# cube.net
KiCad netlist of a schematic drawn in EAGLE
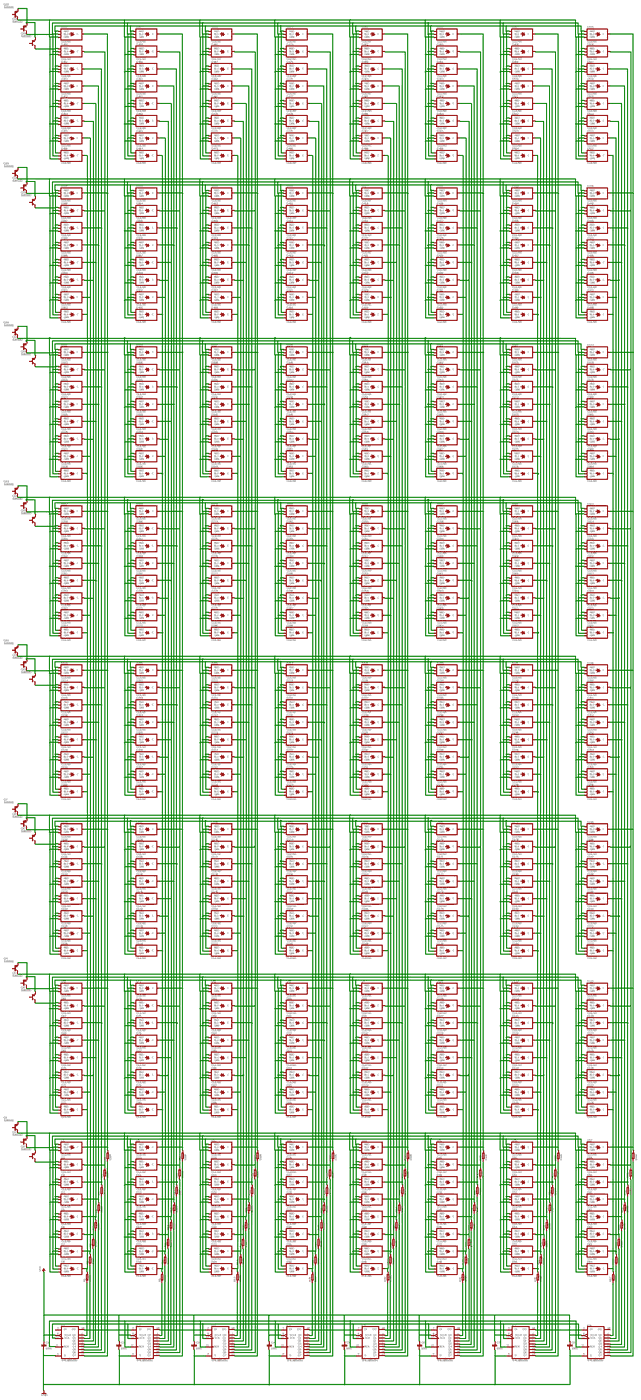
[diagram p0: schematic, sheet 1, overview]
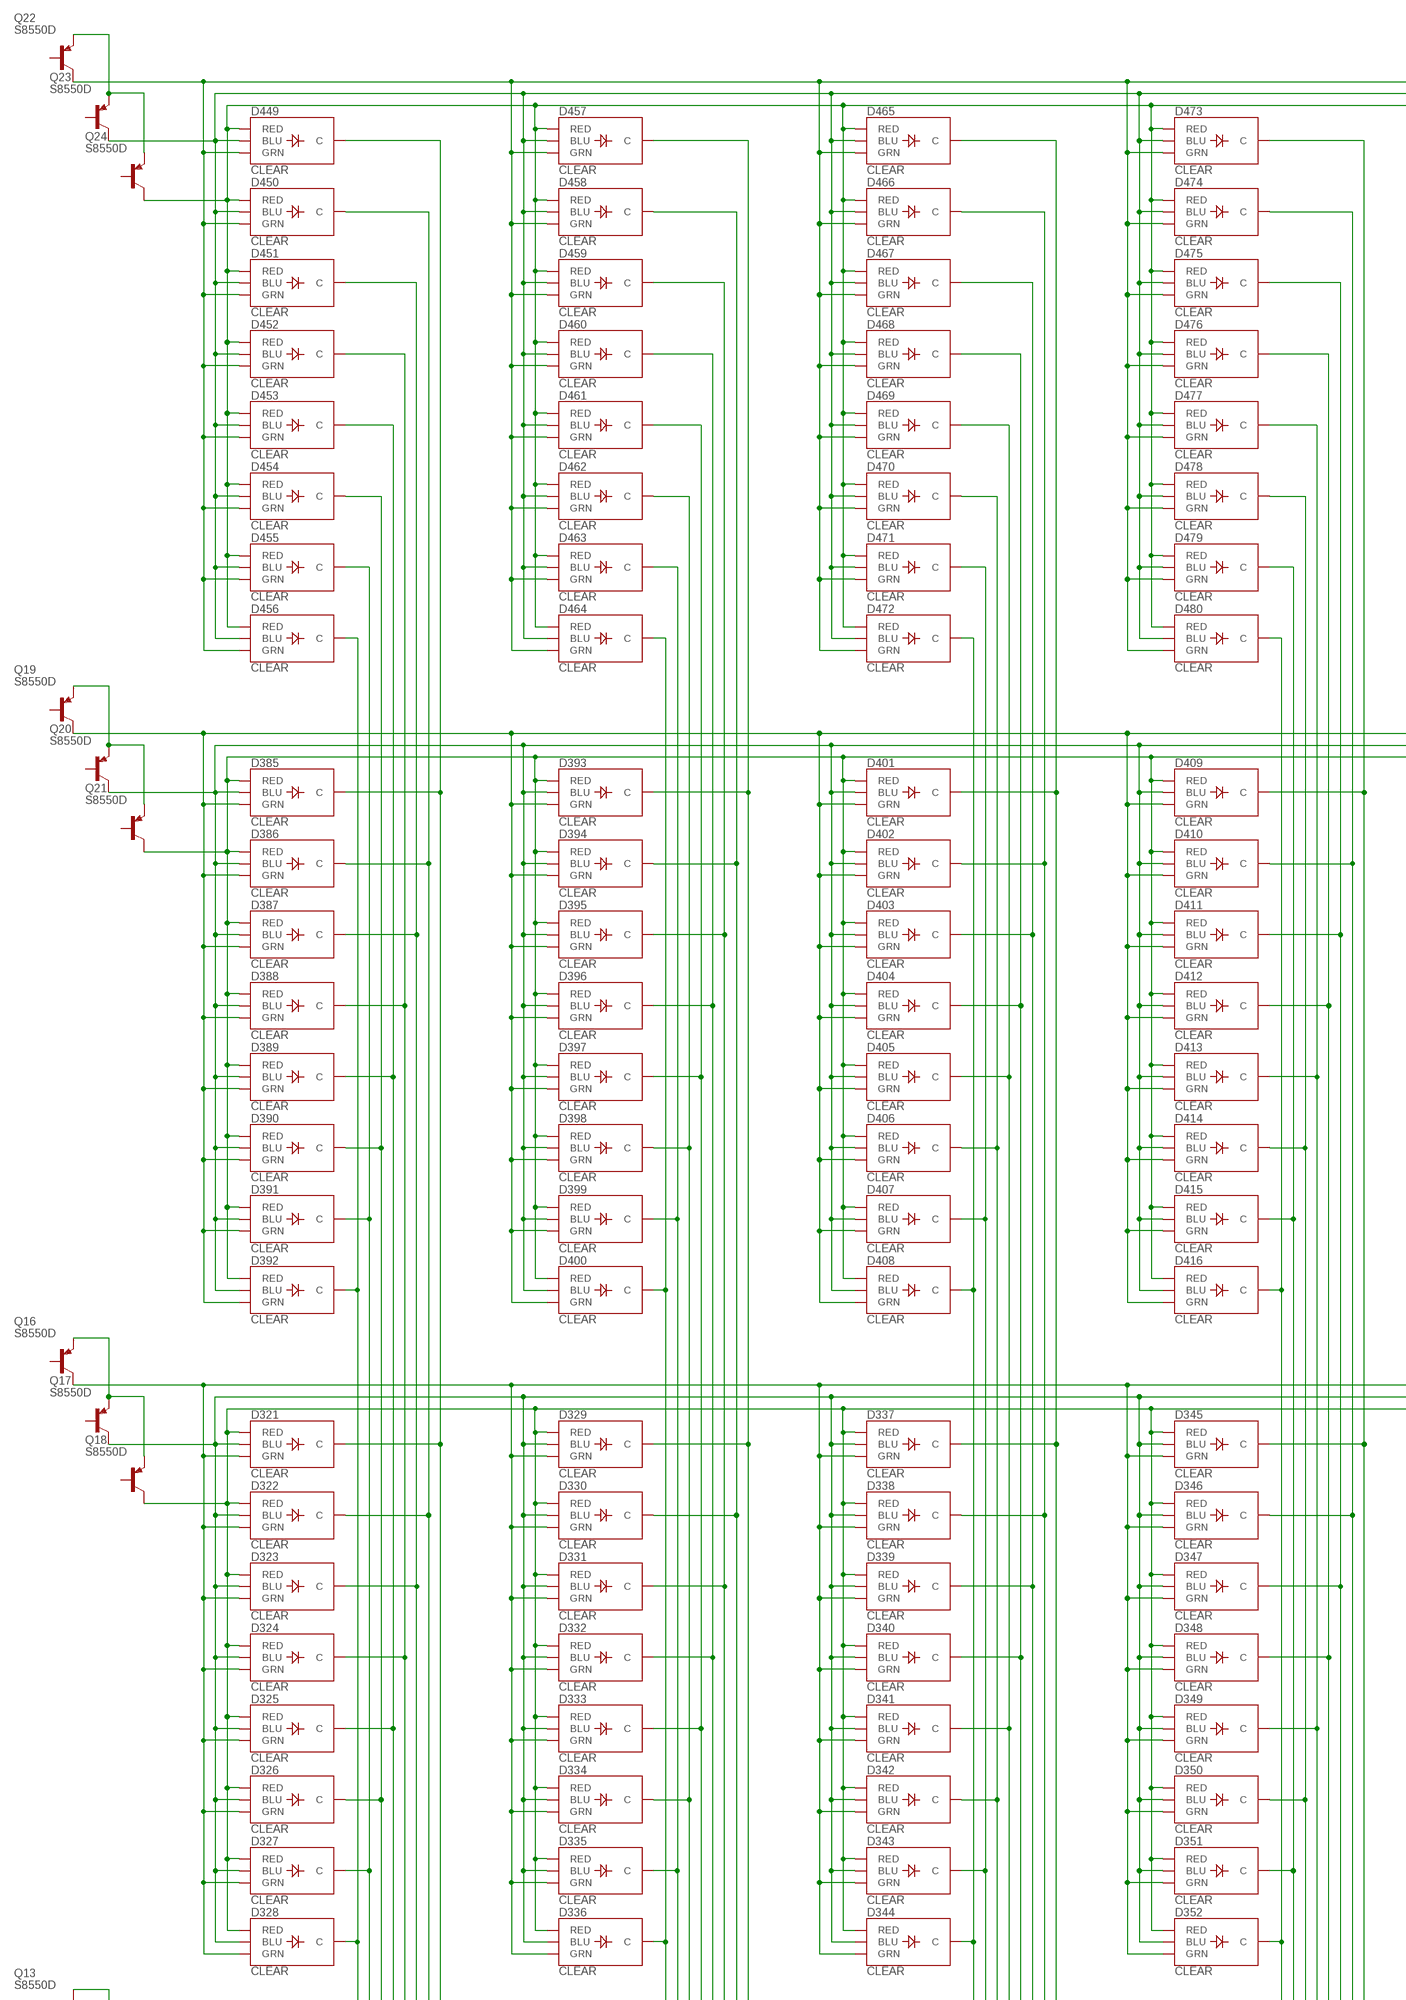
[diagram p1: schematic, sheet 1, part 1 of 8]
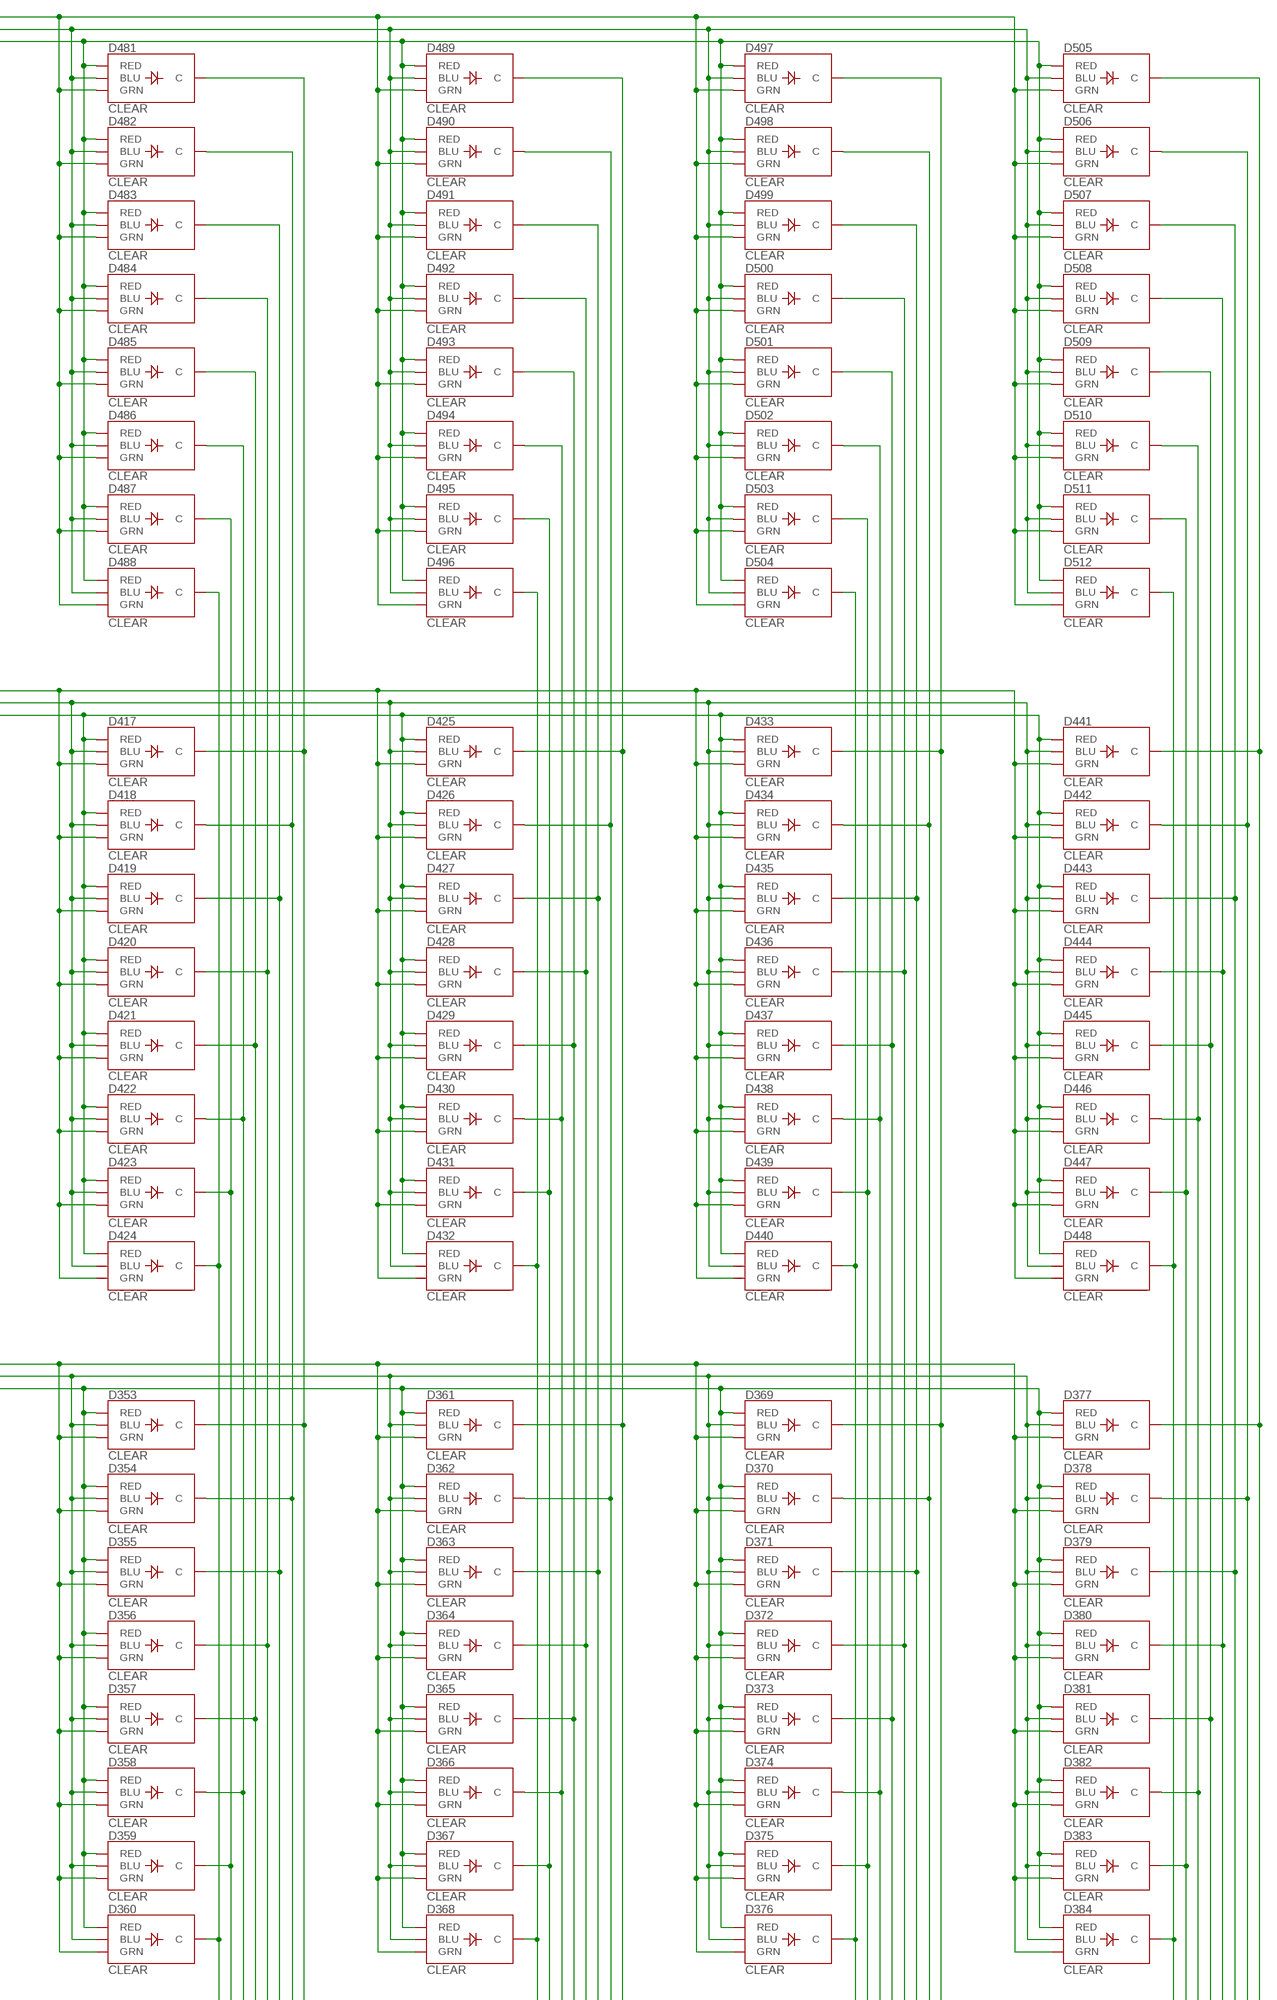
[diagram p2: schematic, sheet 1, part 2 of 8]
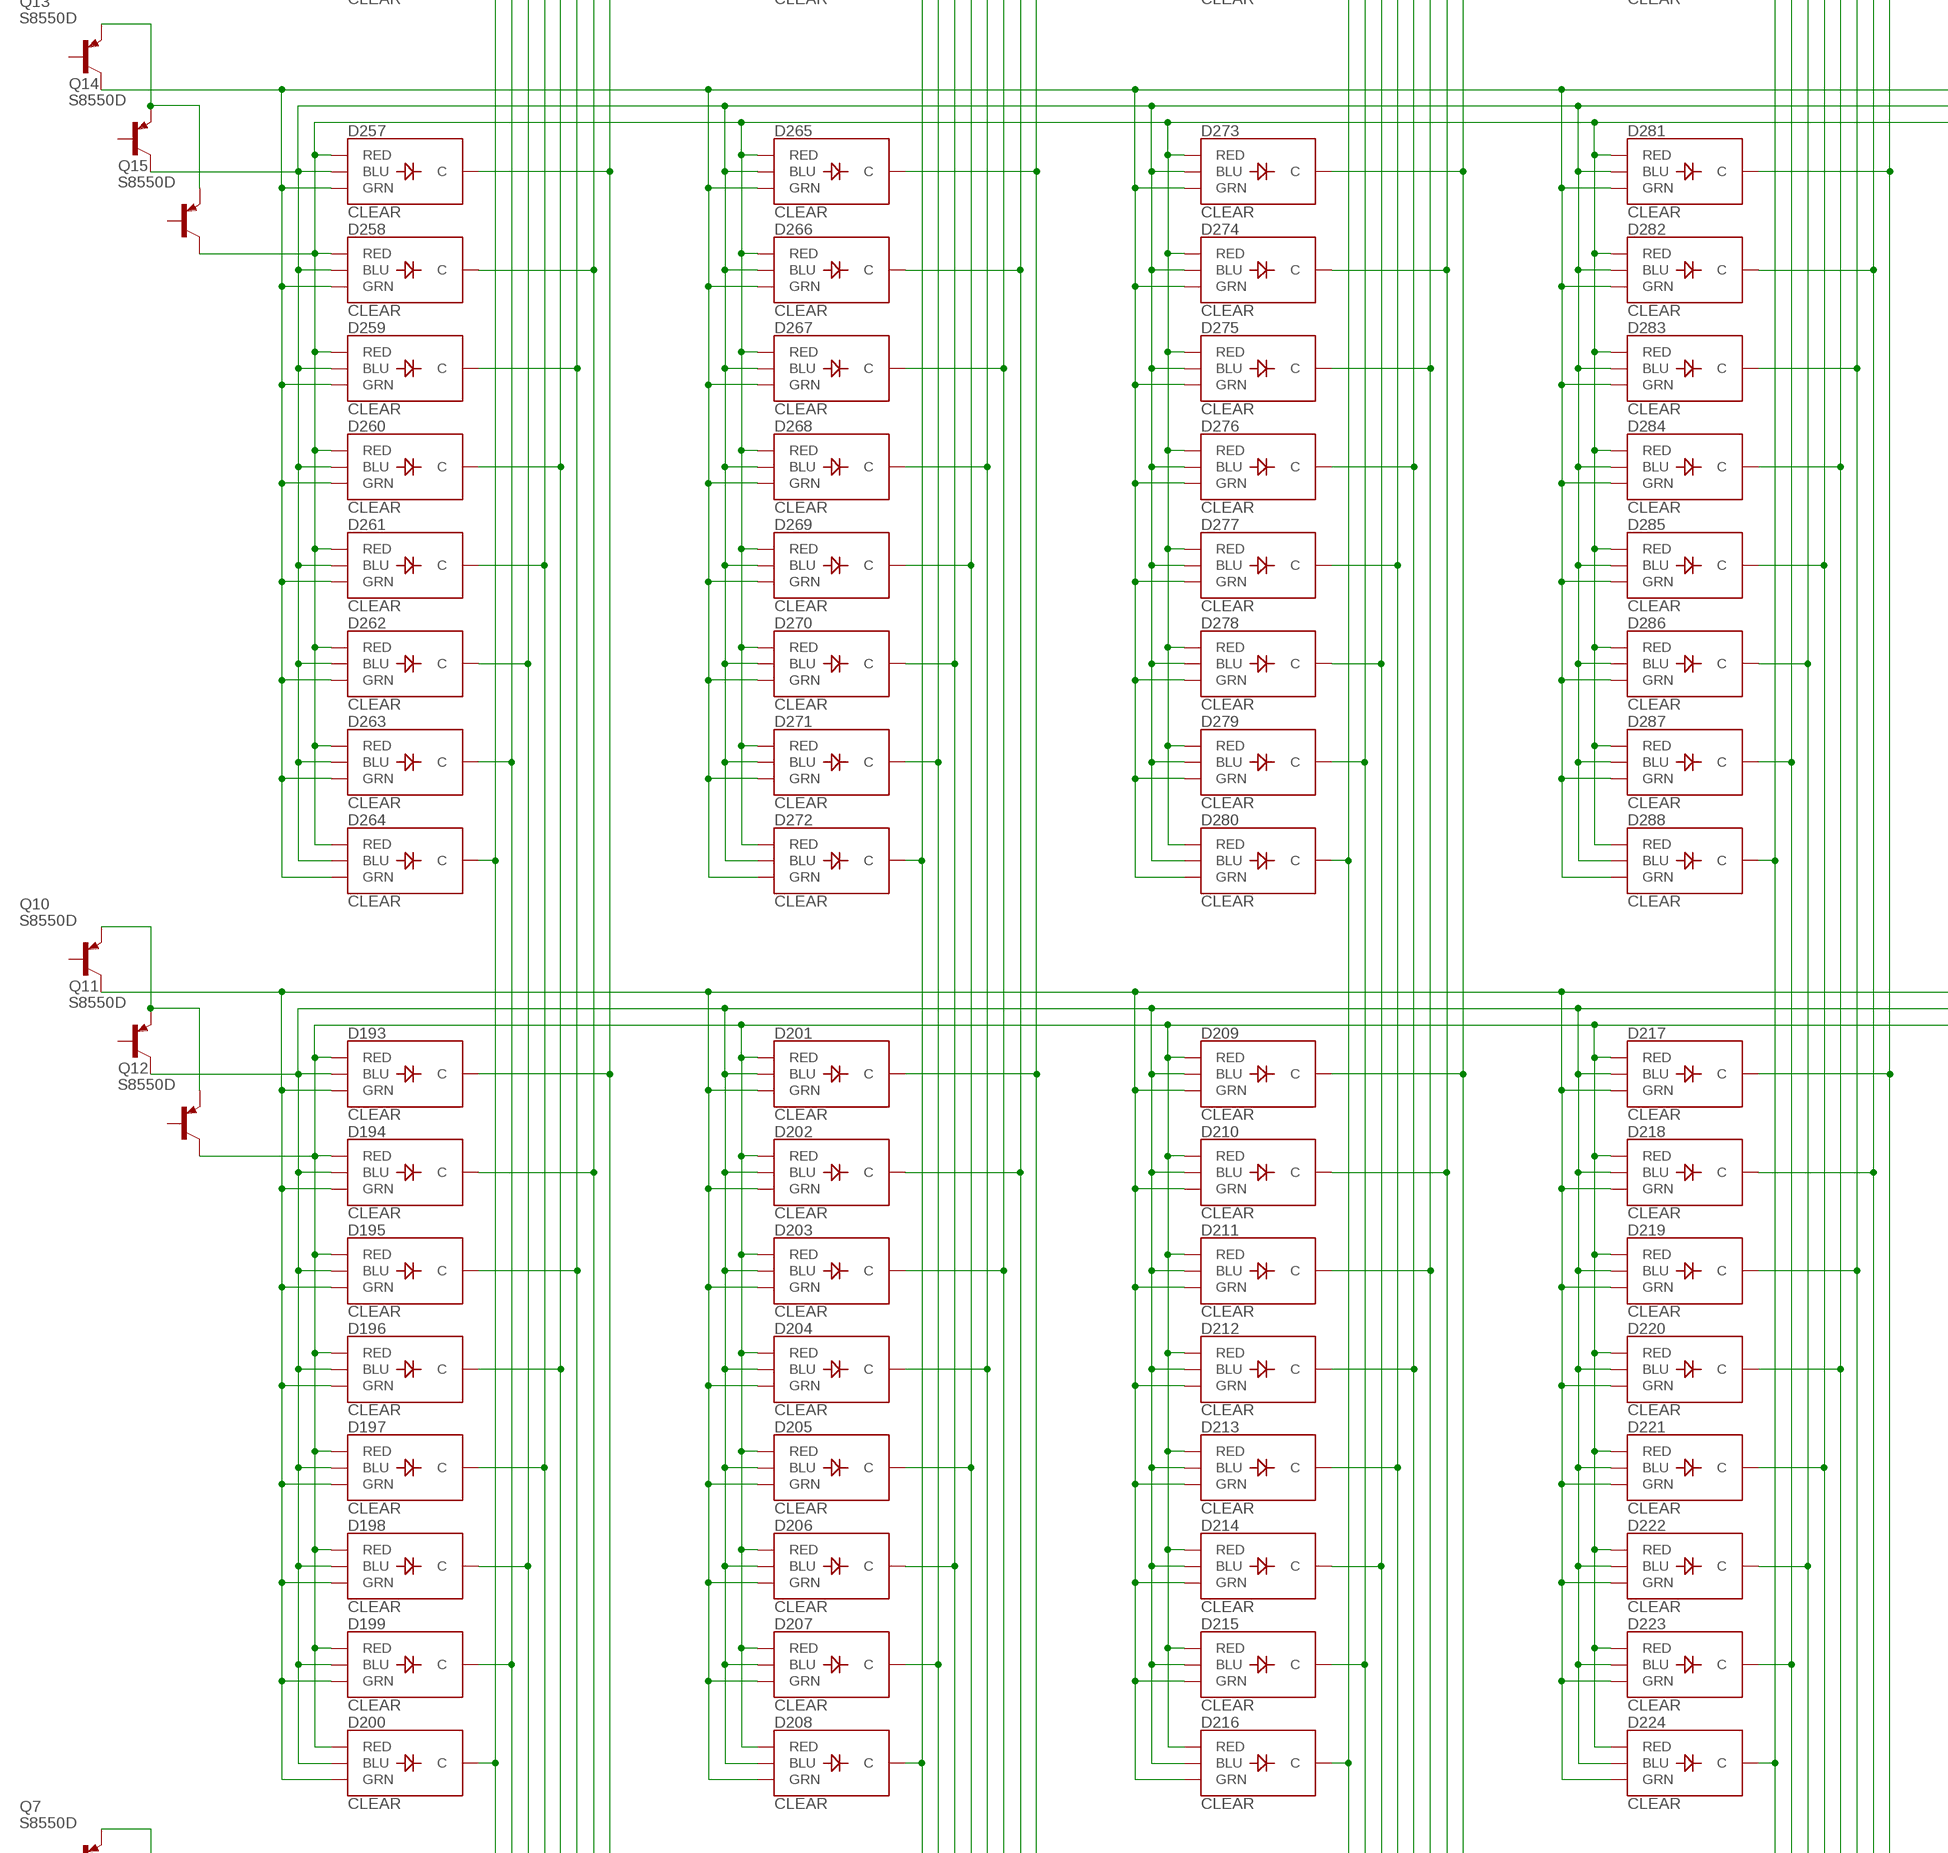
[diagram p3: schematic, sheet 1, part 3 of 8]
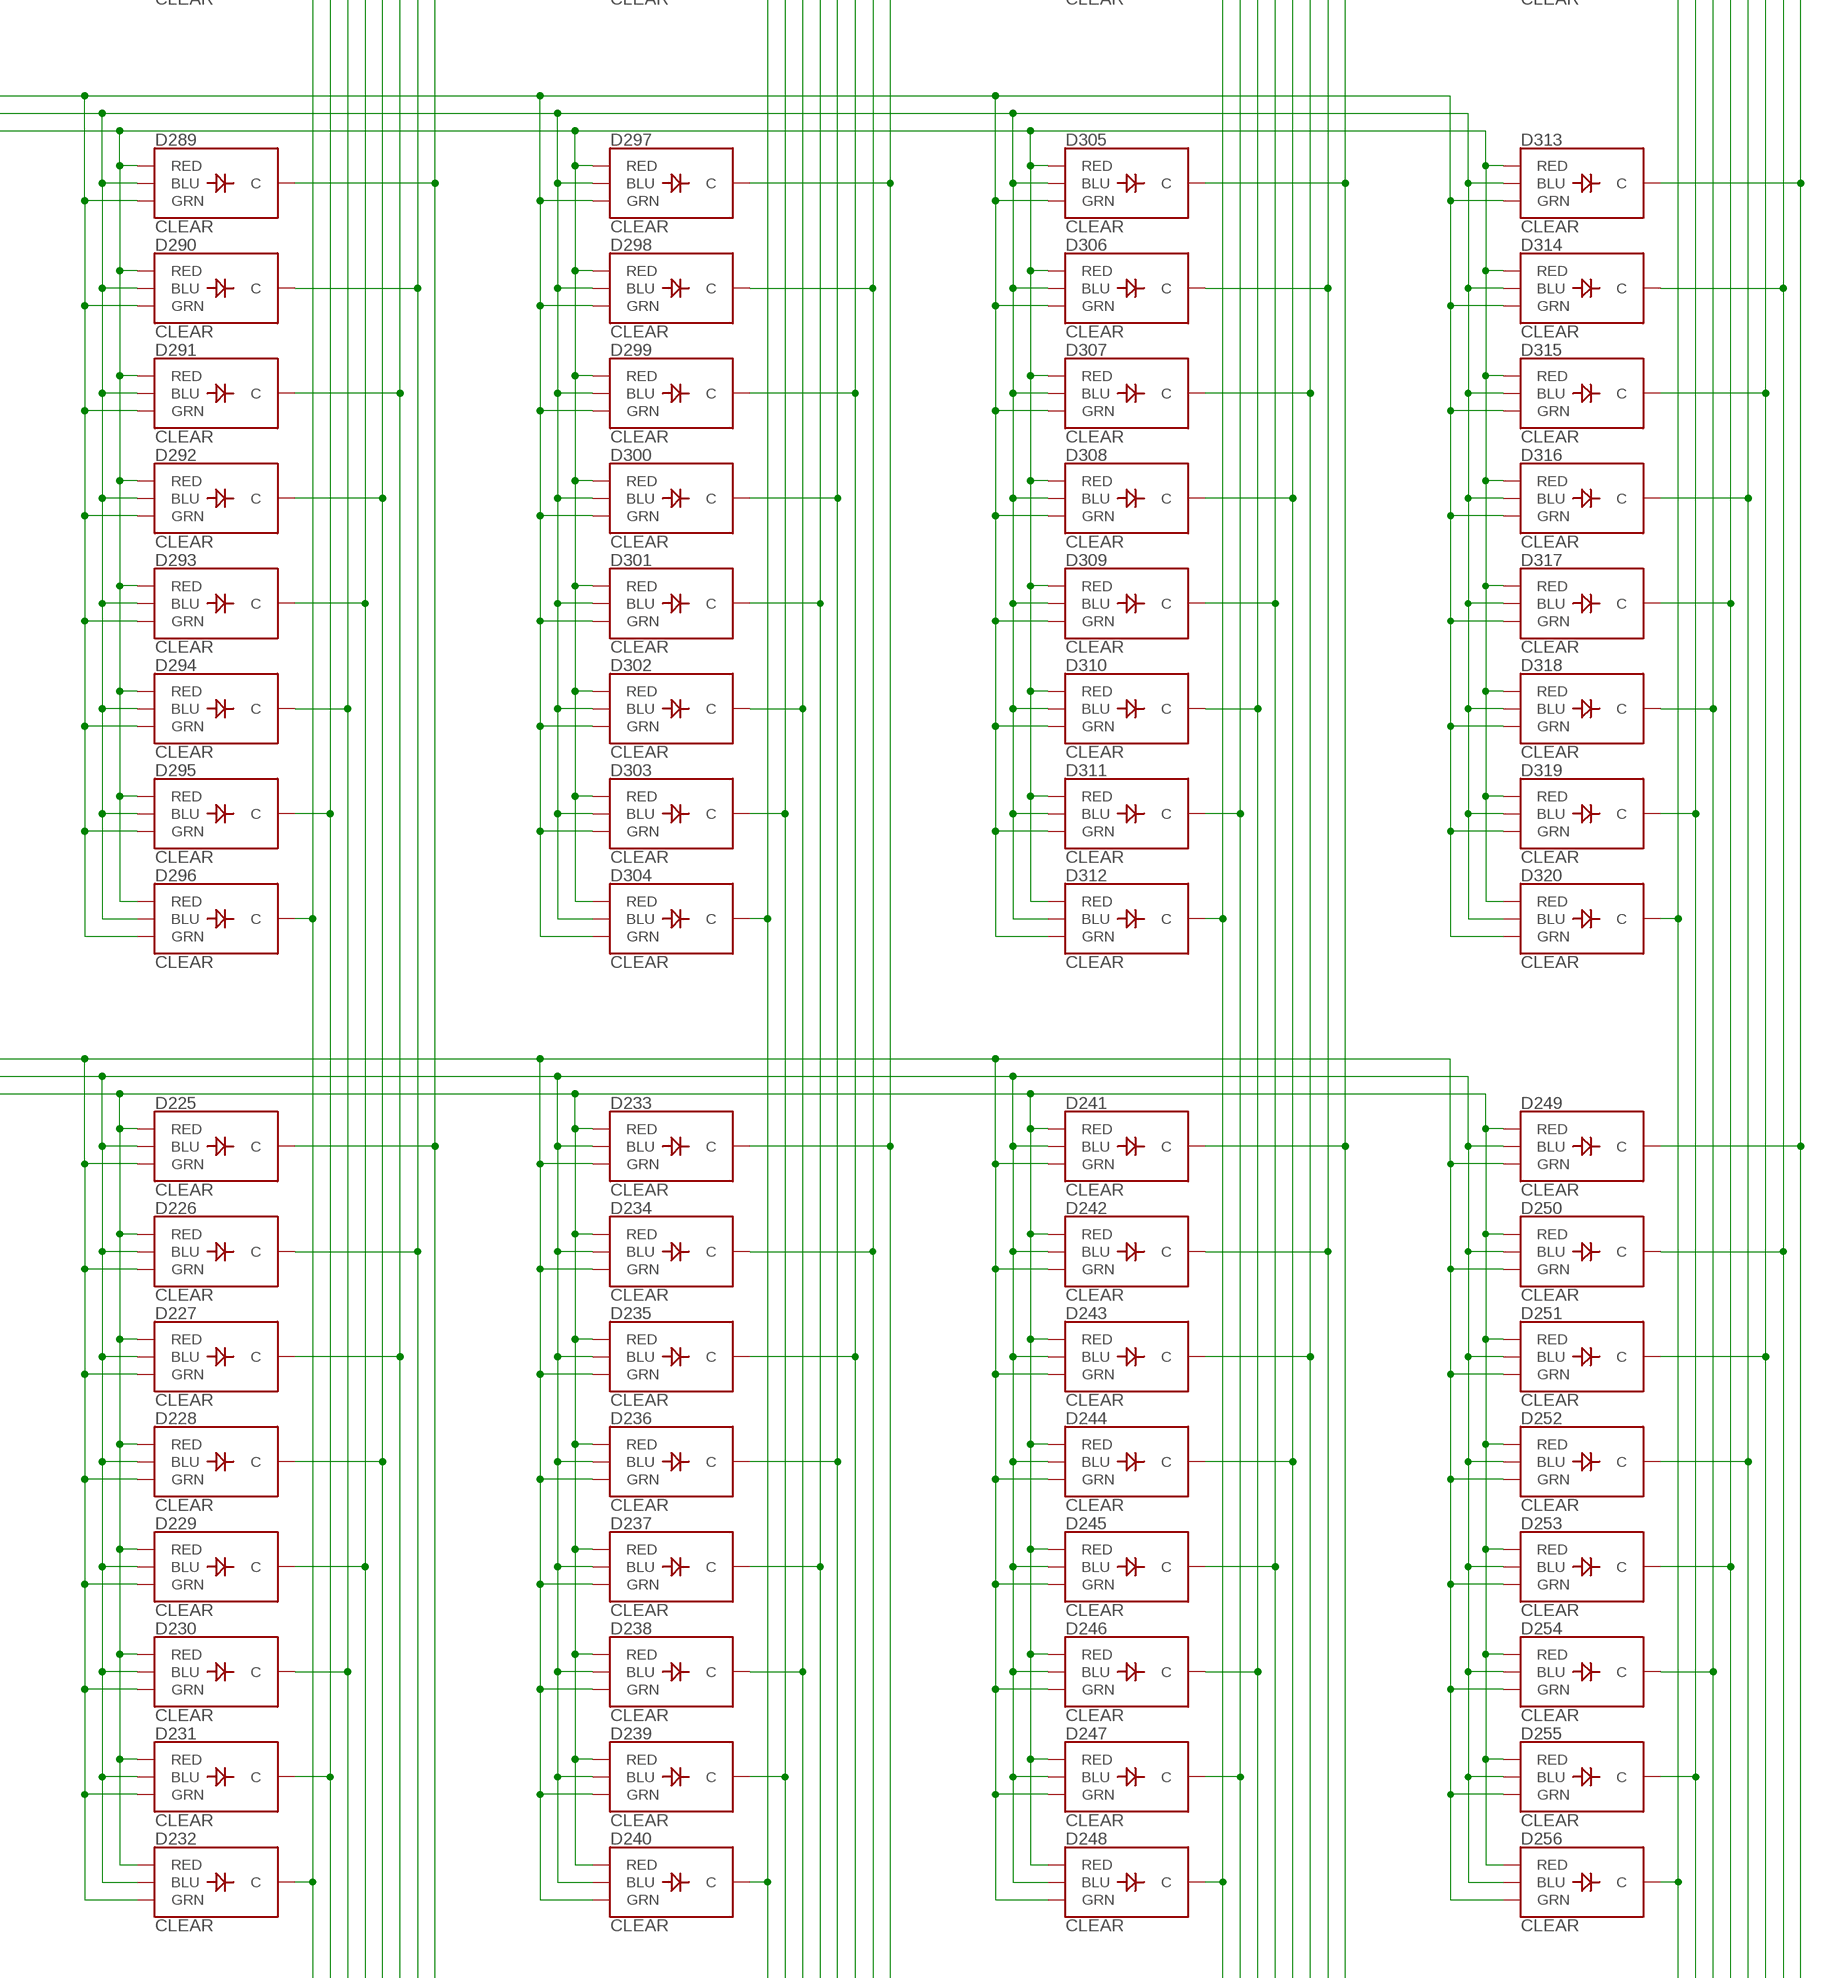
[diagram p4: schematic, sheet 1, part 4 of 8]
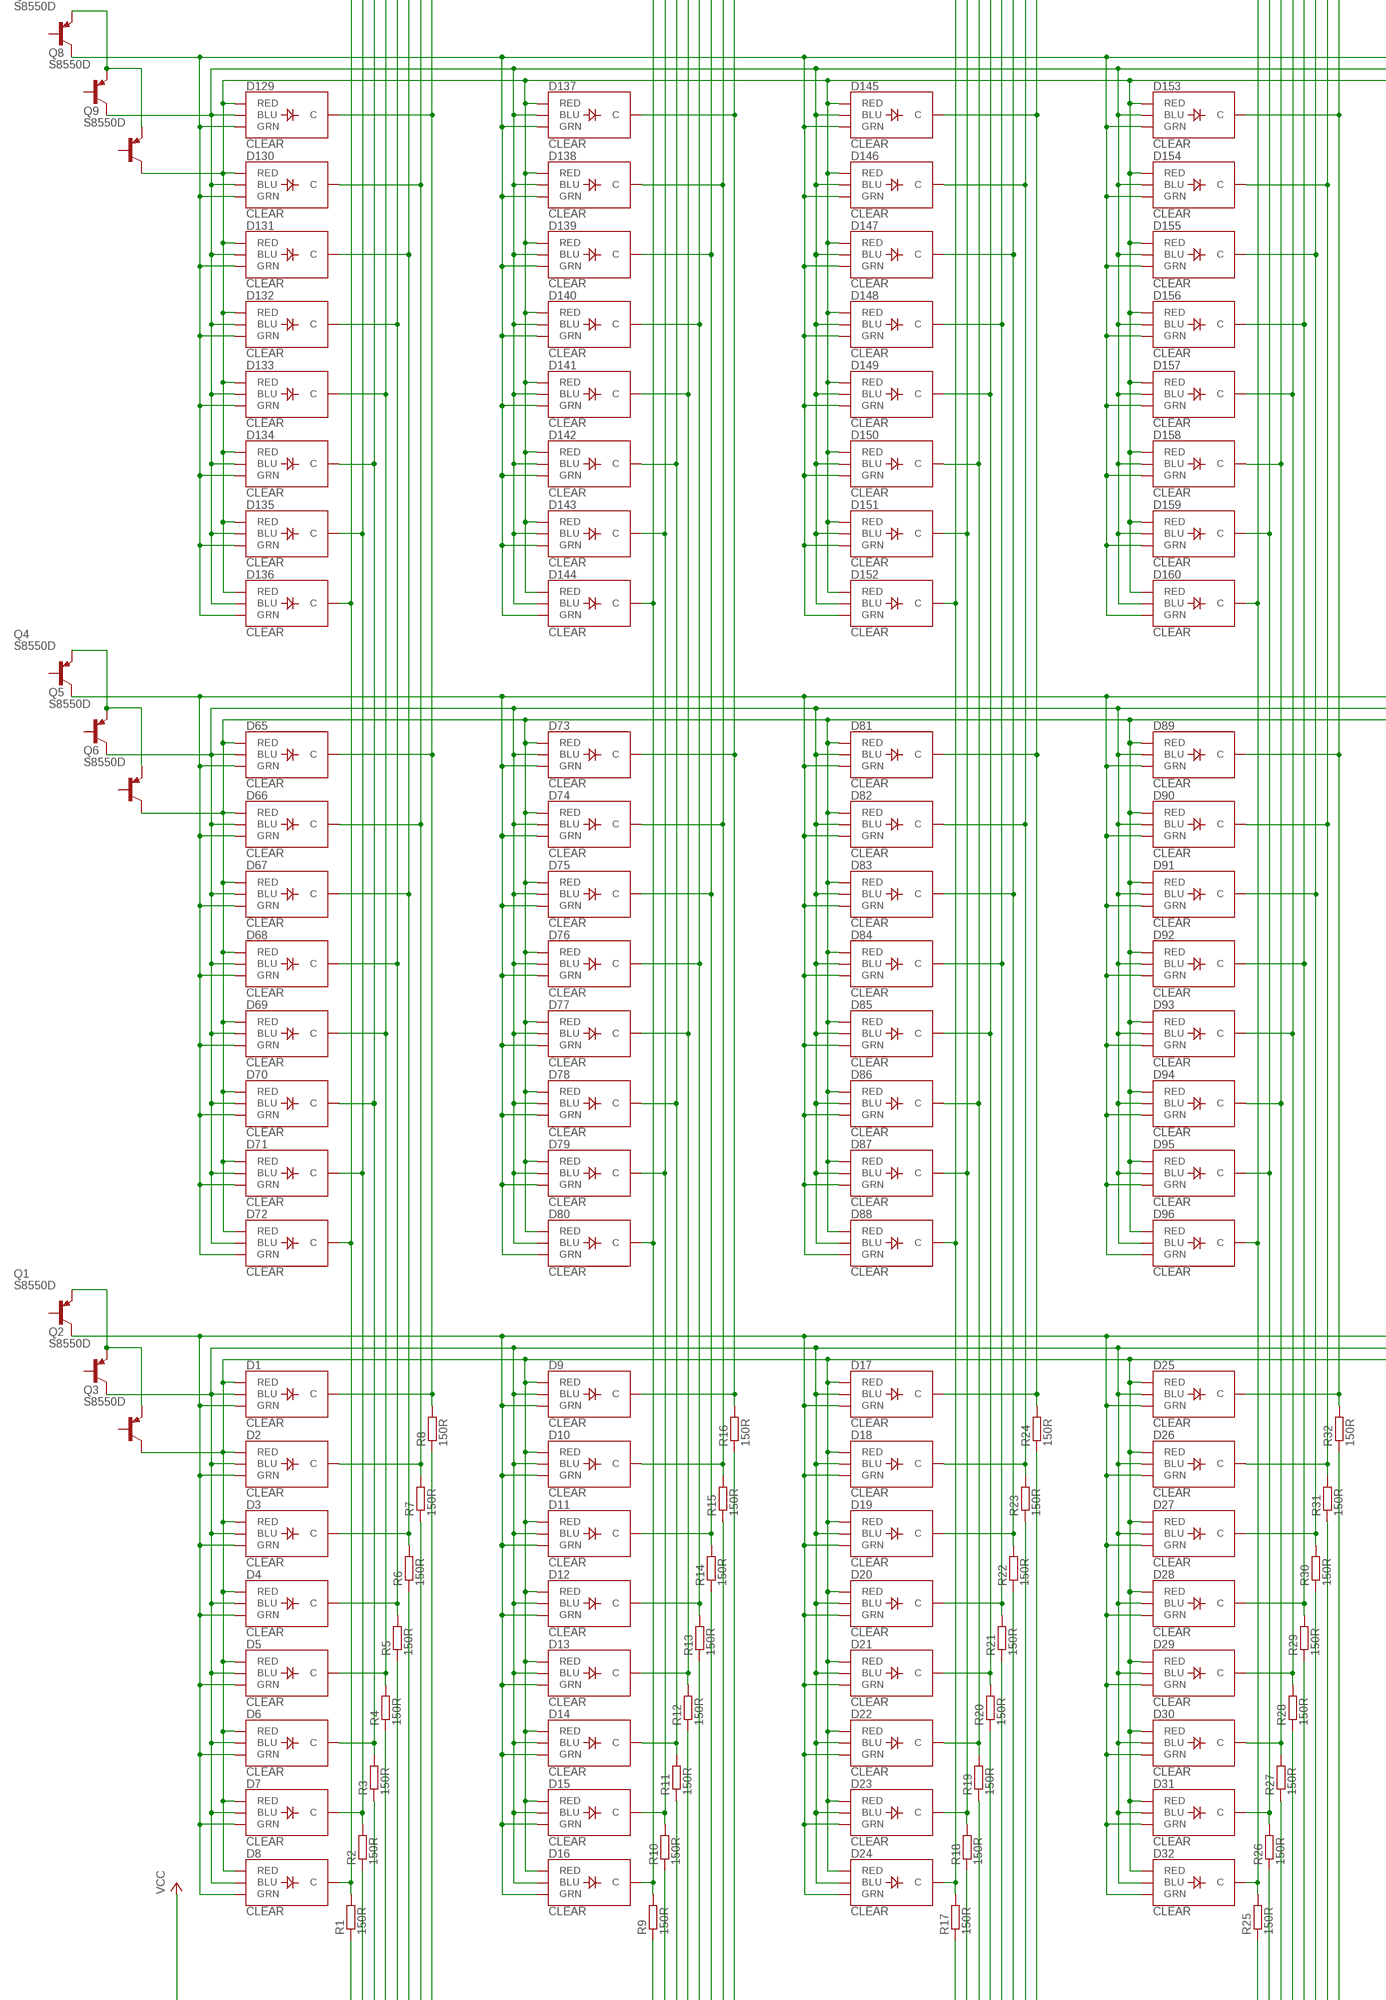
[diagram p5: schematic, sheet 1, part 5 of 8]
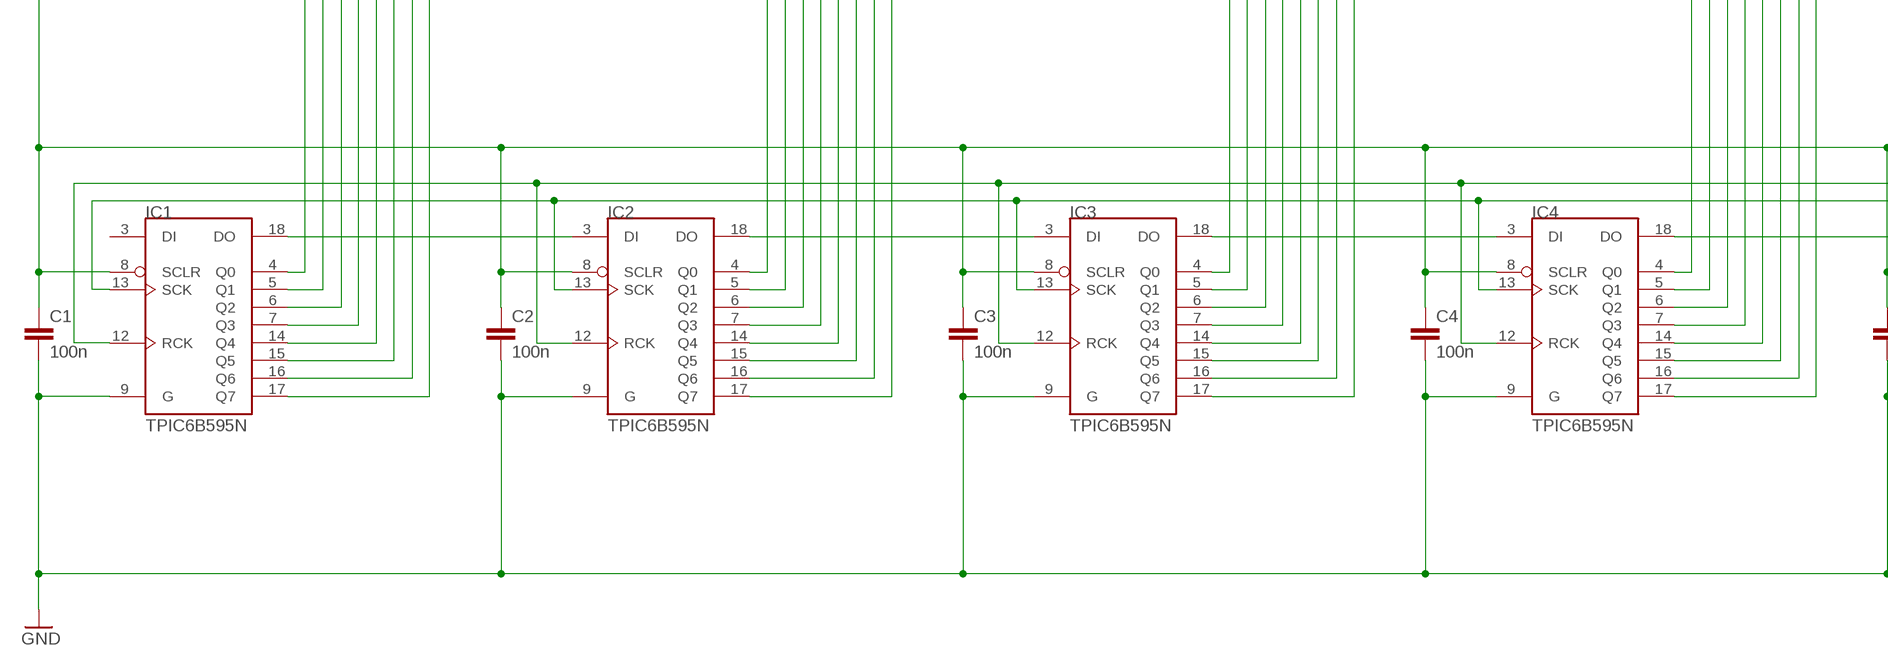
[diagram p6: schematic, sheet 1, part 6 of 8]
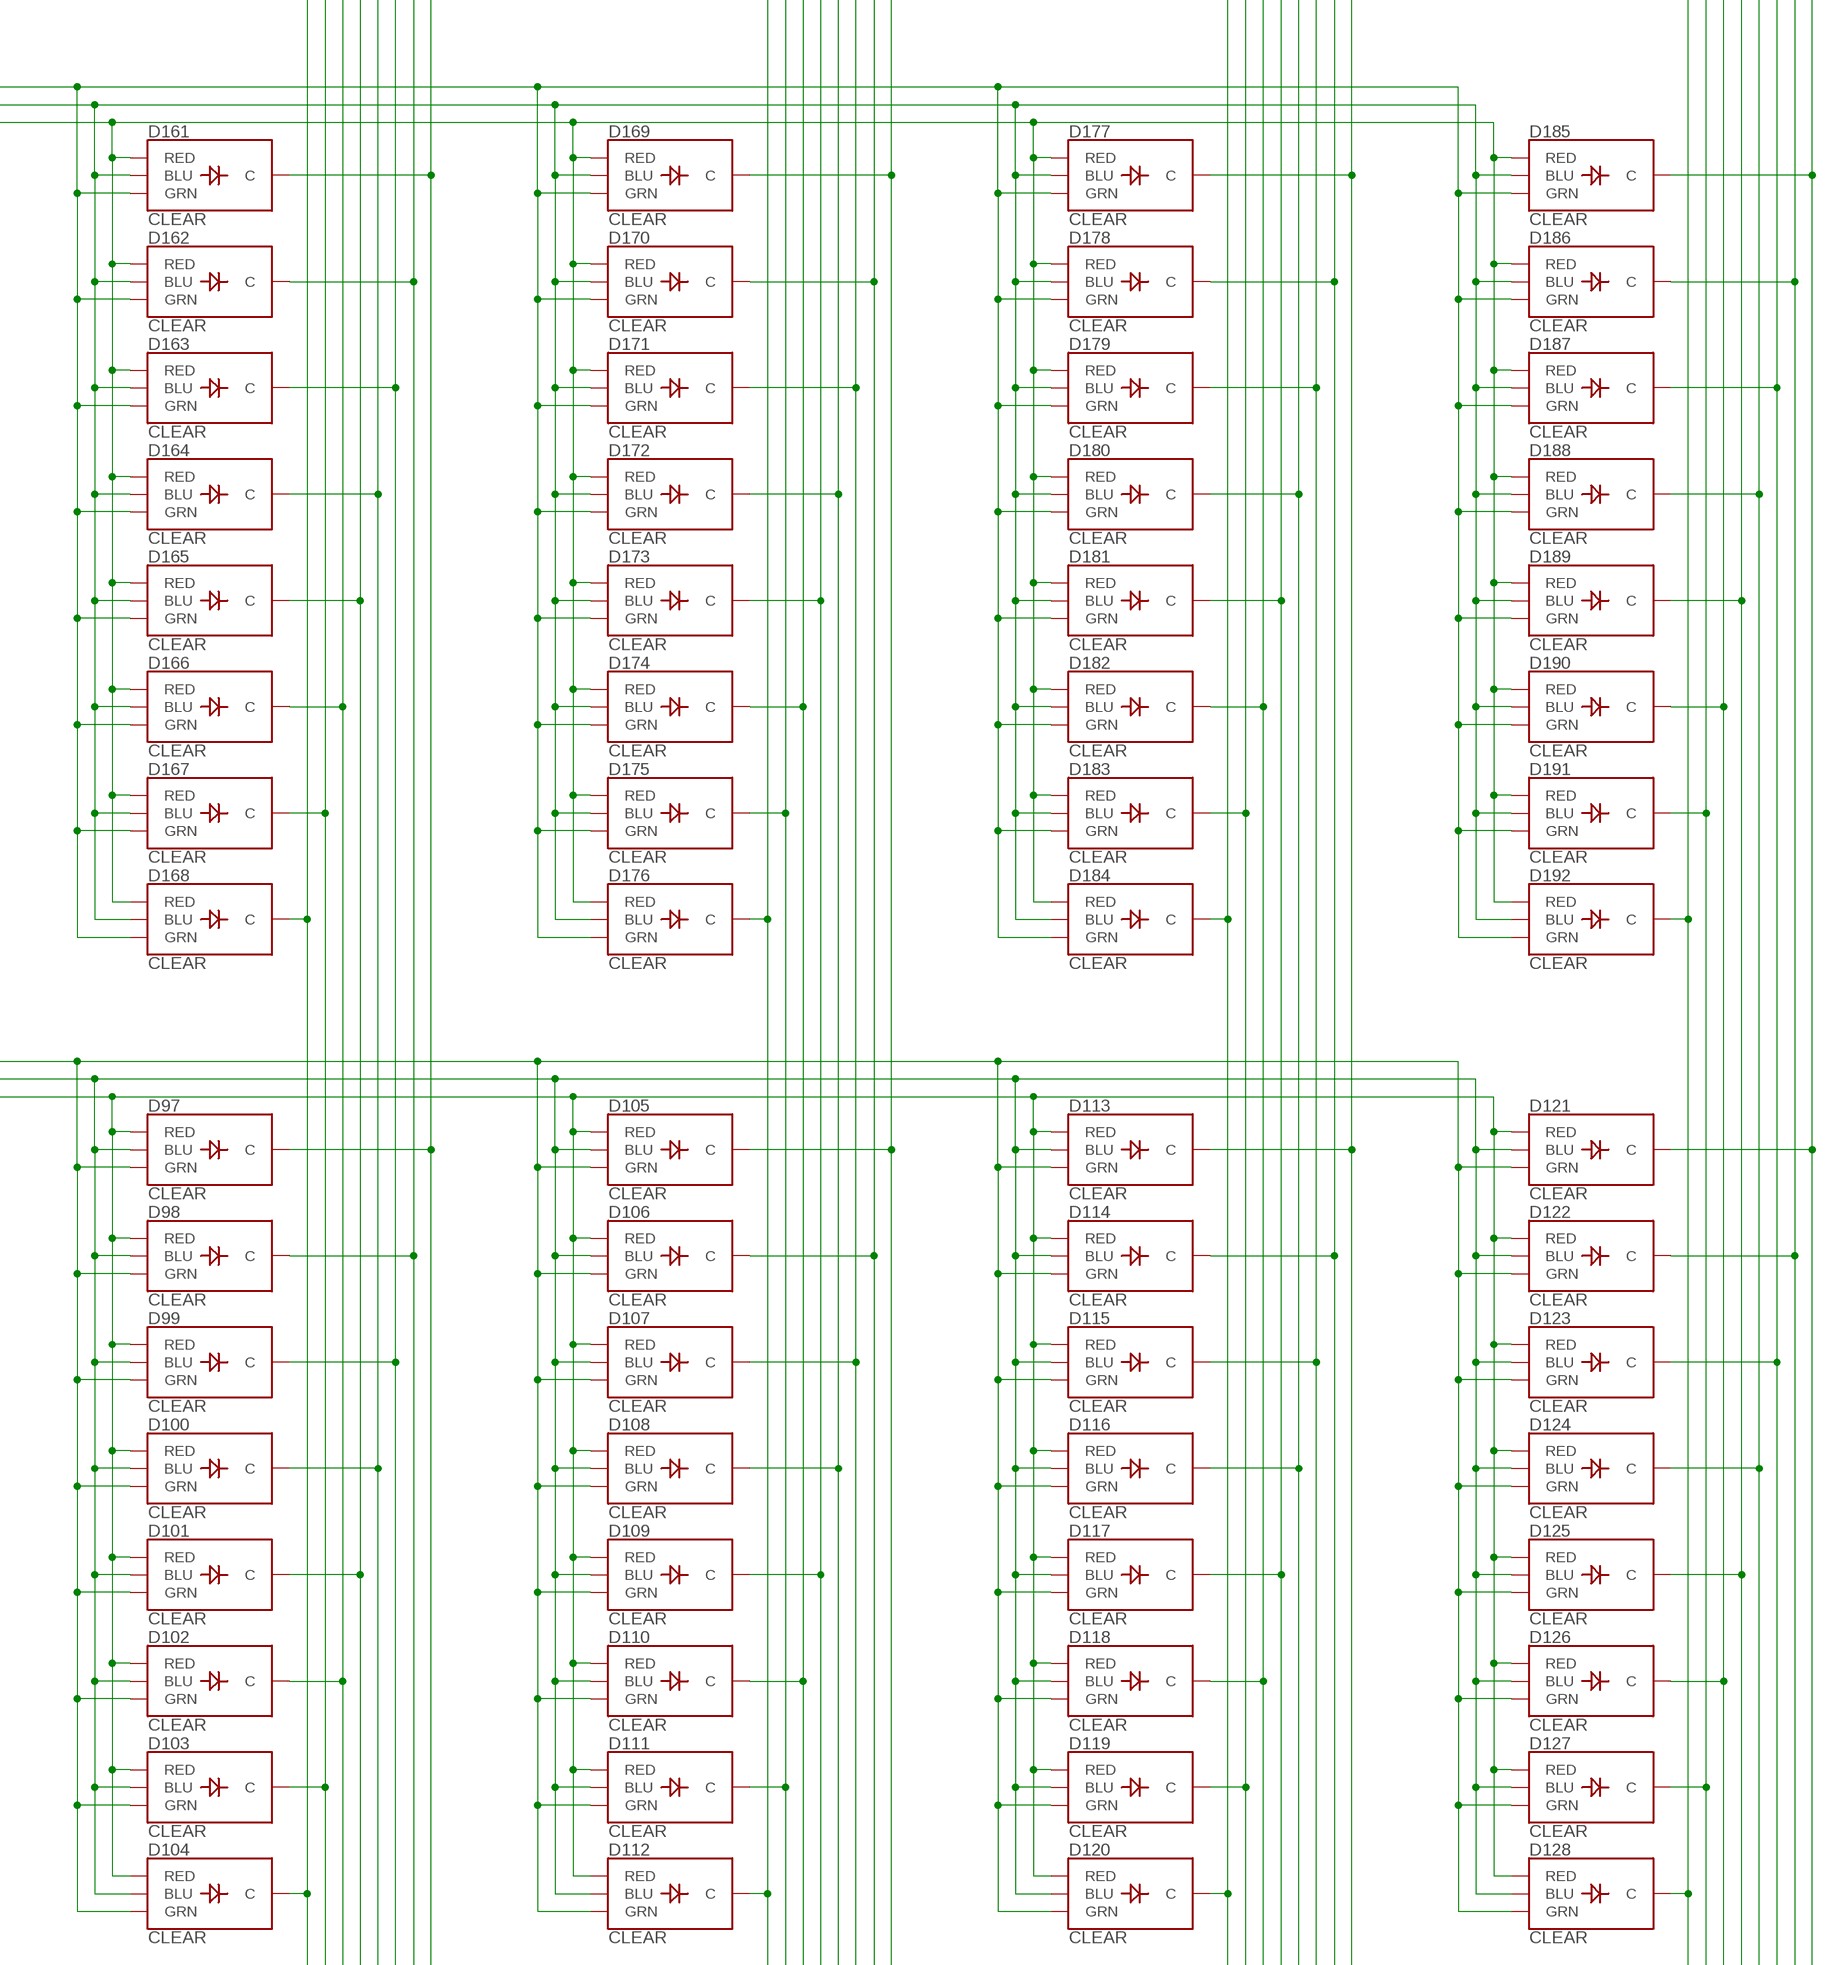
[diagram p7: schematic, sheet 1, part 7 of 8]
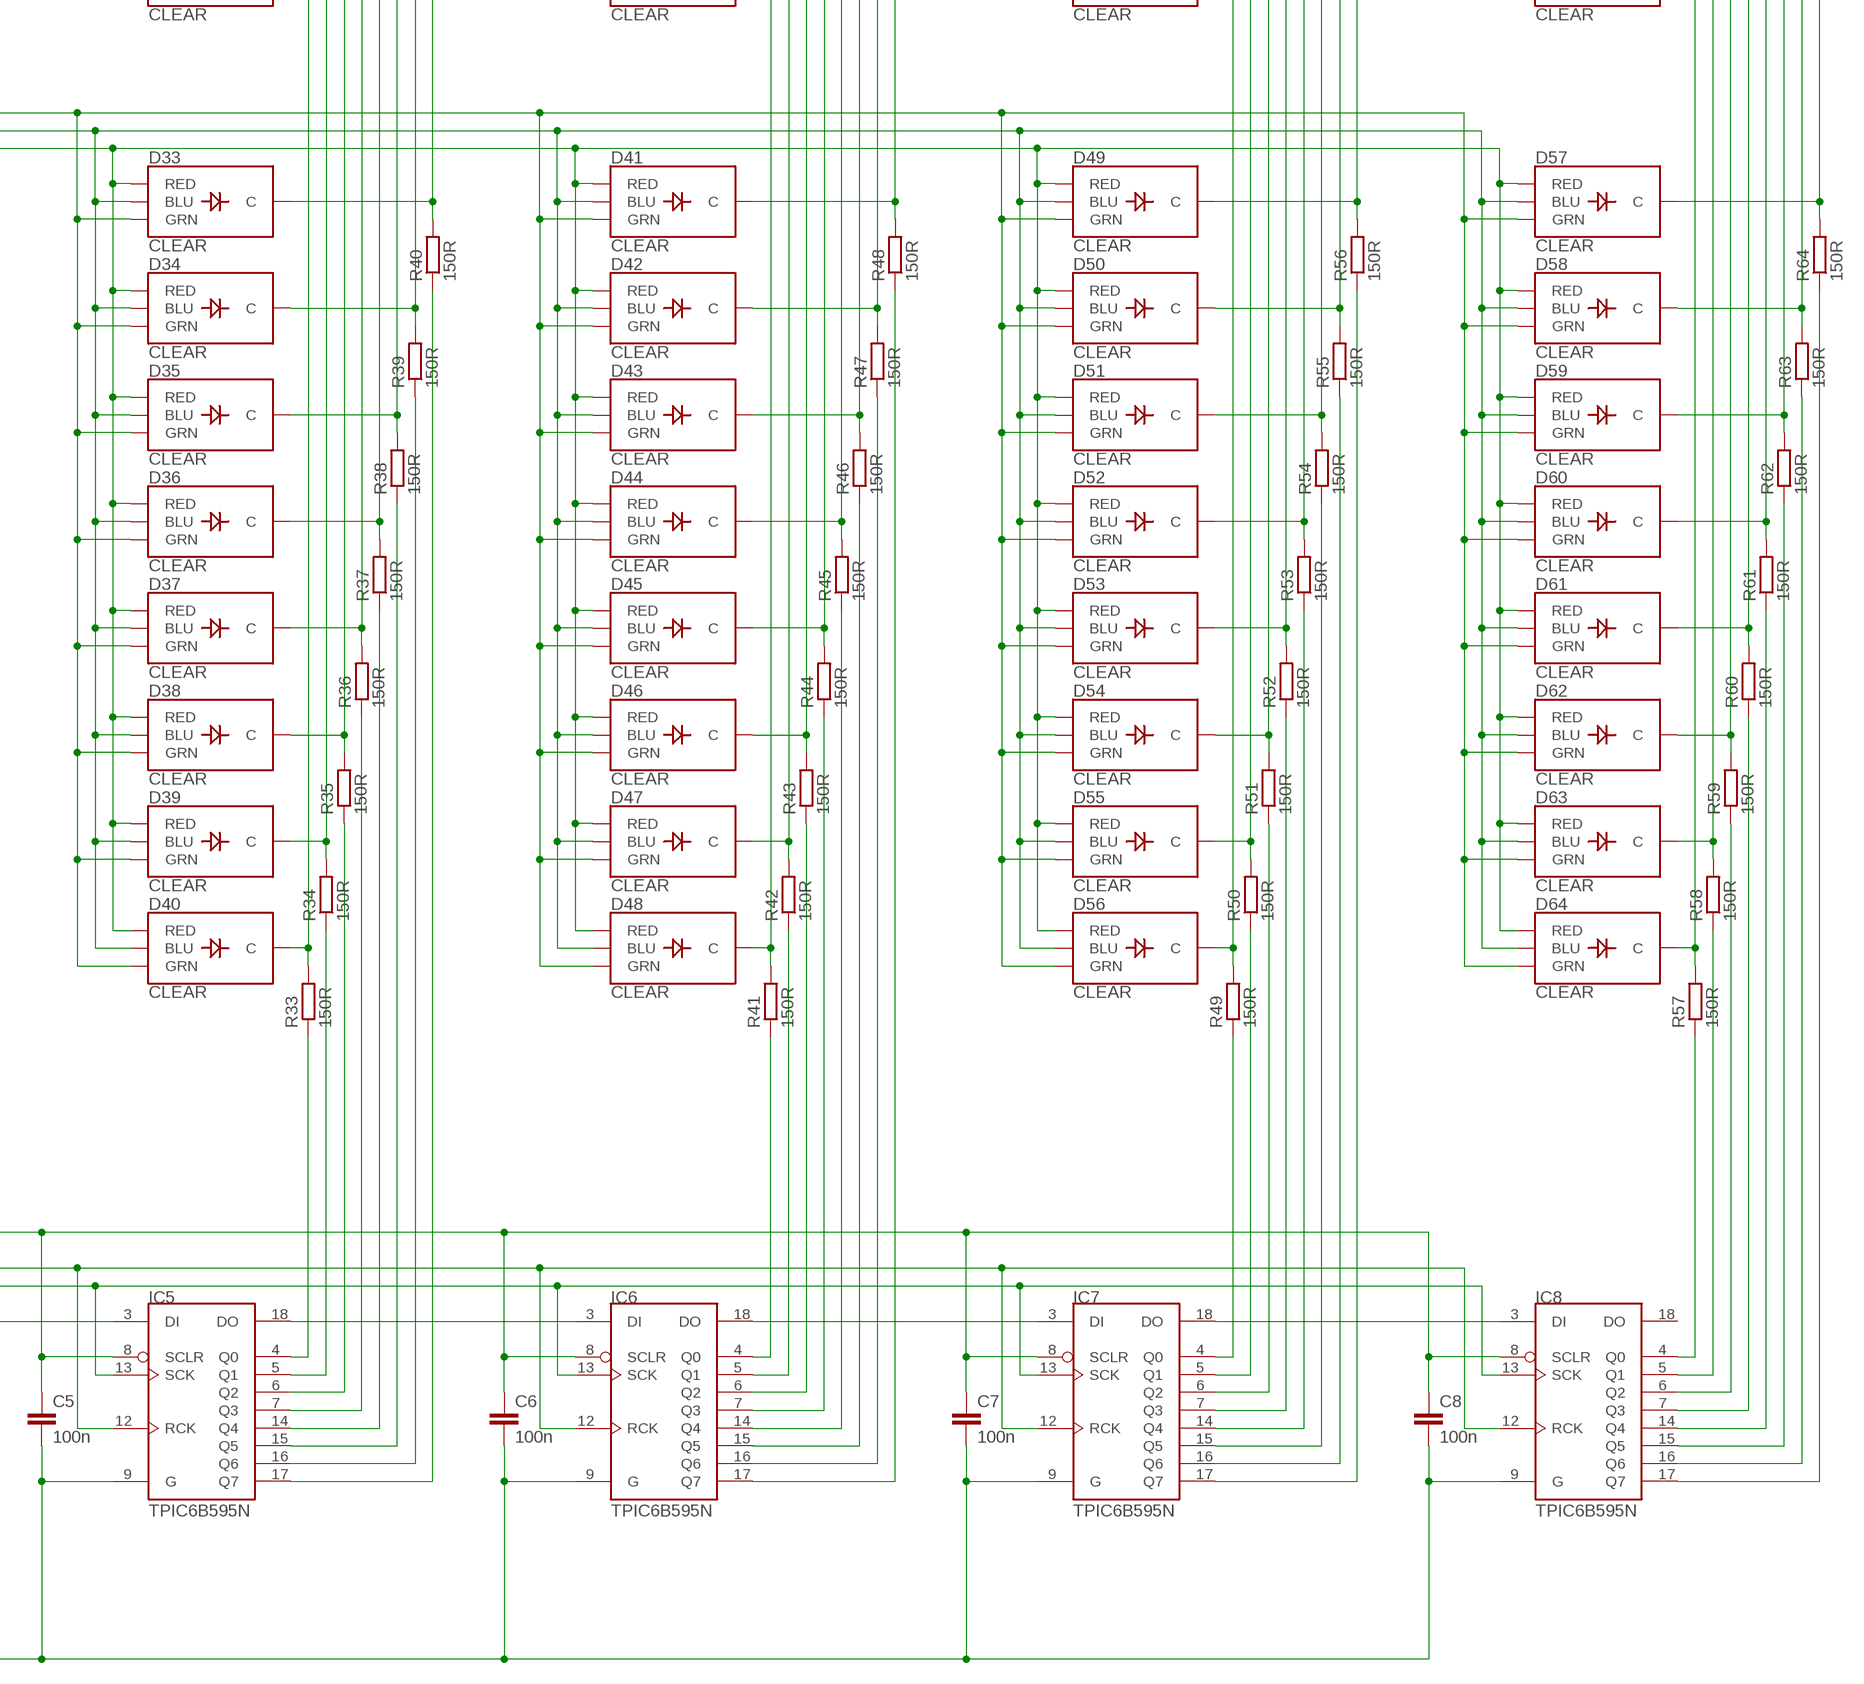
[diagram p8: schematic, sheet 1, part 8 of 8]

(export (version "E")
  (design (tool "Eeschema 10.0.6"))
  (components
    (comp (ref "C1")
      (value "100n")
      (footprint "eagle-import:C050-024X044")
      (libsource (lib "eagle-import") (part "C-EU050-024X044"))
    )
    (comp (ref "C2")
      (value "100n")
      (footprint "eagle-import:C050-024X044")
      (libsource (lib "eagle-import") (part "C-EU050-024X044"))
    )
    (comp (ref "C3")
      (value "100n")
      (footprint "eagle-import:C050-024X044")
      (libsource (lib "eagle-import") (part "C-EU050-024X044"))
    )
    (comp (ref "C4")
      (value "100n")
      (footprint "eagle-import:C050-024X044")
      (libsource (lib "eagle-import") (part "C-EU050-024X044"))
    )
    (comp (ref "C5")
      (value "100n")
      (footprint "eagle-import:C050-024X044")
      (libsource (lib "eagle-import") (part "C-EU050-024X044"))
    )
    (comp (ref "C6")
      (value "100n")
      (footprint "eagle-import:C050-024X044")
      (libsource (lib "eagle-import") (part "C-EU050-024X044"))
    )
    (comp (ref "C7")
      (value "100n")
      (footprint "eagle-import:C050-024X044")
      (libsource (lib "eagle-import") (part "C-EU050-024X044"))
    )
    (comp (ref "C8")
      (value "100n")
      (footprint "eagle-import:C050-024X044")
      (libsource (lib "eagle-import") (part "C-EU050-024X044"))
    )
    (comp (ref "D1")
      (value "CLEAR")
      (footprint "eagle-import:LED-RGB-THRU")
      (libsource (lib "eagle-import") (part "LED-RGB-CCCLEAR"))
    )
    (comp (ref "D2")
      (value "CLEAR")
      (footprint "eagle-import:LED-RGB-THRU")
      (libsource (lib "eagle-import") (part "LED-RGB-CCCLEAR"))
    )
    (comp (ref "D3")
      (value "CLEAR")
      (footprint "eagle-import:LED-RGB-THRU")
      (libsource (lib "eagle-import") (part "LED-RGB-CCCLEAR"))
    )
    (comp (ref "D4")
      (value "CLEAR")
      (footprint "eagle-import:LED-RGB-THRU")
      (libsource (lib "eagle-import") (part "LED-RGB-CCCLEAR"))
    )
    (comp (ref "D5")
      (value "CLEAR")
      (footprint "eagle-import:LED-RGB-THRU")
      (libsource (lib "eagle-import") (part "LED-RGB-CCCLEAR"))
    )
    (comp (ref "D6")
      (value "CLEAR")
      (footprint "eagle-import:LED-RGB-THRU")
      (libsource (lib "eagle-import") (part "LED-RGB-CCCLEAR"))
    )
    (comp (ref "D7")
      (value "CLEAR")
      (footprint "eagle-import:LED-RGB-THRU")
      (libsource (lib "eagle-import") (part "LED-RGB-CCCLEAR"))
    )
    (comp (ref "D8")
      (value "CLEAR")
      (footprint "eagle-import:LED-RGB-THRU")
      (libsource (lib "eagle-import") (part "LED-RGB-CCCLEAR"))
    )
    (comp (ref "D9")
      (value "CLEAR")
      (footprint "eagle-import:LED-RGB-THRU")
      (libsource (lib "eagle-import") (part "LED-RGB-CCCLEAR"))
    )
    (comp (ref "D10")
      (value "CLEAR")
      (footprint "eagle-import:LED-RGB-THRU")
      (libsource (lib "eagle-import") (part "LED-RGB-CCCLEAR"))
    )
    (comp (ref "D11")
      (value "CLEAR")
      (footprint "eagle-import:LED-RGB-THRU")
      (libsource (lib "eagle-import") (part "LED-RGB-CCCLEAR"))
    )
    (comp (ref "D12")
      (value "CLEAR")
      (footprint "eagle-import:LED-RGB-THRU")
      (libsource (lib "eagle-import") (part "LED-RGB-CCCLEAR"))
    )
    (comp (ref "D13")
      (value "CLEAR")
      (footprint "eagle-import:LED-RGB-THRU")
      (libsource (lib "eagle-import") (part "LED-RGB-CCCLEAR"))
    )
    (comp (ref "D14")
      (value "CLEAR")
      (footprint "eagle-import:LED-RGB-THRU")
      (libsource (lib "eagle-import") (part "LED-RGB-CCCLEAR"))
    )
    (comp (ref "D15")
      (value "CLEAR")
      (footprint "eagle-import:LED-RGB-THRU")
      (libsource (lib "eagle-import") (part "LED-RGB-CCCLEAR"))
    )
    (comp (ref "D16")
      (value "CLEAR")
      (footprint "eagle-import:LED-RGB-THRU")
      (libsource (lib "eagle-import") (part "LED-RGB-CCCLEAR"))
    )
    (comp (ref "D17")
      (value "CLEAR")
      (footprint "eagle-import:LED-RGB-THRU")
      (libsource (lib "eagle-import") (part "LED-RGB-CCCLEAR"))
    )
    (comp (ref "D18")
      (value "CLEAR")
      (footprint "eagle-import:LED-RGB-THRU")
      (libsource (lib "eagle-import") (part "LED-RGB-CCCLEAR"))
    )
    (comp (ref "D19")
      (value "CLEAR")
      (footprint "eagle-import:LED-RGB-THRU")
      (libsource (lib "eagle-import") (part "LED-RGB-CCCLEAR"))
    )
    (comp (ref "D20")
      (value "CLEAR")
      (footprint "eagle-import:LED-RGB-THRU")
      (libsource (lib "eagle-import") (part "LED-RGB-CCCLEAR"))
    )
    (comp (ref "D21")
      (value "CLEAR")
      (footprint "eagle-import:LED-RGB-THRU")
      (libsource (lib "eagle-import") (part "LED-RGB-CCCLEAR"))
    )
    (comp (ref "D22")
      (value "CLEAR")
      (footprint "eagle-import:LED-RGB-THRU")
      (libsource (lib "eagle-import") (part "LED-RGB-CCCLEAR"))
    )
    (comp (ref "D23")
      (value "CLEAR")
      (footprint "eagle-import:LED-RGB-THRU")
      (libsource (lib "eagle-import") (part "LED-RGB-CCCLEAR"))
    )
    (comp (ref "D24")
      (value "CLEAR")
      (footprint "eagle-import:LED-RGB-THRU")
      (libsource (lib "eagle-import") (part "LED-RGB-CCCLEAR"))
    )
    (comp (ref "D25")
      (value "CLEAR")
      (footprint "eagle-import:LED-RGB-THRU")
      (libsource (lib "eagle-import") (part "LED-RGB-CCCLEAR"))
    )
    (comp (ref "D26")
      (value "CLEAR")
      (footprint "eagle-import:LED-RGB-THRU")
      (libsource (lib "eagle-import") (part "LED-RGB-CCCLEAR"))
    )
    (comp (ref "D27")
      (value "CLEAR")
      (footprint "eagle-import:LED-RGB-THRU")
      (libsource (lib "eagle-import") (part "LED-RGB-CCCLEAR"))
    )
    (comp (ref "D28")
      (value "CLEAR")
      (footprint "eagle-import:LED-RGB-THRU")
      (libsource (lib "eagle-import") (part "LED-RGB-CCCLEAR"))
    )
    (comp (ref "D29")
      (value "CLEAR")
      (footprint "eagle-import:LED-RGB-THRU")
      (libsource (lib "eagle-import") (part "LED-RGB-CCCLEAR"))
    )
    (comp (ref "D30")
      (value "CLEAR")
      (footprint "eagle-import:LED-RGB-THRU")
      (libsource (lib "eagle-import") (part "LED-RGB-CCCLEAR"))
    )
    (comp (ref "D31")
      (value "CLEAR")
      (footprint "eagle-import:LED-RGB-THRU")
      (libsource (lib "eagle-import") (part "LED-RGB-CCCLEAR"))
    )
    (comp (ref "D32")
      (value "CLEAR")
      (footprint "eagle-import:LED-RGB-THRU")
      (libsource (lib "eagle-import") (part "LED-RGB-CCCLEAR"))
    )
    (comp (ref "D33")
      (value "CLEAR")
      (footprint "eagle-import:LED-RGB-THRU")
      (libsource (lib "eagle-import") (part "LED-RGB-CCCLEAR"))
    )
    (comp (ref "D34")
      (value "CLEAR")
      (footprint "eagle-import:LED-RGB-THRU")
      (libsource (lib "eagle-import") (part "LED-RGB-CCCLEAR"))
    )
    (comp (ref "D35")
      (value "CLEAR")
      (footprint "eagle-import:LED-RGB-THRU")
      (libsource (lib "eagle-import") (part "LED-RGB-CCCLEAR"))
    )
    (comp (ref "D36")
      (value "CLEAR")
      (footprint "eagle-import:LED-RGB-THRU")
      (libsource (lib "eagle-import") (part "LED-RGB-CCCLEAR"))
    )
    (comp (ref "D37")
      (value "CLEAR")
      (footprint "eagle-import:LED-RGB-THRU")
      (libsource (lib "eagle-import") (part "LED-RGB-CCCLEAR"))
    )
    (comp (ref "D38")
      (value "CLEAR")
      (footprint "eagle-import:LED-RGB-THRU")
      (libsource (lib "eagle-import") (part "LED-RGB-CCCLEAR"))
    )
    (comp (ref "D39")
      (value "CLEAR")
      (footprint "eagle-import:LED-RGB-THRU")
      (libsource (lib "eagle-import") (part "LED-RGB-CCCLEAR"))
    )
    (comp (ref "D40")
      (value "CLEAR")
      (footprint "eagle-import:LED-RGB-THRU")
      (libsource (lib "eagle-import") (part "LED-RGB-CCCLEAR"))
    )
    (comp (ref "D41")
      (value "CLEAR")
      (footprint "eagle-import:LED-RGB-THRU")
      (libsource (lib "eagle-import") (part "LED-RGB-CCCLEAR"))
    )
    (comp (ref "D42")
      (value "CLEAR")
      (footprint "eagle-import:LED-RGB-THRU")
      (libsource (lib "eagle-import") (part "LED-RGB-CCCLEAR"))
    )
    (comp (ref "D43")
      (value "CLEAR")
      (footprint "eagle-import:LED-RGB-THRU")
      (libsource (lib "eagle-import") (part "LED-RGB-CCCLEAR"))
    )
    (comp (ref "D44")
      (value "CLEAR")
      (footprint "eagle-import:LED-RGB-THRU")
      (libsource (lib "eagle-import") (part "LED-RGB-CCCLEAR"))
    )
    (comp (ref "D45")
      (value "CLEAR")
      (footprint "eagle-import:LED-RGB-THRU")
      (libsource (lib "eagle-import") (part "LED-RGB-CCCLEAR"))
    )
    (comp (ref "D46")
      (value "CLEAR")
      (footprint "eagle-import:LED-RGB-THRU")
      (libsource (lib "eagle-import") (part "LED-RGB-CCCLEAR"))
    )
    (comp (ref "D47")
      (value "CLEAR")
      (footprint "eagle-import:LED-RGB-THRU")
      (libsource (lib "eagle-import") (part "LED-RGB-CCCLEAR"))
    )
    (comp (ref "D48")
      (value "CLEAR")
      (footprint "eagle-import:LED-RGB-THRU")
      (libsource (lib "eagle-import") (part "LED-RGB-CCCLEAR"))
    )
    (comp (ref "D49")
      (value "CLEAR")
      (footprint "eagle-import:LED-RGB-THRU")
      (libsource (lib "eagle-import") (part "LED-RGB-CCCLEAR"))
    )
    (comp (ref "D50")
      (value "CLEAR")
      (footprint "eagle-import:LED-RGB-THRU")
      (libsource (lib "eagle-import") (part "LED-RGB-CCCLEAR"))
    )
    (comp (ref "D51")
      (value "CLEAR")
      (footprint "eagle-import:LED-RGB-THRU")
      (libsource (lib "eagle-import") (part "LED-RGB-CCCLEAR"))
    )
    (comp (ref "D52")
      (value "CLEAR")
      (footprint "eagle-import:LED-RGB-THRU")
      (libsource (lib "eagle-import") (part "LED-RGB-CCCLEAR"))
    )
    (comp (ref "D53")
      (value "CLEAR")
      (footprint "eagle-import:LED-RGB-THRU")
      (libsource (lib "eagle-import") (part "LED-RGB-CCCLEAR"))
    )
    (comp (ref "D54")
      (value "CLEAR")
      (footprint "eagle-import:LED-RGB-THRU")
      (libsource (lib "eagle-import") (part "LED-RGB-CCCLEAR"))
    )
    (comp (ref "D55")
      (value "CLEAR")
      (footprint "eagle-import:LED-RGB-THRU")
      (libsource (lib "eagle-import") (part "LED-RGB-CCCLEAR"))
    )
    (comp (ref "D56")
      (value "CLEAR")
      (footprint "eagle-import:LED-RGB-THRU")
      (libsource (lib "eagle-import") (part "LED-RGB-CCCLEAR"))
    )
    (comp (ref "D57")
      (value "CLEAR")
      (footprint "eagle-import:LED-RGB-THRU")
      (libsource (lib "eagle-import") (part "LED-RGB-CCCLEAR"))
    )
    (comp (ref "D58")
      (value "CLEAR")
      (footprint "eagle-import:LED-RGB-THRU")
      (libsource (lib "eagle-import") (part "LED-RGB-CCCLEAR"))
    )
    (comp (ref "D59")
      (value "CLEAR")
      (footprint "eagle-import:LED-RGB-THRU")
      (libsource (lib "eagle-import") (part "LED-RGB-CCCLEAR"))
    )
    (comp (ref "D60")
      (value "CLEAR")
      (footprint "eagle-import:LED-RGB-THRU")
      (libsource (lib "eagle-import") (part "LED-RGB-CCCLEAR"))
    )
    (comp (ref "D61")
      (value "CLEAR")
      (footprint "eagle-import:LED-RGB-THRU")
      (libsource (lib "eagle-import") (part "LED-RGB-CCCLEAR"))
    )
    (comp (ref "D62")
      (value "CLEAR")
      (footprint "eagle-import:LED-RGB-THRU")
      (libsource (lib "eagle-import") (part "LED-RGB-CCCLEAR"))
    )
    (comp (ref "D63")
      (value "CLEAR")
      (footprint "eagle-import:LED-RGB-THRU")
      (libsource (lib "eagle-import") (part "LED-RGB-CCCLEAR"))
    )
    (comp (ref "D64")
      (value "CLEAR")
      (footprint "eagle-import:LED-RGB-THRU")
      (libsource (lib "eagle-import") (part "LED-RGB-CCCLEAR"))
    )
    (comp (ref "D65")
      (value "CLEAR")
      (footprint "eagle-import:LED-RGB-THRU")
      (libsource (lib "eagle-import") (part "LED-RGB-CCCLEAR"))
    )
    (comp (ref "D66")
      (value "CLEAR")
      (footprint "eagle-import:LED-RGB-THRU")
      (libsource (lib "eagle-import") (part "LED-RGB-CCCLEAR"))
    )
    (comp (ref "D67")
      (value "CLEAR")
      (footprint "eagle-import:LED-RGB-THRU")
      (libsource (lib "eagle-import") (part "LED-RGB-CCCLEAR"))
    )
    (comp (ref "D68")
      (value "CLEAR")
      (footprint "eagle-import:LED-RGB-THRU")
      (libsource (lib "eagle-import") (part "LED-RGB-CCCLEAR"))
    )
    (comp (ref "D69")
      (value "CLEAR")
      (footprint "eagle-import:LED-RGB-THRU")
      (libsource (lib "eagle-import") (part "LED-RGB-CCCLEAR"))
    )
    (comp (ref "D70")
      (value "CLEAR")
      (footprint "eagle-import:LED-RGB-THRU")
      (libsource (lib "eagle-import") (part "LED-RGB-CCCLEAR"))
    )
    (comp (ref "D71")
      (value "CLEAR")
      (footprint "eagle-import:LED-RGB-THRU")
      (libsource (lib "eagle-import") (part "LED-RGB-CCCLEAR"))
    )
    (comp (ref "D72")
      (value "CLEAR")
      (footprint "eagle-import:LED-RGB-THRU")
      (libsource (lib "eagle-import") (part "LED-RGB-CCCLEAR"))
    )
    (comp (ref "D73")
      (value "CLEAR")
      (footprint "eagle-import:LED-RGB-THRU")
      (libsource (lib "eagle-import") (part "LED-RGB-CCCLEAR"))
    )
    (comp (ref "D74")
      (value "CLEAR")
      (footprint "eagle-import:LED-RGB-THRU")
      (libsource (lib "eagle-import") (part "LED-RGB-CCCLEAR"))
    )
    (comp (ref "D75")
      (value "CLEAR")
      (footprint "eagle-import:LED-RGB-THRU")
      (libsource (lib "eagle-import") (part "LED-RGB-CCCLEAR"))
    )
    (comp (ref "D76")
      (value "CLEAR")
      (footprint "eagle-import:LED-RGB-THRU")
      (libsource (lib "eagle-import") (part "LED-RGB-CCCLEAR"))
    )
    (comp (ref "D77")
      (value "CLEAR")
      (footprint "eagle-import:LED-RGB-THRU")
      (libsource (lib "eagle-import") (part "LED-RGB-CCCLEAR"))
    )
    (comp (ref "D78")
      (value "CLEAR")
      (footprint "eagle-import:LED-RGB-THRU")
      (libsource (lib "eagle-import") (part "LED-RGB-CCCLEAR"))
    )
    (comp (ref "D79")
      (value "CLEAR")
      (footprint "eagle-import:LED-RGB-THRU")
      (libsource (lib "eagle-import") (part "LED-RGB-CCCLEAR"))
    )
    (comp (ref "D80")
      (value "CLEAR")
      (footprint "eagle-import:LED-RGB-THRU")
      (libsource (lib "eagle-import") (part "LED-RGB-CCCLEAR"))
    )
    (comp (ref "D81")
      (value "CLEAR")
      (footprint "eagle-import:LED-RGB-THRU")
      (libsource (lib "eagle-import") (part "LED-RGB-CCCLEAR"))
    )
    (comp (ref "D82")
      (value "CLEAR")
      (footprint "eagle-import:LED-RGB-THRU")
      (libsource (lib "eagle-import") (part "LED-RGB-CCCLEAR"))
    )
    (comp (ref "D83")
      (value "CLEAR")
      (footprint "eagle-import:LED-RGB-THRU")
      (libsource (lib "eagle-import") (part "LED-RGB-CCCLEAR"))
    )
    (comp (ref "D84")
      (value "CLEAR")
      (footprint "eagle-import:LED-RGB-THRU")
      (libsource (lib "eagle-import") (part "LED-RGB-CCCLEAR"))
    )
    (comp (ref "D85")
      (value "CLEAR")
      (footprint "eagle-import:LED-RGB-THRU")
      (libsource (lib "eagle-import") (part "LED-RGB-CCCLEAR"))
    )
    (comp (ref "D86")
      (value "CLEAR")
      (footprint "eagle-import:LED-RGB-THRU")
      (libsource (lib "eagle-import") (part "LED-RGB-CCCLEAR"))
    )
    (comp (ref "D87")
      (value "CLEAR")
      (footprint "eagle-import:LED-RGB-THRU")
      (libsource (lib "eagle-import") (part "LED-RGB-CCCLEAR"))
    )
    (comp (ref "D88")
      (value "CLEAR")
      (footprint "eagle-import:LED-RGB-THRU")
      (libsource (lib "eagle-import") (part "LED-RGB-CCCLEAR"))
    )
    (comp (ref "D89")
      (value "CLEAR")
      (footprint "eagle-import:LED-RGB-THRU")
      (libsource (lib "eagle-import") (part "LED-RGB-CCCLEAR"))
    )
    (comp (ref "D90")
      (value "CLEAR")
      (footprint "eagle-import:LED-RGB-THRU")
      (libsource (lib "eagle-import") (part "LED-RGB-CCCLEAR"))
    )
    (comp (ref "D91")
      (value "CLEAR")
      (footprint "eagle-import:LED-RGB-THRU")
      (libsource (lib "eagle-import") (part "LED-RGB-CCCLEAR"))
    )
    (comp (ref "D92")
      (value "CLEAR")
      (footprint "eagle-import:LED-RGB-THRU")
      (libsource (lib "eagle-import") (part "LED-RGB-CCCLEAR"))
    )
    (comp (ref "D93")
      (value "CLEAR")
      (footprint "eagle-import:LED-RGB-THRU")
      (libsource (lib "eagle-import") (part "LED-RGB-CCCLEAR"))
    )
    (comp (ref "D94")
      (value "CLEAR")
      (footprint "eagle-import:LED-RGB-THRU")
      (libsource (lib "eagle-import") (part "LED-RGB-CCCLEAR"))
    )
    (comp (ref "D95")
      (value "CLEAR")
      (footprint "eagle-import:LED-RGB-THRU")
      (libsource (lib "eagle-import") (part "LED-RGB-CCCLEAR"))
    )
    (comp (ref "D96")
      (value "CLEAR")
      (footprint "eagle-import:LED-RGB-THRU")
      (libsource (lib "eagle-import") (part "LED-RGB-CCCLEAR"))
    )
    (comp (ref "D97")
      (value "CLEAR")
      (footprint "eagle-import:LED-RGB-THRU")
      (libsource (lib "eagle-import") (part "LED-RGB-CCCLEAR"))
    )
    (comp (ref "D98")
      (value "CLEAR")
      (footprint "eagle-import:LED-RGB-THRU")
      (libsource (lib "eagle-import") (part "LED-RGB-CCCLEAR"))
    )
    (comp (ref "D99")
      (value "CLEAR")
      (footprint "eagle-import:LED-RGB-THRU")
      (libsource (lib "eagle-import") (part "LED-RGB-CCCLEAR"))
    )
    (comp (ref "D100")
      (value "CLEAR")
      (footprint "eagle-import:LED-RGB-THRU")
      (libsource (lib "eagle-import") (part "LED-RGB-CCCLEAR"))
    )
    (comp (ref "D101")
      (value "CLEAR")
      (footprint "eagle-import:LED-RGB-THRU")
      (libsource (lib "eagle-import") (part "LED-RGB-CCCLEAR"))
    )
    (comp (ref "D102")
      (value "CLEAR")
      (footprint "eagle-import:LED-RGB-THRU")
      (libsource (lib "eagle-import") (part "LED-RGB-CCCLEAR"))
    )
    (comp (ref "D103")
      (value "CLEAR")
      (footprint "eagle-import:LED-RGB-THRU")
      (libsource (lib "eagle-import") (part "LED-RGB-CCCLEAR"))
    )
    (comp (ref "D104")
      (value "CLEAR")
      (footprint "eagle-import:LED-RGB-THRU")
      (libsource (lib "eagle-import") (part "LED-RGB-CCCLEAR"))
    )
    (comp (ref "D105")
      (value "CLEAR")
      (footprint "eagle-import:LED-RGB-THRU")
      (libsource (lib "eagle-import") (part "LED-RGB-CCCLEAR"))
    )
    (comp (ref "D106")
      (value "CLEAR")
      (footprint "eagle-import:LED-RGB-THRU")
      (libsource (lib "eagle-import") (part "LED-RGB-CCCLEAR"))
    )
    (comp (ref "D107")
      (value "CLEAR")
      (footprint "eagle-import:LED-RGB-THRU")
      (libsource (lib "eagle-import") (part "LED-RGB-CCCLEAR"))
    )
    (comp (ref "D108")
      (value "CLEAR")
      (footprint "eagle-import:LED-RGB-THRU")
      (libsource (lib "eagle-import") (part "LED-RGB-CCCLEAR"))
    )
    (comp (ref "D109")
      (value "CLEAR")
      (footprint "eagle-import:LED-RGB-THRU")
      (libsource (lib "eagle-import") (part "LED-RGB-CCCLEAR"))
    )
    (comp (ref "D110")
      (value "CLEAR")
      (footprint "eagle-import:LED-RGB-THRU")
      (libsource (lib "eagle-import") (part "LED-RGB-CCCLEAR"))
    )
    (comp (ref "D111")
      (value "CLEAR")
      (footprint "eagle-import:LED-RGB-THRU")
      (libsource (lib "eagle-import") (part "LED-RGB-CCCLEAR"))
    )
    (comp (ref "D112")
      (value "CLEAR")
      (footprint "eagle-import:LED-RGB-THRU")
      (libsource (lib "eagle-import") (part "LED-RGB-CCCLEAR"))
    )
    (comp (ref "D113")
      (value "CLEAR")
      (footprint "eagle-import:LED-RGB-THRU")
      (libsource (lib "eagle-import") (part "LED-RGB-CCCLEAR"))
    )
    (comp (ref "D114")
      (value "CLEAR")
      (footprint "eagle-import:LED-RGB-THRU")
      (libsource (lib "eagle-import") (part "LED-RGB-CCCLEAR"))
    )
    (comp (ref "D115")
      (value "CLEAR")
      (footprint "eagle-import:LED-RGB-THRU")
      (libsource (lib "eagle-import") (part "LED-RGB-CCCLEAR"))
    )
    (comp (ref "D116")
      (value "CLEAR")
      (footprint "eagle-import:LED-RGB-THRU")
      (libsource (lib "eagle-import") (part "LED-RGB-CCCLEAR"))
    )
    (comp (ref "D117")
      (value "CLEAR")
      (footprint "eagle-import:LED-RGB-THRU")
      (libsource (lib "eagle-import") (part "LED-RGB-CCCLEAR"))
    )
    (comp (ref "D118")
      (value "CLEAR")
      (footprint "eagle-import:LED-RGB-THRU")
      (libsource (lib "eagle-import") (part "LED-RGB-CCCLEAR"))
    )
    (comp (ref "D119")
      (value "CLEAR")
      (footprint "eagle-import:LED-RGB-THRU")
      (libsource (lib "eagle-import") (part "LED-RGB-CCCLEAR"))
    )
    (comp (ref "D120")
      (value "CLEAR")
      (footprint "eagle-import:LED-RGB-THRU")
      (libsource (lib "eagle-import") (part "LED-RGB-CCCLEAR"))
    )
    (comp (ref "D121")
      (value "CLEAR")
      (footprint "eagle-import:LED-RGB-THRU")
      (libsource (lib "eagle-import") (part "LED-RGB-CCCLEAR"))
    )
    (comp (ref "D122")
      (value "CLEAR")
      (footprint "eagle-import:LED-RGB-THRU")
      (libsource (lib "eagle-import") (part "LED-RGB-CCCLEAR"))
    )
    (comp (ref "D123")
      (value "CLEAR")
      (footprint "eagle-import:LED-RGB-THRU")
      (libsource (lib "eagle-import") (part "LED-RGB-CCCLEAR"))
    )
    (comp (ref "D124")
      (value "CLEAR")
      (footprint "eagle-import:LED-RGB-THRU")
      (libsource (lib "eagle-import") (part "LED-RGB-CCCLEAR"))
    )
    (comp (ref "D125")
      (value "CLEAR")
      (footprint "eagle-import:LED-RGB-THRU")
      (libsource (lib "eagle-import") (part "LED-RGB-CCCLEAR"))
    )
    (comp (ref "D126")
      (value "CLEAR")
      (footprint "eagle-import:LED-RGB-THRU")
      (libsource (lib "eagle-import") (part "LED-RGB-CCCLEAR"))
    )
    (comp (ref "D127")
      (value "CLEAR")
      (footprint "eagle-import:LED-RGB-THRU")
      (libsource (lib "eagle-import") (part "LED-RGB-CCCLEAR"))
    )
    (comp (ref "D128")
      (value "CLEAR")
      (footprint "eagle-import:LED-RGB-THRU")
      (libsource (lib "eagle-import") (part "LED-RGB-CCCLEAR"))
    )
    (comp (ref "D129")
      (value "CLEAR")
      (footprint "eagle-import:LED-RGB-THRU")
      (libsource (lib "eagle-import") (part "LED-RGB-CCCLEAR"))
    )
    (comp (ref "D130")
      (value "CLEAR")
      (footprint "eagle-import:LED-RGB-THRU")
      (libsource (lib "eagle-import") (part "LED-RGB-CCCLEAR"))
    )
    (comp (ref "D131")
      (value "CLEAR")
      (footprint "eagle-import:LED-RGB-THRU")
      (libsource (lib "eagle-import") (part "LED-RGB-CCCLEAR"))
    )
    (comp (ref "D132")
      (value "CLEAR")
      (footprint "eagle-import:LED-RGB-THRU")
      (libsource (lib "eagle-import") (part "LED-RGB-CCCLEAR"))
    )
    (comp (ref "D133")
      (value "CLEAR")
      (footprint "eagle-import:LED-RGB-THRU")
      (libsource (lib "eagle-import") (part "LED-RGB-CCCLEAR"))
    )
    (comp (ref "D134")
      (value "CLEAR")
      (footprint "eagle-import:LED-RGB-THRU")
      (libsource (lib "eagle-import") (part "LED-RGB-CCCLEAR"))
    )
    (comp (ref "D135")
      (value "CLEAR")
      (footprint "eagle-import:LED-RGB-THRU")
      (libsource (lib "eagle-import") (part "LED-RGB-CCCLEAR"))
    )
    (comp (ref "D136")
      (value "CLEAR")
      (footprint "eagle-import:LED-RGB-THRU")
      (libsource (lib "eagle-import") (part "LED-RGB-CCCLEAR"))
    )
    (comp (ref "D137")
      (value "CLEAR")
      (footprint "eagle-import:LED-RGB-THRU")
      (libsource (lib "eagle-import") (part "LED-RGB-CCCLEAR"))
    )
    (comp (ref "D138")
      (value "CLEAR")
      (footprint "eagle-import:LED-RGB-THRU")
      (libsource (lib "eagle-import") (part "LED-RGB-CCCLEAR"))
    )
    (comp (ref "D139")
      (value "CLEAR")
      (footprint "eagle-import:LED-RGB-THRU")
      (libsource (lib "eagle-import") (part "LED-RGB-CCCLEAR"))
    )
    (comp (ref "D140")
      (value "CLEAR")
      (footprint "eagle-import:LED-RGB-THRU")
      (libsource (lib "eagle-import") (part "LED-RGB-CCCLEAR"))
    )
    (comp (ref "D141")
      (value "CLEAR")
      (footprint "eagle-import:LED-RGB-THRU")
      (libsource (lib "eagle-import") (part "LED-RGB-CCCLEAR"))
    )
    (comp (ref "D142")
      (value "CLEAR")
      (footprint "eagle-import:LED-RGB-THRU")
      (libsource (lib "eagle-import") (part "LED-RGB-CCCLEAR"))
    )
    (comp (ref "D143")
      (value "CLEAR")
      (footprint "eagle-import:LED-RGB-THRU")
      (libsource (lib "eagle-import") (part "LED-RGB-CCCLEAR"))
    )
    (comp (ref "D144")
      (value "CLEAR")
      (footprint "eagle-import:LED-RGB-THRU")
      (libsource (lib "eagle-import") (part "LED-RGB-CCCLEAR"))
    )
    (comp (ref "D145")
      (value "CLEAR")
      (footprint "eagle-import:LED-RGB-THRU")
      (libsource (lib "eagle-import") (part "LED-RGB-CCCLEAR"))
    )
    (comp (ref "D146")
      (value "CLEAR")
      (footprint "eagle-import:LED-RGB-THRU")
      (libsource (lib "eagle-import") (part "LED-RGB-CCCLEAR"))
    )
    (comp (ref "D147")
      (value "CLEAR")
      (footprint "eagle-import:LED-RGB-THRU")
      (libsource (lib "eagle-import") (part "LED-RGB-CCCLEAR"))
    )
    (comp (ref "D148")
      (value "CLEAR")
      (footprint "eagle-import:LED-RGB-THRU")
      (libsource (lib "eagle-import") (part "LED-RGB-CCCLEAR"))
    )
    (comp (ref "D149")
      (value "CLEAR")
      (footprint "eagle-import:LED-RGB-THRU")
      (libsource (lib "eagle-import") (part "LED-RGB-CCCLEAR"))
    )
    (comp (ref "D150")
      (value "CLEAR")
      (footprint "eagle-import:LED-RGB-THRU")
      (libsource (lib "eagle-import") (part "LED-RGB-CCCLEAR"))
    )
    (comp (ref "D151")
      (value "CLEAR")
      (footprint "eagle-import:LED-RGB-THRU")
      (libsource (lib "eagle-import") (part "LED-RGB-CCCLEAR"))
    )
    (comp (ref "D152")
      (value "CLEAR")
      (footprint "eagle-import:LED-RGB-THRU")
      (libsource (lib "eagle-import") (part "LED-RGB-CCCLEAR"))
    )
    (comp (ref "D153")
      (value "CLEAR")
      (footprint "eagle-import:LED-RGB-THRU")
      (libsource (lib "eagle-import") (part "LED-RGB-CCCLEAR"))
    )
    (comp (ref "D154")
      (value "CLEAR")
      (footprint "eagle-import:LED-RGB-THRU")
      (libsource (lib "eagle-import") (part "LED-RGB-CCCLEAR"))
    )
    (comp (ref "D155")
      (value "CLEAR")
      (footprint "eagle-import:LED-RGB-THRU")
      (libsource (lib "eagle-import") (part "LED-RGB-CCCLEAR"))
    )
    (comp (ref "D156")
      (value "CLEAR")
      (footprint "eagle-import:LED-RGB-THRU")
      (libsource (lib "eagle-import") (part "LED-RGB-CCCLEAR"))
    )
    (comp (ref "D157")
      (value "CLEAR")
      (footprint "eagle-import:LED-RGB-THRU")
      (libsource (lib "eagle-import") (part "LED-RGB-CCCLEAR"))
    )
    (comp (ref "D158")
      (value "CLEAR")
      (footprint "eagle-import:LED-RGB-THRU")
      (libsource (lib "eagle-import") (part "LED-RGB-CCCLEAR"))
    )
    (comp (ref "D159")
      (value "CLEAR")
      (footprint "eagle-import:LED-RGB-THRU")
      (libsource (lib "eagle-import") (part "LED-RGB-CCCLEAR"))
    )
    (comp (ref "D160")
      (value "CLEAR")
      (footprint "eagle-import:LED-RGB-THRU")
      (libsource (lib "eagle-import") (part "LED-RGB-CCCLEAR"))
    )
    (comp (ref "D161")
      (value "CLEAR")
      (footprint "eagle-import:LED-RGB-THRU")
      (libsource (lib "eagle-import") (part "LED-RGB-CCCLEAR"))
    )
    (comp (ref "D162")
      (value "CLEAR")
      (footprint "eagle-import:LED-RGB-THRU")
      (libsource (lib "eagle-import") (part "LED-RGB-CCCLEAR"))
    )
    (comp (ref "D163")
      (value "CLEAR")
      (footprint "eagle-import:LED-RGB-THRU")
      (libsource (lib "eagle-import") (part "LED-RGB-CCCLEAR"))
    )
    (comp (ref "D164")
      (value "CLEAR")
      (footprint "eagle-import:LED-RGB-THRU")
      (libsource (lib "eagle-import") (part "LED-RGB-CCCLEAR"))
    )
    (comp (ref "D165")
      (value "CLEAR")
      (footprint "eagle-import:LED-RGB-THRU")
      (libsource (lib "eagle-import") (part "LED-RGB-CCCLEAR"))
    )
    (comp (ref "D166")
      (value "CLEAR")
      (footprint "eagle-import:LED-RGB-THRU")
      (libsource (lib "eagle-import") (part "LED-RGB-CCCLEAR"))
    )
    (comp (ref "D167")
      (value "CLEAR")
      (footprint "eagle-import:LED-RGB-THRU")
      (libsource (lib "eagle-import") (part "LED-RGB-CCCLEAR"))
    )
    (comp (ref "D168")
      (value "CLEAR")
      (footprint "eagle-import:LED-RGB-THRU")
      (libsource (lib "eagle-import") (part "LED-RGB-CCCLEAR"))
    )
    (comp (ref "D169")
      (value "CLEAR")
      (footprint "eagle-import:LED-RGB-THRU")
      (libsource (lib "eagle-import") (part "LED-RGB-CCCLEAR"))
    )
    (comp (ref "D170")
      (value "CLEAR")
      (footprint "eagle-import:LED-RGB-THRU")
      (libsource (lib "eagle-import") (part "LED-RGB-CCCLEAR"))
    )
    (comp (ref "D171")
      (value "CLEAR")
      (footprint "eagle-import:LED-RGB-THRU")
      (libsource (lib "eagle-import") (part "LED-RGB-CCCLEAR"))
    )
    (comp (ref "D172")
      (value "CLEAR")
      (footprint "eagle-import:LED-RGB-THRU")
      (libsource (lib "eagle-import") (part "LED-RGB-CCCLEAR"))
    )
    (comp (ref "D173")
      (value "CLEAR")
      (footprint "eagle-import:LED-RGB-THRU")
      (libsource (lib "eagle-import") (part "LED-RGB-CCCLEAR"))
    )
    (comp (ref "D174")
      (value "CLEAR")
      (footprint "eagle-import:LED-RGB-THRU")
      (libsource (lib "eagle-import") (part "LED-RGB-CCCLEAR"))
    )
    (comp (ref "D175")
      (value "CLEAR")
      (footprint "eagle-import:LED-RGB-THRU")
      (libsource (lib "eagle-import") (part "LED-RGB-CCCLEAR"))
    )
    (comp (ref "D176")
      (value "CLEAR")
      (footprint "eagle-import:LED-RGB-THRU")
      (libsource (lib "eagle-import") (part "LED-RGB-CCCLEAR"))
    )
    (comp (ref "D177")
      (value "CLEAR")
      (footprint "eagle-import:LED-RGB-THRU")
      (libsource (lib "eagle-import") (part "LED-RGB-CCCLEAR"))
    )
    (comp (ref "D178")
      (value "CLEAR")
      (footprint "eagle-import:LED-RGB-THRU")
      (libsource (lib "eagle-import") (part "LED-RGB-CCCLEAR"))
    )
    (comp (ref "D179")
      (value "CLEAR")
      (footprint "eagle-import:LED-RGB-THRU")
      (libsource (lib "eagle-import") (part "LED-RGB-CCCLEAR"))
    )
    (comp (ref "D180")
      (value "CLEAR")
      (footprint "eagle-import:LED-RGB-THRU")
      (libsource (lib "eagle-import") (part "LED-RGB-CCCLEAR"))
    )
    (comp (ref "D181")
      (value "CLEAR")
      (footprint "eagle-import:LED-RGB-THRU")
      (libsource (lib "eagle-import") (part "LED-RGB-CCCLEAR"))
    )
    (comp (ref "D182")
      (value "CLEAR")
      (footprint "eagle-import:LED-RGB-THRU")
      (libsource (lib "eagle-import") (part "LED-RGB-CCCLEAR"))
    )
    (comp (ref "D183")
      (value "CLEAR")
      (footprint "eagle-import:LED-RGB-THRU")
      (libsource (lib "eagle-import") (part "LED-RGB-CCCLEAR"))
    )
    (comp (ref "D184")
      (value "CLEAR")
      (footprint "eagle-import:LED-RGB-THRU")
      (libsource (lib "eagle-import") (part "LED-RGB-CCCLEAR"))
    )
    (comp (ref "D185")
      (value "CLEAR")
      (footprint "eagle-import:LED-RGB-THRU")
      (libsource (lib "eagle-import") (part "LED-RGB-CCCLEAR"))
    )
    (comp (ref "D186")
      (value "CLEAR")
      (footprint "eagle-import:LED-RGB-THRU")
      (libsource (lib "eagle-import") (part "LED-RGB-CCCLEAR"))
    )
    (comp (ref "D187")
      (value "CLEAR")
      (footprint "eagle-import:LED-RGB-THRU")
      (libsource (lib "eagle-import") (part "LED-RGB-CCCLEAR"))
    )
    (comp (ref "D188")
      (value "CLEAR")
      (footprint "eagle-import:LED-RGB-THRU")
      (libsource (lib "eagle-import") (part "LED-RGB-CCCLEAR"))
    )
    (comp (ref "D189")
      (value "CLEAR")
      (footprint "eagle-import:LED-RGB-THRU")
      (libsource (lib "eagle-import") (part "LED-RGB-CCCLEAR"))
    )
    (comp (ref "D190")
      (value "CLEAR")
      (footprint "eagle-import:LED-RGB-THRU")
      (libsource (lib "eagle-import") (part "LED-RGB-CCCLEAR"))
    )
    (comp (ref "D191")
      (value "CLEAR")
      (footprint "eagle-import:LED-RGB-THRU")
      (libsource (lib "eagle-import") (part "LED-RGB-CCCLEAR"))
    )
    (comp (ref "D192")
      (value "CLEAR")
      (footprint "eagle-import:LED-RGB-THRU")
      (libsource (lib "eagle-import") (part "LED-RGB-CCCLEAR"))
    )
    (comp (ref "D193")
      (value "CLEAR")
      (footprint "eagle-import:LED-RGB-THRU")
      (libsource (lib "eagle-import") (part "LED-RGB-CCCLEAR"))
    )
    (comp (ref "D194")
      (value "CLEAR")
      (footprint "eagle-import:LED-RGB-THRU")
      (libsource (lib "eagle-import") (part "LED-RGB-CCCLEAR"))
    )
    (comp (ref "D195")
      (value "CLEAR")
      (footprint "eagle-import:LED-RGB-THRU")
      (libsource (lib "eagle-import") (part "LED-RGB-CCCLEAR"))
    )
    (comp (ref "D196")
      (value "CLEAR")
      (footprint "eagle-import:LED-RGB-THRU")
      (libsource (lib "eagle-import") (part "LED-RGB-CCCLEAR"))
    )
    (comp (ref "D197")
      (value "CLEAR")
      (footprint "eagle-import:LED-RGB-THRU")
      (libsource (lib "eagle-import") (part "LED-RGB-CCCLEAR"))
    )
    (comp (ref "D198")
      (value "CLEAR")
      (footprint "eagle-import:LED-RGB-THRU")
      (libsource (lib "eagle-import") (part "LED-RGB-CCCLEAR"))
    )
    (comp (ref "D199")
      (value "CLEAR")
      (footprint "eagle-import:LED-RGB-THRU")
      (libsource (lib "eagle-import") (part "LED-RGB-CCCLEAR"))
    )
    (comp (ref "D200")
      (value "CLEAR")
      (footprint "eagle-import:LED-RGB-THRU")
      (libsource (lib "eagle-import") (part "LED-RGB-CCCLEAR"))
    )
    (comp (ref "D201")
      (value "CLEAR")
      (footprint "eagle-import:LED-RGB-THRU")
      (libsource (lib "eagle-import") (part "LED-RGB-CCCLEAR"))
    )
    (comp (ref "D202")
      (value "CLEAR")
      (footprint "eagle-import:LED-RGB-THRU")
      (libsource (lib "eagle-import") (part "LED-RGB-CCCLEAR"))
    )
    (comp (ref "D203")
      (value "CLEAR")
      (footprint "eagle-import:LED-RGB-THRU")
      (libsource (lib "eagle-import") (part "LED-RGB-CCCLEAR"))
    )
    (comp (ref "D204")
      (value "CLEAR")
      (footprint "eagle-import:LED-RGB-THRU")
      (libsource (lib "eagle-import") (part "LED-RGB-CCCLEAR"))
    )
    (comp (ref "D205")
      (value "CLEAR")
      (footprint "eagle-import:LED-RGB-THRU")
      (libsource (lib "eagle-import") (part "LED-RGB-CCCLEAR"))
    )
    (comp (ref "D206")
      (value "CLEAR")
      (footprint "eagle-import:LED-RGB-THRU")
      (libsource (lib "eagle-import") (part "LED-RGB-CCCLEAR"))
    )
    (comp (ref "D207")
      (value "CLEAR")
      (footprint "eagle-import:LED-RGB-THRU")
      (libsource (lib "eagle-import") (part "LED-RGB-CCCLEAR"))
    )
    (comp (ref "D208")
      (value "CLEAR")
      (footprint "eagle-import:LED-RGB-THRU")
      (libsource (lib "eagle-import") (part "LED-RGB-CCCLEAR"))
    )
    (comp (ref "D209")
      (value "CLEAR")
      (footprint "eagle-import:LED-RGB-THRU")
      (libsource (lib "eagle-import") (part "LED-RGB-CCCLEAR"))
    )
    (comp (ref "D210")
      (value "CLEAR")
      (footprint "eagle-import:LED-RGB-THRU")
      (libsource (lib "eagle-import") (part "LED-RGB-CCCLEAR"))
    )
    (comp (ref "D211")
      (value "CLEAR")
      (footprint "eagle-import:LED-RGB-THRU")
      (libsource (lib "eagle-import") (part "LED-RGB-CCCLEAR"))
    )
    (comp (ref "D212")
      (value "CLEAR")
      (footprint "eagle-import:LED-RGB-THRU")
      (libsource (lib "eagle-import") (part "LED-RGB-CCCLEAR"))
    )
    (comp (ref "D213")
      (value "CLEAR")
      (footprint "eagle-import:LED-RGB-THRU")
      (libsource (lib "eagle-import") (part "LED-RGB-CCCLEAR"))
    )
    (comp (ref "D214")
      (value "CLEAR")
      (footprint "eagle-import:LED-RGB-THRU")
      (libsource (lib "eagle-import") (part "LED-RGB-CCCLEAR"))
    )
    (comp (ref "D215")
      (value "CLEAR")
      (footprint "eagle-import:LED-RGB-THRU")
      (libsource (lib "eagle-import") (part "LED-RGB-CCCLEAR"))
    )
    (comp (ref "D216")
      (value "CLEAR")
      (footprint "eagle-import:LED-RGB-THRU")
      (libsource (lib "eagle-import") (part "LED-RGB-CCCLEAR"))
    )
    (comp (ref "D217")
      (value "CLEAR")
      (footprint "eagle-import:LED-RGB-THRU")
      (libsource (lib "eagle-import") (part "LED-RGB-CCCLEAR"))
    )
    (comp (ref "D218")
      (value "CLEAR")
      (footprint "eagle-import:LED-RGB-THRU")
      (libsource (lib "eagle-import") (part "LED-RGB-CCCLEAR"))
    )
    (comp (ref "D219")
      (value "CLEAR")
      (footprint "eagle-import:LED-RGB-THRU")
      (libsource (lib "eagle-import") (part "LED-RGB-CCCLEAR"))
    )
    (comp (ref "D220")
      (value "CLEAR")
      (footprint "eagle-import:LED-RGB-THRU")
      (libsource (lib "eagle-import") (part "LED-RGB-CCCLEAR"))
    )
    (comp (ref "D221")
      (value "CLEAR")
      (footprint "eagle-import:LED-RGB-THRU")
      (libsource (lib "eagle-import") (part "LED-RGB-CCCLEAR"))
    )
    (comp (ref "D222")
      (value "CLEAR")
      (footprint "eagle-import:LED-RGB-THRU")
      (libsource (lib "eagle-import") (part "LED-RGB-CCCLEAR"))
    )
    (comp (ref "D223")
      (value "CLEAR")
      (footprint "eagle-import:LED-RGB-THRU")
      (libsource (lib "eagle-import") (part "LED-RGB-CCCLEAR"))
    )
    (comp (ref "D224")
      (value "CLEAR")
      (footprint "eagle-import:LED-RGB-THRU")
      (libsource (lib "eagle-import") (part "LED-RGB-CCCLEAR"))
    )
    (comp (ref "D225")
      (value "CLEAR")
      (footprint "eagle-import:LED-RGB-THRU")
      (libsource (lib "eagle-import") (part "LED-RGB-CCCLEAR"))
    )
    (comp (ref "D226")
      (value "CLEAR")
      (footprint "eagle-import:LED-RGB-THRU")
      (libsource (lib "eagle-import") (part "LED-RGB-CCCLEAR"))
    )
    (comp (ref "D227")
      (value "CLEAR")
      (footprint "eagle-import:LED-RGB-THRU")
      (libsource (lib "eagle-import") (part "LED-RGB-CCCLEAR"))
    )
    (comp (ref "D228")
      (value "CLEAR")
      (footprint "eagle-import:LED-RGB-THRU")
      (libsource (lib "eagle-import") (part "LED-RGB-CCCLEAR"))
    )
    (comp (ref "D229")
      (value "CLEAR")
      (footprint "eagle-import:LED-RGB-THRU")
      (libsource (lib "eagle-import") (part "LED-RGB-CCCLEAR"))
    )
    (comp (ref "D230")
      (value "CLEAR")
      (footprint "eagle-import:LED-RGB-THRU")
      (libsource (lib "eagle-import") (part "LED-RGB-CCCLEAR"))
    )
    (comp (ref "D231")
      (value "CLEAR")
      (footprint "eagle-import:LED-RGB-THRU")
      (libsource (lib "eagle-import") (part "LED-RGB-CCCLEAR"))
    )
    (comp (ref "D232")
      (value "CLEAR")
      (footprint "eagle-import:LED-RGB-THRU")
      (libsource (lib "eagle-import") (part "LED-RGB-CCCLEAR"))
    )
    (comp (ref "D233")
      (value "CLEAR")
      (footprint "eagle-import:LED-RGB-THRU")
      (libsource (lib "eagle-import") (part "LED-RGB-CCCLEAR"))
    )
    (comp (ref "D234")
      (value "CLEAR")
      (footprint "eagle-import:LED-RGB-THRU")
      (libsource (lib "eagle-import") (part "LED-RGB-CCCLEAR"))
    )
    (comp (ref "D235")
      (value "CLEAR")
      (footprint "eagle-import:LED-RGB-THRU")
      (libsource (lib "eagle-import") (part "LED-RGB-CCCLEAR"))
    )
    (comp (ref "D236")
      (value "CLEAR")
      (footprint "eagle-import:LED-RGB-THRU")
      (libsource (lib "eagle-import") (part "LED-RGB-CCCLEAR"))
    )
    (comp (ref "D237")
      (value "CLEAR")
      (footprint "eagle-import:LED-RGB-THRU")
      (libsource (lib "eagle-import") (part "LED-RGB-CCCLEAR"))
    )
    (comp (ref "D238")
      (value "CLEAR")
      (footprint "eagle-import:LED-RGB-THRU")
      (libsource (lib "eagle-import") (part "LED-RGB-CCCLEAR"))
    )
    (comp (ref "D239")
      (value "CLEAR")
      (footprint "eagle-import:LED-RGB-THRU")
      (libsource (lib "eagle-import") (part "LED-RGB-CCCLEAR"))
    )
    (comp (ref "D240")
      (value "CLEAR")
      (footprint "eagle-import:LED-RGB-THRU")
      (libsource (lib "eagle-import") (part "LED-RGB-CCCLEAR"))
    )
    (comp (ref "D241")
      (value "CLEAR")
      (footprint "eagle-import:LED-RGB-THRU")
      (libsource (lib "eagle-import") (part "LED-RGB-CCCLEAR"))
    )
    (comp (ref "D242")
      (value "CLEAR")
      (footprint "eagle-import:LED-RGB-THRU")
      (libsource (lib "eagle-import") (part "LED-RGB-CCCLEAR"))
    )
    (comp (ref "D243")
      (value "CLEAR")
      (footprint "eagle-import:LED-RGB-THRU")
      (libsource (lib "eagle-import") (part "LED-RGB-CCCLEAR"))
    )
    (comp (ref "D244")
      (value "CLEAR")
      (footprint "eagle-import:LED-RGB-THRU")
      (libsource (lib "eagle-import") (part "LED-RGB-CCCLEAR"))
    )
    (comp (ref "D245")
      (value "CLEAR")
      (footprint "eagle-import:LED-RGB-THRU")
      (libsource (lib "eagle-import") (part "LED-RGB-CCCLEAR"))
    )
    (comp (ref "D246")
      (value "CLEAR")
      (footprint "eagle-import:LED-RGB-THRU")
      (libsource (lib "eagle-import") (part "LED-RGB-CCCLEAR"))
    )
    (comp (ref "D247")
      (value "CLEAR")
      (footprint "eagle-import:LED-RGB-THRU")
      (libsource (lib "eagle-import") (part "LED-RGB-CCCLEAR"))
    )
    (comp (ref "D248")
      (value "CLEAR")
      (footprint "eagle-import:LED-RGB-THRU")
      (libsource (lib "eagle-import") (part "LED-RGB-CCCLEAR"))
    )
    (comp (ref "D249")
      (value "CLEAR")
      (footprint "eagle-import:LED-RGB-THRU")
      (libsource (lib "eagle-import") (part "LED-RGB-CCCLEAR"))
    )
    (comp (ref "D250")
      (value "CLEAR")
      (footprint "eagle-import:LED-RGB-THRU")
      (libsource (lib "eagle-import") (part "LED-RGB-CCCLEAR"))
    )
    (comp (ref "D251")
      (value "CLEAR")
      (footprint "eagle-import:LED-RGB-THRU")
      (libsource (lib "eagle-import") (part "LED-RGB-CCCLEAR"))
    )
    (comp (ref "D252")
      (value "CLEAR")
      (footprint "eagle-import:LED-RGB-THRU")
      (libsource (lib "eagle-import") (part "LED-RGB-CCCLEAR"))
    )
    (comp (ref "D253")
      (value "CLEAR")
      (footprint "eagle-import:LED-RGB-THRU")
      (libsource (lib "eagle-import") (part "LED-RGB-CCCLEAR"))
    )
    (comp (ref "D254")
      (value "CLEAR")
      (footprint "eagle-import:LED-RGB-THRU")
      (libsource (lib "eagle-import") (part "LED-RGB-CCCLEAR"))
    )
    (comp (ref "D255")
      (value "CLEAR")
      (footprint "eagle-import:LED-RGB-THRU")
      (libsource (lib "eagle-import") (part "LED-RGB-CCCLEAR"))
    )
    (comp (ref "D256")
      (value "CLEAR")
      (footprint "eagle-import:LED-RGB-THRU")
      (libsource (lib "eagle-import") (part "LED-RGB-CCCLEAR"))
    )
    (comp (ref "D257")
      (value "CLEAR")
      (footprint "eagle-import:LED-RGB-THRU")
      (libsource (lib "eagle-import") (part "LED-RGB-CCCLEAR"))
    )
    (comp (ref "D258")
      (value "CLEAR")
      (footprint "eagle-import:LED-RGB-THRU")
      (libsource (lib "eagle-import") (part "LED-RGB-CCCLEAR"))
    )
    (comp (ref "D259")
      (value "CLEAR")
      (footprint "eagle-import:LED-RGB-THRU")
      (libsource (lib "eagle-import") (part "LED-RGB-CCCLEAR"))
    )
    (comp (ref "D260")
      (value "CLEAR")
      (footprint "eagle-import:LED-RGB-THRU")
      (libsource (lib "eagle-import") (part "LED-RGB-CCCLEAR"))
    )
    (comp (ref "D261")
      (value "CLEAR")
      (footprint "eagle-import:LED-RGB-THRU")
      (libsource (lib "eagle-import") (part "LED-RGB-CCCLEAR"))
    )
    (comp (ref "D262")
      (value "CLEAR")
      (footprint "eagle-import:LED-RGB-THRU")
      (libsource (lib "eagle-import") (part "LED-RGB-CCCLEAR"))
    )
    (comp (ref "D263")
      (value "CLEAR")
      (footprint "eagle-import:LED-RGB-THRU")
      (libsource (lib "eagle-import") (part "LED-RGB-CCCLEAR"))
    )
    (comp (ref "D264")
      (value "CLEAR")
      (footprint "eagle-import:LED-RGB-THRU")
      (libsource (lib "eagle-import") (part "LED-RGB-CCCLEAR"))
    )
    (comp (ref "D265")
      (value "CLEAR")
      (footprint "eagle-import:LED-RGB-THRU")
      (libsource (lib "eagle-import") (part "LED-RGB-CCCLEAR"))
    )
    (comp (ref "D266")
      (value "CLEAR")
      (footprint "eagle-import:LED-RGB-THRU")
      (libsource (lib "eagle-import") (part "LED-RGB-CCCLEAR"))
    )
    (comp (ref "D267")
      (value "CLEAR")
      (footprint "eagle-import:LED-RGB-THRU")
      (libsource (lib "eagle-import") (part "LED-RGB-CCCLEAR"))
    )
    (comp (ref "D268")
      (value "CLEAR")
      (footprint "eagle-import:LED-RGB-THRU")
      (libsource (lib "eagle-import") (part "LED-RGB-CCCLEAR"))
    )
    (comp (ref "D269")
      (value "CLEAR")
      (footprint "eagle-import:LED-RGB-THRU")
      (libsource (lib "eagle-import") (part "LED-RGB-CCCLEAR"))
    )
    (comp (ref "D270")
      (value "CLEAR")
      (footprint "eagle-import:LED-RGB-THRU")
      (libsource (lib "eagle-import") (part "LED-RGB-CCCLEAR"))
    )
    (comp (ref "D271")
      (value "CLEAR")
      (footprint "eagle-import:LED-RGB-THRU")
      (libsource (lib "eagle-import") (part "LED-RGB-CCCLEAR"))
    )
    (comp (ref "D272")
      (value "CLEAR")
      (footprint "eagle-import:LED-RGB-THRU")
      (libsource (lib "eagle-import") (part "LED-RGB-CCCLEAR"))
    )
    (comp (ref "D273")
      (value "CLEAR")
      (footprint "eagle-import:LED-RGB-THRU")
      (libsource (lib "eagle-import") (part "LED-RGB-CCCLEAR"))
    )
    (comp (ref "D274")
      (value "CLEAR")
      (footprint "eagle-import:LED-RGB-THRU")
      (libsource (lib "eagle-import") (part "LED-RGB-CCCLEAR"))
    )
    (comp (ref "D275")
      (value "CLEAR")
      (footprint "eagle-import:LED-RGB-THRU")
      (libsource (lib "eagle-import") (part "LED-RGB-CCCLEAR"))
    )
    (comp (ref "D276")
      (value "CLEAR")
      (footprint "eagle-import:LED-RGB-THRU")
      (libsource (lib "eagle-import") (part "LED-RGB-CCCLEAR"))
    )
    (comp (ref "D277")
      (value "CLEAR")
      (footprint "eagle-import:LED-RGB-THRU")
      (libsource (lib "eagle-import") (part "LED-RGB-CCCLEAR"))
    )
    (comp (ref "D278")
      (value "CLEAR")
      (footprint "eagle-import:LED-RGB-THRU")
      (libsource (lib "eagle-import") (part "LED-RGB-CCCLEAR"))
    )
    (comp (ref "D279")
      (value "CLEAR")
      (footprint "eagle-import:LED-RGB-THRU")
      (libsource (lib "eagle-import") (part "LED-RGB-CCCLEAR"))
    )
    (comp (ref "D280")
      (value "CLEAR")
      (footprint "eagle-import:LED-RGB-THRU")
      (libsource (lib "eagle-import") (part "LED-RGB-CCCLEAR"))
    )
    (comp (ref "D281")
      (value "CLEAR")
      (footprint "eagle-import:LED-RGB-THRU")
      (libsource (lib "eagle-import") (part "LED-RGB-CCCLEAR"))
    )
    (comp (ref "D282")
      (value "CLEAR")
      (footprint "eagle-import:LED-RGB-THRU")
      (libsource (lib "eagle-import") (part "LED-RGB-CCCLEAR"))
    )
    (comp (ref "D283")
      (value "CLEAR")
      (footprint "eagle-import:LED-RGB-THRU")
      (libsource (lib "eagle-import") (part "LED-RGB-CCCLEAR"))
    )
    (comp (ref "D284")
      (value "CLEAR")
      (footprint "eagle-import:LED-RGB-THRU")
      (libsource (lib "eagle-import") (part "LED-RGB-CCCLEAR"))
    )
    (comp (ref "D285")
      (value "CLEAR")
      (footprint "eagle-import:LED-RGB-THRU")
      (libsource (lib "eagle-import") (part "LED-RGB-CCCLEAR"))
    )
    (comp (ref "D286")
      (value "CLEAR")
      (footprint "eagle-import:LED-RGB-THRU")
      (libsource (lib "eagle-import") (part "LED-RGB-CCCLEAR"))
    )
    (comp (ref "D287")
      (value "CLEAR")
      (footprint "eagle-import:LED-RGB-THRU")
      (libsource (lib "eagle-import") (part "LED-RGB-CCCLEAR"))
    )
    (comp (ref "D288")
      (value "CLEAR")
      (footprint "eagle-import:LED-RGB-THRU")
      (libsource (lib "eagle-import") (part "LED-RGB-CCCLEAR"))
    )
    (comp (ref "D289")
      (value "CLEAR")
      (footprint "eagle-import:LED-RGB-THRU")
      (libsource (lib "eagle-import") (part "LED-RGB-CCCLEAR"))
    )
    (comp (ref "D290")
      (value "CLEAR")
      (footprint "eagle-import:LED-RGB-THRU")
      (libsource (lib "eagle-import") (part "LED-RGB-CCCLEAR"))
    )
    (comp (ref "D291")
      (value "CLEAR")
      (footprint "eagle-import:LED-RGB-THRU")
      (libsource (lib "eagle-import") (part "LED-RGB-CCCLEAR"))
    )
    (comp (ref "D292")
      (value "CLEAR")
      (footprint "eagle-import:LED-RGB-THRU")
      (libsource (lib "eagle-import") (part "LED-RGB-CCCLEAR"))
    )
    (comp (ref "D293")
      (value "CLEAR")
      (footprint "eagle-import:LED-RGB-THRU")
      (libsource (lib "eagle-import") (part "LED-RGB-CCCLEAR"))
    )
    (comp (ref "D294")
      (value "CLEAR")
      (footprint "eagle-import:LED-RGB-THRU")
      (libsource (lib "eagle-import") (part "LED-RGB-CCCLEAR"))
    )
    (comp (ref "D295")
      (value "CLEAR")
      (footprint "eagle-import:LED-RGB-THRU")
      (libsource (lib "eagle-import") (part "LED-RGB-CCCLEAR"))
    )
    (comp (ref "D296")
      (value "CLEAR")
      (footprint "eagle-import:LED-RGB-THRU")
      (libsource (lib "eagle-import") (part "LED-RGB-CCCLEAR"))
    )
    (comp (ref "D297")
      (value "CLEAR")
      (footprint "eagle-import:LED-RGB-THRU")
      (libsource (lib "eagle-import") (part "LED-RGB-CCCLEAR"))
    )
    (comp (ref "D298")
      (value "CLEAR")
      (footprint "eagle-import:LED-RGB-THRU")
      (libsource (lib "eagle-import") (part "LED-RGB-CCCLEAR"))
    )
    (comp (ref "D299")
      (value "CLEAR")
      (footprint "eagle-import:LED-RGB-THRU")
      (libsource (lib "eagle-import") (part "LED-RGB-CCCLEAR"))
    )
    (comp (ref "D300")
      (value "CLEAR")
      (footprint "eagle-import:LED-RGB-THRU")
      (libsource (lib "eagle-import") (part "LED-RGB-CCCLEAR"))
    )
    (comp (ref "D301")
      (value "CLEAR")
      (footprint "eagle-import:LED-RGB-THRU")
      (libsource (lib "eagle-import") (part "LED-RGB-CCCLEAR"))
    )
    (comp (ref "D302")
      (value "CLEAR")
      (footprint "eagle-import:LED-RGB-THRU")
      (libsource (lib "eagle-import") (part "LED-RGB-CCCLEAR"))
    )
    (comp (ref "D303")
      (value "CLEAR")
      (footprint "eagle-import:LED-RGB-THRU")
      (libsource (lib "eagle-import") (part "LED-RGB-CCCLEAR"))
    )
    (comp (ref "D304")
      (value "CLEAR")
      (footprint "eagle-import:LED-RGB-THRU")
      (libsource (lib "eagle-import") (part "LED-RGB-CCCLEAR"))
    )
    (comp (ref "D305")
      (value "CLEAR")
      (footprint "eagle-import:LED-RGB-THRU")
      (libsource (lib "eagle-import") (part "LED-RGB-CCCLEAR"))
    )
    (comp (ref "D306")
      (value "CLEAR")
      (footprint "eagle-import:LED-RGB-THRU")
      (libsource (lib "eagle-import") (part "LED-RGB-CCCLEAR"))
    )
    (comp (ref "D307")
      (value "CLEAR")
      (footprint "eagle-import:LED-RGB-THRU")
      (libsource (lib "eagle-import") (part "LED-RGB-CCCLEAR"))
    )
    (comp (ref "D308")
      (value "CLEAR")
      (footprint "eagle-import:LED-RGB-THRU")
      (libsource (lib "eagle-import") (part "LED-RGB-CCCLEAR"))
    )
    (comp (ref "D309")
      (value "CLEAR")
      (footprint "eagle-import:LED-RGB-THRU")
      (libsource (lib "eagle-import") (part "LED-RGB-CCCLEAR"))
    )
    (comp (ref "D310")
      (value "CLEAR")
      (footprint "eagle-import:LED-RGB-THRU")
      (libsource (lib "eagle-import") (part "LED-RGB-CCCLEAR"))
    )
    (comp (ref "D311")
      (value "CLEAR")
      (footprint "eagle-import:LED-RGB-THRU")
      (libsource (lib "eagle-import") (part "LED-RGB-CCCLEAR"))
    )
    (comp (ref "D312")
      (value "CLEAR")
      (footprint "eagle-import:LED-RGB-THRU")
      (libsource (lib "eagle-import") (part "LED-RGB-CCCLEAR"))
    )
    (comp (ref "D313")
      (value "CLEAR")
      (footprint "eagle-import:LED-RGB-THRU")
      (libsource (lib "eagle-import") (part "LED-RGB-CCCLEAR"))
    )
    (comp (ref "D314")
      (value "CLEAR")
      (footprint "eagle-import:LED-RGB-THRU")
      (libsource (lib "eagle-import") (part "LED-RGB-CCCLEAR"))
    )
    (comp (ref "D315")
      (value "CLEAR")
      (footprint "eagle-import:LED-RGB-THRU")
      (libsource (lib "eagle-import") (part "LED-RGB-CCCLEAR"))
    )
    (comp (ref "D316")
      (value "CLEAR")
      (footprint "eagle-import:LED-RGB-THRU")
      (libsource (lib "eagle-import") (part "LED-RGB-CCCLEAR"))
    )
    (comp (ref "D317")
      (value "CLEAR")
      (footprint "eagle-import:LED-RGB-THRU")
      (libsource (lib "eagle-import") (part "LED-RGB-CCCLEAR"))
    )
    (comp (ref "D318")
      (value "CLEAR")
      (footprint "eagle-import:LED-RGB-THRU")
      (libsource (lib "eagle-import") (part "LED-RGB-CCCLEAR"))
    )
    (comp (ref "D319")
      (value "CLEAR")
      (footprint "eagle-import:LED-RGB-THRU")
      (libsource (lib "eagle-import") (part "LED-RGB-CCCLEAR"))
    )
    (comp (ref "D320")
      (value "CLEAR")
      (footprint "eagle-import:LED-RGB-THRU")
      (libsource (lib "eagle-import") (part "LED-RGB-CCCLEAR"))
    )
    (comp (ref "D321")
      (value "CLEAR")
      (footprint "eagle-import:LED-RGB-THRU")
      (libsource (lib "eagle-import") (part "LED-RGB-CCCLEAR"))
    )
    (comp (ref "D322")
      (value "CLEAR")
      (footprint "eagle-import:LED-RGB-THRU")
      (libsource (lib "eagle-import") (part "LED-RGB-CCCLEAR"))
    )
    (comp (ref "D323")
      (value "CLEAR")
      (footprint "eagle-import:LED-RGB-THRU")
      (libsource (lib "eagle-import") (part "LED-RGB-CCCLEAR"))
    )
    (comp (ref "D324")
      (value "CLEAR")
      (footprint "eagle-import:LED-RGB-THRU")
      (libsource (lib "eagle-import") (part "LED-RGB-CCCLEAR"))
    )
    (comp (ref "D325")
      (value "CLEAR")
      (footprint "eagle-import:LED-RGB-THRU")
      (libsource (lib "eagle-import") (part "LED-RGB-CCCLEAR"))
    )
    (comp (ref "D326")
      (value "CLEAR")
      (footprint "eagle-import:LED-RGB-THRU")
      (libsource (lib "eagle-import") (part "LED-RGB-CCCLEAR"))
    )
    (comp (ref "D327")
      (value "CLEAR")
      (footprint "eagle-import:LED-RGB-THRU")
      (libsource (lib "eagle-import") (part "LED-RGB-CCCLEAR"))
    )
    (comp (ref "D328")
      (value "CLEAR")
      (footprint "eagle-import:LED-RGB-THRU")
      (libsource (lib "eagle-import") (part "LED-RGB-CCCLEAR"))
    )
    (comp (ref "D329")
      (value "CLEAR")
      (footprint "eagle-import:LED-RGB-THRU")
      (libsource (lib "eagle-import") (part "LED-RGB-CCCLEAR"))
    )
    (comp (ref "D330")
      (value "CLEAR")
      (footprint "eagle-import:LED-RGB-THRU")
      (libsource (lib "eagle-import") (part "LED-RGB-CCCLEAR"))
    )
    (comp (ref "D331")
      (value "CLEAR")
      (footprint "eagle-import:LED-RGB-THRU")
      (libsource (lib "eagle-import") (part "LED-RGB-CCCLEAR"))
    )
    (comp (ref "D332")
      (value "CLEAR")
      (footprint "eagle-import:LED-RGB-THRU")
      (libsource (lib "eagle-import") (part "LED-RGB-CCCLEAR"))
    )
    (comp (ref "D333")
      (value "CLEAR")
      (footprint "eagle-import:LED-RGB-THRU")
      (libsource (lib "eagle-import") (part "LED-RGB-CCCLEAR"))
    )
    (comp (ref "D334")
      (value "CLEAR")
      (footprint "eagle-import:LED-RGB-THRU")
      (libsource (lib "eagle-import") (part "LED-RGB-CCCLEAR"))
    )
    (comp (ref "D335")
      (value "CLEAR")
      (footprint "eagle-import:LED-RGB-THRU")
      (libsource (lib "eagle-import") (part "LED-RGB-CCCLEAR"))
    )
    (comp (ref "D336")
      (value "CLEAR")
      (footprint "eagle-import:LED-RGB-THRU")
      (libsource (lib "eagle-import") (part "LED-RGB-CCCLEAR"))
    )
    (comp (ref "D337")
      (value "CLEAR")
      (footprint "eagle-import:LED-RGB-THRU")
      (libsource (lib "eagle-import") (part "LED-RGB-CCCLEAR"))
    )
    (comp (ref "D338")
      (value "CLEAR")
      (footprint "eagle-import:LED-RGB-THRU")
      (libsource (lib "eagle-import") (part "LED-RGB-CCCLEAR"))
    )
    (comp (ref "D339")
      (value "CLEAR")
      (footprint "eagle-import:LED-RGB-THRU")
      (libsource (lib "eagle-import") (part "LED-RGB-CCCLEAR"))
    )
    (comp (ref "D340")
      (value "CLEAR")
      (footprint "eagle-import:LED-RGB-THRU")
      (libsource (lib "eagle-import") (part "LED-RGB-CCCLEAR"))
    )
    (comp (ref "D341")
      (value "CLEAR")
      (footprint "eagle-import:LED-RGB-THRU")
      (libsource (lib "eagle-import") (part "LED-RGB-CCCLEAR"))
    )
    (comp (ref "D342")
      (value "CLEAR")
      (footprint "eagle-import:LED-RGB-THRU")
      (libsource (lib "eagle-import") (part "LED-RGB-CCCLEAR"))
    )
    (comp (ref "D343")
      (value "CLEAR")
      (footprint "eagle-import:LED-RGB-THRU")
      (libsource (lib "eagle-import") (part "LED-RGB-CCCLEAR"))
    )
    (comp (ref "D344")
      (value "CLEAR")
      (footprint "eagle-import:LED-RGB-THRU")
      (libsource (lib "eagle-import") (part "LED-RGB-CCCLEAR"))
    )
    (comp (ref "D345")
      (value "CLEAR")
      (footprint "eagle-import:LED-RGB-THRU")
      (libsource (lib "eagle-import") (part "LED-RGB-CCCLEAR"))
    )
    (comp (ref "D346")
      (value "CLEAR")
      (footprint "eagle-import:LED-RGB-THRU")
      (libsource (lib "eagle-import") (part "LED-RGB-CCCLEAR"))
    )
    (comp (ref "D347")
      (value "CLEAR")
      (footprint "eagle-import:LED-RGB-THRU")
      (libsource (lib "eagle-import") (part "LED-RGB-CCCLEAR"))
    )
    (comp (ref "D348")
      (value "CLEAR")
      (footprint "eagle-import:LED-RGB-THRU")
      (libsource (lib "eagle-import") (part "LED-RGB-CCCLEAR"))
    )
    (comp (ref "D349")
      (value "CLEAR")
      (footprint "eagle-import:LED-RGB-THRU")
      (libsource (lib "eagle-import") (part "LED-RGB-CCCLEAR"))
    )
    (comp (ref "D350")
      (value "CLEAR")
      (footprint "eagle-import:LED-RGB-THRU")
      (libsource (lib "eagle-import") (part "LED-RGB-CCCLEAR"))
    )
    (comp (ref "D351")
      (value "CLEAR")
      (footprint "eagle-import:LED-RGB-THRU")
      (libsource (lib "eagle-import") (part "LED-RGB-CCCLEAR"))
    )
    (comp (ref "D352")
      (value "CLEAR")
      (footprint "eagle-import:LED-RGB-THRU")
      (libsource (lib "eagle-import") (part "LED-RGB-CCCLEAR"))
    )
    (comp (ref "D353")
      (value "CLEAR")
      (footprint "eagle-import:LED-RGB-THRU")
      (libsource (lib "eagle-import") (part "LED-RGB-CCCLEAR"))
    )
    (comp (ref "D354")
      (value "CLEAR")
      (footprint "eagle-import:LED-RGB-THRU")
      (libsource (lib "eagle-import") (part "LED-RGB-CCCLEAR"))
    )
    (comp (ref "D355")
      (value "CLEAR")
      (footprint "eagle-import:LED-RGB-THRU")
      (libsource (lib "eagle-import") (part "LED-RGB-CCCLEAR"))
    )
    (comp (ref "D356")
      (value "CLEAR")
      (footprint "eagle-import:LED-RGB-THRU")
      (libsource (lib "eagle-import") (part "LED-RGB-CCCLEAR"))
    )
    (comp (ref "D357")
      (value "CLEAR")
      (footprint "eagle-import:LED-RGB-THRU")
      (libsource (lib "eagle-import") (part "LED-RGB-CCCLEAR"))
    )
    (comp (ref "D358")
      (value "CLEAR")
      (footprint "eagle-import:LED-RGB-THRU")
      (libsource (lib "eagle-import") (part "LED-RGB-CCCLEAR"))
    )
    (comp (ref "D359")
      (value "CLEAR")
      (footprint "eagle-import:LED-RGB-THRU")
      (libsource (lib "eagle-import") (part "LED-RGB-CCCLEAR"))
    )
    (comp (ref "D360")
      (value "CLEAR")
      (footprint "eagle-import:LED-RGB-THRU")
      (libsource (lib "eagle-import") (part "LED-RGB-CCCLEAR"))
    )
    (comp (ref "D361")
      (value "CLEAR")
      (footprint "eagle-import:LED-RGB-THRU")
      (libsource (lib "eagle-import") (part "LED-RGB-CCCLEAR"))
    )
    (comp (ref "D362")
      (value "CLEAR")
      (footprint "eagle-import:LED-RGB-THRU")
      (libsource (lib "eagle-import") (part "LED-RGB-CCCLEAR"))
    )
    (comp (ref "D363")
      (value "CLEAR")
      (footprint "eagle-import:LED-RGB-THRU")
      (libsource (lib "eagle-import") (part "LED-RGB-CCCLEAR"))
    )
    (comp (ref "D364")
      (value "CLEAR")
      (footprint "eagle-import:LED-RGB-THRU")
      (libsource (lib "eagle-import") (part "LED-RGB-CCCLEAR"))
    )
    (comp (ref "D365")
      (value "CLEAR")
      (footprint "eagle-import:LED-RGB-THRU")
      (libsource (lib "eagle-import") (part "LED-RGB-CCCLEAR"))
    )
    (comp (ref "D366")
      (value "CLEAR")
      (footprint "eagle-import:LED-RGB-THRU")
      (libsource (lib "eagle-import") (part "LED-RGB-CCCLEAR"))
    )
    (comp (ref "D367")
      (value "CLEAR")
      (footprint "eagle-import:LED-RGB-THRU")
      (libsource (lib "eagle-import") (part "LED-RGB-CCCLEAR"))
    )
    (comp (ref "D368")
      (value "CLEAR")
      (footprint "eagle-import:LED-RGB-THRU")
      (libsource (lib "eagle-import") (part "LED-RGB-CCCLEAR"))
    )
    (comp (ref "D369")
      (value "CLEAR")
      (footprint "eagle-import:LED-RGB-THRU")
      (libsource (lib "eagle-import") (part "LED-RGB-CCCLEAR"))
    )
    (comp (ref "D370")
      (value "CLEAR")
      (footprint "eagle-import:LED-RGB-THRU")
      (libsource (lib "eagle-import") (part "LED-RGB-CCCLEAR"))
    )
    (comp (ref "D371")
      (value "CLEAR")
      (footprint "eagle-import:LED-RGB-THRU")
      (libsource (lib "eagle-import") (part "LED-RGB-CCCLEAR"))
    )
    (comp (ref "D372")
      (value "CLEAR")
      (footprint "eagle-import:LED-RGB-THRU")
      (libsource (lib "eagle-import") (part "LED-RGB-CCCLEAR"))
    )
    (comp (ref "D373")
      (value "CLEAR")
      (footprint "eagle-import:LED-RGB-THRU")
      (libsource (lib "eagle-import") (part "LED-RGB-CCCLEAR"))
    )
    (comp (ref "D374")
      (value "CLEAR")
      (footprint "eagle-import:LED-RGB-THRU")
      (libsource (lib "eagle-import") (part "LED-RGB-CCCLEAR"))
    )
    (comp (ref "D375")
      (value "CLEAR")
      (footprint "eagle-import:LED-RGB-THRU")
      (libsource (lib "eagle-import") (part "LED-RGB-CCCLEAR"))
    )
    (comp (ref "D376")
      (value "CLEAR")
      (footprint "eagle-import:LED-RGB-THRU")
      (libsource (lib "eagle-import") (part "LED-RGB-CCCLEAR"))
    )
    (comp (ref "D377")
      (value "CLEAR")
      (footprint "eagle-import:LED-RGB-THRU")
      (libsource (lib "eagle-import") (part "LED-RGB-CCCLEAR"))
    )
    (comp (ref "D378")
      (value "CLEAR")
      (footprint "eagle-import:LED-RGB-THRU")
      (libsource (lib "eagle-import") (part "LED-RGB-CCCLEAR"))
    )
    (comp (ref "D379")
      (value "CLEAR")
      (footprint "eagle-import:LED-RGB-THRU")
      (libsource (lib "eagle-import") (part "LED-RGB-CCCLEAR"))
    )
    (comp (ref "D380")
      (value "CLEAR")
      (footprint "eagle-import:LED-RGB-THRU")
      (libsource (lib "eagle-import") (part "LED-RGB-CCCLEAR"))
    )
    (comp (ref "D381")
      (value "CLEAR")
      (footprint "eagle-import:LED-RGB-THRU")
      (libsource (lib "eagle-import") (part "LED-RGB-CCCLEAR"))
    )
    (comp (ref "D382")
      (value "CLEAR")
      (footprint "eagle-import:LED-RGB-THRU")
      (libsource (lib "eagle-import") (part "LED-RGB-CCCLEAR"))
    )
    (comp (ref "D383")
      (value "CLEAR")
      (footprint "eagle-import:LED-RGB-THRU")
      (libsource (lib "eagle-import") (part "LED-RGB-CCCLEAR"))
    )
    (comp (ref "D384")
      (value "CLEAR")
      (footprint "eagle-import:LED-RGB-THRU")
      (libsource (lib "eagle-import") (part "LED-RGB-CCCLEAR"))
    )
    (comp (ref "D385")
      (value "CLEAR")
      (footprint "eagle-import:LED-RGB-THRU")
      (libsource (lib "eagle-import") (part "LED-RGB-CCCLEAR"))
    )
    (comp (ref "D386")
      (value "CLEAR")
      (footprint "eagle-import:LED-RGB-THRU")
      (libsource (lib "eagle-import") (part "LED-RGB-CCCLEAR"))
    )
    (comp (ref "D387")
      (value "CLEAR")
      (footprint "eagle-import:LED-RGB-THRU")
      (libsource (lib "eagle-import") (part "LED-RGB-CCCLEAR"))
    )
    (comp (ref "D388")
      (value "CLEAR")
      (footprint "eagle-import:LED-RGB-THRU")
      (libsource (lib "eagle-import") (part "LED-RGB-CCCLEAR"))
    )
    (comp (ref "D389")
      (value "CLEAR")
      (footprint "eagle-import:LED-RGB-THRU")
      (libsource (lib "eagle-import") (part "LED-RGB-CCCLEAR"))
    )
    (comp (ref "D390")
      (value "CLEAR")
      (footprint "eagle-import:LED-RGB-THRU")
      (libsource (lib "eagle-import") (part "LED-RGB-CCCLEAR"))
    )
    (comp (ref "D391")
      (value "CLEAR")
      (footprint "eagle-import:LED-RGB-THRU")
      (libsource (lib "eagle-import") (part "LED-RGB-CCCLEAR"))
    )
    (comp (ref "D392")
      (value "CLEAR")
      (footprint "eagle-import:LED-RGB-THRU")
      (libsource (lib "eagle-import") (part "LED-RGB-CCCLEAR"))
    )
    (comp (ref "D393")
      (value "CLEAR")
      (footprint "eagle-import:LED-RGB-THRU")
      (libsource (lib "eagle-import") (part "LED-RGB-CCCLEAR"))
    )
    (comp (ref "D394")
      (value "CLEAR")
      (footprint "eagle-import:LED-RGB-THRU")
      (libsource (lib "eagle-import") (part "LED-RGB-CCCLEAR"))
    )
    (comp (ref "D395")
      (value "CLEAR")
      (footprint "eagle-import:LED-RGB-THRU")
      (libsource (lib "eagle-import") (part "LED-RGB-CCCLEAR"))
    )
    (comp (ref "D396")
      (value "CLEAR")
      (footprint "eagle-import:LED-RGB-THRU")
      (libsource (lib "eagle-import") (part "LED-RGB-CCCLEAR"))
    )
    (comp (ref "D397")
      (value "CLEAR")
      (footprint "eagle-import:LED-RGB-THRU")
      (libsource (lib "eagle-import") (part "LED-RGB-CCCLEAR"))
    )
    (comp (ref "D398")
      (value "CLEAR")
      (footprint "eagle-import:LED-RGB-THRU")
      (libsource (lib "eagle-import") (part "LED-RGB-CCCLEAR"))
    )
    (comp (ref "D399")
      (value "CLEAR")
      (footprint "eagle-import:LED-RGB-THRU")
      (libsource (lib "eagle-import") (part "LED-RGB-CCCLEAR"))
    )
    (comp (ref "D400")
      (value "CLEAR")
      (footprint "eagle-import:LED-RGB-THRU")
      (libsource (lib "eagle-import") (part "LED-RGB-CCCLEAR"))
    )
    (comp (ref "D401")
      (value "CLEAR")
      (footprint "eagle-import:LED-RGB-THRU")
      (libsource (lib "eagle-import") (part "LED-RGB-CCCLEAR"))
    )
    (comp (ref "D402")
      (value "CLEAR")
      (footprint "eagle-import:LED-RGB-THRU")
      (libsource (lib "eagle-import") (part "LED-RGB-CCCLEAR"))
    )
    (comp (ref "D403")
      (value "CLEAR")
      (footprint "eagle-import:LED-RGB-THRU")
      (libsource (lib "eagle-import") (part "LED-RGB-CCCLEAR"))
    )
    (comp (ref "D404")
      (value "CLEAR")
      (footprint "eagle-import:LED-RGB-THRU")
      (libsource (lib "eagle-import") (part "LED-RGB-CCCLEAR"))
    )
    (comp (ref "D405")
      (value "CLEAR")
      (footprint "eagle-import:LED-RGB-THRU")
      (libsource (lib "eagle-import") (part "LED-RGB-CCCLEAR"))
    )
    (comp (ref "D406")
      (value "CLEAR")
      (footprint "eagle-import:LED-RGB-THRU")
      (libsource (lib "eagle-import") (part "LED-RGB-CCCLEAR"))
    )
    (comp (ref "D407")
      (value "CLEAR")
      (footprint "eagle-import:LED-RGB-THRU")
      (libsource (lib "eagle-import") (part "LED-RGB-CCCLEAR"))
    )
    (comp (ref "D408")
      (value "CLEAR")
      (footprint "eagle-import:LED-RGB-THRU")
      (libsource (lib "eagle-import") (part "LED-RGB-CCCLEAR"))
    )
    (comp (ref "D409")
      (value "CLEAR")
      (footprint "eagle-import:LED-RGB-THRU")
      (libsource (lib "eagle-import") (part "LED-RGB-CCCLEAR"))
    )
    (comp (ref "D410")
      (value "CLEAR")
      (footprint "eagle-import:LED-RGB-THRU")
      (libsource (lib "eagle-import") (part "LED-RGB-CCCLEAR"))
    )
    (comp (ref "D411")
      (value "CLEAR")
      (footprint "eagle-import:LED-RGB-THRU")
      (libsource (lib "eagle-import") (part "LED-RGB-CCCLEAR"))
    )
    (comp (ref "D412")
      (value "CLEAR")
      (footprint "eagle-import:LED-RGB-THRU")
      (libsource (lib "eagle-import") (part "LED-RGB-CCCLEAR"))
    )
    (comp (ref "D413")
      (value "CLEAR")
      (footprint "eagle-import:LED-RGB-THRU")
      (libsource (lib "eagle-import") (part "LED-RGB-CCCLEAR"))
    )
    (comp (ref "D414")
      (value "CLEAR")
      (footprint "eagle-import:LED-RGB-THRU")
      (libsource (lib "eagle-import") (part "LED-RGB-CCCLEAR"))
    )
    (comp (ref "D415")
      (value "CLEAR")
      (footprint "eagle-import:LED-RGB-THRU")
      (libsource (lib "eagle-import") (part "LED-RGB-CCCLEAR"))
    )
    (comp (ref "D416")
      (value "CLEAR")
      (footprint "eagle-import:LED-RGB-THRU")
      (libsource (lib "eagle-import") (part "LED-RGB-CCCLEAR"))
    )
    (comp (ref "D417")
      (value "CLEAR")
      (footprint "eagle-import:LED-RGB-THRU")
      (libsource (lib "eagle-import") (part "LED-RGB-CCCLEAR"))
    )
    (comp (ref "D418")
      (value "CLEAR")
      (footprint "eagle-import:LED-RGB-THRU")
      (libsource (lib "eagle-import") (part "LED-RGB-CCCLEAR"))
    )
    (comp (ref "D419")
      (value "CLEAR")
      (footprint "eagle-import:LED-RGB-THRU")
      (libsource (lib "eagle-import") (part "LED-RGB-CCCLEAR"))
    )
    (comp (ref "D420")
      (value "CLEAR")
      (footprint "eagle-import:LED-RGB-THRU")
      (libsource (lib "eagle-import") (part "LED-RGB-CCCLEAR"))
    )
    (comp (ref "D421")
      (value "CLEAR")
      (footprint "eagle-import:LED-RGB-THRU")
      (libsource (lib "eagle-import") (part "LED-RGB-CCCLEAR"))
    )
    (comp (ref "D422")
      (value "CLEAR")
      (footprint "eagle-import:LED-RGB-THRU")
      (libsource (lib "eagle-import") (part "LED-RGB-CCCLEAR"))
    )
    (comp (ref "D423")
      (value "CLEAR")
      (footprint "eagle-import:LED-RGB-THRU")
      (libsource (lib "eagle-import") (part "LED-RGB-CCCLEAR"))
    )
    (comp (ref "D424")
      (value "CLEAR")
      (footprint "eagle-import:LED-RGB-THRU")
      (libsource (lib "eagle-import") (part "LED-RGB-CCCLEAR"))
    )
    (comp (ref "D425")
      (value "CLEAR")
      (footprint "eagle-import:LED-RGB-THRU")
      (libsource (lib "eagle-import") (part "LED-RGB-CCCLEAR"))
    )
    (comp (ref "D426")
      (value "CLEAR")
      (footprint "eagle-import:LED-RGB-THRU")
      (libsource (lib "eagle-import") (part "LED-RGB-CCCLEAR"))
    )
    (comp (ref "D427")
      (value "CLEAR")
      (footprint "eagle-import:LED-RGB-THRU")
      (libsource (lib "eagle-import") (part "LED-RGB-CCCLEAR"))
    )
    (comp (ref "D428")
      (value "CLEAR")
      (footprint "eagle-import:LED-RGB-THRU")
      (libsource (lib "eagle-import") (part "LED-RGB-CCCLEAR"))
    )
    (comp (ref "D429")
      (value "CLEAR")
      (footprint "eagle-import:LED-RGB-THRU")
      (libsource (lib "eagle-import") (part "LED-RGB-CCCLEAR"))
    )
    (comp (ref "D430")
      (value "CLEAR")
      (footprint "eagle-import:LED-RGB-THRU")
      (libsource (lib "eagle-import") (part "LED-RGB-CCCLEAR"))
    )
    (comp (ref "D431")
      (value "CLEAR")
      (footprint "eagle-import:LED-RGB-THRU")
      (libsource (lib "eagle-import") (part "LED-RGB-CCCLEAR"))
    )
    (comp (ref "D432")
      (value "CLEAR")
      (footprint "eagle-import:LED-RGB-THRU")
      (libsource (lib "eagle-import") (part "LED-RGB-CCCLEAR"))
    )
    (comp (ref "D433")
      (value "CLEAR")
      (footprint "eagle-import:LED-RGB-THRU")
      (libsource (lib "eagle-import") (part "LED-RGB-CCCLEAR"))
    )
    (comp (ref "D434")
      (value "CLEAR")
      (footprint "eagle-import:LED-RGB-THRU")
      (libsource (lib "eagle-import") (part "LED-RGB-CCCLEAR"))
    )
    (comp (ref "D435")
      (value "CLEAR")
      (footprint "eagle-import:LED-RGB-THRU")
      (libsource (lib "eagle-import") (part "LED-RGB-CCCLEAR"))
    )
    (comp (ref "D436")
      (value "CLEAR")
      (footprint "eagle-import:LED-RGB-THRU")
      (libsource (lib "eagle-import") (part "LED-RGB-CCCLEAR"))
    )
    (comp (ref "D437")
      (value "CLEAR")
      (footprint "eagle-import:LED-RGB-THRU")
      (libsource (lib "eagle-import") (part "LED-RGB-CCCLEAR"))
    )
    (comp (ref "D438")
      (value "CLEAR")
      (footprint "eagle-import:LED-RGB-THRU")
      (libsource (lib "eagle-import") (part "LED-RGB-CCCLEAR"))
    )
    (comp (ref "D439")
      (value "CLEAR")
      (footprint "eagle-import:LED-RGB-THRU")
      (libsource (lib "eagle-import") (part "LED-RGB-CCCLEAR"))
    )
    (comp (ref "D440")
      (value "CLEAR")
      (footprint "eagle-import:LED-RGB-THRU")
      (libsource (lib "eagle-import") (part "LED-RGB-CCCLEAR"))
    )
    (comp (ref "D441")
      (value "CLEAR")
      (footprint "eagle-import:LED-RGB-THRU")
      (libsource (lib "eagle-import") (part "LED-RGB-CCCLEAR"))
    )
    (comp (ref "D442")
      (value "CLEAR")
      (footprint "eagle-import:LED-RGB-THRU")
      (libsource (lib "eagle-import") (part "LED-RGB-CCCLEAR"))
    )
    (comp (ref "D443")
      (value "CLEAR")
      (footprint "eagle-import:LED-RGB-THRU")
      (libsource (lib "eagle-import") (part "LED-RGB-CCCLEAR"))
    )
    (comp (ref "D444")
      (value "CLEAR")
      (footprint "eagle-import:LED-RGB-THRU")
      (libsource (lib "eagle-import") (part "LED-RGB-CCCLEAR"))
    )
    (comp (ref "D445")
      (value "CLEAR")
      (footprint "eagle-import:LED-RGB-THRU")
      (libsource (lib "eagle-import") (part "LED-RGB-CCCLEAR"))
    )
    (comp (ref "D446")
      (value "CLEAR")
      (footprint "eagle-import:LED-RGB-THRU")
      (libsource (lib "eagle-import") (part "LED-RGB-CCCLEAR"))
    )
    (comp (ref "D447")
      (value "CLEAR")
      (footprint "eagle-import:LED-RGB-THRU")
      (libsource (lib "eagle-import") (part "LED-RGB-CCCLEAR"))
    )
    (comp (ref "D448")
      (value "CLEAR")
      (footprint "eagle-import:LED-RGB-THRU")
      (libsource (lib "eagle-import") (part "LED-RGB-CCCLEAR"))
    )
    (comp (ref "D449")
      (value "CLEAR")
      (footprint "eagle-import:LED-RGB-THRU")
      (libsource (lib "eagle-import") (part "LED-RGB-CCCLEAR"))
    )
    (comp (ref "D450")
      (value "CLEAR")
      (footprint "eagle-import:LED-RGB-THRU")
      (libsource (lib "eagle-import") (part "LED-RGB-CCCLEAR"))
    )
    (comp (ref "D451")
      (value "CLEAR")
      (footprint "eagle-import:LED-RGB-THRU")
      (libsource (lib "eagle-import") (part "LED-RGB-CCCLEAR"))
    )
    (comp (ref "D452")
      (value "CLEAR")
      (footprint "eagle-import:LED-RGB-THRU")
      (libsource (lib "eagle-import") (part "LED-RGB-CCCLEAR"))
    )
    (comp (ref "D453")
      (value "CLEAR")
      (footprint "eagle-import:LED-RGB-THRU")
      (libsource (lib "eagle-import") (part "LED-RGB-CCCLEAR"))
    )
    (comp (ref "D454")
      (value "CLEAR")
      (footprint "eagle-import:LED-RGB-THRU")
      (libsource (lib "eagle-import") (part "LED-RGB-CCCLEAR"))
    )
    (comp (ref "D455")
      (value "CLEAR")
      (footprint "eagle-import:LED-RGB-THRU")
      (libsource (lib "eagle-import") (part "LED-RGB-CCCLEAR"))
    )
    (comp (ref "D456")
      (value "CLEAR")
      (footprint "eagle-import:LED-RGB-THRU")
      (libsource (lib "eagle-import") (part "LED-RGB-CCCLEAR"))
    )
    (comp (ref "D457")
      (value "CLEAR")
      (footprint "eagle-import:LED-RGB-THRU")
      (libsource (lib "eagle-import") (part "LED-RGB-CCCLEAR"))
    )
    (comp (ref "D458")
      (value "CLEAR")
      (footprint "eagle-import:LED-RGB-THRU")
      (libsource (lib "eagle-import") (part "LED-RGB-CCCLEAR"))
    )
    (comp (ref "D459")
      (value "CLEAR")
      (footprint "eagle-import:LED-RGB-THRU")
      (libsource (lib "eagle-import") (part "LED-RGB-CCCLEAR"))
    )
    (comp (ref "D460")
      (value "CLEAR")
      (footprint "eagle-import:LED-RGB-THRU")
      (libsource (lib "eagle-import") (part "LED-RGB-CCCLEAR"))
    )
    (comp (ref "D461")
      (value "CLEAR")
      (footprint "eagle-import:LED-RGB-THRU")
      (libsource (lib "eagle-import") (part "LED-RGB-CCCLEAR"))
    )
    (comp (ref "D462")
      (value "CLEAR")
      (footprint "eagle-import:LED-RGB-THRU")
      (libsource (lib "eagle-import") (part "LED-RGB-CCCLEAR"))
    )
    (comp (ref "D463")
      (value "CLEAR")
      (footprint "eagle-import:LED-RGB-THRU")
      (libsource (lib "eagle-import") (part "LED-RGB-CCCLEAR"))
    )
    (comp (ref "D464")
      (value "CLEAR")
      (footprint "eagle-import:LED-RGB-THRU")
      (libsource (lib "eagle-import") (part "LED-RGB-CCCLEAR"))
    )
    (comp (ref "D465")
      (value "CLEAR")
      (footprint "eagle-import:LED-RGB-THRU")
      (libsource (lib "eagle-import") (part "LED-RGB-CCCLEAR"))
    )
    (comp (ref "D466")
      (value "CLEAR")
      (footprint "eagle-import:LED-RGB-THRU")
      (libsource (lib "eagle-import") (part "LED-RGB-CCCLEAR"))
    )
    (comp (ref "D467")
      (value "CLEAR")
      (footprint "eagle-import:LED-RGB-THRU")
      (libsource (lib "eagle-import") (part "LED-RGB-CCCLEAR"))
    )
    (comp (ref "D468")
      (value "CLEAR")
      (footprint "eagle-import:LED-RGB-THRU")
      (libsource (lib "eagle-import") (part "LED-RGB-CCCLEAR"))
    )
    (comp (ref "D469")
      (value "CLEAR")
      (footprint "eagle-import:LED-RGB-THRU")
      (libsource (lib "eagle-import") (part "LED-RGB-CCCLEAR"))
    )
    (comp (ref "D470")
      (value "CLEAR")
      (footprint "eagle-import:LED-RGB-THRU")
      (libsource (lib "eagle-import") (part "LED-RGB-CCCLEAR"))
    )
    (comp (ref "D471")
      (value "CLEAR")
      (footprint "eagle-import:LED-RGB-THRU")
      (libsource (lib "eagle-import") (part "LED-RGB-CCCLEAR"))
    )
    (comp (ref "D472")
      (value "CLEAR")
      (footprint "eagle-import:LED-RGB-THRU")
      (libsource (lib "eagle-import") (part "LED-RGB-CCCLEAR"))
    )
    (comp (ref "D473")
      (value "CLEAR")
      (footprint "eagle-import:LED-RGB-THRU")
      (libsource (lib "eagle-import") (part "LED-RGB-CCCLEAR"))
    )
    (comp (ref "D474")
      (value "CLEAR")
      (footprint "eagle-import:LED-RGB-THRU")
      (libsource (lib "eagle-import") (part "LED-RGB-CCCLEAR"))
    )
    (comp (ref "D475")
      (value "CLEAR")
      (footprint "eagle-import:LED-RGB-THRU")
      (libsource (lib "eagle-import") (part "LED-RGB-CCCLEAR"))
    )
    (comp (ref "D476")
      (value "CLEAR")
      (footprint "eagle-import:LED-RGB-THRU")
      (libsource (lib "eagle-import") (part "LED-RGB-CCCLEAR"))
    )
    (comp (ref "D477")
      (value "CLEAR")
      (footprint "eagle-import:LED-RGB-THRU")
      (libsource (lib "eagle-import") (part "LED-RGB-CCCLEAR"))
    )
    (comp (ref "D478")
      (value "CLEAR")
      (footprint "eagle-import:LED-RGB-THRU")
      (libsource (lib "eagle-import") (part "LED-RGB-CCCLEAR"))
    )
    (comp (ref "D479")
      (value "CLEAR")
      (footprint "eagle-import:LED-RGB-THRU")
      (libsource (lib "eagle-import") (part "LED-RGB-CCCLEAR"))
    )
    (comp (ref "D480")
      (value "CLEAR")
      (footprint "eagle-import:LED-RGB-THRU")
      (libsource (lib "eagle-import") (part "LED-RGB-CCCLEAR"))
    )
    (comp (ref "D481")
      (value "CLEAR")
      (footprint "eagle-import:LED-RGB-THRU")
      (libsource (lib "eagle-import") (part "LED-RGB-CCCLEAR"))
    )
    (comp (ref "D482")
      (value "CLEAR")
      (footprint "eagle-import:LED-RGB-THRU")
      (libsource (lib "eagle-import") (part "LED-RGB-CCCLEAR"))
    )
    (comp (ref "D483")
      (value "CLEAR")
      (footprint "eagle-import:LED-RGB-THRU")
      (libsource (lib "eagle-import") (part "LED-RGB-CCCLEAR"))
    )
    (comp (ref "D484")
      (value "CLEAR")
      (footprint "eagle-import:LED-RGB-THRU")
      (libsource (lib "eagle-import") (part "LED-RGB-CCCLEAR"))
    )
    (comp (ref "D485")
      (value "CLEAR")
      (footprint "eagle-import:LED-RGB-THRU")
      (libsource (lib "eagle-import") (part "LED-RGB-CCCLEAR"))
    )
    (comp (ref "D486")
      (value "CLEAR")
      (footprint "eagle-import:LED-RGB-THRU")
      (libsource (lib "eagle-import") (part "LED-RGB-CCCLEAR"))
    )
    (comp (ref "D487")
      (value "CLEAR")
      (footprint "eagle-import:LED-RGB-THRU")
      (libsource (lib "eagle-import") (part "LED-RGB-CCCLEAR"))
    )
    (comp (ref "D488")
      (value "CLEAR")
      (footprint "eagle-import:LED-RGB-THRU")
      (libsource (lib "eagle-import") (part "LED-RGB-CCCLEAR"))
    )
    (comp (ref "D489")
      (value "CLEAR")
      (footprint "eagle-import:LED-RGB-THRU")
      (libsource (lib "eagle-import") (part "LED-RGB-CCCLEAR"))
    )
    (comp (ref "D490")
      (value "CLEAR")
      (footprint "eagle-import:LED-RGB-THRU")
      (libsource (lib "eagle-import") (part "LED-RGB-CCCLEAR"))
    )
    (comp (ref "D491")
      (value "CLEAR")
      (footprint "eagle-import:LED-RGB-THRU")
      (libsource (lib "eagle-import") (part "LED-RGB-CCCLEAR"))
    )
    (comp (ref "D492")
      (value "CLEAR")
      (footprint "eagle-import:LED-RGB-THRU")
      (libsource (lib "eagle-import") (part "LED-RGB-CCCLEAR"))
    )
    (comp (ref "D493")
      (value "CLEAR")
      (footprint "eagle-import:LED-RGB-THRU")
      (libsource (lib "eagle-import") (part "LED-RGB-CCCLEAR"))
    )
    (comp (ref "D494")
      (value "CLEAR")
      (footprint "eagle-import:LED-RGB-THRU")
      (libsource (lib "eagle-import") (part "LED-RGB-CCCLEAR"))
    )
    (comp (ref "D495")
      (value "CLEAR")
      (footprint "eagle-import:LED-RGB-THRU")
      (libsource (lib "eagle-import") (part "LED-RGB-CCCLEAR"))
    )
    (comp (ref "D496")
      (value "CLEAR")
      (footprint "eagle-import:LED-RGB-THRU")
      (libsource (lib "eagle-import") (part "LED-RGB-CCCLEAR"))
    )
    (comp (ref "D497")
      (value "CLEAR")
      (footprint "eagle-import:LED-RGB-THRU")
      (libsource (lib "eagle-import") (part "LED-RGB-CCCLEAR"))
    )
    (comp (ref "D498")
      (value "CLEAR")
      (footprint "eagle-import:LED-RGB-THRU")
      (libsource (lib "eagle-import") (part "LED-RGB-CCCLEAR"))
    )
    (comp (ref "D499")
      (value "CLEAR")
      (footprint "eagle-import:LED-RGB-THRU")
      (libsource (lib "eagle-import") (part "LED-RGB-CCCLEAR"))
    )
    (comp (ref "D500")
      (value "CLEAR")
      (footprint "eagle-import:LED-RGB-THRU")
      (libsource (lib "eagle-import") (part "LED-RGB-CCCLEAR"))
    )
    (comp (ref "D501")
      (value "CLEAR")
      (footprint "eagle-import:LED-RGB-THRU")
      (libsource (lib "eagle-import") (part "LED-RGB-CCCLEAR"))
    )
    (comp (ref "D502")
      (value "CLEAR")
      (footprint "eagle-import:LED-RGB-THRU")
      (libsource (lib "eagle-import") (part "LED-RGB-CCCLEAR"))
    )
    (comp (ref "D503")
      (value "CLEAR")
      (footprint "eagle-import:LED-RGB-THRU")
      (libsource (lib "eagle-import") (part "LED-RGB-CCCLEAR"))
    )
    (comp (ref "D504")
      (value "CLEAR")
      (footprint "eagle-import:LED-RGB-THRU")
      (libsource (lib "eagle-import") (part "LED-RGB-CCCLEAR"))
    )
    (comp (ref "D505")
      (value "CLEAR")
      (footprint "eagle-import:LED-RGB-THRU")
      (libsource (lib "eagle-import") (part "LED-RGB-CCCLEAR"))
    )
    (comp (ref "D506")
      (value "CLEAR")
      (footprint "eagle-import:LED-RGB-THRU")
      (libsource (lib "eagle-import") (part "LED-RGB-CCCLEAR"))
    )
    (comp (ref "D507")
      (value "CLEAR")
      (footprint "eagle-import:LED-RGB-THRU")
      (libsource (lib "eagle-import") (part "LED-RGB-CCCLEAR"))
    )
    (comp (ref "D508")
      (value "CLEAR")
      (footprint "eagle-import:LED-RGB-THRU")
      (libsource (lib "eagle-import") (part "LED-RGB-CCCLEAR"))
    )
    (comp (ref "D509")
      (value "CLEAR")
      (footprint "eagle-import:LED-RGB-THRU")
      (libsource (lib "eagle-import") (part "LED-RGB-CCCLEAR"))
    )
    (comp (ref "D510")
      (value "CLEAR")
      (footprint "eagle-import:LED-RGB-THRU")
      (libsource (lib "eagle-import") (part "LED-RGB-CCCLEAR"))
    )
    (comp (ref "D511")
      (value "CLEAR")
      (footprint "eagle-import:LED-RGB-THRU")
      (libsource (lib "eagle-import") (part "LED-RGB-CCCLEAR"))
    )
    (comp (ref "D512")
      (value "CLEAR")
      (footprint "eagle-import:LED-RGB-THRU")
      (libsource (lib "eagle-import") (part "LED-RGB-CCCLEAR"))
    )
    (comp (ref "IC1")
      (value "TPIC6B595N")
      (footprint "eagle-import:DIL20")
      (libsource (lib "eagle-import") (part "TPIC6B596N"))
    )
    (comp (ref "IC2")
      (value "TPIC6B595N")
      (footprint "eagle-import:DIL20")
      (libsource (lib "eagle-import") (part "TPIC6B596N"))
    )
    (comp (ref "IC3")
      (value "TPIC6B595N")
      (footprint "eagle-import:DIL20")
      (libsource (lib "eagle-import") (part "TPIC6B596N"))
    )
    (comp (ref "IC4")
      (value "TPIC6B595N")
      (footprint "eagle-import:DIL20")
      (libsource (lib "eagle-import") (part "TPIC6B596N"))
    )
    (comp (ref "IC5")
      (value "TPIC6B595N")
      (footprint "eagle-import:DIL20")
      (libsource (lib "eagle-import") (part "TPIC6B596N"))
    )
    (comp (ref "IC6")
      (value "TPIC6B595N")
      (footprint "eagle-import:DIL20")
      (libsource (lib "eagle-import") (part "TPIC6B596N"))
    )
    (comp (ref "IC7")
      (value "TPIC6B595N")
      (footprint "eagle-import:DIL20")
      (libsource (lib "eagle-import") (part "TPIC6B596N"))
    )
    (comp (ref "IC8")
      (value "TPIC6B595N")
      (footprint "eagle-import:DIL20")
      (libsource (lib "eagle-import") (part "TPIC6B596N"))
    )
    (comp (ref "Q1")
      (value "S8550D")
      (footprint "eagle-import:TO92-EBC")
      (libsource (lib "eagle-import") (part "BC558B"))
    )
    (comp (ref "Q2")
      (value "S8550D")
      (footprint "eagle-import:TO92-EBC")
      (libsource (lib "eagle-import") (part "BC558B"))
    )
    (comp (ref "Q3")
      (value "S8550D")
      (footprint "eagle-import:TO92-EBC")
      (libsource (lib "eagle-import") (part "BC558B"))
    )
    (comp (ref "Q4")
      (value "S8550D")
      (footprint "eagle-import:TO92-EBC")
      (libsource (lib "eagle-import") (part "BC558B"))
    )
    (comp (ref "Q5")
      (value "S8550D")
      (footprint "eagle-import:TO92-EBC")
      (libsource (lib "eagle-import") (part "BC558B"))
    )
    (comp (ref "Q6")
      (value "S8550D")
      (footprint "eagle-import:TO92-EBC")
      (libsource (lib "eagle-import") (part "BC558B"))
    )
    (comp (ref "Q7")
      (value "S8550D")
      (footprint "eagle-import:TO92-EBC")
      (libsource (lib "eagle-import") (part "BC558B"))
    )
    (comp (ref "Q8")
      (value "S8550D")
      (footprint "eagle-import:TO92-EBC")
      (libsource (lib "eagle-import") (part "BC558B"))
    )
    (comp (ref "Q9")
      (value "S8550D")
      (footprint "eagle-import:TO92-EBC")
      (libsource (lib "eagle-import") (part "BC558B"))
    )
    (comp (ref "Q10")
      (value "S8550D")
      (footprint "eagle-import:TO92-EBC")
      (libsource (lib "eagle-import") (part "BC558B"))
    )
    (comp (ref "Q11")
      (value "S8550D")
      (footprint "eagle-import:TO92-EBC")
      (libsource (lib "eagle-import") (part "BC558B"))
    )
    (comp (ref "Q12")
      (value "S8550D")
      (footprint "eagle-import:TO92-EBC")
      (libsource (lib "eagle-import") (part "BC558B"))
    )
    (comp (ref "Q13")
      (value "S8550D")
      (footprint "eagle-import:TO92-EBC")
      (libsource (lib "eagle-import") (part "BC558B"))
    )
    (comp (ref "Q14")
      (value "S8550D")
      (footprint "eagle-import:TO92-EBC")
      (libsource (lib "eagle-import") (part "BC558B"))
    )
    (comp (ref "Q15")
      (value "S8550D")
      (footprint "eagle-import:TO92-EBC")
      (libsource (lib "eagle-import") (part "BC558B"))
    )
    (comp (ref "Q16")
      (value "S8550D")
      (footprint "eagle-import:TO92-EBC")
      (libsource (lib "eagle-import") (part "BC558B"))
    )
    (comp (ref "Q17")
      (value "S8550D")
      (footprint "eagle-import:TO92-EBC")
      (libsource (lib "eagle-import") (part "BC558B"))
    )
    (comp (ref "Q18")
      (value "S8550D")
      (footprint "eagle-import:TO92-EBC")
      (libsource (lib "eagle-import") (part "BC558B"))
    )
    (comp (ref "Q19")
      (value "S8550D")
      (footprint "eagle-import:TO92-EBC")
      (libsource (lib "eagle-import") (part "BC558B"))
    )
    (comp (ref "Q20")
      (value "S8550D")
      (footprint "eagle-import:TO92-EBC")
      (libsource (lib "eagle-import") (part "BC558B"))
    )
    (comp (ref "Q21")
      (value "S8550D")
      (footprint "eagle-import:TO92-EBC")
      (libsource (lib "eagle-import") (part "BC558B"))
    )
    (comp (ref "Q22")
      (value "S8550D")
      (footprint "eagle-import:TO92-EBC")
      (libsource (lib "eagle-import") (part "BC558B"))
    )
    (comp (ref "Q23")
      (value "S8550D")
      (footprint "eagle-import:TO92-EBC")
      (libsource (lib "eagle-import") (part "BC558B"))
    )
    (comp (ref "Q24")
      (value "S8550D")
      (footprint "eagle-import:TO92-EBC")
      (libsource (lib "eagle-import") (part "BC558B"))
    )
    (comp (ref "R1")
      (value "150R")
      (footprint "eagle-import:0207_10")
      (libsource (lib "eagle-import") (part "R-EU_0207/10"))
    )
    (comp (ref "R2")
      (value "150R")
      (footprint "eagle-import:0207_10")
      (libsource (lib "eagle-import") (part "R-EU_0207/10"))
    )
    (comp (ref "R3")
      (value "150R")
      (footprint "eagle-import:0207_10")
      (libsource (lib "eagle-import") (part "R-EU_0207/10"))
    )
    (comp (ref "R4")
      (value "150R")
      (footprint "eagle-import:0207_10")
      (libsource (lib "eagle-import") (part "R-EU_0207/10"))
    )
    (comp (ref "R5")
      (value "150R")
      (footprint "eagle-import:0207_10")
      (libsource (lib "eagle-import") (part "R-EU_0207/10"))
    )
    (comp (ref "R6")
      (value "150R")
      (footprint "eagle-import:0207_10")
      (libsource (lib "eagle-import") (part "R-EU_0207/10"))
    )
    (comp (ref "R7")
      (value "150R")
      (footprint "eagle-import:0207_10")
      (libsource (lib "eagle-import") (part "R-EU_0207/10"))
    )
    (comp (ref "R8")
      (value "150R")
      (footprint "eagle-import:0207_10")
      (libsource (lib "eagle-import") (part "R-EU_0207/10"))
    )
    (comp (ref "R9")
      (value "150R")
      (footprint "eagle-import:0207_10")
      (libsource (lib "eagle-import") (part "R-EU_0207/10"))
    )
    (comp (ref "R10")
      (value "150R")
      (footprint "eagle-import:0207_10")
      (libsource (lib "eagle-import") (part "R-EU_0207/10"))
    )
    (comp (ref "R11")
      (value "150R")
      (footprint "eagle-import:0207_10")
      (libsource (lib "eagle-import") (part "R-EU_0207/10"))
    )
    (comp (ref "R12")
      (value "150R")
      (footprint "eagle-import:0207_10")
      (libsource (lib "eagle-import") (part "R-EU_0207/10"))
    )
    (comp (ref "R13")
      (value "150R")
      (footprint "eagle-import:0207_10")
      (libsource (lib "eagle-import") (part "R-EU_0207/10"))
    )
    (comp (ref "R14")
      (value "150R")
      (footprint "eagle-import:0207_10")
      (libsource (lib "eagle-import") (part "R-EU_0207/10"))
    )
    (comp (ref "R15")
      (value "150R")
      (footprint "eagle-import:0207_10")
      (libsource (lib "eagle-import") (part "R-EU_0207/10"))
    )
    (comp (ref "R16")
      (value "150R")
      (footprint "eagle-import:0207_10")
      (libsource (lib "eagle-import") (part "R-EU_0207/10"))
    )
    (comp (ref "R17")
      (value "150R")
      (footprint "eagle-import:0207_10")
      (libsource (lib "eagle-import") (part "R-EU_0207/10"))
    )
    (comp (ref "R18")
      (value "150R")
      (footprint "eagle-import:0207_10")
      (libsource (lib "eagle-import") (part "R-EU_0207/10"))
    )
    (comp (ref "R19")
      (value "150R")
      (footprint "eagle-import:0207_10")
      (libsource (lib "eagle-import") (part "R-EU_0207/10"))
    )
    (comp (ref "R20")
      (value "150R")
      (footprint "eagle-import:0207_10")
      (libsource (lib "eagle-import") (part "R-EU_0207/10"))
    )
    (comp (ref "R21")
      (value "150R")
      (footprint "eagle-import:0207_10")
      (libsource (lib "eagle-import") (part "R-EU_0207/10"))
    )
    (comp (ref "R22")
      (value "150R")
      (footprint "eagle-import:0207_10")
      (libsource (lib "eagle-import") (part "R-EU_0207/10"))
    )
    (comp (ref "R23")
      (value "150R")
      (footprint "eagle-import:0207_10")
      (libsource (lib "eagle-import") (part "R-EU_0207/10"))
    )
    (comp (ref "R24")
      (value "150R")
      (footprint "eagle-import:0207_10")
      (libsource (lib "eagle-import") (part "R-EU_0207/10"))
    )
    (comp (ref "R25")
      (value "150R")
      (footprint "eagle-import:0207_10")
      (libsource (lib "eagle-import") (part "R-EU_0207/10"))
    )
    (comp (ref "R26")
      (value "150R")
      (footprint "eagle-import:0207_10")
      (libsource (lib "eagle-import") (part "R-EU_0207/10"))
    )
    (comp (ref "R27")
      (value "150R")
      (footprint "eagle-import:0207_10")
      (libsource (lib "eagle-import") (part "R-EU_0207/10"))
    )
    (comp (ref "R28")
      (value "150R")
      (footprint "eagle-import:0207_10")
      (libsource (lib "eagle-import") (part "R-EU_0207/10"))
    )
    (comp (ref "R29")
      (value "150R")
      (footprint "eagle-import:0207_10")
      (libsource (lib "eagle-import") (part "R-EU_0207/10"))
    )
    (comp (ref "R30")
      (value "150R")
      (footprint "eagle-import:0207_10")
      (libsource (lib "eagle-import") (part "R-EU_0207/10"))
    )
    (comp (ref "R31")
      (value "150R")
      (footprint "eagle-import:0207_10")
      (libsource (lib "eagle-import") (part "R-EU_0207/10"))
    )
    (comp (ref "R32")
      (value "150R")
      (footprint "eagle-import:0207_10")
      (libsource (lib "eagle-import") (part "R-EU_0207/10"))
    )
    (comp (ref "R33")
      (value "150R")
      (footprint "eagle-import:0207_10")
      (libsource (lib "eagle-import") (part "R-EU_0207/10"))
    )
    (comp (ref "R34")
      (value "150R")
      (footprint "eagle-import:0207_10")
      (libsource (lib "eagle-import") (part "R-EU_0207/10"))
    )
    (comp (ref "R35")
      (value "150R")
      (footprint "eagle-import:0207_10")
      (libsource (lib "eagle-import") (part "R-EU_0207/10"))
    )
    (comp (ref "R36")
      (value "150R")
      (footprint "eagle-import:0207_10")
      (libsource (lib "eagle-import") (part "R-EU_0207/10"))
    )
    (comp (ref "R37")
      (value "150R")
      (footprint "eagle-import:0207_10")
      (libsource (lib "eagle-import") (part "R-EU_0207/10"))
    )
    (comp (ref "R38")
      (value "150R")
      (footprint "eagle-import:0207_10")
      (libsource (lib "eagle-import") (part "R-EU_0207/10"))
    )
    (comp (ref "R39")
      (value "150R")
      (footprint "eagle-import:0207_10")
      (libsource (lib "eagle-import") (part "R-EU_0207/10"))
    )
    (comp (ref "R40")
      (value "150R")
      (footprint "eagle-import:0207_10")
      (libsource (lib "eagle-import") (part "R-EU_0207/10"))
    )
    (comp (ref "R41")
      (value "150R")
      (footprint "eagle-import:0207_10")
      (libsource (lib "eagle-import") (part "R-EU_0207/10"))
    )
    (comp (ref "R42")
      (value "150R")
      (footprint "eagle-import:0207_10")
      (libsource (lib "eagle-import") (part "R-EU_0207/10"))
    )
    (comp (ref "R43")
      (value "150R")
      (footprint "eagle-import:0207_10")
      (libsource (lib "eagle-import") (part "R-EU_0207/10"))
    )
    (comp (ref "R44")
      (value "150R")
      (footprint "eagle-import:0207_10")
      (libsource (lib "eagle-import") (part "R-EU_0207/10"))
    )
    (comp (ref "R45")
      (value "150R")
      (footprint "eagle-import:0207_10")
      (libsource (lib "eagle-import") (part "R-EU_0207/10"))
    )
    (comp (ref "R46")
      (value "150R")
      (footprint "eagle-import:0207_10")
      (libsource (lib "eagle-import") (part "R-EU_0207/10"))
    )
    (comp (ref "R47")
      (value "150R")
      (footprint "eagle-import:0207_10")
      (libsource (lib "eagle-import") (part "R-EU_0207/10"))
    )
    (comp (ref "R48")
      (value "150R")
      (footprint "eagle-import:0207_10")
      (libsource (lib "eagle-import") (part "R-EU_0207/10"))
    )
    (comp (ref "R49")
      (value "150R")
      (footprint "eagle-import:0207_10")
      (libsource (lib "eagle-import") (part "R-EU_0207/10"))
    )
    (comp (ref "R50")
      (value "150R")
      (footprint "eagle-import:0207_10")
      (libsource (lib "eagle-import") (part "R-EU_0207/10"))
    )
    (comp (ref "R51")
      (value "150R")
      (footprint "eagle-import:0207_10")
      (libsource (lib "eagle-import") (part "R-EU_0207/10"))
    )
    (comp (ref "R52")
      (value "150R")
      (footprint "eagle-import:0207_10")
      (libsource (lib "eagle-import") (part "R-EU_0207/10"))
    )
    (comp (ref "R53")
      (value "150R")
      (footprint "eagle-import:0207_10")
      (libsource (lib "eagle-import") (part "R-EU_0207/10"))
    )
    (comp (ref "R54")
      (value "150R")
      (footprint "eagle-import:0207_10")
      (libsource (lib "eagle-import") (part "R-EU_0207/10"))
    )
    (comp (ref "R55")
      (value "150R")
      (footprint "eagle-import:0207_10")
      (libsource (lib "eagle-import") (part "R-EU_0207/10"))
    )
    (comp (ref "R56")
      (value "150R")
      (footprint "eagle-import:0207_10")
      (libsource (lib "eagle-import") (part "R-EU_0207/10"))
    )
    (comp (ref "R57")
      (value "150R")
      (footprint "eagle-import:0207_10")
      (libsource (lib "eagle-import") (part "R-EU_0207/10"))
    )
    (comp (ref "R58")
      (value "150R")
      (footprint "eagle-import:0207_10")
      (libsource (lib "eagle-import") (part "R-EU_0207/10"))
    )
    (comp (ref "R59")
      (value "150R")
      (footprint "eagle-import:0207_10")
      (libsource (lib "eagle-import") (part "R-EU_0207/10"))
    )
    (comp (ref "R60")
      (value "150R")
      (footprint "eagle-import:0207_10")
      (libsource (lib "eagle-import") (part "R-EU_0207/10"))
    )
    (comp (ref "R61")
      (value "150R")
      (footprint "eagle-import:0207_10")
      (libsource (lib "eagle-import") (part "R-EU_0207/10"))
    )
    (comp (ref "R62")
      (value "150R")
      (footprint "eagle-import:0207_10")
      (libsource (lib "eagle-import") (part "R-EU_0207/10"))
    )
    (comp (ref "R63")
      (value "150R")
      (footprint "eagle-import:0207_10")
      (libsource (lib "eagle-import") (part "R-EU_0207/10"))
    )
    (comp (ref "R64")
      (value "150R")
      (footprint "eagle-import:0207_10")
      (libsource (lib "eagle-import") (part "R-EU_0207/10"))
    )
  )
  (nets
    (net (code "1") (name "GND") (class "Default")
      (node (ref "C1") (pin "2") (pinfunction "2_2") (pintype "passive"))
      (node (ref "C2") (pin "2") (pinfunction "2_2") (pintype "passive"))
      (node (ref "C3") (pin "2") (pinfunction "2_2") (pintype "passive"))
      (node (ref "C4") (pin "2") (pinfunction "2_2") (pintype "passive"))
      (node (ref "C5") (pin "2") (pinfunction "2_2") (pintype "passive"))
      (node (ref "C6") (pin "2") (pinfunction "2_2") (pintype "passive"))
      (node (ref "C7") (pin "2") (pinfunction "2_2") (pintype "passive"))
      (node (ref "C8") (pin "2") (pinfunction "2_2") (pintype "passive"))
      (node (ref "IC1") (pin "9") (pinfunction "G_9") (pintype "input"))
      (node (ref "IC2") (pin "9") (pinfunction "G_9") (pintype "input"))
      (node (ref "IC3") (pin "9") (pinfunction "G_9") (pintype "input"))
      (node (ref "IC4") (pin "9") (pinfunction "G_9") (pintype "input"))
      (node (ref "IC5") (pin "9") (pinfunction "G_9") (pintype "input"))
      (node (ref "IC6") (pin "9") (pinfunction "G_9") (pintype "input"))
      (node (ref "IC7") (pin "9") (pinfunction "G_9") (pintype "input"))
      (node (ref "IC8") (pin "9") (pinfunction "G_9") (pintype "input"))
    )
    (net (code "2") (name "Net-(D1-BLU)") (class "Default")
      (node (ref "D1") (pin "4") (pinfunction "BLU_4") (pintype "bidirectional"))
      (node (ref "D10") (pin "4") (pinfunction "BLU_4") (pintype "bidirectional"))
      (node (ref "D11") (pin "4") (pinfunction "BLU_4") (pintype "bidirectional"))
      (node (ref "D12") (pin "4") (pinfunction "BLU_4") (pintype "bidirectional"))
      (node (ref "D13") (pin "4") (pinfunction "BLU_4") (pintype "bidirectional"))
      (node (ref "D14") (pin "4") (pinfunction "BLU_4") (pintype "bidirectional"))
      (node (ref "D15") (pin "4") (pinfunction "BLU_4") (pintype "bidirectional"))
      (node (ref "D16") (pin "4") (pinfunction "BLU_4") (pintype "bidirectional"))
      (node (ref "D17") (pin "4") (pinfunction "BLU_4") (pintype "bidirectional"))
      (node (ref "D18") (pin "4") (pinfunction "BLU_4") (pintype "bidirectional"))
      (node (ref "D19") (pin "4") (pinfunction "BLU_4") (pintype "bidirectional"))
      (node (ref "D2") (pin "4") (pinfunction "BLU_4") (pintype "bidirectional"))
      (node (ref "D20") (pin "4") (pinfunction "BLU_4") (pintype "bidirectional"))
      (node (ref "D21") (pin "4") (pinfunction "BLU_4") (pintype "bidirectional"))
      (node (ref "D22") (pin "4") (pinfunction "BLU_4") (pintype "bidirectional"))
      (node (ref "D23") (pin "4") (pinfunction "BLU_4") (pintype "bidirectional"))
      (node (ref "D24") (pin "4") (pinfunction "BLU_4") (pintype "bidirectional"))
      (node (ref "D25") (pin "4") (pinfunction "BLU_4") (pintype "bidirectional"))
      (node (ref "D26") (pin "4") (pinfunction "BLU_4") (pintype "bidirectional"))
      (node (ref "D27") (pin "4") (pinfunction "BLU_4") (pintype "bidirectional"))
      (node (ref "D28") (pin "4") (pinfunction "BLU_4") (pintype "bidirectional"))
      (node (ref "D29") (pin "4") (pinfunction "BLU_4") (pintype "bidirectional"))
      (node (ref "D3") (pin "4") (pinfunction "BLU_4") (pintype "bidirectional"))
      (node (ref "D30") (pin "4") (pinfunction "BLU_4") (pintype "bidirectional"))
      (node (ref "D31") (pin "4") (pinfunction "BLU_4") (pintype "bidirectional"))
      (node (ref "D32") (pin "4") (pinfunction "BLU_4") (pintype "bidirectional"))
      (node (ref "D33") (pin "4") (pinfunction "BLU_4") (pintype "bidirectional"))
      (node (ref "D34") (pin "4") (pinfunction "BLU_4") (pintype "bidirectional"))
      (node (ref "D35") (pin "4") (pinfunction "BLU_4") (pintype "bidirectional"))
      (node (ref "D36") (pin "4") (pinfunction "BLU_4") (pintype "bidirectional"))
      (node (ref "D37") (pin "4") (pinfunction "BLU_4") (pintype "bidirectional"))
      (node (ref "D38") (pin "4") (pinfunction "BLU_4") (pintype "bidirectional"))
      (node (ref "D39") (pin "4") (pinfunction "BLU_4") (pintype "bidirectional"))
      (node (ref "D4") (pin "4") (pinfunction "BLU_4") (pintype "bidirectional"))
      (node (ref "D40") (pin "4") (pinfunction "BLU_4") (pintype "bidirectional"))
      (node (ref "D41") (pin "4") (pinfunction "BLU_4") (pintype "bidirectional"))
      (node (ref "D42") (pin "4") (pinfunction "BLU_4") (pintype "bidirectional"))
      (node (ref "D43") (pin "4") (pinfunction "BLU_4") (pintype "bidirectional"))
      (node (ref "D44") (pin "4") (pinfunction "BLU_4") (pintype "bidirectional"))
      (node (ref "D45") (pin "4") (pinfunction "BLU_4") (pintype "bidirectional"))
      (node (ref "D46") (pin "4") (pinfunction "BLU_4") (pintype "bidirectional"))
      (node (ref "D47") (pin "4") (pinfunction "BLU_4") (pintype "bidirectional"))
      (node (ref "D48") (pin "4") (pinfunction "BLU_4") (pintype "bidirectional"))
      (node (ref "D49") (pin "4") (pinfunction "BLU_4") (pintype "bidirectional"))
      (node (ref "D5") (pin "4") (pinfunction "BLU_4") (pintype "bidirectional"))
      (node (ref "D50") (pin "4") (pinfunction "BLU_4") (pintype "bidirectional"))
      (node (ref "D51") (pin "4") (pinfunction "BLU_4") (pintype "bidirectional"))
      (node (ref "D52") (pin "4") (pinfunction "BLU_4") (pintype "bidirectional"))
      (node (ref "D53") (pin "4") (pinfunction "BLU_4") (pintype "bidirectional"))
      (node (ref "D54") (pin "4") (pinfunction "BLU_4") (pintype "bidirectional"))
      (node (ref "D55") (pin "4") (pinfunction "BLU_4") (pintype "bidirectional"))
      (node (ref "D56") (pin "4") (pinfunction "BLU_4") (pintype "bidirectional"))
      (node (ref "D57") (pin "4") (pinfunction "BLU_4") (pintype "bidirectional"))
      (node (ref "D58") (pin "4") (pinfunction "BLU_4") (pintype "bidirectional"))
      (node (ref "D59") (pin "4") (pinfunction "BLU_4") (pintype "bidirectional"))
      (node (ref "D6") (pin "4") (pinfunction "BLU_4") (pintype "bidirectional"))
      (node (ref "D60") (pin "4") (pinfunction "BLU_4") (pintype "bidirectional"))
      (node (ref "D61") (pin "4") (pinfunction "BLU_4") (pintype "bidirectional"))
      (node (ref "D62") (pin "4") (pinfunction "BLU_4") (pintype "bidirectional"))
      (node (ref "D63") (pin "4") (pinfunction "BLU_4") (pintype "bidirectional"))
      (node (ref "D64") (pin "4") (pinfunction "BLU_4") (pintype "bidirectional"))
      (node (ref "D7") (pin "4") (pinfunction "BLU_4") (pintype "bidirectional"))
      (node (ref "D8") (pin "4") (pinfunction "BLU_4") (pintype "bidirectional"))
      (node (ref "D9") (pin "4") (pinfunction "BLU_4") (pintype "bidirectional"))
      (node (ref "Q2") (pin "C") (pinfunction "C_C") (pintype "passive"))
    )
    (net (code "3") (name "Net-(D1-C)") (class "Default")
      (node (ref "D1") (pin "2") (pinfunction "C_2") (pintype "bidirectional"))
      (node (ref "D129") (pin "2") (pinfunction "C_2") (pintype "bidirectional"))
      (node (ref "D193") (pin "2") (pinfunction "C_2") (pintype "bidirectional"))
      (node (ref "D257") (pin "2") (pinfunction "C_2") (pintype "bidirectional"))
      (node (ref "D321") (pin "2") (pinfunction "C_2") (pintype "bidirectional"))
      (node (ref "D385") (pin "2") (pinfunction "C_2") (pintype "bidirectional"))
      (node (ref "D449") (pin "2") (pinfunction "C_2") (pintype "bidirectional"))
      (node (ref "D65") (pin "2") (pinfunction "C_2") (pintype "bidirectional"))
      (node (ref "R8") (pin "2") (pinfunction "2_2") (pintype "passive"))
    )
    (net (code "4") (name "Net-(D1-GRN)") (class "Default")
      (node (ref "D1") (pin "3") (pinfunction "GRN_3") (pintype "bidirectional"))
      (node (ref "D10") (pin "3") (pinfunction "GRN_3") (pintype "bidirectional"))
      (node (ref "D11") (pin "3") (pinfunction "GRN_3") (pintype "bidirectional"))
      (node (ref "D12") (pin "3") (pinfunction "GRN_3") (pintype "bidirectional"))
      (node (ref "D13") (pin "3") (pinfunction "GRN_3") (pintype "bidirectional"))
      (node (ref "D14") (pin "3") (pinfunction "GRN_3") (pintype "bidirectional"))
      (node (ref "D15") (pin "3") (pinfunction "GRN_3") (pintype "bidirectional"))
      (node (ref "D16") (pin "3") (pinfunction "GRN_3") (pintype "bidirectional"))
      (node (ref "D17") (pin "3") (pinfunction "GRN_3") (pintype "bidirectional"))
      (node (ref "D18") (pin "3") (pinfunction "GRN_3") (pintype "bidirectional"))
      (node (ref "D19") (pin "3") (pinfunction "GRN_3") (pintype "bidirectional"))
      (node (ref "D2") (pin "3") (pinfunction "GRN_3") (pintype "bidirectional"))
      (node (ref "D20") (pin "3") (pinfunction "GRN_3") (pintype "bidirectional"))
      (node (ref "D21") (pin "3") (pinfunction "GRN_3") (pintype "bidirectional"))
      (node (ref "D22") (pin "3") (pinfunction "GRN_3") (pintype "bidirectional"))
      (node (ref "D23") (pin "3") (pinfunction "GRN_3") (pintype "bidirectional"))
      (node (ref "D24") (pin "3") (pinfunction "GRN_3") (pintype "bidirectional"))
      (node (ref "D25") (pin "3") (pinfunction "GRN_3") (pintype "bidirectional"))
      (node (ref "D26") (pin "3") (pinfunction "GRN_3") (pintype "bidirectional"))
      (node (ref "D27") (pin "3") (pinfunction "GRN_3") (pintype "bidirectional"))
      (node (ref "D28") (pin "3") (pinfunction "GRN_3") (pintype "bidirectional"))
      (node (ref "D29") (pin "3") (pinfunction "GRN_3") (pintype "bidirectional"))
      (node (ref "D3") (pin "3") (pinfunction "GRN_3") (pintype "bidirectional"))
      (node (ref "D30") (pin "3") (pinfunction "GRN_3") (pintype "bidirectional"))
      (node (ref "D31") (pin "3") (pinfunction "GRN_3") (pintype "bidirectional"))
      (node (ref "D32") (pin "3") (pinfunction "GRN_3") (pintype "bidirectional"))
      (node (ref "D33") (pin "3") (pinfunction "GRN_3") (pintype "bidirectional"))
      (node (ref "D34") (pin "3") (pinfunction "GRN_3") (pintype "bidirectional"))
      (node (ref "D35") (pin "3") (pinfunction "GRN_3") (pintype "bidirectional"))
      (node (ref "D36") (pin "3") (pinfunction "GRN_3") (pintype "bidirectional"))
      (node (ref "D37") (pin "3") (pinfunction "GRN_3") (pintype "bidirectional"))
      (node (ref "D38") (pin "3") (pinfunction "GRN_3") (pintype "bidirectional"))
      (node (ref "D39") (pin "3") (pinfunction "GRN_3") (pintype "bidirectional"))
      (node (ref "D4") (pin "3") (pinfunction "GRN_3") (pintype "bidirectional"))
      (node (ref "D40") (pin "3") (pinfunction "GRN_3") (pintype "bidirectional"))
      (node (ref "D41") (pin "3") (pinfunction "GRN_3") (pintype "bidirectional"))
      (node (ref "D42") (pin "3") (pinfunction "GRN_3") (pintype "bidirectional"))
      (node (ref "D43") (pin "3") (pinfunction "GRN_3") (pintype "bidirectional"))
      (node (ref "D44") (pin "3") (pinfunction "GRN_3") (pintype "bidirectional"))
      (node (ref "D45") (pin "3") (pinfunction "GRN_3") (pintype "bidirectional"))
      (node (ref "D46") (pin "3") (pinfunction "GRN_3") (pintype "bidirectional"))
      (node (ref "D47") (pin "3") (pinfunction "GRN_3") (pintype "bidirectional"))
      (node (ref "D48") (pin "3") (pinfunction "GRN_3") (pintype "bidirectional"))
      (node (ref "D49") (pin "3") (pinfunction "GRN_3") (pintype "bidirectional"))
      (node (ref "D5") (pin "3") (pinfunction "GRN_3") (pintype "bidirectional"))
      (node (ref "D50") (pin "3") (pinfunction "GRN_3") (pintype "bidirectional"))
      (node (ref "D51") (pin "3") (pinfunction "GRN_3") (pintype "bidirectional"))
      (node (ref "D52") (pin "3") (pinfunction "GRN_3") (pintype "bidirectional"))
      (node (ref "D53") (pin "3") (pinfunction "GRN_3") (pintype "bidirectional"))
      (node (ref "D54") (pin "3") (pinfunction "GRN_3") (pintype "bidirectional"))
      (node (ref "D55") (pin "3") (pinfunction "GRN_3") (pintype "bidirectional"))
      (node (ref "D56") (pin "3") (pinfunction "GRN_3") (pintype "bidirectional"))
      (node (ref "D57") (pin "3") (pinfunction "GRN_3") (pintype "bidirectional"))
      (node (ref "D58") (pin "3") (pinfunction "GRN_3") (pintype "bidirectional"))
      (node (ref "D59") (pin "3") (pinfunction "GRN_3") (pintype "bidirectional"))
      (node (ref "D6") (pin "3") (pinfunction "GRN_3") (pintype "bidirectional"))
      (node (ref "D60") (pin "3") (pinfunction "GRN_3") (pintype "bidirectional"))
      (node (ref "D61") (pin "3") (pinfunction "GRN_3") (pintype "bidirectional"))
      (node (ref "D62") (pin "3") (pinfunction "GRN_3") (pintype "bidirectional"))
      (node (ref "D63") (pin "3") (pinfunction "GRN_3") (pintype "bidirectional"))
      (node (ref "D64") (pin "3") (pinfunction "GRN_3") (pintype "bidirectional"))
      (node (ref "D7") (pin "3") (pinfunction "GRN_3") (pintype "bidirectional"))
      (node (ref "D8") (pin "3") (pinfunction "GRN_3") (pintype "bidirectional"))
      (node (ref "D9") (pin "3") (pinfunction "GRN_3") (pintype "bidirectional"))
      (node (ref "Q1") (pin "C") (pinfunction "C_C") (pintype "passive"))
    )
    (net (code "5") (name "Net-(D1-RED)") (class "Default")
      (node (ref "D1") (pin "1") (pinfunction "RED_1") (pintype "bidirectional"))
      (node (ref "D10") (pin "1") (pinfunction "RED_1") (pintype "bidirectional"))
      (node (ref "D11") (pin "1") (pinfunction "RED_1") (pintype "bidirectional"))
      (node (ref "D12") (pin "1") (pinfunction "RED_1") (pintype "bidirectional"))
      (node (ref "D13") (pin "1") (pinfunction "RED_1") (pintype "bidirectional"))
      (node (ref "D14") (pin "1") (pinfunction "RED_1") (pintype "bidirectional"))
      (node (ref "D15") (pin "1") (pinfunction "RED_1") (pintype "bidirectional"))
      (node (ref "D16") (pin "1") (pinfunction "RED_1") (pintype "bidirectional"))
      (node (ref "D17") (pin "1") (pinfunction "RED_1") (pintype "bidirectional"))
      (node (ref "D18") (pin "1") (pinfunction "RED_1") (pintype "bidirectional"))
      (node (ref "D19") (pin "1") (pinfunction "RED_1") (pintype "bidirectional"))
      (node (ref "D2") (pin "1") (pinfunction "RED_1") (pintype "bidirectional"))
      (node (ref "D20") (pin "1") (pinfunction "RED_1") (pintype "bidirectional"))
      (node (ref "D21") (pin "1") (pinfunction "RED_1") (pintype "bidirectional"))
      (node (ref "D22") (pin "1") (pinfunction "RED_1") (pintype "bidirectional"))
      (node (ref "D23") (pin "1") (pinfunction "RED_1") (pintype "bidirectional"))
      (node (ref "D24") (pin "1") (pinfunction "RED_1") (pintype "bidirectional"))
      (node (ref "D25") (pin "1") (pinfunction "RED_1") (pintype "bidirectional"))
      (node (ref "D26") (pin "1") (pinfunction "RED_1") (pintype "bidirectional"))
      (node (ref "D27") (pin "1") (pinfunction "RED_1") (pintype "bidirectional"))
      (node (ref "D28") (pin "1") (pinfunction "RED_1") (pintype "bidirectional"))
      (node (ref "D29") (pin "1") (pinfunction "RED_1") (pintype "bidirectional"))
      (node (ref "D3") (pin "1") (pinfunction "RED_1") (pintype "bidirectional"))
      (node (ref "D30") (pin "1") (pinfunction "RED_1") (pintype "bidirectional"))
      (node (ref "D31") (pin "1") (pinfunction "RED_1") (pintype "bidirectional"))
      (node (ref "D32") (pin "1") (pinfunction "RED_1") (pintype "bidirectional"))
      (node (ref "D33") (pin "1") (pinfunction "RED_1") (pintype "bidirectional"))
      (node (ref "D34") (pin "1") (pinfunction "RED_1") (pintype "bidirectional"))
      (node (ref "D35") (pin "1") (pinfunction "RED_1") (pintype "bidirectional"))
      (node (ref "D36") (pin "1") (pinfunction "RED_1") (pintype "bidirectional"))
      (node (ref "D37") (pin "1") (pinfunction "RED_1") (pintype "bidirectional"))
      (node (ref "D38") (pin "1") (pinfunction "RED_1") (pintype "bidirectional"))
      (node (ref "D39") (pin "1") (pinfunction "RED_1") (pintype "bidirectional"))
      (node (ref "D4") (pin "1") (pinfunction "RED_1") (pintype "bidirectional"))
      (node (ref "D40") (pin "1") (pinfunction "RED_1") (pintype "bidirectional"))
      (node (ref "D41") (pin "1") (pinfunction "RED_1") (pintype "bidirectional"))
      (node (ref "D42") (pin "1") (pinfunction "RED_1") (pintype "bidirectional"))
      (node (ref "D43") (pin "1") (pinfunction "RED_1") (pintype "bidirectional"))
      (node (ref "D44") (pin "1") (pinfunction "RED_1") (pintype "bidirectional"))
      (node (ref "D45") (pin "1") (pinfunction "RED_1") (pintype "bidirectional"))
      (node (ref "D46") (pin "1") (pinfunction "RED_1") (pintype "bidirectional"))
      (node (ref "D47") (pin "1") (pinfunction "RED_1") (pintype "bidirectional"))
      (node (ref "D48") (pin "1") (pinfunction "RED_1") (pintype "bidirectional"))
      (node (ref "D49") (pin "1") (pinfunction "RED_1") (pintype "bidirectional"))
      (node (ref "D5") (pin "1") (pinfunction "RED_1") (pintype "bidirectional"))
      (node (ref "D50") (pin "1") (pinfunction "RED_1") (pintype "bidirectional"))
      (node (ref "D51") (pin "1") (pinfunction "RED_1") (pintype "bidirectional"))
      (node (ref "D52") (pin "1") (pinfunction "RED_1") (pintype "bidirectional"))
      (node (ref "D53") (pin "1") (pinfunction "RED_1") (pintype "bidirectional"))
      (node (ref "D54") (pin "1") (pinfunction "RED_1") (pintype "bidirectional"))
      (node (ref "D55") (pin "1") (pinfunction "RED_1") (pintype "bidirectional"))
      (node (ref "D56") (pin "1") (pinfunction "RED_1") (pintype "bidirectional"))
      (node (ref "D57") (pin "1") (pinfunction "RED_1") (pintype "bidirectional"))
      (node (ref "D58") (pin "1") (pinfunction "RED_1") (pintype "bidirectional"))
      (node (ref "D59") (pin "1") (pinfunction "RED_1") (pintype "bidirectional"))
      (node (ref "D6") (pin "1") (pinfunction "RED_1") (pintype "bidirectional"))
      (node (ref "D60") (pin "1") (pinfunction "RED_1") (pintype "bidirectional"))
      (node (ref "D61") (pin "1") (pinfunction "RED_1") (pintype "bidirectional"))
      (node (ref "D62") (pin "1") (pinfunction "RED_1") (pintype "bidirectional"))
      (node (ref "D63") (pin "1") (pinfunction "RED_1") (pintype "bidirectional"))
      (node (ref "D64") (pin "1") (pinfunction "RED_1") (pintype "bidirectional"))
      (node (ref "D7") (pin "1") (pinfunction "RED_1") (pintype "bidirectional"))
      (node (ref "D8") (pin "1") (pinfunction "RED_1") (pintype "bidirectional"))
      (node (ref "D9") (pin "1") (pinfunction "RED_1") (pintype "bidirectional"))
      (node (ref "Q3") (pin "C") (pinfunction "C_C") (pintype "passive"))
    )
    (net (code "6") (name "Net-(D10-C)") (class "Default")
      (node (ref "D10") (pin "2") (pinfunction "C_2") (pintype "bidirectional"))
      (node (ref "D138") (pin "2") (pinfunction "C_2") (pintype "bidirectional"))
      (node (ref "D202") (pin "2") (pinfunction "C_2") (pintype "bidirectional"))
      (node (ref "D266") (pin "2") (pinfunction "C_2") (pintype "bidirectional"))
      (node (ref "D330") (pin "2") (pinfunction "C_2") (pintype "bidirectional"))
      (node (ref "D394") (pin "2") (pinfunction "C_2") (pintype "bidirectional"))
      (node (ref "D458") (pin "2") (pinfunction "C_2") (pintype "bidirectional"))
      (node (ref "D74") (pin "2") (pinfunction "C_2") (pintype "bidirectional"))
      (node (ref "R15") (pin "2") (pinfunction "2_2") (pintype "passive"))
    )
    (net (code "7") (name "Net-(D11-C)") (class "Default")
      (node (ref "D11") (pin "2") (pinfunction "C_2") (pintype "bidirectional"))
      (node (ref "D139") (pin "2") (pinfunction "C_2") (pintype "bidirectional"))
      (node (ref "D203") (pin "2") (pinfunction "C_2") (pintype "bidirectional"))
      (node (ref "D267") (pin "2") (pinfunction "C_2") (pintype "bidirectional"))
      (node (ref "D331") (pin "2") (pinfunction "C_2") (pintype "bidirectional"))
      (node (ref "D395") (pin "2") (pinfunction "C_2") (pintype "bidirectional"))
      (node (ref "D459") (pin "2") (pinfunction "C_2") (pintype "bidirectional"))
      (node (ref "D75") (pin "2") (pinfunction "C_2") (pintype "bidirectional"))
      (node (ref "R14") (pin "2") (pinfunction "2_2") (pintype "passive"))
    )
    (net (code "8") (name "Net-(D12-C)") (class "Default")
      (node (ref "D12") (pin "2") (pinfunction "C_2") (pintype "bidirectional"))
      (node (ref "D140") (pin "2") (pinfunction "C_2") (pintype "bidirectional"))
      (node (ref "D204") (pin "2") (pinfunction "C_2") (pintype "bidirectional"))
      (node (ref "D268") (pin "2") (pinfunction "C_2") (pintype "bidirectional"))
      (node (ref "D332") (pin "2") (pinfunction "C_2") (pintype "bidirectional"))
      (node (ref "D396") (pin "2") (pinfunction "C_2") (pintype "bidirectional"))
      (node (ref "D460") (pin "2") (pinfunction "C_2") (pintype "bidirectional"))
      (node (ref "D76") (pin "2") (pinfunction "C_2") (pintype "bidirectional"))
      (node (ref "R13") (pin "2") (pinfunction "2_2") (pintype "passive"))
    )
    (net (code "9") (name "Net-(D13-C)") (class "Default")
      (node (ref "D13") (pin "2") (pinfunction "C_2") (pintype "bidirectional"))
      (node (ref "D141") (pin "2") (pinfunction "C_2") (pintype "bidirectional"))
      (node (ref "D205") (pin "2") (pinfunction "C_2") (pintype "bidirectional"))
      (node (ref "D269") (pin "2") (pinfunction "C_2") (pintype "bidirectional"))
      (node (ref "D333") (pin "2") (pinfunction "C_2") (pintype "bidirectional"))
      (node (ref "D397") (pin "2") (pinfunction "C_2") (pintype "bidirectional"))
      (node (ref "D461") (pin "2") (pinfunction "C_2") (pintype "bidirectional"))
      (node (ref "D77") (pin "2") (pinfunction "C_2") (pintype "bidirectional"))
      (node (ref "R12") (pin "2") (pinfunction "2_2") (pintype "passive"))
    )
    (net (code "10") (name "Net-(D14-C)") (class "Default")
      (node (ref "D14") (pin "2") (pinfunction "C_2") (pintype "bidirectional"))
      (node (ref "D142") (pin "2") (pinfunction "C_2") (pintype "bidirectional"))
      (node (ref "D206") (pin "2") (pinfunction "C_2") (pintype "bidirectional"))
      (node (ref "D270") (pin "2") (pinfunction "C_2") (pintype "bidirectional"))
      (node (ref "D334") (pin "2") (pinfunction "C_2") (pintype "bidirectional"))
      (node (ref "D398") (pin "2") (pinfunction "C_2") (pintype "bidirectional"))
      (node (ref "D462") (pin "2") (pinfunction "C_2") (pintype "bidirectional"))
      (node (ref "D78") (pin "2") (pinfunction "C_2") (pintype "bidirectional"))
      (node (ref "R11") (pin "2") (pinfunction "2_2") (pintype "passive"))
    )
    (net (code "11") (name "Net-(D100-BLU)") (class "Default")
      (node (ref "D100") (pin "4") (pinfunction "BLU_4") (pintype "bidirectional"))
      (node (ref "D101") (pin "4") (pinfunction "BLU_4") (pintype "bidirectional"))
      (node (ref "D102") (pin "4") (pinfunction "BLU_4") (pintype "bidirectional"))
      (node (ref "D103") (pin "4") (pinfunction "BLU_4") (pintype "bidirectional"))
      (node (ref "D104") (pin "4") (pinfunction "BLU_4") (pintype "bidirectional"))
      (node (ref "D105") (pin "4") (pinfunction "BLU_4") (pintype "bidirectional"))
      (node (ref "D106") (pin "4") (pinfunction "BLU_4") (pintype "bidirectional"))
      (node (ref "D107") (pin "4") (pinfunction "BLU_4") (pintype "bidirectional"))
      (node (ref "D108") (pin "4") (pinfunction "BLU_4") (pintype "bidirectional"))
      (node (ref "D109") (pin "4") (pinfunction "BLU_4") (pintype "bidirectional"))
      (node (ref "D110") (pin "4") (pinfunction "BLU_4") (pintype "bidirectional"))
      (node (ref "D111") (pin "4") (pinfunction "BLU_4") (pintype "bidirectional"))
      (node (ref "D112") (pin "4") (pinfunction "BLU_4") (pintype "bidirectional"))
      (node (ref "D113") (pin "4") (pinfunction "BLU_4") (pintype "bidirectional"))
      (node (ref "D114") (pin "4") (pinfunction "BLU_4") (pintype "bidirectional"))
      (node (ref "D115") (pin "4") (pinfunction "BLU_4") (pintype "bidirectional"))
      (node (ref "D116") (pin "4") (pinfunction "BLU_4") (pintype "bidirectional"))
      (node (ref "D117") (pin "4") (pinfunction "BLU_4") (pintype "bidirectional"))
      (node (ref "D118") (pin "4") (pinfunction "BLU_4") (pintype "bidirectional"))
      (node (ref "D119") (pin "4") (pinfunction "BLU_4") (pintype "bidirectional"))
      (node (ref "D120") (pin "4") (pinfunction "BLU_4") (pintype "bidirectional"))
      (node (ref "D121") (pin "4") (pinfunction "BLU_4") (pintype "bidirectional"))
      (node (ref "D122") (pin "4") (pinfunction "BLU_4") (pintype "bidirectional"))
      (node (ref "D123") (pin "4") (pinfunction "BLU_4") (pintype "bidirectional"))
      (node (ref "D124") (pin "4") (pinfunction "BLU_4") (pintype "bidirectional"))
      (node (ref "D125") (pin "4") (pinfunction "BLU_4") (pintype "bidirectional"))
      (node (ref "D126") (pin "4") (pinfunction "BLU_4") (pintype "bidirectional"))
      (node (ref "D127") (pin "4") (pinfunction "BLU_4") (pintype "bidirectional"))
      (node (ref "D128") (pin "4") (pinfunction "BLU_4") (pintype "bidirectional"))
      (node (ref "D65") (pin "4") (pinfunction "BLU_4") (pintype "bidirectional"))
      (node (ref "D66") (pin "4") (pinfunction "BLU_4") (pintype "bidirectional"))
      (node (ref "D67") (pin "4") (pinfunction "BLU_4") (pintype "bidirectional"))
      (node (ref "D68") (pin "4") (pinfunction "BLU_4") (pintype "bidirectional"))
      (node (ref "D69") (pin "4") (pinfunction "BLU_4") (pintype "bidirectional"))
      (node (ref "D70") (pin "4") (pinfunction "BLU_4") (pintype "bidirectional"))
      (node (ref "D71") (pin "4") (pinfunction "BLU_4") (pintype "bidirectional"))
      (node (ref "D72") (pin "4") (pinfunction "BLU_4") (pintype "bidirectional"))
      (node (ref "D73") (pin "4") (pinfunction "BLU_4") (pintype "bidirectional"))
      (node (ref "D74") (pin "4") (pinfunction "BLU_4") (pintype "bidirectional"))
      (node (ref "D75") (pin "4") (pinfunction "BLU_4") (pintype "bidirectional"))
      (node (ref "D76") (pin "4") (pinfunction "BLU_4") (pintype "bidirectional"))
      (node (ref "D77") (pin "4") (pinfunction "BLU_4") (pintype "bidirectional"))
      (node (ref "D78") (pin "4") (pinfunction "BLU_4") (pintype "bidirectional"))
      (node (ref "D79") (pin "4") (pinfunction "BLU_4") (pintype "bidirectional"))
      (node (ref "D80") (pin "4") (pinfunction "BLU_4") (pintype "bidirectional"))
      (node (ref "D81") (pin "4") (pinfunction "BLU_4") (pintype "bidirectional"))
      (node (ref "D82") (pin "4") (pinfunction "BLU_4") (pintype "bidirectional"))
      (node (ref "D83") (pin "4") (pinfunction "BLU_4") (pintype "bidirectional"))
      (node (ref "D84") (pin "4") (pinfunction "BLU_4") (pintype "bidirectional"))
      (node (ref "D85") (pin "4") (pinfunction "BLU_4") (pintype "bidirectional"))
      (node (ref "D86") (pin "4") (pinfunction "BLU_4") (pintype "bidirectional"))
      (node (ref "D87") (pin "4") (pinfunction "BLU_4") (pintype "bidirectional"))
      (node (ref "D88") (pin "4") (pinfunction "BLU_4") (pintype "bidirectional"))
      (node (ref "D89") (pin "4") (pinfunction "BLU_4") (pintype "bidirectional"))
      (node (ref "D90") (pin "4") (pinfunction "BLU_4") (pintype "bidirectional"))
      (node (ref "D91") (pin "4") (pinfunction "BLU_4") (pintype "bidirectional"))
      (node (ref "D92") (pin "4") (pinfunction "BLU_4") (pintype "bidirectional"))
      (node (ref "D93") (pin "4") (pinfunction "BLU_4") (pintype "bidirectional"))
      (node (ref "D94") (pin "4") (pinfunction "BLU_4") (pintype "bidirectional"))
      (node (ref "D95") (pin "4") (pinfunction "BLU_4") (pintype "bidirectional"))
      (node (ref "D96") (pin "4") (pinfunction "BLU_4") (pintype "bidirectional"))
      (node (ref "D97") (pin "4") (pinfunction "BLU_4") (pintype "bidirectional"))
      (node (ref "D98") (pin "4") (pinfunction "BLU_4") (pintype "bidirectional"))
      (node (ref "D99") (pin "4") (pinfunction "BLU_4") (pintype "bidirectional"))
      (node (ref "Q5") (pin "C") (pinfunction "C_C") (pintype "passive"))
    )
    (net (code "12") (name "Net-(D100-C)") (class "Default")
      (node (ref "D100") (pin "2") (pinfunction "C_2") (pintype "bidirectional"))
      (node (ref "D164") (pin "2") (pinfunction "C_2") (pintype "bidirectional"))
      (node (ref "D228") (pin "2") (pinfunction "C_2") (pintype "bidirectional"))
      (node (ref "D292") (pin "2") (pinfunction "C_2") (pintype "bidirectional"))
      (node (ref "D356") (pin "2") (pinfunction "C_2") (pintype "bidirectional"))
      (node (ref "D36") (pin "2") (pinfunction "C_2") (pintype "bidirectional"))
      (node (ref "D420") (pin "2") (pinfunction "C_2") (pintype "bidirectional"))
      (node (ref "D484") (pin "2") (pinfunction "C_2") (pintype "bidirectional"))
      (node (ref "R37") (pin "2") (pinfunction "2_2") (pintype "passive"))
    )
    (net (code "13") (name "Net-(D100-GRN)") (class "Default")
      (node (ref "D100") (pin "3") (pinfunction "GRN_3") (pintype "bidirectional"))
      (node (ref "D101") (pin "3") (pinfunction "GRN_3") (pintype "bidirectional"))
      (node (ref "D102") (pin "3") (pinfunction "GRN_3") (pintype "bidirectional"))
      (node (ref "D103") (pin "3") (pinfunction "GRN_3") (pintype "bidirectional"))
      (node (ref "D104") (pin "3") (pinfunction "GRN_3") (pintype "bidirectional"))
      (node (ref "D105") (pin "3") (pinfunction "GRN_3") (pintype "bidirectional"))
      (node (ref "D106") (pin "3") (pinfunction "GRN_3") (pintype "bidirectional"))
      (node (ref "D107") (pin "3") (pinfunction "GRN_3") (pintype "bidirectional"))
      (node (ref "D108") (pin "3") (pinfunction "GRN_3") (pintype "bidirectional"))
      (node (ref "D109") (pin "3") (pinfunction "GRN_3") (pintype "bidirectional"))
      (node (ref "D110") (pin "3") (pinfunction "GRN_3") (pintype "bidirectional"))
      (node (ref "D111") (pin "3") (pinfunction "GRN_3") (pintype "bidirectional"))
      (node (ref "D112") (pin "3") (pinfunction "GRN_3") (pintype "bidirectional"))
      (node (ref "D113") (pin "3") (pinfunction "GRN_3") (pintype "bidirectional"))
      (node (ref "D114") (pin "3") (pinfunction "GRN_3") (pintype "bidirectional"))
      (node (ref "D115") (pin "3") (pinfunction "GRN_3") (pintype "bidirectional"))
      (node (ref "D116") (pin "3") (pinfunction "GRN_3") (pintype "bidirectional"))
      (node (ref "D117") (pin "3") (pinfunction "GRN_3") (pintype "bidirectional"))
      (node (ref "D118") (pin "3") (pinfunction "GRN_3") (pintype "bidirectional"))
      (node (ref "D119") (pin "3") (pinfunction "GRN_3") (pintype "bidirectional"))
      (node (ref "D120") (pin "3") (pinfunction "GRN_3") (pintype "bidirectional"))
      (node (ref "D121") (pin "3") (pinfunction "GRN_3") (pintype "bidirectional"))
      (node (ref "D122") (pin "3") (pinfunction "GRN_3") (pintype "bidirectional"))
      (node (ref "D123") (pin "3") (pinfunction "GRN_3") (pintype "bidirectional"))
      (node (ref "D124") (pin "3") (pinfunction "GRN_3") (pintype "bidirectional"))
      (node (ref "D125") (pin "3") (pinfunction "GRN_3") (pintype "bidirectional"))
      (node (ref "D126") (pin "3") (pinfunction "GRN_3") (pintype "bidirectional"))
      (node (ref "D127") (pin "3") (pinfunction "GRN_3") (pintype "bidirectional"))
      (node (ref "D128") (pin "3") (pinfunction "GRN_3") (pintype "bidirectional"))
      (node (ref "D65") (pin "3") (pinfunction "GRN_3") (pintype "bidirectional"))
      (node (ref "D66") (pin "3") (pinfunction "GRN_3") (pintype "bidirectional"))
      (node (ref "D67") (pin "3") (pinfunction "GRN_3") (pintype "bidirectional"))
      (node (ref "D68") (pin "3") (pinfunction "GRN_3") (pintype "bidirectional"))
      (node (ref "D69") (pin "3") (pinfunction "GRN_3") (pintype "bidirectional"))
      (node (ref "D70") (pin "3") (pinfunction "GRN_3") (pintype "bidirectional"))
      (node (ref "D71") (pin "3") (pinfunction "GRN_3") (pintype "bidirectional"))
      (node (ref "D72") (pin "3") (pinfunction "GRN_3") (pintype "bidirectional"))
      (node (ref "D73") (pin "3") (pinfunction "GRN_3") (pintype "bidirectional"))
      (node (ref "D74") (pin "3") (pinfunction "GRN_3") (pintype "bidirectional"))
      (node (ref "D75") (pin "3") (pinfunction "GRN_3") (pintype "bidirectional"))
      (node (ref "D76") (pin "3") (pinfunction "GRN_3") (pintype "bidirectional"))
      (node (ref "D77") (pin "3") (pinfunction "GRN_3") (pintype "bidirectional"))
      (node (ref "D78") (pin "3") (pinfunction "GRN_3") (pintype "bidirectional"))
      (node (ref "D79") (pin "3") (pinfunction "GRN_3") (pintype "bidirectional"))
      (node (ref "D80") (pin "3") (pinfunction "GRN_3") (pintype "bidirectional"))
      (node (ref "D81") (pin "3") (pinfunction "GRN_3") (pintype "bidirectional"))
      (node (ref "D82") (pin "3") (pinfunction "GRN_3") (pintype "bidirectional"))
      (node (ref "D83") (pin "3") (pinfunction "GRN_3") (pintype "bidirectional"))
      (node (ref "D84") (pin "3") (pinfunction "GRN_3") (pintype "bidirectional"))
      (node (ref "D85") (pin "3") (pinfunction "GRN_3") (pintype "bidirectional"))
      (node (ref "D86") (pin "3") (pinfunction "GRN_3") (pintype "bidirectional"))
      (node (ref "D87") (pin "3") (pinfunction "GRN_3") (pintype "bidirectional"))
      (node (ref "D88") (pin "3") (pinfunction "GRN_3") (pintype "bidirectional"))
      (node (ref "D89") (pin "3") (pinfunction "GRN_3") (pintype "bidirectional"))
      (node (ref "D90") (pin "3") (pinfunction "GRN_3") (pintype "bidirectional"))
      (node (ref "D91") (pin "3") (pinfunction "GRN_3") (pintype "bidirectional"))
      (node (ref "D92") (pin "3") (pinfunction "GRN_3") (pintype "bidirectional"))
      (node (ref "D93") (pin "3") (pinfunction "GRN_3") (pintype "bidirectional"))
      (node (ref "D94") (pin "3") (pinfunction "GRN_3") (pintype "bidirectional"))
      (node (ref "D95") (pin "3") (pinfunction "GRN_3") (pintype "bidirectional"))
      (node (ref "D96") (pin "3") (pinfunction "GRN_3") (pintype "bidirectional"))
      (node (ref "D97") (pin "3") (pinfunction "GRN_3") (pintype "bidirectional"))
      (node (ref "D98") (pin "3") (pinfunction "GRN_3") (pintype "bidirectional"))
      (node (ref "D99") (pin "3") (pinfunction "GRN_3") (pintype "bidirectional"))
      (node (ref "Q4") (pin "C") (pinfunction "C_C") (pintype "passive"))
    )
    (net (code "14") (name "Net-(D100-RED)") (class "Default")
      (node (ref "D100") (pin "1") (pinfunction "RED_1") (pintype "bidirectional"))
      (node (ref "D101") (pin "1") (pinfunction "RED_1") (pintype "bidirectional"))
      (node (ref "D102") (pin "1") (pinfunction "RED_1") (pintype "bidirectional"))
      (node (ref "D103") (pin "1") (pinfunction "RED_1") (pintype "bidirectional"))
      (node (ref "D104") (pin "1") (pinfunction "RED_1") (pintype "bidirectional"))
      (node (ref "D105") (pin "1") (pinfunction "RED_1") (pintype "bidirectional"))
      (node (ref "D106") (pin "1") (pinfunction "RED_1") (pintype "bidirectional"))
      (node (ref "D107") (pin "1") (pinfunction "RED_1") (pintype "bidirectional"))
      (node (ref "D108") (pin "1") (pinfunction "RED_1") (pintype "bidirectional"))
      (node (ref "D109") (pin "1") (pinfunction "RED_1") (pintype "bidirectional"))
      (node (ref "D110") (pin "1") (pinfunction "RED_1") (pintype "bidirectional"))
      (node (ref "D111") (pin "1") (pinfunction "RED_1") (pintype "bidirectional"))
      (node (ref "D112") (pin "1") (pinfunction "RED_1") (pintype "bidirectional"))
      (node (ref "D113") (pin "1") (pinfunction "RED_1") (pintype "bidirectional"))
      (node (ref "D114") (pin "1") (pinfunction "RED_1") (pintype "bidirectional"))
      (node (ref "D115") (pin "1") (pinfunction "RED_1") (pintype "bidirectional"))
      (node (ref "D116") (pin "1") (pinfunction "RED_1") (pintype "bidirectional"))
      (node (ref "D117") (pin "1") (pinfunction "RED_1") (pintype "bidirectional"))
      (node (ref "D118") (pin "1") (pinfunction "RED_1") (pintype "bidirectional"))
      (node (ref "D119") (pin "1") (pinfunction "RED_1") (pintype "bidirectional"))
      (node (ref "D120") (pin "1") (pinfunction "RED_1") (pintype "bidirectional"))
      (node (ref "D121") (pin "1") (pinfunction "RED_1") (pintype "bidirectional"))
      (node (ref "D122") (pin "1") (pinfunction "RED_1") (pintype "bidirectional"))
      (node (ref "D123") (pin "1") (pinfunction "RED_1") (pintype "bidirectional"))
      (node (ref "D124") (pin "1") (pinfunction "RED_1") (pintype "bidirectional"))
      (node (ref "D125") (pin "1") (pinfunction "RED_1") (pintype "bidirectional"))
      (node (ref "D126") (pin "1") (pinfunction "RED_1") (pintype "bidirectional"))
      (node (ref "D127") (pin "1") (pinfunction "RED_1") (pintype "bidirectional"))
      (node (ref "D128") (pin "1") (pinfunction "RED_1") (pintype "bidirectional"))
      (node (ref "D65") (pin "1") (pinfunction "RED_1") (pintype "bidirectional"))
      (node (ref "D66") (pin "1") (pinfunction "RED_1") (pintype "bidirectional"))
      (node (ref "D67") (pin "1") (pinfunction "RED_1") (pintype "bidirectional"))
      (node (ref "D68") (pin "1") (pinfunction "RED_1") (pintype "bidirectional"))
      (node (ref "D69") (pin "1") (pinfunction "RED_1") (pintype "bidirectional"))
      (node (ref "D70") (pin "1") (pinfunction "RED_1") (pintype "bidirectional"))
      (node (ref "D71") (pin "1") (pinfunction "RED_1") (pintype "bidirectional"))
      (node (ref "D72") (pin "1") (pinfunction "RED_1") (pintype "bidirectional"))
      (node (ref "D73") (pin "1") (pinfunction "RED_1") (pintype "bidirectional"))
      (node (ref "D74") (pin "1") (pinfunction "RED_1") (pintype "bidirectional"))
      (node (ref "D75") (pin "1") (pinfunction "RED_1") (pintype "bidirectional"))
      (node (ref "D76") (pin "1") (pinfunction "RED_1") (pintype "bidirectional"))
      (node (ref "D77") (pin "1") (pinfunction "RED_1") (pintype "bidirectional"))
      (node (ref "D78") (pin "1") (pinfunction "RED_1") (pintype "bidirectional"))
      (node (ref "D79") (pin "1") (pinfunction "RED_1") (pintype "bidirectional"))
      (node (ref "D80") (pin "1") (pinfunction "RED_1") (pintype "bidirectional"))
      (node (ref "D81") (pin "1") (pinfunction "RED_1") (pintype "bidirectional"))
      (node (ref "D82") (pin "1") (pinfunction "RED_1") (pintype "bidirectional"))
      (node (ref "D83") (pin "1") (pinfunction "RED_1") (pintype "bidirectional"))
      (node (ref "D84") (pin "1") (pinfunction "RED_1") (pintype "bidirectional"))
      (node (ref "D85") (pin "1") (pinfunction "RED_1") (pintype "bidirectional"))
      (node (ref "D86") (pin "1") (pinfunction "RED_1") (pintype "bidirectional"))
      (node (ref "D87") (pin "1") (pinfunction "RED_1") (pintype "bidirectional"))
      (node (ref "D88") (pin "1") (pinfunction "RED_1") (pintype "bidirectional"))
      (node (ref "D89") (pin "1") (pinfunction "RED_1") (pintype "bidirectional"))
      (node (ref "D90") (pin "1") (pinfunction "RED_1") (pintype "bidirectional"))
      (node (ref "D91") (pin "1") (pinfunction "RED_1") (pintype "bidirectional"))
      (node (ref "D92") (pin "1") (pinfunction "RED_1") (pintype "bidirectional"))
      (node (ref "D93") (pin "1") (pinfunction "RED_1") (pintype "bidirectional"))
      (node (ref "D94") (pin "1") (pinfunction "RED_1") (pintype "bidirectional"))
      (node (ref "D95") (pin "1") (pinfunction "RED_1") (pintype "bidirectional"))
      (node (ref "D96") (pin "1") (pinfunction "RED_1") (pintype "bidirectional"))
      (node (ref "D97") (pin "1") (pinfunction "RED_1") (pintype "bidirectional"))
      (node (ref "D98") (pin "1") (pinfunction "RED_1") (pintype "bidirectional"))
      (node (ref "D99") (pin "1") (pinfunction "RED_1") (pintype "bidirectional"))
      (node (ref "Q6") (pin "C") (pinfunction "C_C") (pintype "passive"))
    )
    (net (code "15") (name "Net-(D101-C)") (class "Default")
      (node (ref "D101") (pin "2") (pinfunction "C_2") (pintype "bidirectional"))
      (node (ref "D165") (pin "2") (pinfunction "C_2") (pintype "bidirectional"))
      (node (ref "D229") (pin "2") (pinfunction "C_2") (pintype "bidirectional"))
      (node (ref "D293") (pin "2") (pinfunction "C_2") (pintype "bidirectional"))
      (node (ref "D357") (pin "2") (pinfunction "C_2") (pintype "bidirectional"))
      (node (ref "D37") (pin "2") (pinfunction "C_2") (pintype "bidirectional"))
      (node (ref "D421") (pin "2") (pinfunction "C_2") (pintype "bidirectional"))
      (node (ref "D485") (pin "2") (pinfunction "C_2") (pintype "bidirectional"))
      (node (ref "R36") (pin "2") (pinfunction "2_2") (pintype "passive"))
    )
    (net (code "16") (name "Net-(D102-C)") (class "Default")
      (node (ref "D102") (pin "2") (pinfunction "C_2") (pintype "bidirectional"))
      (node (ref "D166") (pin "2") (pinfunction "C_2") (pintype "bidirectional"))
      (node (ref "D230") (pin "2") (pinfunction "C_2") (pintype "bidirectional"))
      (node (ref "D294") (pin "2") (pinfunction "C_2") (pintype "bidirectional"))
      (node (ref "D358") (pin "2") (pinfunction "C_2") (pintype "bidirectional"))
      (node (ref "D38") (pin "2") (pinfunction "C_2") (pintype "bidirectional"))
      (node (ref "D422") (pin "2") (pinfunction "C_2") (pintype "bidirectional"))
      (node (ref "D486") (pin "2") (pinfunction "C_2") (pintype "bidirectional"))
      (node (ref "R35") (pin "2") (pinfunction "2_2") (pintype "passive"))
    )
    (net (code "17") (name "Net-(D103-C)") (class "Default")
      (node (ref "D103") (pin "2") (pinfunction "C_2") (pintype "bidirectional"))
      (node (ref "D167") (pin "2") (pinfunction "C_2") (pintype "bidirectional"))
      (node (ref "D231") (pin "2") (pinfunction "C_2") (pintype "bidirectional"))
      (node (ref "D295") (pin "2") (pinfunction "C_2") (pintype "bidirectional"))
      (node (ref "D359") (pin "2") (pinfunction "C_2") (pintype "bidirectional"))
      (node (ref "D39") (pin "2") (pinfunction "C_2") (pintype "bidirectional"))
      (node (ref "D423") (pin "2") (pinfunction "C_2") (pintype "bidirectional"))
      (node (ref "D487") (pin "2") (pinfunction "C_2") (pintype "bidirectional"))
      (node (ref "R34") (pin "2") (pinfunction "2_2") (pintype "passive"))
    )
    (net (code "18") (name "Net-(D104-C)") (class "Default")
      (node (ref "D104") (pin "2") (pinfunction "C_2") (pintype "bidirectional"))
      (node (ref "D168") (pin "2") (pinfunction "C_2") (pintype "bidirectional"))
      (node (ref "D232") (pin "2") (pinfunction "C_2") (pintype "bidirectional"))
      (node (ref "D296") (pin "2") (pinfunction "C_2") (pintype "bidirectional"))
      (node (ref "D360") (pin "2") (pinfunction "C_2") (pintype "bidirectional"))
      (node (ref "D40") (pin "2") (pinfunction "C_2") (pintype "bidirectional"))
      (node (ref "D424") (pin "2") (pinfunction "C_2") (pintype "bidirectional"))
      (node (ref "D488") (pin "2") (pinfunction "C_2") (pintype "bidirectional"))
      (node (ref "R33") (pin "2") (pinfunction "2_2") (pintype "passive"))
    )
    (net (code "19") (name "Net-(D105-C)") (class "Default")
      (node (ref "D105") (pin "2") (pinfunction "C_2") (pintype "bidirectional"))
      (node (ref "D169") (pin "2") (pinfunction "C_2") (pintype "bidirectional"))
      (node (ref "D233") (pin "2") (pinfunction "C_2") (pintype "bidirectional"))
      (node (ref "D297") (pin "2") (pinfunction "C_2") (pintype "bidirectional"))
      (node (ref "D361") (pin "2") (pinfunction "C_2") (pintype "bidirectional"))
      (node (ref "D41") (pin "2") (pinfunction "C_2") (pintype "bidirectional"))
      (node (ref "D425") (pin "2") (pinfunction "C_2") (pintype "bidirectional"))
      (node (ref "D489") (pin "2") (pinfunction "C_2") (pintype "bidirectional"))
      (node (ref "R48") (pin "2") (pinfunction "2_2") (pintype "passive"))
    )
    (net (code "20") (name "Net-(D106-C)") (class "Default")
      (node (ref "D106") (pin "2") (pinfunction "C_2") (pintype "bidirectional"))
      (node (ref "D170") (pin "2") (pinfunction "C_2") (pintype "bidirectional"))
      (node (ref "D234") (pin "2") (pinfunction "C_2") (pintype "bidirectional"))
      (node (ref "D298") (pin "2") (pinfunction "C_2") (pintype "bidirectional"))
      (node (ref "D362") (pin "2") (pinfunction "C_2") (pintype "bidirectional"))
      (node (ref "D42") (pin "2") (pinfunction "C_2") (pintype "bidirectional"))
      (node (ref "D426") (pin "2") (pinfunction "C_2") (pintype "bidirectional"))
      (node (ref "D490") (pin "2") (pinfunction "C_2") (pintype "bidirectional"))
      (node (ref "R47") (pin "2") (pinfunction "2_2") (pintype "passive"))
    )
    (net (code "21") (name "Net-(D107-C)") (class "Default")
      (node (ref "D107") (pin "2") (pinfunction "C_2") (pintype "bidirectional"))
      (node (ref "D171") (pin "2") (pinfunction "C_2") (pintype "bidirectional"))
      (node (ref "D235") (pin "2") (pinfunction "C_2") (pintype "bidirectional"))
      (node (ref "D299") (pin "2") (pinfunction "C_2") (pintype "bidirectional"))
      (node (ref "D363") (pin "2") (pinfunction "C_2") (pintype "bidirectional"))
      (node (ref "D427") (pin "2") (pinfunction "C_2") (pintype "bidirectional"))
      (node (ref "D43") (pin "2") (pinfunction "C_2") (pintype "bidirectional"))
      (node (ref "D491") (pin "2") (pinfunction "C_2") (pintype "bidirectional"))
      (node (ref "R46") (pin "2") (pinfunction "2_2") (pintype "passive"))
    )
    (net (code "22") (name "Net-(D108-C)") (class "Default")
      (node (ref "D108") (pin "2") (pinfunction "C_2") (pintype "bidirectional"))
      (node (ref "D172") (pin "2") (pinfunction "C_2") (pintype "bidirectional"))
      (node (ref "D236") (pin "2") (pinfunction "C_2") (pintype "bidirectional"))
      (node (ref "D300") (pin "2") (pinfunction "C_2") (pintype "bidirectional"))
      (node (ref "D364") (pin "2") (pinfunction "C_2") (pintype "bidirectional"))
      (node (ref "D428") (pin "2") (pinfunction "C_2") (pintype "bidirectional"))
      (node (ref "D44") (pin "2") (pinfunction "C_2") (pintype "bidirectional"))
      (node (ref "D492") (pin "2") (pinfunction "C_2") (pintype "bidirectional"))
      (node (ref "R45") (pin "2") (pinfunction "2_2") (pintype "passive"))
    )
    (net (code "23") (name "Net-(D109-C)") (class "Default")
      (node (ref "D109") (pin "2") (pinfunction "C_2") (pintype "bidirectional"))
      (node (ref "D173") (pin "2") (pinfunction "C_2") (pintype "bidirectional"))
      (node (ref "D237") (pin "2") (pinfunction "C_2") (pintype "bidirectional"))
      (node (ref "D301") (pin "2") (pinfunction "C_2") (pintype "bidirectional"))
      (node (ref "D365") (pin "2") (pinfunction "C_2") (pintype "bidirectional"))
      (node (ref "D429") (pin "2") (pinfunction "C_2") (pintype "bidirectional"))
      (node (ref "D45") (pin "2") (pinfunction "C_2") (pintype "bidirectional"))
      (node (ref "D493") (pin "2") (pinfunction "C_2") (pintype "bidirectional"))
      (node (ref "R44") (pin "2") (pinfunction "2_2") (pintype "passive"))
    )
    (net (code "24") (name "Net-(D110-C)") (class "Default")
      (node (ref "D110") (pin "2") (pinfunction "C_2") (pintype "bidirectional"))
      (node (ref "D174") (pin "2") (pinfunction "C_2") (pintype "bidirectional"))
      (node (ref "D238") (pin "2") (pinfunction "C_2") (pintype "bidirectional"))
      (node (ref "D302") (pin "2") (pinfunction "C_2") (pintype "bidirectional"))
      (node (ref "D366") (pin "2") (pinfunction "C_2") (pintype "bidirectional"))
      (node (ref "D430") (pin "2") (pinfunction "C_2") (pintype "bidirectional"))
      (node (ref "D46") (pin "2") (pinfunction "C_2") (pintype "bidirectional"))
      (node (ref "D494") (pin "2") (pinfunction "C_2") (pintype "bidirectional"))
      (node (ref "R43") (pin "2") (pinfunction "2_2") (pintype "passive"))
    )
    (net (code "25") (name "Net-(D111-C)") (class "Default")
      (node (ref "D111") (pin "2") (pinfunction "C_2") (pintype "bidirectional"))
      (node (ref "D175") (pin "2") (pinfunction "C_2") (pintype "bidirectional"))
      (node (ref "D239") (pin "2") (pinfunction "C_2") (pintype "bidirectional"))
      (node (ref "D303") (pin "2") (pinfunction "C_2") (pintype "bidirectional"))
      (node (ref "D367") (pin "2") (pinfunction "C_2") (pintype "bidirectional"))
      (node (ref "D431") (pin "2") (pinfunction "C_2") (pintype "bidirectional"))
      (node (ref "D47") (pin "2") (pinfunction "C_2") (pintype "bidirectional"))
      (node (ref "D495") (pin "2") (pinfunction "C_2") (pintype "bidirectional"))
      (node (ref "R42") (pin "2") (pinfunction "2_2") (pintype "passive"))
    )
    (net (code "26") (name "Net-(D112-C)") (class "Default")
      (node (ref "D112") (pin "2") (pinfunction "C_2") (pintype "bidirectional"))
      (node (ref "D176") (pin "2") (pinfunction "C_2") (pintype "bidirectional"))
      (node (ref "D240") (pin "2") (pinfunction "C_2") (pintype "bidirectional"))
      (node (ref "D304") (pin "2") (pinfunction "C_2") (pintype "bidirectional"))
      (node (ref "D368") (pin "2") (pinfunction "C_2") (pintype "bidirectional"))
      (node (ref "D432") (pin "2") (pinfunction "C_2") (pintype "bidirectional"))
      (node (ref "D48") (pin "2") (pinfunction "C_2") (pintype "bidirectional"))
      (node (ref "D496") (pin "2") (pinfunction "C_2") (pintype "bidirectional"))
      (node (ref "R41") (pin "2") (pinfunction "2_2") (pintype "passive"))
    )
    (net (code "27") (name "Net-(D113-C)") (class "Default")
      (node (ref "D113") (pin "2") (pinfunction "C_2") (pintype "bidirectional"))
      (node (ref "D177") (pin "2") (pinfunction "C_2") (pintype "bidirectional"))
      (node (ref "D241") (pin "2") (pinfunction "C_2") (pintype "bidirectional"))
      (node (ref "D305") (pin "2") (pinfunction "C_2") (pintype "bidirectional"))
      (node (ref "D369") (pin "2") (pinfunction "C_2") (pintype "bidirectional"))
      (node (ref "D433") (pin "2") (pinfunction "C_2") (pintype "bidirectional"))
      (node (ref "D49") (pin "2") (pinfunction "C_2") (pintype "bidirectional"))
      (node (ref "D497") (pin "2") (pinfunction "C_2") (pintype "bidirectional"))
      (node (ref "R56") (pin "2") (pinfunction "2_2") (pintype "passive"))
    )
    (net (code "28") (name "Net-(D114-C)") (class "Default")
      (node (ref "D114") (pin "2") (pinfunction "C_2") (pintype "bidirectional"))
      (node (ref "D178") (pin "2") (pinfunction "C_2") (pintype "bidirectional"))
      (node (ref "D242") (pin "2") (pinfunction "C_2") (pintype "bidirectional"))
      (node (ref "D306") (pin "2") (pinfunction "C_2") (pintype "bidirectional"))
      (node (ref "D370") (pin "2") (pinfunction "C_2") (pintype "bidirectional"))
      (node (ref "D434") (pin "2") (pinfunction "C_2") (pintype "bidirectional"))
      (node (ref "D498") (pin "2") (pinfunction "C_2") (pintype "bidirectional"))
      (node (ref "D50") (pin "2") (pinfunction "C_2") (pintype "bidirectional"))
      (node (ref "R55") (pin "2") (pinfunction "2_2") (pintype "passive"))
    )
    (net (code "29") (name "Net-(D115-C)") (class "Default")
      (node (ref "D115") (pin "2") (pinfunction "C_2") (pintype "bidirectional"))
      (node (ref "D179") (pin "2") (pinfunction "C_2") (pintype "bidirectional"))
      (node (ref "D243") (pin "2") (pinfunction "C_2") (pintype "bidirectional"))
      (node (ref "D307") (pin "2") (pinfunction "C_2") (pintype "bidirectional"))
      (node (ref "D371") (pin "2") (pinfunction "C_2") (pintype "bidirectional"))
      (node (ref "D435") (pin "2") (pinfunction "C_2") (pintype "bidirectional"))
      (node (ref "D499") (pin "2") (pinfunction "C_2") (pintype "bidirectional"))
      (node (ref "D51") (pin "2") (pinfunction "C_2") (pintype "bidirectional"))
      (node (ref "R54") (pin "2") (pinfunction "2_2") (pintype "passive"))
    )
    (net (code "30") (name "Net-(D116-C)") (class "Default")
      (node (ref "D116") (pin "2") (pinfunction "C_2") (pintype "bidirectional"))
      (node (ref "D180") (pin "2") (pinfunction "C_2") (pintype "bidirectional"))
      (node (ref "D244") (pin "2") (pinfunction "C_2") (pintype "bidirectional"))
      (node (ref "D308") (pin "2") (pinfunction "C_2") (pintype "bidirectional"))
      (node (ref "D372") (pin "2") (pinfunction "C_2") (pintype "bidirectional"))
      (node (ref "D436") (pin "2") (pinfunction "C_2") (pintype "bidirectional"))
      (node (ref "D500") (pin "2") (pinfunction "C_2") (pintype "bidirectional"))
      (node (ref "D52") (pin "2") (pinfunction "C_2") (pintype "bidirectional"))
      (node (ref "R53") (pin "2") (pinfunction "2_2") (pintype "passive"))
    )
    (net (code "31") (name "Net-(D117-C)") (class "Default")
      (node (ref "D117") (pin "2") (pinfunction "C_2") (pintype "bidirectional"))
      (node (ref "D181") (pin "2") (pinfunction "C_2") (pintype "bidirectional"))
      (node (ref "D245") (pin "2") (pinfunction "C_2") (pintype "bidirectional"))
      (node (ref "D309") (pin "2") (pinfunction "C_2") (pintype "bidirectional"))
      (node (ref "D373") (pin "2") (pinfunction "C_2") (pintype "bidirectional"))
      (node (ref "D437") (pin "2") (pinfunction "C_2") (pintype "bidirectional"))
      (node (ref "D501") (pin "2") (pinfunction "C_2") (pintype "bidirectional"))
      (node (ref "D53") (pin "2") (pinfunction "C_2") (pintype "bidirectional"))
      (node (ref "R52") (pin "2") (pinfunction "2_2") (pintype "passive"))
    )
    (net (code "32") (name "Net-(D118-C)") (class "Default")
      (node (ref "D118") (pin "2") (pinfunction "C_2") (pintype "bidirectional"))
      (node (ref "D182") (pin "2") (pinfunction "C_2") (pintype "bidirectional"))
      (node (ref "D246") (pin "2") (pinfunction "C_2") (pintype "bidirectional"))
      (node (ref "D310") (pin "2") (pinfunction "C_2") (pintype "bidirectional"))
      (node (ref "D374") (pin "2") (pinfunction "C_2") (pintype "bidirectional"))
      (node (ref "D438") (pin "2") (pinfunction "C_2") (pintype "bidirectional"))
      (node (ref "D502") (pin "2") (pinfunction "C_2") (pintype "bidirectional"))
      (node (ref "D54") (pin "2") (pinfunction "C_2") (pintype "bidirectional"))
      (node (ref "R51") (pin "2") (pinfunction "2_2") (pintype "passive"))
    )
    (net (code "33") (name "Net-(D119-C)") (class "Default")
      (node (ref "D119") (pin "2") (pinfunction "C_2") (pintype "bidirectional"))
      (node (ref "D183") (pin "2") (pinfunction "C_2") (pintype "bidirectional"))
      (node (ref "D247") (pin "2") (pinfunction "C_2") (pintype "bidirectional"))
      (node (ref "D311") (pin "2") (pinfunction "C_2") (pintype "bidirectional"))
      (node (ref "D375") (pin "2") (pinfunction "C_2") (pintype "bidirectional"))
      (node (ref "D439") (pin "2") (pinfunction "C_2") (pintype "bidirectional"))
      (node (ref "D503") (pin "2") (pinfunction "C_2") (pintype "bidirectional"))
      (node (ref "D55") (pin "2") (pinfunction "C_2") (pintype "bidirectional"))
      (node (ref "R50") (pin "2") (pinfunction "2_2") (pintype "passive"))
    )
    (net (code "34") (name "Net-(D120-C)") (class "Default")
      (node (ref "D120") (pin "2") (pinfunction "C_2") (pintype "bidirectional"))
      (node (ref "D184") (pin "2") (pinfunction "C_2") (pintype "bidirectional"))
      (node (ref "D248") (pin "2") (pinfunction "C_2") (pintype "bidirectional"))
      (node (ref "D312") (pin "2") (pinfunction "C_2") (pintype "bidirectional"))
      (node (ref "D376") (pin "2") (pinfunction "C_2") (pintype "bidirectional"))
      (node (ref "D440") (pin "2") (pinfunction "C_2") (pintype "bidirectional"))
      (node (ref "D504") (pin "2") (pinfunction "C_2") (pintype "bidirectional"))
      (node (ref "D56") (pin "2") (pinfunction "C_2") (pintype "bidirectional"))
      (node (ref "R49") (pin "2") (pinfunction "2_2") (pintype "passive"))
    )
    (net (code "35") (name "Net-(D121-C)") (class "Default")
      (node (ref "D121") (pin "2") (pinfunction "C_2") (pintype "bidirectional"))
      (node (ref "D185") (pin "2") (pinfunction "C_2") (pintype "bidirectional"))
      (node (ref "D249") (pin "2") (pinfunction "C_2") (pintype "bidirectional"))
      (node (ref "D313") (pin "2") (pinfunction "C_2") (pintype "bidirectional"))
      (node (ref "D377") (pin "2") (pinfunction "C_2") (pintype "bidirectional"))
      (node (ref "D441") (pin "2") (pinfunction "C_2") (pintype "bidirectional"))
      (node (ref "D505") (pin "2") (pinfunction "C_2") (pintype "bidirectional"))
      (node (ref "D57") (pin "2") (pinfunction "C_2") (pintype "bidirectional"))
      (node (ref "R64") (pin "2") (pinfunction "2_2") (pintype "passive"))
    )
    (net (code "36") (name "Net-(D122-C)") (class "Default")
      (node (ref "D122") (pin "2") (pinfunction "C_2") (pintype "bidirectional"))
      (node (ref "D186") (pin "2") (pinfunction "C_2") (pintype "bidirectional"))
      (node (ref "D250") (pin "2") (pinfunction "C_2") (pintype "bidirectional"))
      (node (ref "D314") (pin "2") (pinfunction "C_2") (pintype "bidirectional"))
      (node (ref "D378") (pin "2") (pinfunction "C_2") (pintype "bidirectional"))
      (node (ref "D442") (pin "2") (pinfunction "C_2") (pintype "bidirectional"))
      (node (ref "D506") (pin "2") (pinfunction "C_2") (pintype "bidirectional"))
      (node (ref "D58") (pin "2") (pinfunction "C_2") (pintype "bidirectional"))
      (node (ref "R63") (pin "2") (pinfunction "2_2") (pintype "passive"))
    )
    (net (code "37") (name "Net-(D123-C)") (class "Default")
      (node (ref "D123") (pin "2") (pinfunction "C_2") (pintype "bidirectional"))
      (node (ref "D187") (pin "2") (pinfunction "C_2") (pintype "bidirectional"))
      (node (ref "D251") (pin "2") (pinfunction "C_2") (pintype "bidirectional"))
      (node (ref "D315") (pin "2") (pinfunction "C_2") (pintype "bidirectional"))
      (node (ref "D379") (pin "2") (pinfunction "C_2") (pintype "bidirectional"))
      (node (ref "D443") (pin "2") (pinfunction "C_2") (pintype "bidirectional"))
      (node (ref "D507") (pin "2") (pinfunction "C_2") (pintype "bidirectional"))
      (node (ref "D59") (pin "2") (pinfunction "C_2") (pintype "bidirectional"))
      (node (ref "R62") (pin "2") (pinfunction "2_2") (pintype "passive"))
    )
    (net (code "38") (name "Net-(D124-C)") (class "Default")
      (node (ref "D124") (pin "2") (pinfunction "C_2") (pintype "bidirectional"))
      (node (ref "D188") (pin "2") (pinfunction "C_2") (pintype "bidirectional"))
      (node (ref "D252") (pin "2") (pinfunction "C_2") (pintype "bidirectional"))
      (node (ref "D316") (pin "2") (pinfunction "C_2") (pintype "bidirectional"))
      (node (ref "D380") (pin "2") (pinfunction "C_2") (pintype "bidirectional"))
      (node (ref "D444") (pin "2") (pinfunction "C_2") (pintype "bidirectional"))
      (node (ref "D508") (pin "2") (pinfunction "C_2") (pintype "bidirectional"))
      (node (ref "D60") (pin "2") (pinfunction "C_2") (pintype "bidirectional"))
      (node (ref "R61") (pin "2") (pinfunction "2_2") (pintype "passive"))
    )
    (net (code "39") (name "Net-(D125-C)") (class "Default")
      (node (ref "D125") (pin "2") (pinfunction "C_2") (pintype "bidirectional"))
      (node (ref "D189") (pin "2") (pinfunction "C_2") (pintype "bidirectional"))
      (node (ref "D253") (pin "2") (pinfunction "C_2") (pintype "bidirectional"))
      (node (ref "D317") (pin "2") (pinfunction "C_2") (pintype "bidirectional"))
      (node (ref "D381") (pin "2") (pinfunction "C_2") (pintype "bidirectional"))
      (node (ref "D445") (pin "2") (pinfunction "C_2") (pintype "bidirectional"))
      (node (ref "D509") (pin "2") (pinfunction "C_2") (pintype "bidirectional"))
      (node (ref "D61") (pin "2") (pinfunction "C_2") (pintype "bidirectional"))
      (node (ref "R60") (pin "2") (pinfunction "2_2") (pintype "passive"))
    )
    (net (code "40") (name "Net-(D126-C)") (class "Default")
      (node (ref "D126") (pin "2") (pinfunction "C_2") (pintype "bidirectional"))
      (node (ref "D190") (pin "2") (pinfunction "C_2") (pintype "bidirectional"))
      (node (ref "D254") (pin "2") (pinfunction "C_2") (pintype "bidirectional"))
      (node (ref "D318") (pin "2") (pinfunction "C_2") (pintype "bidirectional"))
      (node (ref "D382") (pin "2") (pinfunction "C_2") (pintype "bidirectional"))
      (node (ref "D446") (pin "2") (pinfunction "C_2") (pintype "bidirectional"))
      (node (ref "D510") (pin "2") (pinfunction "C_2") (pintype "bidirectional"))
      (node (ref "D62") (pin "2") (pinfunction "C_2") (pintype "bidirectional"))
      (node (ref "R59") (pin "2") (pinfunction "2_2") (pintype "passive"))
    )
    (net (code "41") (name "Net-(D127-C)") (class "Default")
      (node (ref "D127") (pin "2") (pinfunction "C_2") (pintype "bidirectional"))
      (node (ref "D191") (pin "2") (pinfunction "C_2") (pintype "bidirectional"))
      (node (ref "D255") (pin "2") (pinfunction "C_2") (pintype "bidirectional"))
      (node (ref "D319") (pin "2") (pinfunction "C_2") (pintype "bidirectional"))
      (node (ref "D383") (pin "2") (pinfunction "C_2") (pintype "bidirectional"))
      (node (ref "D447") (pin "2") (pinfunction "C_2") (pintype "bidirectional"))
      (node (ref "D511") (pin "2") (pinfunction "C_2") (pintype "bidirectional"))
      (node (ref "D63") (pin "2") (pinfunction "C_2") (pintype "bidirectional"))
      (node (ref "R58") (pin "2") (pinfunction "2_2") (pintype "passive"))
    )
    (net (code "42") (name "Net-(D128-C)") (class "Default")
      (node (ref "D128") (pin "2") (pinfunction "C_2") (pintype "bidirectional"))
      (node (ref "D192") (pin "2") (pinfunction "C_2") (pintype "bidirectional"))
      (node (ref "D256") (pin "2") (pinfunction "C_2") (pintype "bidirectional"))
      (node (ref "D320") (pin "2") (pinfunction "C_2") (pintype "bidirectional"))
      (node (ref "D384") (pin "2") (pinfunction "C_2") (pintype "bidirectional"))
      (node (ref "D448") (pin "2") (pinfunction "C_2") (pintype "bidirectional"))
      (node (ref "D512") (pin "2") (pinfunction "C_2") (pintype "bidirectional"))
      (node (ref "D64") (pin "2") (pinfunction "C_2") (pintype "bidirectional"))
      (node (ref "R57") (pin "2") (pinfunction "2_2") (pintype "passive"))
    )
    (net (code "43") (name "Net-(D129-BLU)") (class "Default")
      (node (ref "D129") (pin "4") (pinfunction "BLU_4") (pintype "bidirectional"))
      (node (ref "D130") (pin "4") (pinfunction "BLU_4") (pintype "bidirectional"))
      (node (ref "D131") (pin "4") (pinfunction "BLU_4") (pintype "bidirectional"))
      (node (ref "D132") (pin "4") (pinfunction "BLU_4") (pintype "bidirectional"))
      (node (ref "D133") (pin "4") (pinfunction "BLU_4") (pintype "bidirectional"))
      (node (ref "D134") (pin "4") (pinfunction "BLU_4") (pintype "bidirectional"))
      (node (ref "D135") (pin "4") (pinfunction "BLU_4") (pintype "bidirectional"))
      (node (ref "D136") (pin "4") (pinfunction "BLU_4") (pintype "bidirectional"))
      (node (ref "D137") (pin "4") (pinfunction "BLU_4") (pintype "bidirectional"))
      (node (ref "D138") (pin "4") (pinfunction "BLU_4") (pintype "bidirectional"))
      (node (ref "D139") (pin "4") (pinfunction "BLU_4") (pintype "bidirectional"))
      (node (ref "D140") (pin "4") (pinfunction "BLU_4") (pintype "bidirectional"))
      (node (ref "D141") (pin "4") (pinfunction "BLU_4") (pintype "bidirectional"))
      (node (ref "D142") (pin "4") (pinfunction "BLU_4") (pintype "bidirectional"))
      (node (ref "D143") (pin "4") (pinfunction "BLU_4") (pintype "bidirectional"))
      (node (ref "D144") (pin "4") (pinfunction "BLU_4") (pintype "bidirectional"))
      (node (ref "D145") (pin "4") (pinfunction "BLU_4") (pintype "bidirectional"))
      (node (ref "D146") (pin "4") (pinfunction "BLU_4") (pintype "bidirectional"))
      (node (ref "D147") (pin "4") (pinfunction "BLU_4") (pintype "bidirectional"))
      (node (ref "D148") (pin "4") (pinfunction "BLU_4") (pintype "bidirectional"))
      (node (ref "D149") (pin "4") (pinfunction "BLU_4") (pintype "bidirectional"))
      (node (ref "D150") (pin "4") (pinfunction "BLU_4") (pintype "bidirectional"))
      (node (ref "D151") (pin "4") (pinfunction "BLU_4") (pintype "bidirectional"))
      (node (ref "D152") (pin "4") (pinfunction "BLU_4") (pintype "bidirectional"))
      (node (ref "D153") (pin "4") (pinfunction "BLU_4") (pintype "bidirectional"))
      (node (ref "D154") (pin "4") (pinfunction "BLU_4") (pintype "bidirectional"))
      (node (ref "D155") (pin "4") (pinfunction "BLU_4") (pintype "bidirectional"))
      (node (ref "D156") (pin "4") (pinfunction "BLU_4") (pintype "bidirectional"))
      (node (ref "D157") (pin "4") (pinfunction "BLU_4") (pintype "bidirectional"))
      (node (ref "D158") (pin "4") (pinfunction "BLU_4") (pintype "bidirectional"))
      (node (ref "D159") (pin "4") (pinfunction "BLU_4") (pintype "bidirectional"))
      (node (ref "D160") (pin "4") (pinfunction "BLU_4") (pintype "bidirectional"))
      (node (ref "D161") (pin "4") (pinfunction "BLU_4") (pintype "bidirectional"))
      (node (ref "D162") (pin "4") (pinfunction "BLU_4") (pintype "bidirectional"))
      (node (ref "D163") (pin "4") (pinfunction "BLU_4") (pintype "bidirectional"))
      (node (ref "D164") (pin "4") (pinfunction "BLU_4") (pintype "bidirectional"))
      (node (ref "D165") (pin "4") (pinfunction "BLU_4") (pintype "bidirectional"))
      (node (ref "D166") (pin "4") (pinfunction "BLU_4") (pintype "bidirectional"))
      (node (ref "D167") (pin "4") (pinfunction "BLU_4") (pintype "bidirectional"))
      (node (ref "D168") (pin "4") (pinfunction "BLU_4") (pintype "bidirectional"))
      (node (ref "D169") (pin "4") (pinfunction "BLU_4") (pintype "bidirectional"))
      (node (ref "D170") (pin "4") (pinfunction "BLU_4") (pintype "bidirectional"))
      (node (ref "D171") (pin "4") (pinfunction "BLU_4") (pintype "bidirectional"))
      (node (ref "D172") (pin "4") (pinfunction "BLU_4") (pintype "bidirectional"))
      (node (ref "D173") (pin "4") (pinfunction "BLU_4") (pintype "bidirectional"))
      (node (ref "D174") (pin "4") (pinfunction "BLU_4") (pintype "bidirectional"))
      (node (ref "D175") (pin "4") (pinfunction "BLU_4") (pintype "bidirectional"))
      (node (ref "D176") (pin "4") (pinfunction "BLU_4") (pintype "bidirectional"))
      (node (ref "D177") (pin "4") (pinfunction "BLU_4") (pintype "bidirectional"))
      (node (ref "D178") (pin "4") (pinfunction "BLU_4") (pintype "bidirectional"))
      (node (ref "D179") (pin "4") (pinfunction "BLU_4") (pintype "bidirectional"))
      (node (ref "D180") (pin "4") (pinfunction "BLU_4") (pintype "bidirectional"))
      (node (ref "D181") (pin "4") (pinfunction "BLU_4") (pintype "bidirectional"))
      (node (ref "D182") (pin "4") (pinfunction "BLU_4") (pintype "bidirectional"))
      (node (ref "D183") (pin "4") (pinfunction "BLU_4") (pintype "bidirectional"))
      (node (ref "D184") (pin "4") (pinfunction "BLU_4") (pintype "bidirectional"))
      (node (ref "D185") (pin "4") (pinfunction "BLU_4") (pintype "bidirectional"))
      (node (ref "D186") (pin "4") (pinfunction "BLU_4") (pintype "bidirectional"))
      (node (ref "D187") (pin "4") (pinfunction "BLU_4") (pintype "bidirectional"))
      (node (ref "D188") (pin "4") (pinfunction "BLU_4") (pintype "bidirectional"))
      (node (ref "D189") (pin "4") (pinfunction "BLU_4") (pintype "bidirectional"))
      (node (ref "D190") (pin "4") (pinfunction "BLU_4") (pintype "bidirectional"))
      (node (ref "D191") (pin "4") (pinfunction "BLU_4") (pintype "bidirectional"))
      (node (ref "D192") (pin "4") (pinfunction "BLU_4") (pintype "bidirectional"))
      (node (ref "Q8") (pin "C") (pinfunction "C_C") (pintype "passive"))
    )
    (net (code "44") (name "Net-(D129-GRN)") (class "Default")
      (node (ref "D129") (pin "3") (pinfunction "GRN_3") (pintype "bidirectional"))
      (node (ref "D130") (pin "3") (pinfunction "GRN_3") (pintype "bidirectional"))
      (node (ref "D131") (pin "3") (pinfunction "GRN_3") (pintype "bidirectional"))
      (node (ref "D132") (pin "3") (pinfunction "GRN_3") (pintype "bidirectional"))
      (node (ref "D133") (pin "3") (pinfunction "GRN_3") (pintype "bidirectional"))
      (node (ref "D134") (pin "3") (pinfunction "GRN_3") (pintype "bidirectional"))
      (node (ref "D135") (pin "3") (pinfunction "GRN_3") (pintype "bidirectional"))
      (node (ref "D136") (pin "3") (pinfunction "GRN_3") (pintype "bidirectional"))
      (node (ref "D137") (pin "3") (pinfunction "GRN_3") (pintype "bidirectional"))
      (node (ref "D138") (pin "3") (pinfunction "GRN_3") (pintype "bidirectional"))
      (node (ref "D139") (pin "3") (pinfunction "GRN_3") (pintype "bidirectional"))
      (node (ref "D140") (pin "3") (pinfunction "GRN_3") (pintype "bidirectional"))
      (node (ref "D141") (pin "3") (pinfunction "GRN_3") (pintype "bidirectional"))
      (node (ref "D142") (pin "3") (pinfunction "GRN_3") (pintype "bidirectional"))
      (node (ref "D143") (pin "3") (pinfunction "GRN_3") (pintype "bidirectional"))
      (node (ref "D144") (pin "3") (pinfunction "GRN_3") (pintype "bidirectional"))
      (node (ref "D145") (pin "3") (pinfunction "GRN_3") (pintype "bidirectional"))
      (node (ref "D146") (pin "3") (pinfunction "GRN_3") (pintype "bidirectional"))
      (node (ref "D147") (pin "3") (pinfunction "GRN_3") (pintype "bidirectional"))
      (node (ref "D148") (pin "3") (pinfunction "GRN_3") (pintype "bidirectional"))
      (node (ref "D149") (pin "3") (pinfunction "GRN_3") (pintype "bidirectional"))
      (node (ref "D150") (pin "3") (pinfunction "GRN_3") (pintype "bidirectional"))
      (node (ref "D151") (pin "3") (pinfunction "GRN_3") (pintype "bidirectional"))
      (node (ref "D152") (pin "3") (pinfunction "GRN_3") (pintype "bidirectional"))
      (node (ref "D153") (pin "3") (pinfunction "GRN_3") (pintype "bidirectional"))
      (node (ref "D154") (pin "3") (pinfunction "GRN_3") (pintype "bidirectional"))
      (node (ref "D155") (pin "3") (pinfunction "GRN_3") (pintype "bidirectional"))
      (node (ref "D156") (pin "3") (pinfunction "GRN_3") (pintype "bidirectional"))
      (node (ref "D157") (pin "3") (pinfunction "GRN_3") (pintype "bidirectional"))
      (node (ref "D158") (pin "3") (pinfunction "GRN_3") (pintype "bidirectional"))
      (node (ref "D159") (pin "3") (pinfunction "GRN_3") (pintype "bidirectional"))
      (node (ref "D160") (pin "3") (pinfunction "GRN_3") (pintype "bidirectional"))
      (node (ref "D161") (pin "3") (pinfunction "GRN_3") (pintype "bidirectional"))
      (node (ref "D162") (pin "3") (pinfunction "GRN_3") (pintype "bidirectional"))
      (node (ref "D163") (pin "3") (pinfunction "GRN_3") (pintype "bidirectional"))
      (node (ref "D164") (pin "3") (pinfunction "GRN_3") (pintype "bidirectional"))
      (node (ref "D165") (pin "3") (pinfunction "GRN_3") (pintype "bidirectional"))
      (node (ref "D166") (pin "3") (pinfunction "GRN_3") (pintype "bidirectional"))
      (node (ref "D167") (pin "3") (pinfunction "GRN_3") (pintype "bidirectional"))
      (node (ref "D168") (pin "3") (pinfunction "GRN_3") (pintype "bidirectional"))
      (node (ref "D169") (pin "3") (pinfunction "GRN_3") (pintype "bidirectional"))
      (node (ref "D170") (pin "3") (pinfunction "GRN_3") (pintype "bidirectional"))
      (node (ref "D171") (pin "3") (pinfunction "GRN_3") (pintype "bidirectional"))
      (node (ref "D172") (pin "3") (pinfunction "GRN_3") (pintype "bidirectional"))
      (node (ref "D173") (pin "3") (pinfunction "GRN_3") (pintype "bidirectional"))
      (node (ref "D174") (pin "3") (pinfunction "GRN_3") (pintype "bidirectional"))
      (node (ref "D175") (pin "3") (pinfunction "GRN_3") (pintype "bidirectional"))
      (node (ref "D176") (pin "3") (pinfunction "GRN_3") (pintype "bidirectional"))
      (node (ref "D177") (pin "3") (pinfunction "GRN_3") (pintype "bidirectional"))
      (node (ref "D178") (pin "3") (pinfunction "GRN_3") (pintype "bidirectional"))
      (node (ref "D179") (pin "3") (pinfunction "GRN_3") (pintype "bidirectional"))
      (node (ref "D180") (pin "3") (pinfunction "GRN_3") (pintype "bidirectional"))
      (node (ref "D181") (pin "3") (pinfunction "GRN_3") (pintype "bidirectional"))
      (node (ref "D182") (pin "3") (pinfunction "GRN_3") (pintype "bidirectional"))
      (node (ref "D183") (pin "3") (pinfunction "GRN_3") (pintype "bidirectional"))
      (node (ref "D184") (pin "3") (pinfunction "GRN_3") (pintype "bidirectional"))
      (node (ref "D185") (pin "3") (pinfunction "GRN_3") (pintype "bidirectional"))
      (node (ref "D186") (pin "3") (pinfunction "GRN_3") (pintype "bidirectional"))
      (node (ref "D187") (pin "3") (pinfunction "GRN_3") (pintype "bidirectional"))
      (node (ref "D188") (pin "3") (pinfunction "GRN_3") (pintype "bidirectional"))
      (node (ref "D189") (pin "3") (pinfunction "GRN_3") (pintype "bidirectional"))
      (node (ref "D190") (pin "3") (pinfunction "GRN_3") (pintype "bidirectional"))
      (node (ref "D191") (pin "3") (pinfunction "GRN_3") (pintype "bidirectional"))
      (node (ref "D192") (pin "3") (pinfunction "GRN_3") (pintype "bidirectional"))
      (node (ref "Q7") (pin "C") (pinfunction "C_C") (pintype "passive"))
    )
    (net (code "45") (name "Net-(D129-RED)") (class "Default")
      (node (ref "D129") (pin "1") (pinfunction "RED_1") (pintype "bidirectional"))
      (node (ref "D130") (pin "1") (pinfunction "RED_1") (pintype "bidirectional"))
      (node (ref "D131") (pin "1") (pinfunction "RED_1") (pintype "bidirectional"))
      (node (ref "D132") (pin "1") (pinfunction "RED_1") (pintype "bidirectional"))
      (node (ref "D133") (pin "1") (pinfunction "RED_1") (pintype "bidirectional"))
      (node (ref "D134") (pin "1") (pinfunction "RED_1") (pintype "bidirectional"))
      (node (ref "D135") (pin "1") (pinfunction "RED_1") (pintype "bidirectional"))
      (node (ref "D136") (pin "1") (pinfunction "RED_1") (pintype "bidirectional"))
      (node (ref "D137") (pin "1") (pinfunction "RED_1") (pintype "bidirectional"))
      (node (ref "D138") (pin "1") (pinfunction "RED_1") (pintype "bidirectional"))
      (node (ref "D139") (pin "1") (pinfunction "RED_1") (pintype "bidirectional"))
      (node (ref "D140") (pin "1") (pinfunction "RED_1") (pintype "bidirectional"))
      (node (ref "D141") (pin "1") (pinfunction "RED_1") (pintype "bidirectional"))
      (node (ref "D142") (pin "1") (pinfunction "RED_1") (pintype "bidirectional"))
      (node (ref "D143") (pin "1") (pinfunction "RED_1") (pintype "bidirectional"))
      (node (ref "D144") (pin "1") (pinfunction "RED_1") (pintype "bidirectional"))
      (node (ref "D145") (pin "1") (pinfunction "RED_1") (pintype "bidirectional"))
      (node (ref "D146") (pin "1") (pinfunction "RED_1") (pintype "bidirectional"))
      (node (ref "D147") (pin "1") (pinfunction "RED_1") (pintype "bidirectional"))
      (node (ref "D148") (pin "1") (pinfunction "RED_1") (pintype "bidirectional"))
      (node (ref "D149") (pin "1") (pinfunction "RED_1") (pintype "bidirectional"))
      (node (ref "D150") (pin "1") (pinfunction "RED_1") (pintype "bidirectional"))
      (node (ref "D151") (pin "1") (pinfunction "RED_1") (pintype "bidirectional"))
      (node (ref "D152") (pin "1") (pinfunction "RED_1") (pintype "bidirectional"))
      (node (ref "D153") (pin "1") (pinfunction "RED_1") (pintype "bidirectional"))
      (node (ref "D154") (pin "1") (pinfunction "RED_1") (pintype "bidirectional"))
      (node (ref "D155") (pin "1") (pinfunction "RED_1") (pintype "bidirectional"))
      (node (ref "D156") (pin "1") (pinfunction "RED_1") (pintype "bidirectional"))
      (node (ref "D157") (pin "1") (pinfunction "RED_1") (pintype "bidirectional"))
      (node (ref "D158") (pin "1") (pinfunction "RED_1") (pintype "bidirectional"))
      (node (ref "D159") (pin "1") (pinfunction "RED_1") (pintype "bidirectional"))
      (node (ref "D160") (pin "1") (pinfunction "RED_1") (pintype "bidirectional"))
      (node (ref "D161") (pin "1") (pinfunction "RED_1") (pintype "bidirectional"))
      (node (ref "D162") (pin "1") (pinfunction "RED_1") (pintype "bidirectional"))
      (node (ref "D163") (pin "1") (pinfunction "RED_1") (pintype "bidirectional"))
      (node (ref "D164") (pin "1") (pinfunction "RED_1") (pintype "bidirectional"))
      (node (ref "D165") (pin "1") (pinfunction "RED_1") (pintype "bidirectional"))
      (node (ref "D166") (pin "1") (pinfunction "RED_1") (pintype "bidirectional"))
      (node (ref "D167") (pin "1") (pinfunction "RED_1") (pintype "bidirectional"))
      (node (ref "D168") (pin "1") (pinfunction "RED_1") (pintype "bidirectional"))
      (node (ref "D169") (pin "1") (pinfunction "RED_1") (pintype "bidirectional"))
      (node (ref "D170") (pin "1") (pinfunction "RED_1") (pintype "bidirectional"))
      (node (ref "D171") (pin "1") (pinfunction "RED_1") (pintype "bidirectional"))
      (node (ref "D172") (pin "1") (pinfunction "RED_1") (pintype "bidirectional"))
      (node (ref "D173") (pin "1") (pinfunction "RED_1") (pintype "bidirectional"))
      (node (ref "D174") (pin "1") (pinfunction "RED_1") (pintype "bidirectional"))
      (node (ref "D175") (pin "1") (pinfunction "RED_1") (pintype "bidirectional"))
      (node (ref "D176") (pin "1") (pinfunction "RED_1") (pintype "bidirectional"))
      (node (ref "D177") (pin "1") (pinfunction "RED_1") (pintype "bidirectional"))
      (node (ref "D178") (pin "1") (pinfunction "RED_1") (pintype "bidirectional"))
      (node (ref "D179") (pin "1") (pinfunction "RED_1") (pintype "bidirectional"))
      (node (ref "D180") (pin "1") (pinfunction "RED_1") (pintype "bidirectional"))
      (node (ref "D181") (pin "1") (pinfunction "RED_1") (pintype "bidirectional"))
      (node (ref "D182") (pin "1") (pinfunction "RED_1") (pintype "bidirectional"))
      (node (ref "D183") (pin "1") (pinfunction "RED_1") (pintype "bidirectional"))
      (node (ref "D184") (pin "1") (pinfunction "RED_1") (pintype "bidirectional"))
      (node (ref "D185") (pin "1") (pinfunction "RED_1") (pintype "bidirectional"))
      (node (ref "D186") (pin "1") (pinfunction "RED_1") (pintype "bidirectional"))
      (node (ref "D187") (pin "1") (pinfunction "RED_1") (pintype "bidirectional"))
      (node (ref "D188") (pin "1") (pinfunction "RED_1") (pintype "bidirectional"))
      (node (ref "D189") (pin "1") (pinfunction "RED_1") (pintype "bidirectional"))
      (node (ref "D190") (pin "1") (pinfunction "RED_1") (pintype "bidirectional"))
      (node (ref "D191") (pin "1") (pinfunction "RED_1") (pintype "bidirectional"))
      (node (ref "D192") (pin "1") (pinfunction "RED_1") (pintype "bidirectional"))
      (node (ref "Q9") (pin "C") (pinfunction "C_C") (pintype "passive"))
    )
    (net (code "46") (name "Net-(D130-C)") (class "Default")
      (node (ref "D130") (pin "2") (pinfunction "C_2") (pintype "bidirectional"))
      (node (ref "D194") (pin "2") (pinfunction "C_2") (pintype "bidirectional"))
      (node (ref "D2") (pin "2") (pinfunction "C_2") (pintype "bidirectional"))
      (node (ref "D258") (pin "2") (pinfunction "C_2") (pintype "bidirectional"))
      (node (ref "D322") (pin "2") (pinfunction "C_2") (pintype "bidirectional"))
      (node (ref "D386") (pin "2") (pinfunction "C_2") (pintype "bidirectional"))
      (node (ref "D450") (pin "2") (pinfunction "C_2") (pintype "bidirectional"))
      (node (ref "D66") (pin "2") (pinfunction "C_2") (pintype "bidirectional"))
      (node (ref "R7") (pin "2") (pinfunction "2_2") (pintype "passive"))
    )
    (net (code "47") (name "Net-(D131-C)") (class "Default")
      (node (ref "D131") (pin "2") (pinfunction "C_2") (pintype "bidirectional"))
      (node (ref "D195") (pin "2") (pinfunction "C_2") (pintype "bidirectional"))
      (node (ref "D259") (pin "2") (pinfunction "C_2") (pintype "bidirectional"))
      (node (ref "D3") (pin "2") (pinfunction "C_2") (pintype "bidirectional"))
      (node (ref "D323") (pin "2") (pinfunction "C_2") (pintype "bidirectional"))
      (node (ref "D387") (pin "2") (pinfunction "C_2") (pintype "bidirectional"))
      (node (ref "D451") (pin "2") (pinfunction "C_2") (pintype "bidirectional"))
      (node (ref "D67") (pin "2") (pinfunction "C_2") (pintype "bidirectional"))
      (node (ref "R6") (pin "2") (pinfunction "2_2") (pintype "passive"))
    )
    (net (code "48") (name "Net-(D132-C)") (class "Default")
      (node (ref "D132") (pin "2") (pinfunction "C_2") (pintype "bidirectional"))
      (node (ref "D196") (pin "2") (pinfunction "C_2") (pintype "bidirectional"))
      (node (ref "D260") (pin "2") (pinfunction "C_2") (pintype "bidirectional"))
      (node (ref "D324") (pin "2") (pinfunction "C_2") (pintype "bidirectional"))
      (node (ref "D388") (pin "2") (pinfunction "C_2") (pintype "bidirectional"))
      (node (ref "D4") (pin "2") (pinfunction "C_2") (pintype "bidirectional"))
      (node (ref "D452") (pin "2") (pinfunction "C_2") (pintype "bidirectional"))
      (node (ref "D68") (pin "2") (pinfunction "C_2") (pintype "bidirectional"))
      (node (ref "R5") (pin "2") (pinfunction "2_2") (pintype "passive"))
    )
    (net (code "49") (name "Net-(D133-C)") (class "Default")
      (node (ref "D133") (pin "2") (pinfunction "C_2") (pintype "bidirectional"))
      (node (ref "D197") (pin "2") (pinfunction "C_2") (pintype "bidirectional"))
      (node (ref "D261") (pin "2") (pinfunction "C_2") (pintype "bidirectional"))
      (node (ref "D325") (pin "2") (pinfunction "C_2") (pintype "bidirectional"))
      (node (ref "D389") (pin "2") (pinfunction "C_2") (pintype "bidirectional"))
      (node (ref "D453") (pin "2") (pinfunction "C_2") (pintype "bidirectional"))
      (node (ref "D5") (pin "2") (pinfunction "C_2") (pintype "bidirectional"))
      (node (ref "D69") (pin "2") (pinfunction "C_2") (pintype "bidirectional"))
      (node (ref "R4") (pin "2") (pinfunction "2_2") (pintype "passive"))
    )
    (net (code "50") (name "Net-(D134-C)") (class "Default")
      (node (ref "D134") (pin "2") (pinfunction "C_2") (pintype "bidirectional"))
      (node (ref "D198") (pin "2") (pinfunction "C_2") (pintype "bidirectional"))
      (node (ref "D262") (pin "2") (pinfunction "C_2") (pintype "bidirectional"))
      (node (ref "D326") (pin "2") (pinfunction "C_2") (pintype "bidirectional"))
      (node (ref "D390") (pin "2") (pinfunction "C_2") (pintype "bidirectional"))
      (node (ref "D454") (pin "2") (pinfunction "C_2") (pintype "bidirectional"))
      (node (ref "D6") (pin "2") (pinfunction "C_2") (pintype "bidirectional"))
      (node (ref "D70") (pin "2") (pinfunction "C_2") (pintype "bidirectional"))
      (node (ref "R3") (pin "2") (pinfunction "2_2") (pintype "passive"))
    )
    (net (code "51") (name "Net-(D135-C)") (class "Default")
      (node (ref "D135") (pin "2") (pinfunction "C_2") (pintype "bidirectional"))
      (node (ref "D199") (pin "2") (pinfunction "C_2") (pintype "bidirectional"))
      (node (ref "D263") (pin "2") (pinfunction "C_2") (pintype "bidirectional"))
      (node (ref "D327") (pin "2") (pinfunction "C_2") (pintype "bidirectional"))
      (node (ref "D391") (pin "2") (pinfunction "C_2") (pintype "bidirectional"))
      (node (ref "D455") (pin "2") (pinfunction "C_2") (pintype "bidirectional"))
      (node (ref "D7") (pin "2") (pinfunction "C_2") (pintype "bidirectional"))
      (node (ref "D71") (pin "2") (pinfunction "C_2") (pintype "bidirectional"))
      (node (ref "R2") (pin "2") (pinfunction "2_2") (pintype "passive"))
    )
    (net (code "52") (name "Net-(D136-C)") (class "Default")
      (node (ref "D136") (pin "2") (pinfunction "C_2") (pintype "bidirectional"))
      (node (ref "D200") (pin "2") (pinfunction "C_2") (pintype "bidirectional"))
      (node (ref "D264") (pin "2") (pinfunction "C_2") (pintype "bidirectional"))
      (node (ref "D328") (pin "2") (pinfunction "C_2") (pintype "bidirectional"))
      (node (ref "D392") (pin "2") (pinfunction "C_2") (pintype "bidirectional"))
      (node (ref "D456") (pin "2") (pinfunction "C_2") (pintype "bidirectional"))
      (node (ref "D72") (pin "2") (pinfunction "C_2") (pintype "bidirectional"))
      (node (ref "D8") (pin "2") (pinfunction "C_2") (pintype "bidirectional"))
      (node (ref "R1") (pin "2") (pinfunction "2_2") (pintype "passive"))
    )
    (net (code "53") (name "Net-(D137-C)") (class "Default")
      (node (ref "D137") (pin "2") (pinfunction "C_2") (pintype "bidirectional"))
      (node (ref "D201") (pin "2") (pinfunction "C_2") (pintype "bidirectional"))
      (node (ref "D265") (pin "2") (pinfunction "C_2") (pintype "bidirectional"))
      (node (ref "D329") (pin "2") (pinfunction "C_2") (pintype "bidirectional"))
      (node (ref "D393") (pin "2") (pinfunction "C_2") (pintype "bidirectional"))
      (node (ref "D457") (pin "2") (pinfunction "C_2") (pintype "bidirectional"))
      (node (ref "D73") (pin "2") (pinfunction "C_2") (pintype "bidirectional"))
      (node (ref "D9") (pin "2") (pinfunction "C_2") (pintype "bidirectional"))
      (node (ref "R16") (pin "2") (pinfunction "2_2") (pintype "passive"))
    )
    (net (code "54") (name "Net-(D143-C)") (class "Default")
      (node (ref "D143") (pin "2") (pinfunction "C_2") (pintype "bidirectional"))
      (node (ref "D15") (pin "2") (pinfunction "C_2") (pintype "bidirectional"))
      (node (ref "D207") (pin "2") (pinfunction "C_2") (pintype "bidirectional"))
      (node (ref "D271") (pin "2") (pinfunction "C_2") (pintype "bidirectional"))
      (node (ref "D335") (pin "2") (pinfunction "C_2") (pintype "bidirectional"))
      (node (ref "D399") (pin "2") (pinfunction "C_2") (pintype "bidirectional"))
      (node (ref "D463") (pin "2") (pinfunction "C_2") (pintype "bidirectional"))
      (node (ref "D79") (pin "2") (pinfunction "C_2") (pintype "bidirectional"))
      (node (ref "R10") (pin "2") (pinfunction "2_2") (pintype "passive"))
    )
    (net (code "55") (name "Net-(D144-C)") (class "Default")
      (node (ref "D144") (pin "2") (pinfunction "C_2") (pintype "bidirectional"))
      (node (ref "D16") (pin "2") (pinfunction "C_2") (pintype "bidirectional"))
      (node (ref "D208") (pin "2") (pinfunction "C_2") (pintype "bidirectional"))
      (node (ref "D272") (pin "2") (pinfunction "C_2") (pintype "bidirectional"))
      (node (ref "D336") (pin "2") (pinfunction "C_2") (pintype "bidirectional"))
      (node (ref "D400") (pin "2") (pinfunction "C_2") (pintype "bidirectional"))
      (node (ref "D464") (pin "2") (pinfunction "C_2") (pintype "bidirectional"))
      (node (ref "D80") (pin "2") (pinfunction "C_2") (pintype "bidirectional"))
      (node (ref "R9") (pin "2") (pinfunction "2_2") (pintype "passive"))
    )
    (net (code "56") (name "Net-(D145-C)") (class "Default")
      (node (ref "D145") (pin "2") (pinfunction "C_2") (pintype "bidirectional"))
      (node (ref "D17") (pin "2") (pinfunction "C_2") (pintype "bidirectional"))
      (node (ref "D209") (pin "2") (pinfunction "C_2") (pintype "bidirectional"))
      (node (ref "D273") (pin "2") (pinfunction "C_2") (pintype "bidirectional"))
      (node (ref "D337") (pin "2") (pinfunction "C_2") (pintype "bidirectional"))
      (node (ref "D401") (pin "2") (pinfunction "C_2") (pintype "bidirectional"))
      (node (ref "D465") (pin "2") (pinfunction "C_2") (pintype "bidirectional"))
      (node (ref "D81") (pin "2") (pinfunction "C_2") (pintype "bidirectional"))
      (node (ref "R24") (pin "2") (pinfunction "2_2") (pintype "passive"))
    )
    (net (code "57") (name "Net-(D146-C)") (class "Default")
      (node (ref "D146") (pin "2") (pinfunction "C_2") (pintype "bidirectional"))
      (node (ref "D18") (pin "2") (pinfunction "C_2") (pintype "bidirectional"))
      (node (ref "D210") (pin "2") (pinfunction "C_2") (pintype "bidirectional"))
      (node (ref "D274") (pin "2") (pinfunction "C_2") (pintype "bidirectional"))
      (node (ref "D338") (pin "2") (pinfunction "C_2") (pintype "bidirectional"))
      (node (ref "D402") (pin "2") (pinfunction "C_2") (pintype "bidirectional"))
      (node (ref "D466") (pin "2") (pinfunction "C_2") (pintype "bidirectional"))
      (node (ref "D82") (pin "2") (pinfunction "C_2") (pintype "bidirectional"))
      (node (ref "R23") (pin "2") (pinfunction "2_2") (pintype "passive"))
    )
    (net (code "58") (name "Net-(D147-C)") (class "Default")
      (node (ref "D147") (pin "2") (pinfunction "C_2") (pintype "bidirectional"))
      (node (ref "D19") (pin "2") (pinfunction "C_2") (pintype "bidirectional"))
      (node (ref "D211") (pin "2") (pinfunction "C_2") (pintype "bidirectional"))
      (node (ref "D275") (pin "2") (pinfunction "C_2") (pintype "bidirectional"))
      (node (ref "D339") (pin "2") (pinfunction "C_2") (pintype "bidirectional"))
      (node (ref "D403") (pin "2") (pinfunction "C_2") (pintype "bidirectional"))
      (node (ref "D467") (pin "2") (pinfunction "C_2") (pintype "bidirectional"))
      (node (ref "D83") (pin "2") (pinfunction "C_2") (pintype "bidirectional"))
      (node (ref "R22") (pin "2") (pinfunction "2_2") (pintype "passive"))
    )
    (net (code "59") (name "Net-(D148-C)") (class "Default")
      (node (ref "D148") (pin "2") (pinfunction "C_2") (pintype "bidirectional"))
      (node (ref "D20") (pin "2") (pinfunction "C_2") (pintype "bidirectional"))
      (node (ref "D212") (pin "2") (pinfunction "C_2") (pintype "bidirectional"))
      (node (ref "D276") (pin "2") (pinfunction "C_2") (pintype "bidirectional"))
      (node (ref "D340") (pin "2") (pinfunction "C_2") (pintype "bidirectional"))
      (node (ref "D404") (pin "2") (pinfunction "C_2") (pintype "bidirectional"))
      (node (ref "D468") (pin "2") (pinfunction "C_2") (pintype "bidirectional"))
      (node (ref "D84") (pin "2") (pinfunction "C_2") (pintype "bidirectional"))
      (node (ref "R21") (pin "2") (pinfunction "2_2") (pintype "passive"))
    )
    (net (code "60") (name "Net-(D149-C)") (class "Default")
      (node (ref "D149") (pin "2") (pinfunction "C_2") (pintype "bidirectional"))
      (node (ref "D21") (pin "2") (pinfunction "C_2") (pintype "bidirectional"))
      (node (ref "D213") (pin "2") (pinfunction "C_2") (pintype "bidirectional"))
      (node (ref "D277") (pin "2") (pinfunction "C_2") (pintype "bidirectional"))
      (node (ref "D341") (pin "2") (pinfunction "C_2") (pintype "bidirectional"))
      (node (ref "D405") (pin "2") (pinfunction "C_2") (pintype "bidirectional"))
      (node (ref "D469") (pin "2") (pinfunction "C_2") (pintype "bidirectional"))
      (node (ref "D85") (pin "2") (pinfunction "C_2") (pintype "bidirectional"))
      (node (ref "R20") (pin "2") (pinfunction "2_2") (pintype "passive"))
    )
    (net (code "61") (name "Net-(D150-C)") (class "Default")
      (node (ref "D150") (pin "2") (pinfunction "C_2") (pintype "bidirectional"))
      (node (ref "D214") (pin "2") (pinfunction "C_2") (pintype "bidirectional"))
      (node (ref "D22") (pin "2") (pinfunction "C_2") (pintype "bidirectional"))
      (node (ref "D278") (pin "2") (pinfunction "C_2") (pintype "bidirectional"))
      (node (ref "D342") (pin "2") (pinfunction "C_2") (pintype "bidirectional"))
      (node (ref "D406") (pin "2") (pinfunction "C_2") (pintype "bidirectional"))
      (node (ref "D470") (pin "2") (pinfunction "C_2") (pintype "bidirectional"))
      (node (ref "D86") (pin "2") (pinfunction "C_2") (pintype "bidirectional"))
      (node (ref "R19") (pin "2") (pinfunction "2_2") (pintype "passive"))
    )
    (net (code "62") (name "Net-(D151-C)") (class "Default")
      (node (ref "D151") (pin "2") (pinfunction "C_2") (pintype "bidirectional"))
      (node (ref "D215") (pin "2") (pinfunction "C_2") (pintype "bidirectional"))
      (node (ref "D23") (pin "2") (pinfunction "C_2") (pintype "bidirectional"))
      (node (ref "D279") (pin "2") (pinfunction "C_2") (pintype "bidirectional"))
      (node (ref "D343") (pin "2") (pinfunction "C_2") (pintype "bidirectional"))
      (node (ref "D407") (pin "2") (pinfunction "C_2") (pintype "bidirectional"))
      (node (ref "D471") (pin "2") (pinfunction "C_2") (pintype "bidirectional"))
      (node (ref "D87") (pin "2") (pinfunction "C_2") (pintype "bidirectional"))
      (node (ref "R18") (pin "2") (pinfunction "2_2") (pintype "passive"))
    )
    (net (code "63") (name "Net-(D152-C)") (class "Default")
      (node (ref "D152") (pin "2") (pinfunction "C_2") (pintype "bidirectional"))
      (node (ref "D216") (pin "2") (pinfunction "C_2") (pintype "bidirectional"))
      (node (ref "D24") (pin "2") (pinfunction "C_2") (pintype "bidirectional"))
      (node (ref "D280") (pin "2") (pinfunction "C_2") (pintype "bidirectional"))
      (node (ref "D344") (pin "2") (pinfunction "C_2") (pintype "bidirectional"))
      (node (ref "D408") (pin "2") (pinfunction "C_2") (pintype "bidirectional"))
      (node (ref "D472") (pin "2") (pinfunction "C_2") (pintype "bidirectional"))
      (node (ref "D88") (pin "2") (pinfunction "C_2") (pintype "bidirectional"))
      (node (ref "R17") (pin "2") (pinfunction "2_2") (pintype "passive"))
    )
    (net (code "64") (name "Net-(D153-C)") (class "Default")
      (node (ref "D153") (pin "2") (pinfunction "C_2") (pintype "bidirectional"))
      (node (ref "D217") (pin "2") (pinfunction "C_2") (pintype "bidirectional"))
      (node (ref "D25") (pin "2") (pinfunction "C_2") (pintype "bidirectional"))
      (node (ref "D281") (pin "2") (pinfunction "C_2") (pintype "bidirectional"))
      (node (ref "D345") (pin "2") (pinfunction "C_2") (pintype "bidirectional"))
      (node (ref "D409") (pin "2") (pinfunction "C_2") (pintype "bidirectional"))
      (node (ref "D473") (pin "2") (pinfunction "C_2") (pintype "bidirectional"))
      (node (ref "D89") (pin "2") (pinfunction "C_2") (pintype "bidirectional"))
      (node (ref "R32") (pin "2") (pinfunction "2_2") (pintype "passive"))
    )
    (net (code "65") (name "Net-(D154-C)") (class "Default")
      (node (ref "D154") (pin "2") (pinfunction "C_2") (pintype "bidirectional"))
      (node (ref "D218") (pin "2") (pinfunction "C_2") (pintype "bidirectional"))
      (node (ref "D26") (pin "2") (pinfunction "C_2") (pintype "bidirectional"))
      (node (ref "D282") (pin "2") (pinfunction "C_2") (pintype "bidirectional"))
      (node (ref "D346") (pin "2") (pinfunction "C_2") (pintype "bidirectional"))
      (node (ref "D410") (pin "2") (pinfunction "C_2") (pintype "bidirectional"))
      (node (ref "D474") (pin "2") (pinfunction "C_2") (pintype "bidirectional"))
      (node (ref "D90") (pin "2") (pinfunction "C_2") (pintype "bidirectional"))
      (node (ref "R31") (pin "2") (pinfunction "2_2") (pintype "passive"))
    )
    (net (code "66") (name "Net-(D155-C)") (class "Default")
      (node (ref "D155") (pin "2") (pinfunction "C_2") (pintype "bidirectional"))
      (node (ref "D219") (pin "2") (pinfunction "C_2") (pintype "bidirectional"))
      (node (ref "D27") (pin "2") (pinfunction "C_2") (pintype "bidirectional"))
      (node (ref "D283") (pin "2") (pinfunction "C_2") (pintype "bidirectional"))
      (node (ref "D347") (pin "2") (pinfunction "C_2") (pintype "bidirectional"))
      (node (ref "D411") (pin "2") (pinfunction "C_2") (pintype "bidirectional"))
      (node (ref "D475") (pin "2") (pinfunction "C_2") (pintype "bidirectional"))
      (node (ref "D91") (pin "2") (pinfunction "C_2") (pintype "bidirectional"))
      (node (ref "R30") (pin "2") (pinfunction "2_2") (pintype "passive"))
    )
    (net (code "67") (name "Net-(D156-C)") (class "Default")
      (node (ref "D156") (pin "2") (pinfunction "C_2") (pintype "bidirectional"))
      (node (ref "D220") (pin "2") (pinfunction "C_2") (pintype "bidirectional"))
      (node (ref "D28") (pin "2") (pinfunction "C_2") (pintype "bidirectional"))
      (node (ref "D284") (pin "2") (pinfunction "C_2") (pintype "bidirectional"))
      (node (ref "D348") (pin "2") (pinfunction "C_2") (pintype "bidirectional"))
      (node (ref "D412") (pin "2") (pinfunction "C_2") (pintype "bidirectional"))
      (node (ref "D476") (pin "2") (pinfunction "C_2") (pintype "bidirectional"))
      (node (ref "D92") (pin "2") (pinfunction "C_2") (pintype "bidirectional"))
      (node (ref "R29") (pin "2") (pinfunction "2_2") (pintype "passive"))
    )
    (net (code "68") (name "Net-(D157-C)") (class "Default")
      (node (ref "D157") (pin "2") (pinfunction "C_2") (pintype "bidirectional"))
      (node (ref "D221") (pin "2") (pinfunction "C_2") (pintype "bidirectional"))
      (node (ref "D285") (pin "2") (pinfunction "C_2") (pintype "bidirectional"))
      (node (ref "D29") (pin "2") (pinfunction "C_2") (pintype "bidirectional"))
      (node (ref "D349") (pin "2") (pinfunction "C_2") (pintype "bidirectional"))
      (node (ref "D413") (pin "2") (pinfunction "C_2") (pintype "bidirectional"))
      (node (ref "D477") (pin "2") (pinfunction "C_2") (pintype "bidirectional"))
      (node (ref "D93") (pin "2") (pinfunction "C_2") (pintype "bidirectional"))
      (node (ref "R28") (pin "2") (pinfunction "2_2") (pintype "passive"))
    )
    (net (code "69") (name "Net-(D158-C)") (class "Default")
      (node (ref "D158") (pin "2") (pinfunction "C_2") (pintype "bidirectional"))
      (node (ref "D222") (pin "2") (pinfunction "C_2") (pintype "bidirectional"))
      (node (ref "D286") (pin "2") (pinfunction "C_2") (pintype "bidirectional"))
      (node (ref "D30") (pin "2") (pinfunction "C_2") (pintype "bidirectional"))
      (node (ref "D350") (pin "2") (pinfunction "C_2") (pintype "bidirectional"))
      (node (ref "D414") (pin "2") (pinfunction "C_2") (pintype "bidirectional"))
      (node (ref "D478") (pin "2") (pinfunction "C_2") (pintype "bidirectional"))
      (node (ref "D94") (pin "2") (pinfunction "C_2") (pintype "bidirectional"))
      (node (ref "R27") (pin "2") (pinfunction "2_2") (pintype "passive"))
    )
    (net (code "70") (name "Net-(D159-C)") (class "Default")
      (node (ref "D159") (pin "2") (pinfunction "C_2") (pintype "bidirectional"))
      (node (ref "D223") (pin "2") (pinfunction "C_2") (pintype "bidirectional"))
      (node (ref "D287") (pin "2") (pinfunction "C_2") (pintype "bidirectional"))
      (node (ref "D31") (pin "2") (pinfunction "C_2") (pintype "bidirectional"))
      (node (ref "D351") (pin "2") (pinfunction "C_2") (pintype "bidirectional"))
      (node (ref "D415") (pin "2") (pinfunction "C_2") (pintype "bidirectional"))
      (node (ref "D479") (pin "2") (pinfunction "C_2") (pintype "bidirectional"))
      (node (ref "D95") (pin "2") (pinfunction "C_2") (pintype "bidirectional"))
      (node (ref "R26") (pin "2") (pinfunction "2_2") (pintype "passive"))
    )
    (net (code "71") (name "Net-(D160-C)") (class "Default")
      (node (ref "D160") (pin "2") (pinfunction "C_2") (pintype "bidirectional"))
      (node (ref "D224") (pin "2") (pinfunction "C_2") (pintype "bidirectional"))
      (node (ref "D288") (pin "2") (pinfunction "C_2") (pintype "bidirectional"))
      (node (ref "D32") (pin "2") (pinfunction "C_2") (pintype "bidirectional"))
      (node (ref "D352") (pin "2") (pinfunction "C_2") (pintype "bidirectional"))
      (node (ref "D416") (pin "2") (pinfunction "C_2") (pintype "bidirectional"))
      (node (ref "D480") (pin "2") (pinfunction "C_2") (pintype "bidirectional"))
      (node (ref "D96") (pin "2") (pinfunction "C_2") (pintype "bidirectional"))
      (node (ref "R25") (pin "2") (pinfunction "2_2") (pintype "passive"))
    )
    (net (code "72") (name "Net-(D161-C)") (class "Default")
      (node (ref "D161") (pin "2") (pinfunction "C_2") (pintype "bidirectional"))
      (node (ref "D225") (pin "2") (pinfunction "C_2") (pintype "bidirectional"))
      (node (ref "D289") (pin "2") (pinfunction "C_2") (pintype "bidirectional"))
      (node (ref "D33") (pin "2") (pinfunction "C_2") (pintype "bidirectional"))
      (node (ref "D353") (pin "2") (pinfunction "C_2") (pintype "bidirectional"))
      (node (ref "D417") (pin "2") (pinfunction "C_2") (pintype "bidirectional"))
      (node (ref "D481") (pin "2") (pinfunction "C_2") (pintype "bidirectional"))
      (node (ref "D97") (pin "2") (pinfunction "C_2") (pintype "bidirectional"))
      (node (ref "R40") (pin "2") (pinfunction "2_2") (pintype "passive"))
    )
    (net (code "73") (name "Net-(D162-C)") (class "Default")
      (node (ref "D162") (pin "2") (pinfunction "C_2") (pintype "bidirectional"))
      (node (ref "D226") (pin "2") (pinfunction "C_2") (pintype "bidirectional"))
      (node (ref "D290") (pin "2") (pinfunction "C_2") (pintype "bidirectional"))
      (node (ref "D34") (pin "2") (pinfunction "C_2") (pintype "bidirectional"))
      (node (ref "D354") (pin "2") (pinfunction "C_2") (pintype "bidirectional"))
      (node (ref "D418") (pin "2") (pinfunction "C_2") (pintype "bidirectional"))
      (node (ref "D482") (pin "2") (pinfunction "C_2") (pintype "bidirectional"))
      (node (ref "D98") (pin "2") (pinfunction "C_2") (pintype "bidirectional"))
      (node (ref "R39") (pin "2") (pinfunction "2_2") (pintype "passive"))
    )
    (net (code "74") (name "Net-(D163-C)") (class "Default")
      (node (ref "D163") (pin "2") (pinfunction "C_2") (pintype "bidirectional"))
      (node (ref "D227") (pin "2") (pinfunction "C_2") (pintype "bidirectional"))
      (node (ref "D291") (pin "2") (pinfunction "C_2") (pintype "bidirectional"))
      (node (ref "D35") (pin "2") (pinfunction "C_2") (pintype "bidirectional"))
      (node (ref "D355") (pin "2") (pinfunction "C_2") (pintype "bidirectional"))
      (node (ref "D419") (pin "2") (pinfunction "C_2") (pintype "bidirectional"))
      (node (ref "D483") (pin "2") (pinfunction "C_2") (pintype "bidirectional"))
      (node (ref "D99") (pin "2") (pinfunction "C_2") (pintype "bidirectional"))
      (node (ref "R38") (pin "2") (pinfunction "2_2") (pintype "passive"))
    )
    (net (code "75") (name "Net-(D193-BLU)") (class "Default")
      (node (ref "D193") (pin "4") (pinfunction "BLU_4") (pintype "bidirectional"))
      (node (ref "D194") (pin "4") (pinfunction "BLU_4") (pintype "bidirectional"))
      (node (ref "D195") (pin "4") (pinfunction "BLU_4") (pintype "bidirectional"))
      (node (ref "D196") (pin "4") (pinfunction "BLU_4") (pintype "bidirectional"))
      (node (ref "D197") (pin "4") (pinfunction "BLU_4") (pintype "bidirectional"))
      (node (ref "D198") (pin "4") (pinfunction "BLU_4") (pintype "bidirectional"))
      (node (ref "D199") (pin "4") (pinfunction "BLU_4") (pintype "bidirectional"))
      (node (ref "D200") (pin "4") (pinfunction "BLU_4") (pintype "bidirectional"))
      (node (ref "D201") (pin "4") (pinfunction "BLU_4") (pintype "bidirectional"))
      (node (ref "D202") (pin "4") (pinfunction "BLU_4") (pintype "bidirectional"))
      (node (ref "D203") (pin "4") (pinfunction "BLU_4") (pintype "bidirectional"))
      (node (ref "D204") (pin "4") (pinfunction "BLU_4") (pintype "bidirectional"))
      (node (ref "D205") (pin "4") (pinfunction "BLU_4") (pintype "bidirectional"))
      (node (ref "D206") (pin "4") (pinfunction "BLU_4") (pintype "bidirectional"))
      (node (ref "D207") (pin "4") (pinfunction "BLU_4") (pintype "bidirectional"))
      (node (ref "D208") (pin "4") (pinfunction "BLU_4") (pintype "bidirectional"))
      (node (ref "D209") (pin "4") (pinfunction "BLU_4") (pintype "bidirectional"))
      (node (ref "D210") (pin "4") (pinfunction "BLU_4") (pintype "bidirectional"))
      (node (ref "D211") (pin "4") (pinfunction "BLU_4") (pintype "bidirectional"))
      (node (ref "D212") (pin "4") (pinfunction "BLU_4") (pintype "bidirectional"))
      (node (ref "D213") (pin "4") (pinfunction "BLU_4") (pintype "bidirectional"))
      (node (ref "D214") (pin "4") (pinfunction "BLU_4") (pintype "bidirectional"))
      (node (ref "D215") (pin "4") (pinfunction "BLU_4") (pintype "bidirectional"))
      (node (ref "D216") (pin "4") (pinfunction "BLU_4") (pintype "bidirectional"))
      (node (ref "D217") (pin "4") (pinfunction "BLU_4") (pintype "bidirectional"))
      (node (ref "D218") (pin "4") (pinfunction "BLU_4") (pintype "bidirectional"))
      (node (ref "D219") (pin "4") (pinfunction "BLU_4") (pintype "bidirectional"))
      (node (ref "D220") (pin "4") (pinfunction "BLU_4") (pintype "bidirectional"))
      (node (ref "D221") (pin "4") (pinfunction "BLU_4") (pintype "bidirectional"))
      (node (ref "D222") (pin "4") (pinfunction "BLU_4") (pintype "bidirectional"))
      (node (ref "D223") (pin "4") (pinfunction "BLU_4") (pintype "bidirectional"))
      (node (ref "D224") (pin "4") (pinfunction "BLU_4") (pintype "bidirectional"))
      (node (ref "D225") (pin "4") (pinfunction "BLU_4") (pintype "bidirectional"))
      (node (ref "D226") (pin "4") (pinfunction "BLU_4") (pintype "bidirectional"))
      (node (ref "D227") (pin "4") (pinfunction "BLU_4") (pintype "bidirectional"))
      (node (ref "D228") (pin "4") (pinfunction "BLU_4") (pintype "bidirectional"))
      (node (ref "D229") (pin "4") (pinfunction "BLU_4") (pintype "bidirectional"))
      (node (ref "D230") (pin "4") (pinfunction "BLU_4") (pintype "bidirectional"))
      (node (ref "D231") (pin "4") (pinfunction "BLU_4") (pintype "bidirectional"))
      (node (ref "D232") (pin "4") (pinfunction "BLU_4") (pintype "bidirectional"))
      (node (ref "D233") (pin "4") (pinfunction "BLU_4") (pintype "bidirectional"))
      (node (ref "D234") (pin "4") (pinfunction "BLU_4") (pintype "bidirectional"))
      (node (ref "D235") (pin "4") (pinfunction "BLU_4") (pintype "bidirectional"))
      (node (ref "D236") (pin "4") (pinfunction "BLU_4") (pintype "bidirectional"))
      (node (ref "D237") (pin "4") (pinfunction "BLU_4") (pintype "bidirectional"))
      (node (ref "D238") (pin "4") (pinfunction "BLU_4") (pintype "bidirectional"))
      (node (ref "D239") (pin "4") (pinfunction "BLU_4") (pintype "bidirectional"))
      (node (ref "D240") (pin "4") (pinfunction "BLU_4") (pintype "bidirectional"))
      (node (ref "D241") (pin "4") (pinfunction "BLU_4") (pintype "bidirectional"))
      (node (ref "D242") (pin "4") (pinfunction "BLU_4") (pintype "bidirectional"))
      (node (ref "D243") (pin "4") (pinfunction "BLU_4") (pintype "bidirectional"))
      (node (ref "D244") (pin "4") (pinfunction "BLU_4") (pintype "bidirectional"))
      (node (ref "D245") (pin "4") (pinfunction "BLU_4") (pintype "bidirectional"))
      (node (ref "D246") (pin "4") (pinfunction "BLU_4") (pintype "bidirectional"))
      (node (ref "D247") (pin "4") (pinfunction "BLU_4") (pintype "bidirectional"))
      (node (ref "D248") (pin "4") (pinfunction "BLU_4") (pintype "bidirectional"))
      (node (ref "D249") (pin "4") (pinfunction "BLU_4") (pintype "bidirectional"))
      (node (ref "D250") (pin "4") (pinfunction "BLU_4") (pintype "bidirectional"))
      (node (ref "D251") (pin "4") (pinfunction "BLU_4") (pintype "bidirectional"))
      (node (ref "D252") (pin "4") (pinfunction "BLU_4") (pintype "bidirectional"))
      (node (ref "D253") (pin "4") (pinfunction "BLU_4") (pintype "bidirectional"))
      (node (ref "D254") (pin "4") (pinfunction "BLU_4") (pintype "bidirectional"))
      (node (ref "D255") (pin "4") (pinfunction "BLU_4") (pintype "bidirectional"))
      (node (ref "D256") (pin "4") (pinfunction "BLU_4") (pintype "bidirectional"))
      (node (ref "Q11") (pin "C") (pinfunction "C_C") (pintype "passive"))
    )
    (net (code "76") (name "Net-(D193-GRN)") (class "Default")
      (node (ref "D193") (pin "3") (pinfunction "GRN_3") (pintype "bidirectional"))
      (node (ref "D194") (pin "3") (pinfunction "GRN_3") (pintype "bidirectional"))
      (node (ref "D195") (pin "3") (pinfunction "GRN_3") (pintype "bidirectional"))
      (node (ref "D196") (pin "3") (pinfunction "GRN_3") (pintype "bidirectional"))
      (node (ref "D197") (pin "3") (pinfunction "GRN_3") (pintype "bidirectional"))
      (node (ref "D198") (pin "3") (pinfunction "GRN_3") (pintype "bidirectional"))
      (node (ref "D199") (pin "3") (pinfunction "GRN_3") (pintype "bidirectional"))
      (node (ref "D200") (pin "3") (pinfunction "GRN_3") (pintype "bidirectional"))
      (node (ref "D201") (pin "3") (pinfunction "GRN_3") (pintype "bidirectional"))
      (node (ref "D202") (pin "3") (pinfunction "GRN_3") (pintype "bidirectional"))
      (node (ref "D203") (pin "3") (pinfunction "GRN_3") (pintype "bidirectional"))
      (node (ref "D204") (pin "3") (pinfunction "GRN_3") (pintype "bidirectional"))
      (node (ref "D205") (pin "3") (pinfunction "GRN_3") (pintype "bidirectional"))
      (node (ref "D206") (pin "3") (pinfunction "GRN_3") (pintype "bidirectional"))
      (node (ref "D207") (pin "3") (pinfunction "GRN_3") (pintype "bidirectional"))
      (node (ref "D208") (pin "3") (pinfunction "GRN_3") (pintype "bidirectional"))
      (node (ref "D209") (pin "3") (pinfunction "GRN_3") (pintype "bidirectional"))
      (node (ref "D210") (pin "3") (pinfunction "GRN_3") (pintype "bidirectional"))
      (node (ref "D211") (pin "3") (pinfunction "GRN_3") (pintype "bidirectional"))
      (node (ref "D212") (pin "3") (pinfunction "GRN_3") (pintype "bidirectional"))
      (node (ref "D213") (pin "3") (pinfunction "GRN_3") (pintype "bidirectional"))
      (node (ref "D214") (pin "3") (pinfunction "GRN_3") (pintype "bidirectional"))
      (node (ref "D215") (pin "3") (pinfunction "GRN_3") (pintype "bidirectional"))
      (node (ref "D216") (pin "3") (pinfunction "GRN_3") (pintype "bidirectional"))
      (node (ref "D217") (pin "3") (pinfunction "GRN_3") (pintype "bidirectional"))
      (node (ref "D218") (pin "3") (pinfunction "GRN_3") (pintype "bidirectional"))
      (node (ref "D219") (pin "3") (pinfunction "GRN_3") (pintype "bidirectional"))
      (node (ref "D220") (pin "3") (pinfunction "GRN_3") (pintype "bidirectional"))
      (node (ref "D221") (pin "3") (pinfunction "GRN_3") (pintype "bidirectional"))
      (node (ref "D222") (pin "3") (pinfunction "GRN_3") (pintype "bidirectional"))
      (node (ref "D223") (pin "3") (pinfunction "GRN_3") (pintype "bidirectional"))
      (node (ref "D224") (pin "3") (pinfunction "GRN_3") (pintype "bidirectional"))
      (node (ref "D225") (pin "3") (pinfunction "GRN_3") (pintype "bidirectional"))
      (node (ref "D226") (pin "3") (pinfunction "GRN_3") (pintype "bidirectional"))
      (node (ref "D227") (pin "3") (pinfunction "GRN_3") (pintype "bidirectional"))
      (node (ref "D228") (pin "3") (pinfunction "GRN_3") (pintype "bidirectional"))
      (node (ref "D229") (pin "3") (pinfunction "GRN_3") (pintype "bidirectional"))
      (node (ref "D230") (pin "3") (pinfunction "GRN_3") (pintype "bidirectional"))
      (node (ref "D231") (pin "3") (pinfunction "GRN_3") (pintype "bidirectional"))
      (node (ref "D232") (pin "3") (pinfunction "GRN_3") (pintype "bidirectional"))
      (node (ref "D233") (pin "3") (pinfunction "GRN_3") (pintype "bidirectional"))
      (node (ref "D234") (pin "3") (pinfunction "GRN_3") (pintype "bidirectional"))
      (node (ref "D235") (pin "3") (pinfunction "GRN_3") (pintype "bidirectional"))
      (node (ref "D236") (pin "3") (pinfunction "GRN_3") (pintype "bidirectional"))
      (node (ref "D237") (pin "3") (pinfunction "GRN_3") (pintype "bidirectional"))
      (node (ref "D238") (pin "3") (pinfunction "GRN_3") (pintype "bidirectional"))
      (node (ref "D239") (pin "3") (pinfunction "GRN_3") (pintype "bidirectional"))
      (node (ref "D240") (pin "3") (pinfunction "GRN_3") (pintype "bidirectional"))
      (node (ref "D241") (pin "3") (pinfunction "GRN_3") (pintype "bidirectional"))
      (node (ref "D242") (pin "3") (pinfunction "GRN_3") (pintype "bidirectional"))
      (node (ref "D243") (pin "3") (pinfunction "GRN_3") (pintype "bidirectional"))
      (node (ref "D244") (pin "3") (pinfunction "GRN_3") (pintype "bidirectional"))
      (node (ref "D245") (pin "3") (pinfunction "GRN_3") (pintype "bidirectional"))
      (node (ref "D246") (pin "3") (pinfunction "GRN_3") (pintype "bidirectional"))
      (node (ref "D247") (pin "3") (pinfunction "GRN_3") (pintype "bidirectional"))
      (node (ref "D248") (pin "3") (pinfunction "GRN_3") (pintype "bidirectional"))
      (node (ref "D249") (pin "3") (pinfunction "GRN_3") (pintype "bidirectional"))
      (node (ref "D250") (pin "3") (pinfunction "GRN_3") (pintype "bidirectional"))
      (node (ref "D251") (pin "3") (pinfunction "GRN_3") (pintype "bidirectional"))
      (node (ref "D252") (pin "3") (pinfunction "GRN_3") (pintype "bidirectional"))
      (node (ref "D253") (pin "3") (pinfunction "GRN_3") (pintype "bidirectional"))
      (node (ref "D254") (pin "3") (pinfunction "GRN_3") (pintype "bidirectional"))
      (node (ref "D255") (pin "3") (pinfunction "GRN_3") (pintype "bidirectional"))
      (node (ref "D256") (pin "3") (pinfunction "GRN_3") (pintype "bidirectional"))
      (node (ref "Q10") (pin "C") (pinfunction "C_C") (pintype "passive"))
    )
    (net (code "77") (name "Net-(D193-RED)") (class "Default")
      (node (ref "D193") (pin "1") (pinfunction "RED_1") (pintype "bidirectional"))
      (node (ref "D194") (pin "1") (pinfunction "RED_1") (pintype "bidirectional"))
      (node (ref "D195") (pin "1") (pinfunction "RED_1") (pintype "bidirectional"))
      (node (ref "D196") (pin "1") (pinfunction "RED_1") (pintype "bidirectional"))
      (node (ref "D197") (pin "1") (pinfunction "RED_1") (pintype "bidirectional"))
      (node (ref "D198") (pin "1") (pinfunction "RED_1") (pintype "bidirectional"))
      (node (ref "D199") (pin "1") (pinfunction "RED_1") (pintype "bidirectional"))
      (node (ref "D200") (pin "1") (pinfunction "RED_1") (pintype "bidirectional"))
      (node (ref "D201") (pin "1") (pinfunction "RED_1") (pintype "bidirectional"))
      (node (ref "D202") (pin "1") (pinfunction "RED_1") (pintype "bidirectional"))
      (node (ref "D203") (pin "1") (pinfunction "RED_1") (pintype "bidirectional"))
      (node (ref "D204") (pin "1") (pinfunction "RED_1") (pintype "bidirectional"))
      (node (ref "D205") (pin "1") (pinfunction "RED_1") (pintype "bidirectional"))
      (node (ref "D206") (pin "1") (pinfunction "RED_1") (pintype "bidirectional"))
      (node (ref "D207") (pin "1") (pinfunction "RED_1") (pintype "bidirectional"))
      (node (ref "D208") (pin "1") (pinfunction "RED_1") (pintype "bidirectional"))
      (node (ref "D209") (pin "1") (pinfunction "RED_1") (pintype "bidirectional"))
      (node (ref "D210") (pin "1") (pinfunction "RED_1") (pintype "bidirectional"))
      (node (ref "D211") (pin "1") (pinfunction "RED_1") (pintype "bidirectional"))
      (node (ref "D212") (pin "1") (pinfunction "RED_1") (pintype "bidirectional"))
      (node (ref "D213") (pin "1") (pinfunction "RED_1") (pintype "bidirectional"))
      (node (ref "D214") (pin "1") (pinfunction "RED_1") (pintype "bidirectional"))
      (node (ref "D215") (pin "1") (pinfunction "RED_1") (pintype "bidirectional"))
      (node (ref "D216") (pin "1") (pinfunction "RED_1") (pintype "bidirectional"))
      (node (ref "D217") (pin "1") (pinfunction "RED_1") (pintype "bidirectional"))
      (node (ref "D218") (pin "1") (pinfunction "RED_1") (pintype "bidirectional"))
      (node (ref "D219") (pin "1") (pinfunction "RED_1") (pintype "bidirectional"))
      (node (ref "D220") (pin "1") (pinfunction "RED_1") (pintype "bidirectional"))
      (node (ref "D221") (pin "1") (pinfunction "RED_1") (pintype "bidirectional"))
      (node (ref "D222") (pin "1") (pinfunction "RED_1") (pintype "bidirectional"))
      (node (ref "D223") (pin "1") (pinfunction "RED_1") (pintype "bidirectional"))
      (node (ref "D224") (pin "1") (pinfunction "RED_1") (pintype "bidirectional"))
      (node (ref "D225") (pin "1") (pinfunction "RED_1") (pintype "bidirectional"))
      (node (ref "D226") (pin "1") (pinfunction "RED_1") (pintype "bidirectional"))
      (node (ref "D227") (pin "1") (pinfunction "RED_1") (pintype "bidirectional"))
      (node (ref "D228") (pin "1") (pinfunction "RED_1") (pintype "bidirectional"))
      (node (ref "D229") (pin "1") (pinfunction "RED_1") (pintype "bidirectional"))
      (node (ref "D230") (pin "1") (pinfunction "RED_1") (pintype "bidirectional"))
      (node (ref "D231") (pin "1") (pinfunction "RED_1") (pintype "bidirectional"))
      (node (ref "D232") (pin "1") (pinfunction "RED_1") (pintype "bidirectional"))
      (node (ref "D233") (pin "1") (pinfunction "RED_1") (pintype "bidirectional"))
      (node (ref "D234") (pin "1") (pinfunction "RED_1") (pintype "bidirectional"))
      (node (ref "D235") (pin "1") (pinfunction "RED_1") (pintype "bidirectional"))
      (node (ref "D236") (pin "1") (pinfunction "RED_1") (pintype "bidirectional"))
      (node (ref "D237") (pin "1") (pinfunction "RED_1") (pintype "bidirectional"))
      (node (ref "D238") (pin "1") (pinfunction "RED_1") (pintype "bidirectional"))
      (node (ref "D239") (pin "1") (pinfunction "RED_1") (pintype "bidirectional"))
      (node (ref "D240") (pin "1") (pinfunction "RED_1") (pintype "bidirectional"))
      (node (ref "D241") (pin "1") (pinfunction "RED_1") (pintype "bidirectional"))
      (node (ref "D242") (pin "1") (pinfunction "RED_1") (pintype "bidirectional"))
      (node (ref "D243") (pin "1") (pinfunction "RED_1") (pintype "bidirectional"))
      (node (ref "D244") (pin "1") (pinfunction "RED_1") (pintype "bidirectional"))
      (node (ref "D245") (pin "1") (pinfunction "RED_1") (pintype "bidirectional"))
      (node (ref "D246") (pin "1") (pinfunction "RED_1") (pintype "bidirectional"))
      (node (ref "D247") (pin "1") (pinfunction "RED_1") (pintype "bidirectional"))
      (node (ref "D248") (pin "1") (pinfunction "RED_1") (pintype "bidirectional"))
      (node (ref "D249") (pin "1") (pinfunction "RED_1") (pintype "bidirectional"))
      (node (ref "D250") (pin "1") (pinfunction "RED_1") (pintype "bidirectional"))
      (node (ref "D251") (pin "1") (pinfunction "RED_1") (pintype "bidirectional"))
      (node (ref "D252") (pin "1") (pinfunction "RED_1") (pintype "bidirectional"))
      (node (ref "D253") (pin "1") (pinfunction "RED_1") (pintype "bidirectional"))
      (node (ref "D254") (pin "1") (pinfunction "RED_1") (pintype "bidirectional"))
      (node (ref "D255") (pin "1") (pinfunction "RED_1") (pintype "bidirectional"))
      (node (ref "D256") (pin "1") (pinfunction "RED_1") (pintype "bidirectional"))
      (node (ref "Q12") (pin "C") (pinfunction "C_C") (pintype "passive"))
    )
    (net (code "78") (name "Net-(D257-BLU)") (class "Default")
      (node (ref "D257") (pin "4") (pinfunction "BLU_4") (pintype "bidirectional"))
      (node (ref "D258") (pin "4") (pinfunction "BLU_4") (pintype "bidirectional"))
      (node (ref "D259") (pin "4") (pinfunction "BLU_4") (pintype "bidirectional"))
      (node (ref "D260") (pin "4") (pinfunction "BLU_4") (pintype "bidirectional"))
      (node (ref "D261") (pin "4") (pinfunction "BLU_4") (pintype "bidirectional"))
      (node (ref "D262") (pin "4") (pinfunction "BLU_4") (pintype "bidirectional"))
      (node (ref "D263") (pin "4") (pinfunction "BLU_4") (pintype "bidirectional"))
      (node (ref "D264") (pin "4") (pinfunction "BLU_4") (pintype "bidirectional"))
      (node (ref "D265") (pin "4") (pinfunction "BLU_4") (pintype "bidirectional"))
      (node (ref "D266") (pin "4") (pinfunction "BLU_4") (pintype "bidirectional"))
      (node (ref "D267") (pin "4") (pinfunction "BLU_4") (pintype "bidirectional"))
      (node (ref "D268") (pin "4") (pinfunction "BLU_4") (pintype "bidirectional"))
      (node (ref "D269") (pin "4") (pinfunction "BLU_4") (pintype "bidirectional"))
      (node (ref "D270") (pin "4") (pinfunction "BLU_4") (pintype "bidirectional"))
      (node (ref "D271") (pin "4") (pinfunction "BLU_4") (pintype "bidirectional"))
      (node (ref "D272") (pin "4") (pinfunction "BLU_4") (pintype "bidirectional"))
      (node (ref "D273") (pin "4") (pinfunction "BLU_4") (pintype "bidirectional"))
      (node (ref "D274") (pin "4") (pinfunction "BLU_4") (pintype "bidirectional"))
      (node (ref "D275") (pin "4") (pinfunction "BLU_4") (pintype "bidirectional"))
      (node (ref "D276") (pin "4") (pinfunction "BLU_4") (pintype "bidirectional"))
      (node (ref "D277") (pin "4") (pinfunction "BLU_4") (pintype "bidirectional"))
      (node (ref "D278") (pin "4") (pinfunction "BLU_4") (pintype "bidirectional"))
      (node (ref "D279") (pin "4") (pinfunction "BLU_4") (pintype "bidirectional"))
      (node (ref "D280") (pin "4") (pinfunction "BLU_4") (pintype "bidirectional"))
      (node (ref "D281") (pin "4") (pinfunction "BLU_4") (pintype "bidirectional"))
      (node (ref "D282") (pin "4") (pinfunction "BLU_4") (pintype "bidirectional"))
      (node (ref "D283") (pin "4") (pinfunction "BLU_4") (pintype "bidirectional"))
      (node (ref "D284") (pin "4") (pinfunction "BLU_4") (pintype "bidirectional"))
      (node (ref "D285") (pin "4") (pinfunction "BLU_4") (pintype "bidirectional"))
      (node (ref "D286") (pin "4") (pinfunction "BLU_4") (pintype "bidirectional"))
      (node (ref "D287") (pin "4") (pinfunction "BLU_4") (pintype "bidirectional"))
      (node (ref "D288") (pin "4") (pinfunction "BLU_4") (pintype "bidirectional"))
      (node (ref "D289") (pin "4") (pinfunction "BLU_4") (pintype "bidirectional"))
      (node (ref "D290") (pin "4") (pinfunction "BLU_4") (pintype "bidirectional"))
      (node (ref "D291") (pin "4") (pinfunction "BLU_4") (pintype "bidirectional"))
      (node (ref "D292") (pin "4") (pinfunction "BLU_4") (pintype "bidirectional"))
      (node (ref "D293") (pin "4") (pinfunction "BLU_4") (pintype "bidirectional"))
      (node (ref "D294") (pin "4") (pinfunction "BLU_4") (pintype "bidirectional"))
      (node (ref "D295") (pin "4") (pinfunction "BLU_4") (pintype "bidirectional"))
      (node (ref "D296") (pin "4") (pinfunction "BLU_4") (pintype "bidirectional"))
      (node (ref "D297") (pin "4") (pinfunction "BLU_4") (pintype "bidirectional"))
      (node (ref "D298") (pin "4") (pinfunction "BLU_4") (pintype "bidirectional"))
      (node (ref "D299") (pin "4") (pinfunction "BLU_4") (pintype "bidirectional"))
      (node (ref "D300") (pin "4") (pinfunction "BLU_4") (pintype "bidirectional"))
      (node (ref "D301") (pin "4") (pinfunction "BLU_4") (pintype "bidirectional"))
      (node (ref "D302") (pin "4") (pinfunction "BLU_4") (pintype "bidirectional"))
      (node (ref "D303") (pin "4") (pinfunction "BLU_4") (pintype "bidirectional"))
      (node (ref "D304") (pin "4") (pinfunction "BLU_4") (pintype "bidirectional"))
      (node (ref "D305") (pin "4") (pinfunction "BLU_4") (pintype "bidirectional"))
      (node (ref "D306") (pin "4") (pinfunction "BLU_4") (pintype "bidirectional"))
      (node (ref "D307") (pin "4") (pinfunction "BLU_4") (pintype "bidirectional"))
      (node (ref "D308") (pin "4") (pinfunction "BLU_4") (pintype "bidirectional"))
      (node (ref "D309") (pin "4") (pinfunction "BLU_4") (pintype "bidirectional"))
      (node (ref "D310") (pin "4") (pinfunction "BLU_4") (pintype "bidirectional"))
      (node (ref "D311") (pin "4") (pinfunction "BLU_4") (pintype "bidirectional"))
      (node (ref "D312") (pin "4") (pinfunction "BLU_4") (pintype "bidirectional"))
      (node (ref "D313") (pin "4") (pinfunction "BLU_4") (pintype "bidirectional"))
      (node (ref "D314") (pin "4") (pinfunction "BLU_4") (pintype "bidirectional"))
      (node (ref "D315") (pin "4") (pinfunction "BLU_4") (pintype "bidirectional"))
      (node (ref "D316") (pin "4") (pinfunction "BLU_4") (pintype "bidirectional"))
      (node (ref "D317") (pin "4") (pinfunction "BLU_4") (pintype "bidirectional"))
      (node (ref "D318") (pin "4") (pinfunction "BLU_4") (pintype "bidirectional"))
      (node (ref "D319") (pin "4") (pinfunction "BLU_4") (pintype "bidirectional"))
      (node (ref "D320") (pin "4") (pinfunction "BLU_4") (pintype "bidirectional"))
      (node (ref "Q14") (pin "C") (pinfunction "C_C") (pintype "passive"))
    )
    (net (code "79") (name "Net-(D257-GRN)") (class "Default")
      (node (ref "D257") (pin "3") (pinfunction "GRN_3") (pintype "bidirectional"))
      (node (ref "D258") (pin "3") (pinfunction "GRN_3") (pintype "bidirectional"))
      (node (ref "D259") (pin "3") (pinfunction "GRN_3") (pintype "bidirectional"))
      (node (ref "D260") (pin "3") (pinfunction "GRN_3") (pintype "bidirectional"))
      (node (ref "D261") (pin "3") (pinfunction "GRN_3") (pintype "bidirectional"))
      (node (ref "D262") (pin "3") (pinfunction "GRN_3") (pintype "bidirectional"))
      (node (ref "D263") (pin "3") (pinfunction "GRN_3") (pintype "bidirectional"))
      (node (ref "D264") (pin "3") (pinfunction "GRN_3") (pintype "bidirectional"))
      (node (ref "D265") (pin "3") (pinfunction "GRN_3") (pintype "bidirectional"))
      (node (ref "D266") (pin "3") (pinfunction "GRN_3") (pintype "bidirectional"))
      (node (ref "D267") (pin "3") (pinfunction "GRN_3") (pintype "bidirectional"))
      (node (ref "D268") (pin "3") (pinfunction "GRN_3") (pintype "bidirectional"))
      (node (ref "D269") (pin "3") (pinfunction "GRN_3") (pintype "bidirectional"))
      (node (ref "D270") (pin "3") (pinfunction "GRN_3") (pintype "bidirectional"))
      (node (ref "D271") (pin "3") (pinfunction "GRN_3") (pintype "bidirectional"))
      (node (ref "D272") (pin "3") (pinfunction "GRN_3") (pintype "bidirectional"))
      (node (ref "D273") (pin "3") (pinfunction "GRN_3") (pintype "bidirectional"))
      (node (ref "D274") (pin "3") (pinfunction "GRN_3") (pintype "bidirectional"))
      (node (ref "D275") (pin "3") (pinfunction "GRN_3") (pintype "bidirectional"))
      (node (ref "D276") (pin "3") (pinfunction "GRN_3") (pintype "bidirectional"))
      (node (ref "D277") (pin "3") (pinfunction "GRN_3") (pintype "bidirectional"))
      (node (ref "D278") (pin "3") (pinfunction "GRN_3") (pintype "bidirectional"))
      (node (ref "D279") (pin "3") (pinfunction "GRN_3") (pintype "bidirectional"))
      (node (ref "D280") (pin "3") (pinfunction "GRN_3") (pintype "bidirectional"))
      (node (ref "D281") (pin "3") (pinfunction "GRN_3") (pintype "bidirectional"))
      (node (ref "D282") (pin "3") (pinfunction "GRN_3") (pintype "bidirectional"))
      (node (ref "D283") (pin "3") (pinfunction "GRN_3") (pintype "bidirectional"))
      (node (ref "D284") (pin "3") (pinfunction "GRN_3") (pintype "bidirectional"))
      (node (ref "D285") (pin "3") (pinfunction "GRN_3") (pintype "bidirectional"))
      (node (ref "D286") (pin "3") (pinfunction "GRN_3") (pintype "bidirectional"))
      (node (ref "D287") (pin "3") (pinfunction "GRN_3") (pintype "bidirectional"))
      (node (ref "D288") (pin "3") (pinfunction "GRN_3") (pintype "bidirectional"))
      (node (ref "D289") (pin "3") (pinfunction "GRN_3") (pintype "bidirectional"))
      (node (ref "D290") (pin "3") (pinfunction "GRN_3") (pintype "bidirectional"))
      (node (ref "D291") (pin "3") (pinfunction "GRN_3") (pintype "bidirectional"))
      (node (ref "D292") (pin "3") (pinfunction "GRN_3") (pintype "bidirectional"))
      (node (ref "D293") (pin "3") (pinfunction "GRN_3") (pintype "bidirectional"))
      (node (ref "D294") (pin "3") (pinfunction "GRN_3") (pintype "bidirectional"))
      (node (ref "D295") (pin "3") (pinfunction "GRN_3") (pintype "bidirectional"))
      (node (ref "D296") (pin "3") (pinfunction "GRN_3") (pintype "bidirectional"))
      (node (ref "D297") (pin "3") (pinfunction "GRN_3") (pintype "bidirectional"))
      (node (ref "D298") (pin "3") (pinfunction "GRN_3") (pintype "bidirectional"))
      (node (ref "D299") (pin "3") (pinfunction "GRN_3") (pintype "bidirectional"))
      (node (ref "D300") (pin "3") (pinfunction "GRN_3") (pintype "bidirectional"))
      (node (ref "D301") (pin "3") (pinfunction "GRN_3") (pintype "bidirectional"))
      (node (ref "D302") (pin "3") (pinfunction "GRN_3") (pintype "bidirectional"))
      (node (ref "D303") (pin "3") (pinfunction "GRN_3") (pintype "bidirectional"))
      (node (ref "D304") (pin "3") (pinfunction "GRN_3") (pintype "bidirectional"))
      (node (ref "D305") (pin "3") (pinfunction "GRN_3") (pintype "bidirectional"))
      (node (ref "D306") (pin "3") (pinfunction "GRN_3") (pintype "bidirectional"))
      (node (ref "D307") (pin "3") (pinfunction "GRN_3") (pintype "bidirectional"))
      (node (ref "D308") (pin "3") (pinfunction "GRN_3") (pintype "bidirectional"))
      (node (ref "D309") (pin "3") (pinfunction "GRN_3") (pintype "bidirectional"))
      (node (ref "D310") (pin "3") (pinfunction "GRN_3") (pintype "bidirectional"))
      (node (ref "D311") (pin "3") (pinfunction "GRN_3") (pintype "bidirectional"))
      (node (ref "D312") (pin "3") (pinfunction "GRN_3") (pintype "bidirectional"))
      (node (ref "D313") (pin "3") (pinfunction "GRN_3") (pintype "bidirectional"))
      (node (ref "D314") (pin "3") (pinfunction "GRN_3") (pintype "bidirectional"))
      (node (ref "D315") (pin "3") (pinfunction "GRN_3") (pintype "bidirectional"))
      (node (ref "D316") (pin "3") (pinfunction "GRN_3") (pintype "bidirectional"))
      (node (ref "D317") (pin "3") (pinfunction "GRN_3") (pintype "bidirectional"))
      (node (ref "D318") (pin "3") (pinfunction "GRN_3") (pintype "bidirectional"))
      (node (ref "D319") (pin "3") (pinfunction "GRN_3") (pintype "bidirectional"))
      (node (ref "D320") (pin "3") (pinfunction "GRN_3") (pintype "bidirectional"))
      (node (ref "Q13") (pin "C") (pinfunction "C_C") (pintype "passive"))
    )
    (net (code "80") (name "Net-(D257-RED)") (class "Default")
      (node (ref "D257") (pin "1") (pinfunction "RED_1") (pintype "bidirectional"))
      (node (ref "D258") (pin "1") (pinfunction "RED_1") (pintype "bidirectional"))
      (node (ref "D259") (pin "1") (pinfunction "RED_1") (pintype "bidirectional"))
      (node (ref "D260") (pin "1") (pinfunction "RED_1") (pintype "bidirectional"))
      (node (ref "D261") (pin "1") (pinfunction "RED_1") (pintype "bidirectional"))
      (node (ref "D262") (pin "1") (pinfunction "RED_1") (pintype "bidirectional"))
      (node (ref "D263") (pin "1") (pinfunction "RED_1") (pintype "bidirectional"))
      (node (ref "D264") (pin "1") (pinfunction "RED_1") (pintype "bidirectional"))
      (node (ref "D265") (pin "1") (pinfunction "RED_1") (pintype "bidirectional"))
      (node (ref "D266") (pin "1") (pinfunction "RED_1") (pintype "bidirectional"))
      (node (ref "D267") (pin "1") (pinfunction "RED_1") (pintype "bidirectional"))
      (node (ref "D268") (pin "1") (pinfunction "RED_1") (pintype "bidirectional"))
      (node (ref "D269") (pin "1") (pinfunction "RED_1") (pintype "bidirectional"))
      (node (ref "D270") (pin "1") (pinfunction "RED_1") (pintype "bidirectional"))
      (node (ref "D271") (pin "1") (pinfunction "RED_1") (pintype "bidirectional"))
      (node (ref "D272") (pin "1") (pinfunction "RED_1") (pintype "bidirectional"))
      (node (ref "D273") (pin "1") (pinfunction "RED_1") (pintype "bidirectional"))
      (node (ref "D274") (pin "1") (pinfunction "RED_1") (pintype "bidirectional"))
      (node (ref "D275") (pin "1") (pinfunction "RED_1") (pintype "bidirectional"))
      (node (ref "D276") (pin "1") (pinfunction "RED_1") (pintype "bidirectional"))
      (node (ref "D277") (pin "1") (pinfunction "RED_1") (pintype "bidirectional"))
      (node (ref "D278") (pin "1") (pinfunction "RED_1") (pintype "bidirectional"))
      (node (ref "D279") (pin "1") (pinfunction "RED_1") (pintype "bidirectional"))
      (node (ref "D280") (pin "1") (pinfunction "RED_1") (pintype "bidirectional"))
      (node (ref "D281") (pin "1") (pinfunction "RED_1") (pintype "bidirectional"))
      (node (ref "D282") (pin "1") (pinfunction "RED_1") (pintype "bidirectional"))
      (node (ref "D283") (pin "1") (pinfunction "RED_1") (pintype "bidirectional"))
      (node (ref "D284") (pin "1") (pinfunction "RED_1") (pintype "bidirectional"))
      (node (ref "D285") (pin "1") (pinfunction "RED_1") (pintype "bidirectional"))
      (node (ref "D286") (pin "1") (pinfunction "RED_1") (pintype "bidirectional"))
      (node (ref "D287") (pin "1") (pinfunction "RED_1") (pintype "bidirectional"))
      (node (ref "D288") (pin "1") (pinfunction "RED_1") (pintype "bidirectional"))
      (node (ref "D289") (pin "1") (pinfunction "RED_1") (pintype "bidirectional"))
      (node (ref "D290") (pin "1") (pinfunction "RED_1") (pintype "bidirectional"))
      (node (ref "D291") (pin "1") (pinfunction "RED_1") (pintype "bidirectional"))
      (node (ref "D292") (pin "1") (pinfunction "RED_1") (pintype "bidirectional"))
      (node (ref "D293") (pin "1") (pinfunction "RED_1") (pintype "bidirectional"))
      (node (ref "D294") (pin "1") (pinfunction "RED_1") (pintype "bidirectional"))
      (node (ref "D295") (pin "1") (pinfunction "RED_1") (pintype "bidirectional"))
      (node (ref "D296") (pin "1") (pinfunction "RED_1") (pintype "bidirectional"))
      (node (ref "D297") (pin "1") (pinfunction "RED_1") (pintype "bidirectional"))
      (node (ref "D298") (pin "1") (pinfunction "RED_1") (pintype "bidirectional"))
      (node (ref "D299") (pin "1") (pinfunction "RED_1") (pintype "bidirectional"))
      (node (ref "D300") (pin "1") (pinfunction "RED_1") (pintype "bidirectional"))
      (node (ref "D301") (pin "1") (pinfunction "RED_1") (pintype "bidirectional"))
      (node (ref "D302") (pin "1") (pinfunction "RED_1") (pintype "bidirectional"))
      (node (ref "D303") (pin "1") (pinfunction "RED_1") (pintype "bidirectional"))
      (node (ref "D304") (pin "1") (pinfunction "RED_1") (pintype "bidirectional"))
      (node (ref "D305") (pin "1") (pinfunction "RED_1") (pintype "bidirectional"))
      (node (ref "D306") (pin "1") (pinfunction "RED_1") (pintype "bidirectional"))
      (node (ref "D307") (pin "1") (pinfunction "RED_1") (pintype "bidirectional"))
      (node (ref "D308") (pin "1") (pinfunction "RED_1") (pintype "bidirectional"))
      (node (ref "D309") (pin "1") (pinfunction "RED_1") (pintype "bidirectional"))
      (node (ref "D310") (pin "1") (pinfunction "RED_1") (pintype "bidirectional"))
      (node (ref "D311") (pin "1") (pinfunction "RED_1") (pintype "bidirectional"))
      (node (ref "D312") (pin "1") (pinfunction "RED_1") (pintype "bidirectional"))
      (node (ref "D313") (pin "1") (pinfunction "RED_1") (pintype "bidirectional"))
      (node (ref "D314") (pin "1") (pinfunction "RED_1") (pintype "bidirectional"))
      (node (ref "D315") (pin "1") (pinfunction "RED_1") (pintype "bidirectional"))
      (node (ref "D316") (pin "1") (pinfunction "RED_1") (pintype "bidirectional"))
      (node (ref "D317") (pin "1") (pinfunction "RED_1") (pintype "bidirectional"))
      (node (ref "D318") (pin "1") (pinfunction "RED_1") (pintype "bidirectional"))
      (node (ref "D319") (pin "1") (pinfunction "RED_1") (pintype "bidirectional"))
      (node (ref "D320") (pin "1") (pinfunction "RED_1") (pintype "bidirectional"))
      (node (ref "Q15") (pin "C") (pinfunction "C_C") (pintype "passive"))
    )
    (net (code "81") (name "Net-(D321-BLU)") (class "Default")
      (node (ref "D321") (pin "4") (pinfunction "BLU_4") (pintype "bidirectional"))
      (node (ref "D322") (pin "4") (pinfunction "BLU_4") (pintype "bidirectional"))
      (node (ref "D323") (pin "4") (pinfunction "BLU_4") (pintype "bidirectional"))
      (node (ref "D324") (pin "4") (pinfunction "BLU_4") (pintype "bidirectional"))
      (node (ref "D325") (pin "4") (pinfunction "BLU_4") (pintype "bidirectional"))
      (node (ref "D326") (pin "4") (pinfunction "BLU_4") (pintype "bidirectional"))
      (node (ref "D327") (pin "4") (pinfunction "BLU_4") (pintype "bidirectional"))
      (node (ref "D328") (pin "4") (pinfunction "BLU_4") (pintype "bidirectional"))
      (node (ref "D329") (pin "4") (pinfunction "BLU_4") (pintype "bidirectional"))
      (node (ref "D330") (pin "4") (pinfunction "BLU_4") (pintype "bidirectional"))
      (node (ref "D331") (pin "4") (pinfunction "BLU_4") (pintype "bidirectional"))
      (node (ref "D332") (pin "4") (pinfunction "BLU_4") (pintype "bidirectional"))
      (node (ref "D333") (pin "4") (pinfunction "BLU_4") (pintype "bidirectional"))
      (node (ref "D334") (pin "4") (pinfunction "BLU_4") (pintype "bidirectional"))
      (node (ref "D335") (pin "4") (pinfunction "BLU_4") (pintype "bidirectional"))
      (node (ref "D336") (pin "4") (pinfunction "BLU_4") (pintype "bidirectional"))
      (node (ref "D337") (pin "4") (pinfunction "BLU_4") (pintype "bidirectional"))
      (node (ref "D338") (pin "4") (pinfunction "BLU_4") (pintype "bidirectional"))
      (node (ref "D339") (pin "4") (pinfunction "BLU_4") (pintype "bidirectional"))
      (node (ref "D340") (pin "4") (pinfunction "BLU_4") (pintype "bidirectional"))
      (node (ref "D341") (pin "4") (pinfunction "BLU_4") (pintype "bidirectional"))
      (node (ref "D342") (pin "4") (pinfunction "BLU_4") (pintype "bidirectional"))
      (node (ref "D343") (pin "4") (pinfunction "BLU_4") (pintype "bidirectional"))
      (node (ref "D344") (pin "4") (pinfunction "BLU_4") (pintype "bidirectional"))
      (node (ref "D345") (pin "4") (pinfunction "BLU_4") (pintype "bidirectional"))
      (node (ref "D346") (pin "4") (pinfunction "BLU_4") (pintype "bidirectional"))
      (node (ref "D347") (pin "4") (pinfunction "BLU_4") (pintype "bidirectional"))
      (node (ref "D348") (pin "4") (pinfunction "BLU_4") (pintype "bidirectional"))
      (node (ref "D349") (pin "4") (pinfunction "BLU_4") (pintype "bidirectional"))
      (node (ref "D350") (pin "4") (pinfunction "BLU_4") (pintype "bidirectional"))
      (node (ref "D351") (pin "4") (pinfunction "BLU_4") (pintype "bidirectional"))
      (node (ref "D352") (pin "4") (pinfunction "BLU_4") (pintype "bidirectional"))
      (node (ref "D353") (pin "4") (pinfunction "BLU_4") (pintype "bidirectional"))
      (node (ref "D354") (pin "4") (pinfunction "BLU_4") (pintype "bidirectional"))
      (node (ref "D355") (pin "4") (pinfunction "BLU_4") (pintype "bidirectional"))
      (node (ref "D356") (pin "4") (pinfunction "BLU_4") (pintype "bidirectional"))
      (node (ref "D357") (pin "4") (pinfunction "BLU_4") (pintype "bidirectional"))
      (node (ref "D358") (pin "4") (pinfunction "BLU_4") (pintype "bidirectional"))
      (node (ref "D359") (pin "4") (pinfunction "BLU_4") (pintype "bidirectional"))
      (node (ref "D360") (pin "4") (pinfunction "BLU_4") (pintype "bidirectional"))
      (node (ref "D361") (pin "4") (pinfunction "BLU_4") (pintype "bidirectional"))
      (node (ref "D362") (pin "4") (pinfunction "BLU_4") (pintype "bidirectional"))
      (node (ref "D363") (pin "4") (pinfunction "BLU_4") (pintype "bidirectional"))
      (node (ref "D364") (pin "4") (pinfunction "BLU_4") (pintype "bidirectional"))
      (node (ref "D365") (pin "4") (pinfunction "BLU_4") (pintype "bidirectional"))
      (node (ref "D366") (pin "4") (pinfunction "BLU_4") (pintype "bidirectional"))
      (node (ref "D367") (pin "4") (pinfunction "BLU_4") (pintype "bidirectional"))
      (node (ref "D368") (pin "4") (pinfunction "BLU_4") (pintype "bidirectional"))
      (node (ref "D369") (pin "4") (pinfunction "BLU_4") (pintype "bidirectional"))
      (node (ref "D370") (pin "4") (pinfunction "BLU_4") (pintype "bidirectional"))
      (node (ref "D371") (pin "4") (pinfunction "BLU_4") (pintype "bidirectional"))
      (node (ref "D372") (pin "4") (pinfunction "BLU_4") (pintype "bidirectional"))
      (node (ref "D373") (pin "4") (pinfunction "BLU_4") (pintype "bidirectional"))
      (node (ref "D374") (pin "4") (pinfunction "BLU_4") (pintype "bidirectional"))
      (node (ref "D375") (pin "4") (pinfunction "BLU_4") (pintype "bidirectional"))
      (node (ref "D376") (pin "4") (pinfunction "BLU_4") (pintype "bidirectional"))
      (node (ref "D377") (pin "4") (pinfunction "BLU_4") (pintype "bidirectional"))
      (node (ref "D378") (pin "4") (pinfunction "BLU_4") (pintype "bidirectional"))
      (node (ref "D379") (pin "4") (pinfunction "BLU_4") (pintype "bidirectional"))
      (node (ref "D380") (pin "4") (pinfunction "BLU_4") (pintype "bidirectional"))
      (node (ref "D381") (pin "4") (pinfunction "BLU_4") (pintype "bidirectional"))
      (node (ref "D382") (pin "4") (pinfunction "BLU_4") (pintype "bidirectional"))
      (node (ref "D383") (pin "4") (pinfunction "BLU_4") (pintype "bidirectional"))
      (node (ref "D384") (pin "4") (pinfunction "BLU_4") (pintype "bidirectional"))
      (node (ref "Q17") (pin "C") (pinfunction "C_C") (pintype "passive"))
    )
    (net (code "82") (name "Net-(D321-GRN)") (class "Default")
      (node (ref "D321") (pin "3") (pinfunction "GRN_3") (pintype "bidirectional"))
      (node (ref "D322") (pin "3") (pinfunction "GRN_3") (pintype "bidirectional"))
      (node (ref "D323") (pin "3") (pinfunction "GRN_3") (pintype "bidirectional"))
      (node (ref "D324") (pin "3") (pinfunction "GRN_3") (pintype "bidirectional"))
      (node (ref "D325") (pin "3") (pinfunction "GRN_3") (pintype "bidirectional"))
      (node (ref "D326") (pin "3") (pinfunction "GRN_3") (pintype "bidirectional"))
      (node (ref "D327") (pin "3") (pinfunction "GRN_3") (pintype "bidirectional"))
      (node (ref "D328") (pin "3") (pinfunction "GRN_3") (pintype "bidirectional"))
      (node (ref "D329") (pin "3") (pinfunction "GRN_3") (pintype "bidirectional"))
      (node (ref "D330") (pin "3") (pinfunction "GRN_3") (pintype "bidirectional"))
      (node (ref "D331") (pin "3") (pinfunction "GRN_3") (pintype "bidirectional"))
      (node (ref "D332") (pin "3") (pinfunction "GRN_3") (pintype "bidirectional"))
      (node (ref "D333") (pin "3") (pinfunction "GRN_3") (pintype "bidirectional"))
      (node (ref "D334") (pin "3") (pinfunction "GRN_3") (pintype "bidirectional"))
      (node (ref "D335") (pin "3") (pinfunction "GRN_3") (pintype "bidirectional"))
      (node (ref "D336") (pin "3") (pinfunction "GRN_3") (pintype "bidirectional"))
      (node (ref "D337") (pin "3") (pinfunction "GRN_3") (pintype "bidirectional"))
      (node (ref "D338") (pin "3") (pinfunction "GRN_3") (pintype "bidirectional"))
      (node (ref "D339") (pin "3") (pinfunction "GRN_3") (pintype "bidirectional"))
      (node (ref "D340") (pin "3") (pinfunction "GRN_3") (pintype "bidirectional"))
      (node (ref "D341") (pin "3") (pinfunction "GRN_3") (pintype "bidirectional"))
      (node (ref "D342") (pin "3") (pinfunction "GRN_3") (pintype "bidirectional"))
      (node (ref "D343") (pin "3") (pinfunction "GRN_3") (pintype "bidirectional"))
      (node (ref "D344") (pin "3") (pinfunction "GRN_3") (pintype "bidirectional"))
      (node (ref "D345") (pin "3") (pinfunction "GRN_3") (pintype "bidirectional"))
      (node (ref "D346") (pin "3") (pinfunction "GRN_3") (pintype "bidirectional"))
      (node (ref "D347") (pin "3") (pinfunction "GRN_3") (pintype "bidirectional"))
      (node (ref "D348") (pin "3") (pinfunction "GRN_3") (pintype "bidirectional"))
      (node (ref "D349") (pin "3") (pinfunction "GRN_3") (pintype "bidirectional"))
      (node (ref "D350") (pin "3") (pinfunction "GRN_3") (pintype "bidirectional"))
      (node (ref "D351") (pin "3") (pinfunction "GRN_3") (pintype "bidirectional"))
      (node (ref "D352") (pin "3") (pinfunction "GRN_3") (pintype "bidirectional"))
      (node (ref "D353") (pin "3") (pinfunction "GRN_3") (pintype "bidirectional"))
      (node (ref "D354") (pin "3") (pinfunction "GRN_3") (pintype "bidirectional"))
      (node (ref "D355") (pin "3") (pinfunction "GRN_3") (pintype "bidirectional"))
      (node (ref "D356") (pin "3") (pinfunction "GRN_3") (pintype "bidirectional"))
      (node (ref "D357") (pin "3") (pinfunction "GRN_3") (pintype "bidirectional"))
      (node (ref "D358") (pin "3") (pinfunction "GRN_3") (pintype "bidirectional"))
      (node (ref "D359") (pin "3") (pinfunction "GRN_3") (pintype "bidirectional"))
      (node (ref "D360") (pin "3") (pinfunction "GRN_3") (pintype "bidirectional"))
      (node (ref "D361") (pin "3") (pinfunction "GRN_3") (pintype "bidirectional"))
      (node (ref "D362") (pin "3") (pinfunction "GRN_3") (pintype "bidirectional"))
      (node (ref "D363") (pin "3") (pinfunction "GRN_3") (pintype "bidirectional"))
      (node (ref "D364") (pin "3") (pinfunction "GRN_3") (pintype "bidirectional"))
      (node (ref "D365") (pin "3") (pinfunction "GRN_3") (pintype "bidirectional"))
      (node (ref "D366") (pin "3") (pinfunction "GRN_3") (pintype "bidirectional"))
      (node (ref "D367") (pin "3") (pinfunction "GRN_3") (pintype "bidirectional"))
      (node (ref "D368") (pin "3") (pinfunction "GRN_3") (pintype "bidirectional"))
      (node (ref "D369") (pin "3") (pinfunction "GRN_3") (pintype "bidirectional"))
      (node (ref "D370") (pin "3") (pinfunction "GRN_3") (pintype "bidirectional"))
      (node (ref "D371") (pin "3") (pinfunction "GRN_3") (pintype "bidirectional"))
      (node (ref "D372") (pin "3") (pinfunction "GRN_3") (pintype "bidirectional"))
      (node (ref "D373") (pin "3") (pinfunction "GRN_3") (pintype "bidirectional"))
      (node (ref "D374") (pin "3") (pinfunction "GRN_3") (pintype "bidirectional"))
      (node (ref "D375") (pin "3") (pinfunction "GRN_3") (pintype "bidirectional"))
      (node (ref "D376") (pin "3") (pinfunction "GRN_3") (pintype "bidirectional"))
      (node (ref "D377") (pin "3") (pinfunction "GRN_3") (pintype "bidirectional"))
      (node (ref "D378") (pin "3") (pinfunction "GRN_3") (pintype "bidirectional"))
      (node (ref "D379") (pin "3") (pinfunction "GRN_3") (pintype "bidirectional"))
      (node (ref "D380") (pin "3") (pinfunction "GRN_3") (pintype "bidirectional"))
      (node (ref "D381") (pin "3") (pinfunction "GRN_3") (pintype "bidirectional"))
      (node (ref "D382") (pin "3") (pinfunction "GRN_3") (pintype "bidirectional"))
      (node (ref "D383") (pin "3") (pinfunction "GRN_3") (pintype "bidirectional"))
      (node (ref "D384") (pin "3") (pinfunction "GRN_3") (pintype "bidirectional"))
      (node (ref "Q16") (pin "C") (pinfunction "C_C") (pintype "passive"))
    )
    (net (code "83") (name "Net-(D321-RED)") (class "Default")
      (node (ref "D321") (pin "1") (pinfunction "RED_1") (pintype "bidirectional"))
      (node (ref "D322") (pin "1") (pinfunction "RED_1") (pintype "bidirectional"))
      (node (ref "D323") (pin "1") (pinfunction "RED_1") (pintype "bidirectional"))
      (node (ref "D324") (pin "1") (pinfunction "RED_1") (pintype "bidirectional"))
      (node (ref "D325") (pin "1") (pinfunction "RED_1") (pintype "bidirectional"))
      (node (ref "D326") (pin "1") (pinfunction "RED_1") (pintype "bidirectional"))
      (node (ref "D327") (pin "1") (pinfunction "RED_1") (pintype "bidirectional"))
      (node (ref "D328") (pin "1") (pinfunction "RED_1") (pintype "bidirectional"))
      (node (ref "D329") (pin "1") (pinfunction "RED_1") (pintype "bidirectional"))
      (node (ref "D330") (pin "1") (pinfunction "RED_1") (pintype "bidirectional"))
      (node (ref "D331") (pin "1") (pinfunction "RED_1") (pintype "bidirectional"))
      (node (ref "D332") (pin "1") (pinfunction "RED_1") (pintype "bidirectional"))
      (node (ref "D333") (pin "1") (pinfunction "RED_1") (pintype "bidirectional"))
      (node (ref "D334") (pin "1") (pinfunction "RED_1") (pintype "bidirectional"))
      (node (ref "D335") (pin "1") (pinfunction "RED_1") (pintype "bidirectional"))
      (node (ref "D336") (pin "1") (pinfunction "RED_1") (pintype "bidirectional"))
      (node (ref "D337") (pin "1") (pinfunction "RED_1") (pintype "bidirectional"))
      (node (ref "D338") (pin "1") (pinfunction "RED_1") (pintype "bidirectional"))
      (node (ref "D339") (pin "1") (pinfunction "RED_1") (pintype "bidirectional"))
      (node (ref "D340") (pin "1") (pinfunction "RED_1") (pintype "bidirectional"))
      (node (ref "D341") (pin "1") (pinfunction "RED_1") (pintype "bidirectional"))
      (node (ref "D342") (pin "1") (pinfunction "RED_1") (pintype "bidirectional"))
      (node (ref "D343") (pin "1") (pinfunction "RED_1") (pintype "bidirectional"))
      (node (ref "D344") (pin "1") (pinfunction "RED_1") (pintype "bidirectional"))
      (node (ref "D345") (pin "1") (pinfunction "RED_1") (pintype "bidirectional"))
      (node (ref "D346") (pin "1") (pinfunction "RED_1") (pintype "bidirectional"))
      (node (ref "D347") (pin "1") (pinfunction "RED_1") (pintype "bidirectional"))
      (node (ref "D348") (pin "1") (pinfunction "RED_1") (pintype "bidirectional"))
      (node (ref "D349") (pin "1") (pinfunction "RED_1") (pintype "bidirectional"))
      (node (ref "D350") (pin "1") (pinfunction "RED_1") (pintype "bidirectional"))
      (node (ref "D351") (pin "1") (pinfunction "RED_1") (pintype "bidirectional"))
      (node (ref "D352") (pin "1") (pinfunction "RED_1") (pintype "bidirectional"))
      (node (ref "D353") (pin "1") (pinfunction "RED_1") (pintype "bidirectional"))
      (node (ref "D354") (pin "1") (pinfunction "RED_1") (pintype "bidirectional"))
      (node (ref "D355") (pin "1") (pinfunction "RED_1") (pintype "bidirectional"))
      (node (ref "D356") (pin "1") (pinfunction "RED_1") (pintype "bidirectional"))
      (node (ref "D357") (pin "1") (pinfunction "RED_1") (pintype "bidirectional"))
      (node (ref "D358") (pin "1") (pinfunction "RED_1") (pintype "bidirectional"))
      (node (ref "D359") (pin "1") (pinfunction "RED_1") (pintype "bidirectional"))
      (node (ref "D360") (pin "1") (pinfunction "RED_1") (pintype "bidirectional"))
      (node (ref "D361") (pin "1") (pinfunction "RED_1") (pintype "bidirectional"))
      (node (ref "D362") (pin "1") (pinfunction "RED_1") (pintype "bidirectional"))
      (node (ref "D363") (pin "1") (pinfunction "RED_1") (pintype "bidirectional"))
      (node (ref "D364") (pin "1") (pinfunction "RED_1") (pintype "bidirectional"))
      (node (ref "D365") (pin "1") (pinfunction "RED_1") (pintype "bidirectional"))
      (node (ref "D366") (pin "1") (pinfunction "RED_1") (pintype "bidirectional"))
      (node (ref "D367") (pin "1") (pinfunction "RED_1") (pintype "bidirectional"))
      (node (ref "D368") (pin "1") (pinfunction "RED_1") (pintype "bidirectional"))
      (node (ref "D369") (pin "1") (pinfunction "RED_1") (pintype "bidirectional"))
      (node (ref "D370") (pin "1") (pinfunction "RED_1") (pintype "bidirectional"))
      (node (ref "D371") (pin "1") (pinfunction "RED_1") (pintype "bidirectional"))
      (node (ref "D372") (pin "1") (pinfunction "RED_1") (pintype "bidirectional"))
      (node (ref "D373") (pin "1") (pinfunction "RED_1") (pintype "bidirectional"))
      (node (ref "D374") (pin "1") (pinfunction "RED_1") (pintype "bidirectional"))
      (node (ref "D375") (pin "1") (pinfunction "RED_1") (pintype "bidirectional"))
      (node (ref "D376") (pin "1") (pinfunction "RED_1") (pintype "bidirectional"))
      (node (ref "D377") (pin "1") (pinfunction "RED_1") (pintype "bidirectional"))
      (node (ref "D378") (pin "1") (pinfunction "RED_1") (pintype "bidirectional"))
      (node (ref "D379") (pin "1") (pinfunction "RED_1") (pintype "bidirectional"))
      (node (ref "D380") (pin "1") (pinfunction "RED_1") (pintype "bidirectional"))
      (node (ref "D381") (pin "1") (pinfunction "RED_1") (pintype "bidirectional"))
      (node (ref "D382") (pin "1") (pinfunction "RED_1") (pintype "bidirectional"))
      (node (ref "D383") (pin "1") (pinfunction "RED_1") (pintype "bidirectional"))
      (node (ref "D384") (pin "1") (pinfunction "RED_1") (pintype "bidirectional"))
      (node (ref "Q18") (pin "C") (pinfunction "C_C") (pintype "passive"))
    )
    (net (code "84") (name "Net-(D385-BLU)") (class "Default")
      (node (ref "D385") (pin "4") (pinfunction "BLU_4") (pintype "bidirectional"))
      (node (ref "D386") (pin "4") (pinfunction "BLU_4") (pintype "bidirectional"))
      (node (ref "D387") (pin "4") (pinfunction "BLU_4") (pintype "bidirectional"))
      (node (ref "D388") (pin "4") (pinfunction "BLU_4") (pintype "bidirectional"))
      (node (ref "D389") (pin "4") (pinfunction "BLU_4") (pintype "bidirectional"))
      (node (ref "D390") (pin "4") (pinfunction "BLU_4") (pintype "bidirectional"))
      (node (ref "D391") (pin "4") (pinfunction "BLU_4") (pintype "bidirectional"))
      (node (ref "D392") (pin "4") (pinfunction "BLU_4") (pintype "bidirectional"))
      (node (ref "D393") (pin "4") (pinfunction "BLU_4") (pintype "bidirectional"))
      (node (ref "D394") (pin "4") (pinfunction "BLU_4") (pintype "bidirectional"))
      (node (ref "D395") (pin "4") (pinfunction "BLU_4") (pintype "bidirectional"))
      (node (ref "D396") (pin "4") (pinfunction "BLU_4") (pintype "bidirectional"))
      (node (ref "D397") (pin "4") (pinfunction "BLU_4") (pintype "bidirectional"))
      (node (ref "D398") (pin "4") (pinfunction "BLU_4") (pintype "bidirectional"))
      (node (ref "D399") (pin "4") (pinfunction "BLU_4") (pintype "bidirectional"))
      (node (ref "D400") (pin "4") (pinfunction "BLU_4") (pintype "bidirectional"))
      (node (ref "D401") (pin "4") (pinfunction "BLU_4") (pintype "bidirectional"))
      (node (ref "D402") (pin "4") (pinfunction "BLU_4") (pintype "bidirectional"))
      (node (ref "D403") (pin "4") (pinfunction "BLU_4") (pintype "bidirectional"))
      (node (ref "D404") (pin "4") (pinfunction "BLU_4") (pintype "bidirectional"))
      (node (ref "D405") (pin "4") (pinfunction "BLU_4") (pintype "bidirectional"))
      (node (ref "D406") (pin "4") (pinfunction "BLU_4") (pintype "bidirectional"))
      (node (ref "D407") (pin "4") (pinfunction "BLU_4") (pintype "bidirectional"))
      (node (ref "D408") (pin "4") (pinfunction "BLU_4") (pintype "bidirectional"))
      (node (ref "D409") (pin "4") (pinfunction "BLU_4") (pintype "bidirectional"))
      (node (ref "D410") (pin "4") (pinfunction "BLU_4") (pintype "bidirectional"))
      (node (ref "D411") (pin "4") (pinfunction "BLU_4") (pintype "bidirectional"))
      (node (ref "D412") (pin "4") (pinfunction "BLU_4") (pintype "bidirectional"))
      (node (ref "D413") (pin "4") (pinfunction "BLU_4") (pintype "bidirectional"))
      (node (ref "D414") (pin "4") (pinfunction "BLU_4") (pintype "bidirectional"))
      (node (ref "D415") (pin "4") (pinfunction "BLU_4") (pintype "bidirectional"))
      (node (ref "D416") (pin "4") (pinfunction "BLU_4") (pintype "bidirectional"))
      (node (ref "D417") (pin "4") (pinfunction "BLU_4") (pintype "bidirectional"))
      (node (ref "D418") (pin "4") (pinfunction "BLU_4") (pintype "bidirectional"))
      (node (ref "D419") (pin "4") (pinfunction "BLU_4") (pintype "bidirectional"))
      (node (ref "D420") (pin "4") (pinfunction "BLU_4") (pintype "bidirectional"))
      (node (ref "D421") (pin "4") (pinfunction "BLU_4") (pintype "bidirectional"))
      (node (ref "D422") (pin "4") (pinfunction "BLU_4") (pintype "bidirectional"))
      (node (ref "D423") (pin "4") (pinfunction "BLU_4") (pintype "bidirectional"))
      (node (ref "D424") (pin "4") (pinfunction "BLU_4") (pintype "bidirectional"))
      (node (ref "D425") (pin "4") (pinfunction "BLU_4") (pintype "bidirectional"))
      (node (ref "D426") (pin "4") (pinfunction "BLU_4") (pintype "bidirectional"))
      (node (ref "D427") (pin "4") (pinfunction "BLU_4") (pintype "bidirectional"))
      (node (ref "D428") (pin "4") (pinfunction "BLU_4") (pintype "bidirectional"))
      (node (ref "D429") (pin "4") (pinfunction "BLU_4") (pintype "bidirectional"))
      (node (ref "D430") (pin "4") (pinfunction "BLU_4") (pintype "bidirectional"))
      (node (ref "D431") (pin "4") (pinfunction "BLU_4") (pintype "bidirectional"))
      (node (ref "D432") (pin "4") (pinfunction "BLU_4") (pintype "bidirectional"))
      (node (ref "D433") (pin "4") (pinfunction "BLU_4") (pintype "bidirectional"))
      (node (ref "D434") (pin "4") (pinfunction "BLU_4") (pintype "bidirectional"))
      (node (ref "D435") (pin "4") (pinfunction "BLU_4") (pintype "bidirectional"))
      (node (ref "D436") (pin "4") (pinfunction "BLU_4") (pintype "bidirectional"))
      (node (ref "D437") (pin "4") (pinfunction "BLU_4") (pintype "bidirectional"))
      (node (ref "D438") (pin "4") (pinfunction "BLU_4") (pintype "bidirectional"))
      (node (ref "D439") (pin "4") (pinfunction "BLU_4") (pintype "bidirectional"))
      (node (ref "D440") (pin "4") (pinfunction "BLU_4") (pintype "bidirectional"))
      (node (ref "D441") (pin "4") (pinfunction "BLU_4") (pintype "bidirectional"))
      (node (ref "D442") (pin "4") (pinfunction "BLU_4") (pintype "bidirectional"))
      (node (ref "D443") (pin "4") (pinfunction "BLU_4") (pintype "bidirectional"))
      (node (ref "D444") (pin "4") (pinfunction "BLU_4") (pintype "bidirectional"))
      (node (ref "D445") (pin "4") (pinfunction "BLU_4") (pintype "bidirectional"))
      (node (ref "D446") (pin "4") (pinfunction "BLU_4") (pintype "bidirectional"))
      (node (ref "D447") (pin "4") (pinfunction "BLU_4") (pintype "bidirectional"))
      (node (ref "D448") (pin "4") (pinfunction "BLU_4") (pintype "bidirectional"))
      (node (ref "Q20") (pin "C") (pinfunction "C_C") (pintype "passive"))
    )
    (net (code "85") (name "Net-(D385-GRN)") (class "Default")
      (node (ref "D385") (pin "3") (pinfunction "GRN_3") (pintype "bidirectional"))
      (node (ref "D386") (pin "3") (pinfunction "GRN_3") (pintype "bidirectional"))
      (node (ref "D387") (pin "3") (pinfunction "GRN_3") (pintype "bidirectional"))
      (node (ref "D388") (pin "3") (pinfunction "GRN_3") (pintype "bidirectional"))
      (node (ref "D389") (pin "3") (pinfunction "GRN_3") (pintype "bidirectional"))
      (node (ref "D390") (pin "3") (pinfunction "GRN_3") (pintype "bidirectional"))
      (node (ref "D391") (pin "3") (pinfunction "GRN_3") (pintype "bidirectional"))
      (node (ref "D392") (pin "3") (pinfunction "GRN_3") (pintype "bidirectional"))
      (node (ref "D393") (pin "3") (pinfunction "GRN_3") (pintype "bidirectional"))
      (node (ref "D394") (pin "3") (pinfunction "GRN_3") (pintype "bidirectional"))
      (node (ref "D395") (pin "3") (pinfunction "GRN_3") (pintype "bidirectional"))
      (node (ref "D396") (pin "3") (pinfunction "GRN_3") (pintype "bidirectional"))
      (node (ref "D397") (pin "3") (pinfunction "GRN_3") (pintype "bidirectional"))
      (node (ref "D398") (pin "3") (pinfunction "GRN_3") (pintype "bidirectional"))
      (node (ref "D399") (pin "3") (pinfunction "GRN_3") (pintype "bidirectional"))
      (node (ref "D400") (pin "3") (pinfunction "GRN_3") (pintype "bidirectional"))
      (node (ref "D401") (pin "3") (pinfunction "GRN_3") (pintype "bidirectional"))
      (node (ref "D402") (pin "3") (pinfunction "GRN_3") (pintype "bidirectional"))
      (node (ref "D403") (pin "3") (pinfunction "GRN_3") (pintype "bidirectional"))
      (node (ref "D404") (pin "3") (pinfunction "GRN_3") (pintype "bidirectional"))
      (node (ref "D405") (pin "3") (pinfunction "GRN_3") (pintype "bidirectional"))
      (node (ref "D406") (pin "3") (pinfunction "GRN_3") (pintype "bidirectional"))
      (node (ref "D407") (pin "3") (pinfunction "GRN_3") (pintype "bidirectional"))
      (node (ref "D408") (pin "3") (pinfunction "GRN_3") (pintype "bidirectional"))
      (node (ref "D409") (pin "3") (pinfunction "GRN_3") (pintype "bidirectional"))
      (node (ref "D410") (pin "3") (pinfunction "GRN_3") (pintype "bidirectional"))
      (node (ref "D411") (pin "3") (pinfunction "GRN_3") (pintype "bidirectional"))
      (node (ref "D412") (pin "3") (pinfunction "GRN_3") (pintype "bidirectional"))
      (node (ref "D413") (pin "3") (pinfunction "GRN_3") (pintype "bidirectional"))
      (node (ref "D414") (pin "3") (pinfunction "GRN_3") (pintype "bidirectional"))
      (node (ref "D415") (pin "3") (pinfunction "GRN_3") (pintype "bidirectional"))
      (node (ref "D416") (pin "3") (pinfunction "GRN_3") (pintype "bidirectional"))
      (node (ref "D417") (pin "3") (pinfunction "GRN_3") (pintype "bidirectional"))
      (node (ref "D418") (pin "3") (pinfunction "GRN_3") (pintype "bidirectional"))
      (node (ref "D419") (pin "3") (pinfunction "GRN_3") (pintype "bidirectional"))
      (node (ref "D420") (pin "3") (pinfunction "GRN_3") (pintype "bidirectional"))
      (node (ref "D421") (pin "3") (pinfunction "GRN_3") (pintype "bidirectional"))
      (node (ref "D422") (pin "3") (pinfunction "GRN_3") (pintype "bidirectional"))
      (node (ref "D423") (pin "3") (pinfunction "GRN_3") (pintype "bidirectional"))
      (node (ref "D424") (pin "3") (pinfunction "GRN_3") (pintype "bidirectional"))
      (node (ref "D425") (pin "3") (pinfunction "GRN_3") (pintype "bidirectional"))
      (node (ref "D426") (pin "3") (pinfunction "GRN_3") (pintype "bidirectional"))
      (node (ref "D427") (pin "3") (pinfunction "GRN_3") (pintype "bidirectional"))
      (node (ref "D428") (pin "3") (pinfunction "GRN_3") (pintype "bidirectional"))
      (node (ref "D429") (pin "3") (pinfunction "GRN_3") (pintype "bidirectional"))
      (node (ref "D430") (pin "3") (pinfunction "GRN_3") (pintype "bidirectional"))
      (node (ref "D431") (pin "3") (pinfunction "GRN_3") (pintype "bidirectional"))
      (node (ref "D432") (pin "3") (pinfunction "GRN_3") (pintype "bidirectional"))
      (node (ref "D433") (pin "3") (pinfunction "GRN_3") (pintype "bidirectional"))
      (node (ref "D434") (pin "3") (pinfunction "GRN_3") (pintype "bidirectional"))
      (node (ref "D435") (pin "3") (pinfunction "GRN_3") (pintype "bidirectional"))
      (node (ref "D436") (pin "3") (pinfunction "GRN_3") (pintype "bidirectional"))
      (node (ref "D437") (pin "3") (pinfunction "GRN_3") (pintype "bidirectional"))
      (node (ref "D438") (pin "3") (pinfunction "GRN_3") (pintype "bidirectional"))
      (node (ref "D439") (pin "3") (pinfunction "GRN_3") (pintype "bidirectional"))
      (node (ref "D440") (pin "3") (pinfunction "GRN_3") (pintype "bidirectional"))
      (node (ref "D441") (pin "3") (pinfunction "GRN_3") (pintype "bidirectional"))
      (node (ref "D442") (pin "3") (pinfunction "GRN_3") (pintype "bidirectional"))
      (node (ref "D443") (pin "3") (pinfunction "GRN_3") (pintype "bidirectional"))
      (node (ref "D444") (pin "3") (pinfunction "GRN_3") (pintype "bidirectional"))
      (node (ref "D445") (pin "3") (pinfunction "GRN_3") (pintype "bidirectional"))
      (node (ref "D446") (pin "3") (pinfunction "GRN_3") (pintype "bidirectional"))
      (node (ref "D447") (pin "3") (pinfunction "GRN_3") (pintype "bidirectional"))
      (node (ref "D448") (pin "3") (pinfunction "GRN_3") (pintype "bidirectional"))
      (node (ref "Q19") (pin "C") (pinfunction "C_C") (pintype "passive"))
    )
    (net (code "86") (name "Net-(D385-RED)") (class "Default")
      (node (ref "D385") (pin "1") (pinfunction "RED_1") (pintype "bidirectional"))
      (node (ref "D386") (pin "1") (pinfunction "RED_1") (pintype "bidirectional"))
      (node (ref "D387") (pin "1") (pinfunction "RED_1") (pintype "bidirectional"))
      (node (ref "D388") (pin "1") (pinfunction "RED_1") (pintype "bidirectional"))
      (node (ref "D389") (pin "1") (pinfunction "RED_1") (pintype "bidirectional"))
      (node (ref "D390") (pin "1") (pinfunction "RED_1") (pintype "bidirectional"))
      (node (ref "D391") (pin "1") (pinfunction "RED_1") (pintype "bidirectional"))
      (node (ref "D392") (pin "1") (pinfunction "RED_1") (pintype "bidirectional"))
      (node (ref "D393") (pin "1") (pinfunction "RED_1") (pintype "bidirectional"))
      (node (ref "D394") (pin "1") (pinfunction "RED_1") (pintype "bidirectional"))
      (node (ref "D395") (pin "1") (pinfunction "RED_1") (pintype "bidirectional"))
      (node (ref "D396") (pin "1") (pinfunction "RED_1") (pintype "bidirectional"))
      (node (ref "D397") (pin "1") (pinfunction "RED_1") (pintype "bidirectional"))
      (node (ref "D398") (pin "1") (pinfunction "RED_1") (pintype "bidirectional"))
      (node (ref "D399") (pin "1") (pinfunction "RED_1") (pintype "bidirectional"))
      (node (ref "D400") (pin "1") (pinfunction "RED_1") (pintype "bidirectional"))
      (node (ref "D401") (pin "1") (pinfunction "RED_1") (pintype "bidirectional"))
      (node (ref "D402") (pin "1") (pinfunction "RED_1") (pintype "bidirectional"))
      (node (ref "D403") (pin "1") (pinfunction "RED_1") (pintype "bidirectional"))
      (node (ref "D404") (pin "1") (pinfunction "RED_1") (pintype "bidirectional"))
      (node (ref "D405") (pin "1") (pinfunction "RED_1") (pintype "bidirectional"))
      (node (ref "D406") (pin "1") (pinfunction "RED_1") (pintype "bidirectional"))
      (node (ref "D407") (pin "1") (pinfunction "RED_1") (pintype "bidirectional"))
      (node (ref "D408") (pin "1") (pinfunction "RED_1") (pintype "bidirectional"))
      (node (ref "D409") (pin "1") (pinfunction "RED_1") (pintype "bidirectional"))
      (node (ref "D410") (pin "1") (pinfunction "RED_1") (pintype "bidirectional"))
      (node (ref "D411") (pin "1") (pinfunction "RED_1") (pintype "bidirectional"))
      (node (ref "D412") (pin "1") (pinfunction "RED_1") (pintype "bidirectional"))
      (node (ref "D413") (pin "1") (pinfunction "RED_1") (pintype "bidirectional"))
      (node (ref "D414") (pin "1") (pinfunction "RED_1") (pintype "bidirectional"))
      (node (ref "D415") (pin "1") (pinfunction "RED_1") (pintype "bidirectional"))
      (node (ref "D416") (pin "1") (pinfunction "RED_1") (pintype "bidirectional"))
      (node (ref "D417") (pin "1") (pinfunction "RED_1") (pintype "bidirectional"))
      (node (ref "D418") (pin "1") (pinfunction "RED_1") (pintype "bidirectional"))
      (node (ref "D419") (pin "1") (pinfunction "RED_1") (pintype "bidirectional"))
      (node (ref "D420") (pin "1") (pinfunction "RED_1") (pintype "bidirectional"))
      (node (ref "D421") (pin "1") (pinfunction "RED_1") (pintype "bidirectional"))
      (node (ref "D422") (pin "1") (pinfunction "RED_1") (pintype "bidirectional"))
      (node (ref "D423") (pin "1") (pinfunction "RED_1") (pintype "bidirectional"))
      (node (ref "D424") (pin "1") (pinfunction "RED_1") (pintype "bidirectional"))
      (node (ref "D425") (pin "1") (pinfunction "RED_1") (pintype "bidirectional"))
      (node (ref "D426") (pin "1") (pinfunction "RED_1") (pintype "bidirectional"))
      (node (ref "D427") (pin "1") (pinfunction "RED_1") (pintype "bidirectional"))
      (node (ref "D428") (pin "1") (pinfunction "RED_1") (pintype "bidirectional"))
      (node (ref "D429") (pin "1") (pinfunction "RED_1") (pintype "bidirectional"))
      (node (ref "D430") (pin "1") (pinfunction "RED_1") (pintype "bidirectional"))
      (node (ref "D431") (pin "1") (pinfunction "RED_1") (pintype "bidirectional"))
      (node (ref "D432") (pin "1") (pinfunction "RED_1") (pintype "bidirectional"))
      (node (ref "D433") (pin "1") (pinfunction "RED_1") (pintype "bidirectional"))
      (node (ref "D434") (pin "1") (pinfunction "RED_1") (pintype "bidirectional"))
      (node (ref "D435") (pin "1") (pinfunction "RED_1") (pintype "bidirectional"))
      (node (ref "D436") (pin "1") (pinfunction "RED_1") (pintype "bidirectional"))
      (node (ref "D437") (pin "1") (pinfunction "RED_1") (pintype "bidirectional"))
      (node (ref "D438") (pin "1") (pinfunction "RED_1") (pintype "bidirectional"))
      (node (ref "D439") (pin "1") (pinfunction "RED_1") (pintype "bidirectional"))
      (node (ref "D440") (pin "1") (pinfunction "RED_1") (pintype "bidirectional"))
      (node (ref "D441") (pin "1") (pinfunction "RED_1") (pintype "bidirectional"))
      (node (ref "D442") (pin "1") (pinfunction "RED_1") (pintype "bidirectional"))
      (node (ref "D443") (pin "1") (pinfunction "RED_1") (pintype "bidirectional"))
      (node (ref "D444") (pin "1") (pinfunction "RED_1") (pintype "bidirectional"))
      (node (ref "D445") (pin "1") (pinfunction "RED_1") (pintype "bidirectional"))
      (node (ref "D446") (pin "1") (pinfunction "RED_1") (pintype "bidirectional"))
      (node (ref "D447") (pin "1") (pinfunction "RED_1") (pintype "bidirectional"))
      (node (ref "D448") (pin "1") (pinfunction "RED_1") (pintype "bidirectional"))
      (node (ref "Q21") (pin "C") (pinfunction "C_C") (pintype "passive"))
    )
    (net (code "87") (name "Net-(D449-BLU)") (class "Default")
      (node (ref "D449") (pin "4") (pinfunction "BLU_4") (pintype "bidirectional"))
      (node (ref "D450") (pin "4") (pinfunction "BLU_4") (pintype "bidirectional"))
      (node (ref "D451") (pin "4") (pinfunction "BLU_4") (pintype "bidirectional"))
      (node (ref "D452") (pin "4") (pinfunction "BLU_4") (pintype "bidirectional"))
      (node (ref "D453") (pin "4") (pinfunction "BLU_4") (pintype "bidirectional"))
      (node (ref "D454") (pin "4") (pinfunction "BLU_4") (pintype "bidirectional"))
      (node (ref "D455") (pin "4") (pinfunction "BLU_4") (pintype "bidirectional"))
      (node (ref "D456") (pin "4") (pinfunction "BLU_4") (pintype "bidirectional"))
      (node (ref "D457") (pin "4") (pinfunction "BLU_4") (pintype "bidirectional"))
      (node (ref "D458") (pin "4") (pinfunction "BLU_4") (pintype "bidirectional"))
      (node (ref "D459") (pin "4") (pinfunction "BLU_4") (pintype "bidirectional"))
      (node (ref "D460") (pin "4") (pinfunction "BLU_4") (pintype "bidirectional"))
      (node (ref "D461") (pin "4") (pinfunction "BLU_4") (pintype "bidirectional"))
      (node (ref "D462") (pin "4") (pinfunction "BLU_4") (pintype "bidirectional"))
      (node (ref "D463") (pin "4") (pinfunction "BLU_4") (pintype "bidirectional"))
      (node (ref "D464") (pin "4") (pinfunction "BLU_4") (pintype "bidirectional"))
      (node (ref "D465") (pin "4") (pinfunction "BLU_4") (pintype "bidirectional"))
      (node (ref "D466") (pin "4") (pinfunction "BLU_4") (pintype "bidirectional"))
      (node (ref "D467") (pin "4") (pinfunction "BLU_4") (pintype "bidirectional"))
      (node (ref "D468") (pin "4") (pinfunction "BLU_4") (pintype "bidirectional"))
      (node (ref "D469") (pin "4") (pinfunction "BLU_4") (pintype "bidirectional"))
      (node (ref "D470") (pin "4") (pinfunction "BLU_4") (pintype "bidirectional"))
      (node (ref "D471") (pin "4") (pinfunction "BLU_4") (pintype "bidirectional"))
      (node (ref "D472") (pin "4") (pinfunction "BLU_4") (pintype "bidirectional"))
      (node (ref "D473") (pin "4") (pinfunction "BLU_4") (pintype "bidirectional"))
      (node (ref "D474") (pin "4") (pinfunction "BLU_4") (pintype "bidirectional"))
      (node (ref "D475") (pin "4") (pinfunction "BLU_4") (pintype "bidirectional"))
      (node (ref "D476") (pin "4") (pinfunction "BLU_4") (pintype "bidirectional"))
      (node (ref "D477") (pin "4") (pinfunction "BLU_4") (pintype "bidirectional"))
      (node (ref "D478") (pin "4") (pinfunction "BLU_4") (pintype "bidirectional"))
      (node (ref "D479") (pin "4") (pinfunction "BLU_4") (pintype "bidirectional"))
      (node (ref "D480") (pin "4") (pinfunction "BLU_4") (pintype "bidirectional"))
      (node (ref "D481") (pin "4") (pinfunction "BLU_4") (pintype "bidirectional"))
      (node (ref "D482") (pin "4") (pinfunction "BLU_4") (pintype "bidirectional"))
      (node (ref "D483") (pin "4") (pinfunction "BLU_4") (pintype "bidirectional"))
      (node (ref "D484") (pin "4") (pinfunction "BLU_4") (pintype "bidirectional"))
      (node (ref "D485") (pin "4") (pinfunction "BLU_4") (pintype "bidirectional"))
      (node (ref "D486") (pin "4") (pinfunction "BLU_4") (pintype "bidirectional"))
      (node (ref "D487") (pin "4") (pinfunction "BLU_4") (pintype "bidirectional"))
      (node (ref "D488") (pin "4") (pinfunction "BLU_4") (pintype "bidirectional"))
      (node (ref "D489") (pin "4") (pinfunction "BLU_4") (pintype "bidirectional"))
      (node (ref "D490") (pin "4") (pinfunction "BLU_4") (pintype "bidirectional"))
      (node (ref "D491") (pin "4") (pinfunction "BLU_4") (pintype "bidirectional"))
      (node (ref "D492") (pin "4") (pinfunction "BLU_4") (pintype "bidirectional"))
      (node (ref "D493") (pin "4") (pinfunction "BLU_4") (pintype "bidirectional"))
      (node (ref "D494") (pin "4") (pinfunction "BLU_4") (pintype "bidirectional"))
      (node (ref "D495") (pin "4") (pinfunction "BLU_4") (pintype "bidirectional"))
      (node (ref "D496") (pin "4") (pinfunction "BLU_4") (pintype "bidirectional"))
      (node (ref "D497") (pin "4") (pinfunction "BLU_4") (pintype "bidirectional"))
      (node (ref "D498") (pin "4") (pinfunction "BLU_4") (pintype "bidirectional"))
      (node (ref "D499") (pin "4") (pinfunction "BLU_4") (pintype "bidirectional"))
      (node (ref "D500") (pin "4") (pinfunction "BLU_4") (pintype "bidirectional"))
      (node (ref "D501") (pin "4") (pinfunction "BLU_4") (pintype "bidirectional"))
      (node (ref "D502") (pin "4") (pinfunction "BLU_4") (pintype "bidirectional"))
      (node (ref "D503") (pin "4") (pinfunction "BLU_4") (pintype "bidirectional"))
      (node (ref "D504") (pin "4") (pinfunction "BLU_4") (pintype "bidirectional"))
      (node (ref "D505") (pin "4") (pinfunction "BLU_4") (pintype "bidirectional"))
      (node (ref "D506") (pin "4") (pinfunction "BLU_4") (pintype "bidirectional"))
      (node (ref "D507") (pin "4") (pinfunction "BLU_4") (pintype "bidirectional"))
      (node (ref "D508") (pin "4") (pinfunction "BLU_4") (pintype "bidirectional"))
      (node (ref "D509") (pin "4") (pinfunction "BLU_4") (pintype "bidirectional"))
      (node (ref "D510") (pin "4") (pinfunction "BLU_4") (pintype "bidirectional"))
      (node (ref "D511") (pin "4") (pinfunction "BLU_4") (pintype "bidirectional"))
      (node (ref "D512") (pin "4") (pinfunction "BLU_4") (pintype "bidirectional"))
      (node (ref "Q23") (pin "C") (pinfunction "C_C") (pintype "passive"))
    )
    (net (code "88") (name "Net-(D449-GRN)") (class "Default")
      (node (ref "D449") (pin "3") (pinfunction "GRN_3") (pintype "bidirectional"))
      (node (ref "D450") (pin "3") (pinfunction "GRN_3") (pintype "bidirectional"))
      (node (ref "D451") (pin "3") (pinfunction "GRN_3") (pintype "bidirectional"))
      (node (ref "D452") (pin "3") (pinfunction "GRN_3") (pintype "bidirectional"))
      (node (ref "D453") (pin "3") (pinfunction "GRN_3") (pintype "bidirectional"))
      (node (ref "D454") (pin "3") (pinfunction "GRN_3") (pintype "bidirectional"))
      (node (ref "D455") (pin "3") (pinfunction "GRN_3") (pintype "bidirectional"))
      (node (ref "D456") (pin "3") (pinfunction "GRN_3") (pintype "bidirectional"))
      (node (ref "D457") (pin "3") (pinfunction "GRN_3") (pintype "bidirectional"))
      (node (ref "D458") (pin "3") (pinfunction "GRN_3") (pintype "bidirectional"))
      (node (ref "D459") (pin "3") (pinfunction "GRN_3") (pintype "bidirectional"))
      (node (ref "D460") (pin "3") (pinfunction "GRN_3") (pintype "bidirectional"))
      (node (ref "D461") (pin "3") (pinfunction "GRN_3") (pintype "bidirectional"))
      (node (ref "D462") (pin "3") (pinfunction "GRN_3") (pintype "bidirectional"))
      (node (ref "D463") (pin "3") (pinfunction "GRN_3") (pintype "bidirectional"))
      (node (ref "D464") (pin "3") (pinfunction "GRN_3") (pintype "bidirectional"))
      (node (ref "D465") (pin "3") (pinfunction "GRN_3") (pintype "bidirectional"))
      (node (ref "D466") (pin "3") (pinfunction "GRN_3") (pintype "bidirectional"))
      (node (ref "D467") (pin "3") (pinfunction "GRN_3") (pintype "bidirectional"))
      (node (ref "D468") (pin "3") (pinfunction "GRN_3") (pintype "bidirectional"))
      (node (ref "D469") (pin "3") (pinfunction "GRN_3") (pintype "bidirectional"))
      (node (ref "D470") (pin "3") (pinfunction "GRN_3") (pintype "bidirectional"))
      (node (ref "D471") (pin "3") (pinfunction "GRN_3") (pintype "bidirectional"))
      (node (ref "D472") (pin "3") (pinfunction "GRN_3") (pintype "bidirectional"))
      (node (ref "D473") (pin "3") (pinfunction "GRN_3") (pintype "bidirectional"))
      (node (ref "D474") (pin "3") (pinfunction "GRN_3") (pintype "bidirectional"))
      (node (ref "D475") (pin "3") (pinfunction "GRN_3") (pintype "bidirectional"))
      (node (ref "D476") (pin "3") (pinfunction "GRN_3") (pintype "bidirectional"))
      (node (ref "D477") (pin "3") (pinfunction "GRN_3") (pintype "bidirectional"))
      (node (ref "D478") (pin "3") (pinfunction "GRN_3") (pintype "bidirectional"))
      (node (ref "D479") (pin "3") (pinfunction "GRN_3") (pintype "bidirectional"))
      (node (ref "D480") (pin "3") (pinfunction "GRN_3") (pintype "bidirectional"))
      (node (ref "D481") (pin "3") (pinfunction "GRN_3") (pintype "bidirectional"))
      (node (ref "D482") (pin "3") (pinfunction "GRN_3") (pintype "bidirectional"))
      (node (ref "D483") (pin "3") (pinfunction "GRN_3") (pintype "bidirectional"))
      (node (ref "D484") (pin "3") (pinfunction "GRN_3") (pintype "bidirectional"))
      (node (ref "D485") (pin "3") (pinfunction "GRN_3") (pintype "bidirectional"))
      (node (ref "D486") (pin "3") (pinfunction "GRN_3") (pintype "bidirectional"))
      (node (ref "D487") (pin "3") (pinfunction "GRN_3") (pintype "bidirectional"))
      (node (ref "D488") (pin "3") (pinfunction "GRN_3") (pintype "bidirectional"))
      (node (ref "D489") (pin "3") (pinfunction "GRN_3") (pintype "bidirectional"))
      (node (ref "D490") (pin "3") (pinfunction "GRN_3") (pintype "bidirectional"))
      (node (ref "D491") (pin "3") (pinfunction "GRN_3") (pintype "bidirectional"))
      (node (ref "D492") (pin "3") (pinfunction "GRN_3") (pintype "bidirectional"))
      (node (ref "D493") (pin "3") (pinfunction "GRN_3") (pintype "bidirectional"))
      (node (ref "D494") (pin "3") (pinfunction "GRN_3") (pintype "bidirectional"))
      (node (ref "D495") (pin "3") (pinfunction "GRN_3") (pintype "bidirectional"))
      (node (ref "D496") (pin "3") (pinfunction "GRN_3") (pintype "bidirectional"))
      (node (ref "D497") (pin "3") (pinfunction "GRN_3") (pintype "bidirectional"))
      (node (ref "D498") (pin "3") (pinfunction "GRN_3") (pintype "bidirectional"))
      (node (ref "D499") (pin "3") (pinfunction "GRN_3") (pintype "bidirectional"))
      (node (ref "D500") (pin "3") (pinfunction "GRN_3") (pintype "bidirectional"))
      (node (ref "D501") (pin "3") (pinfunction "GRN_3") (pintype "bidirectional"))
      (node (ref "D502") (pin "3") (pinfunction "GRN_3") (pintype "bidirectional"))
      (node (ref "D503") (pin "3") (pinfunction "GRN_3") (pintype "bidirectional"))
      (node (ref "D504") (pin "3") (pinfunction "GRN_3") (pintype "bidirectional"))
      (node (ref "D505") (pin "3") (pinfunction "GRN_3") (pintype "bidirectional"))
      (node (ref "D506") (pin "3") (pinfunction "GRN_3") (pintype "bidirectional"))
      (node (ref "D507") (pin "3") (pinfunction "GRN_3") (pintype "bidirectional"))
      (node (ref "D508") (pin "3") (pinfunction "GRN_3") (pintype "bidirectional"))
      (node (ref "D509") (pin "3") (pinfunction "GRN_3") (pintype "bidirectional"))
      (node (ref "D510") (pin "3") (pinfunction "GRN_3") (pintype "bidirectional"))
      (node (ref "D511") (pin "3") (pinfunction "GRN_3") (pintype "bidirectional"))
      (node (ref "D512") (pin "3") (pinfunction "GRN_3") (pintype "bidirectional"))
      (node (ref "Q22") (pin "C") (pinfunction "C_C") (pintype "passive"))
    )
    (net (code "89") (name "Net-(D449-RED)") (class "Default")
      (node (ref "D449") (pin "1") (pinfunction "RED_1") (pintype "bidirectional"))
      (node (ref "D450") (pin "1") (pinfunction "RED_1") (pintype "bidirectional"))
      (node (ref "D451") (pin "1") (pinfunction "RED_1") (pintype "bidirectional"))
      (node (ref "D452") (pin "1") (pinfunction "RED_1") (pintype "bidirectional"))
      (node (ref "D453") (pin "1") (pinfunction "RED_1") (pintype "bidirectional"))
      (node (ref "D454") (pin "1") (pinfunction "RED_1") (pintype "bidirectional"))
      (node (ref "D455") (pin "1") (pinfunction "RED_1") (pintype "bidirectional"))
      (node (ref "D456") (pin "1") (pinfunction "RED_1") (pintype "bidirectional"))
      (node (ref "D457") (pin "1") (pinfunction "RED_1") (pintype "bidirectional"))
      (node (ref "D458") (pin "1") (pinfunction "RED_1") (pintype "bidirectional"))
      (node (ref "D459") (pin "1") (pinfunction "RED_1") (pintype "bidirectional"))
      (node (ref "D460") (pin "1") (pinfunction "RED_1") (pintype "bidirectional"))
      (node (ref "D461") (pin "1") (pinfunction "RED_1") (pintype "bidirectional"))
      (node (ref "D462") (pin "1") (pinfunction "RED_1") (pintype "bidirectional"))
      (node (ref "D463") (pin "1") (pinfunction "RED_1") (pintype "bidirectional"))
      (node (ref "D464") (pin "1") (pinfunction "RED_1") (pintype "bidirectional"))
      (node (ref "D465") (pin "1") (pinfunction "RED_1") (pintype "bidirectional"))
      (node (ref "D466") (pin "1") (pinfunction "RED_1") (pintype "bidirectional"))
      (node (ref "D467") (pin "1") (pinfunction "RED_1") (pintype "bidirectional"))
      (node (ref "D468") (pin "1") (pinfunction "RED_1") (pintype "bidirectional"))
      (node (ref "D469") (pin "1") (pinfunction "RED_1") (pintype "bidirectional"))
      (node (ref "D470") (pin "1") (pinfunction "RED_1") (pintype "bidirectional"))
      (node (ref "D471") (pin "1") (pinfunction "RED_1") (pintype "bidirectional"))
      (node (ref "D472") (pin "1") (pinfunction "RED_1") (pintype "bidirectional"))
      (node (ref "D473") (pin "1") (pinfunction "RED_1") (pintype "bidirectional"))
      (node (ref "D474") (pin "1") (pinfunction "RED_1") (pintype "bidirectional"))
      (node (ref "D475") (pin "1") (pinfunction "RED_1") (pintype "bidirectional"))
      (node (ref "D476") (pin "1") (pinfunction "RED_1") (pintype "bidirectional"))
      (node (ref "D477") (pin "1") (pinfunction "RED_1") (pintype "bidirectional"))
      (node (ref "D478") (pin "1") (pinfunction "RED_1") (pintype "bidirectional"))
      (node (ref "D479") (pin "1") (pinfunction "RED_1") (pintype "bidirectional"))
      (node (ref "D480") (pin "1") (pinfunction "RED_1") (pintype "bidirectional"))
      (node (ref "D481") (pin "1") (pinfunction "RED_1") (pintype "bidirectional"))
      (node (ref "D482") (pin "1") (pinfunction "RED_1") (pintype "bidirectional"))
      (node (ref "D483") (pin "1") (pinfunction "RED_1") (pintype "bidirectional"))
      (node (ref "D484") (pin "1") (pinfunction "RED_1") (pintype "bidirectional"))
      (node (ref "D485") (pin "1") (pinfunction "RED_1") (pintype "bidirectional"))
      (node (ref "D486") (pin "1") (pinfunction "RED_1") (pintype "bidirectional"))
      (node (ref "D487") (pin "1") (pinfunction "RED_1") (pintype "bidirectional"))
      (node (ref "D488") (pin "1") (pinfunction "RED_1") (pintype "bidirectional"))
      (node (ref "D489") (pin "1") (pinfunction "RED_1") (pintype "bidirectional"))
      (node (ref "D490") (pin "1") (pinfunction "RED_1") (pintype "bidirectional"))
      (node (ref "D491") (pin "1") (pinfunction "RED_1") (pintype "bidirectional"))
      (node (ref "D492") (pin "1") (pinfunction "RED_1") (pintype "bidirectional"))
      (node (ref "D493") (pin "1") (pinfunction "RED_1") (pintype "bidirectional"))
      (node (ref "D494") (pin "1") (pinfunction "RED_1") (pintype "bidirectional"))
      (node (ref "D495") (pin "1") (pinfunction "RED_1") (pintype "bidirectional"))
      (node (ref "D496") (pin "1") (pinfunction "RED_1") (pintype "bidirectional"))
      (node (ref "D497") (pin "1") (pinfunction "RED_1") (pintype "bidirectional"))
      (node (ref "D498") (pin "1") (pinfunction "RED_1") (pintype "bidirectional"))
      (node (ref "D499") (pin "1") (pinfunction "RED_1") (pintype "bidirectional"))
      (node (ref "D500") (pin "1") (pinfunction "RED_1") (pintype "bidirectional"))
      (node (ref "D501") (pin "1") (pinfunction "RED_1") (pintype "bidirectional"))
      (node (ref "D502") (pin "1") (pinfunction "RED_1") (pintype "bidirectional"))
      (node (ref "D503") (pin "1") (pinfunction "RED_1") (pintype "bidirectional"))
      (node (ref "D504") (pin "1") (pinfunction "RED_1") (pintype "bidirectional"))
      (node (ref "D505") (pin "1") (pinfunction "RED_1") (pintype "bidirectional"))
      (node (ref "D506") (pin "1") (pinfunction "RED_1") (pintype "bidirectional"))
      (node (ref "D507") (pin "1") (pinfunction "RED_1") (pintype "bidirectional"))
      (node (ref "D508") (pin "1") (pinfunction "RED_1") (pintype "bidirectional"))
      (node (ref "D509") (pin "1") (pinfunction "RED_1") (pintype "bidirectional"))
      (node (ref "D510") (pin "1") (pinfunction "RED_1") (pintype "bidirectional"))
      (node (ref "D511") (pin "1") (pinfunction "RED_1") (pintype "bidirectional"))
      (node (ref "D512") (pin "1") (pinfunction "RED_1") (pintype "bidirectional"))
      (node (ref "Q24") (pin "C") (pinfunction "C_C") (pintype "passive"))
    )
    (net (code "90") (name "Net-(IC1A-DO)") (class "Default")
      (node (ref "IC1") (pin "18") (pinfunction "DO_18") (pintype "output"))
      (node (ref "IC2") (pin "3") (pinfunction "DI_3") (pintype "input"))
    )
    (net (code "91") (name "Net-(IC1A-Q0)") (class "Default")
      (node (ref "IC1") (pin "4") (pinfunction "Q0_4") (pintype "open_collector"))
      (node (ref "R1") (pin "1") (pinfunction "1_1") (pintype "passive"))
    )
    (net (code "92") (name "Net-(IC1A-Q1)") (class "Default")
      (node (ref "IC1") (pin "5") (pinfunction "Q1_5") (pintype "open_collector"))
      (node (ref "R2") (pin "1") (pinfunction "1_1") (pintype "passive"))
    )
    (net (code "93") (name "Net-(IC1A-Q2)") (class "Default")
      (node (ref "IC1") (pin "6") (pinfunction "Q2_6") (pintype "open_collector"))
      (node (ref "R3") (pin "1") (pinfunction "1_1") (pintype "passive"))
    )
    (net (code "94") (name "Net-(IC1A-Q3)") (class "Default")
      (node (ref "IC1") (pin "7") (pinfunction "Q3_7") (pintype "open_collector"))
      (node (ref "R4") (pin "1") (pinfunction "1_1") (pintype "passive"))
    )
    (net (code "95") (name "Net-(IC1A-Q4)") (class "Default")
      (node (ref "IC1") (pin "14") (pinfunction "Q4_14") (pintype "open_collector"))
      (node (ref "R5") (pin "1") (pinfunction "1_1") (pintype "passive"))
    )
    (net (code "96") (name "Net-(IC1A-Q5)") (class "Default")
      (node (ref "IC1") (pin "15") (pinfunction "Q5_15") (pintype "open_collector"))
      (node (ref "R6") (pin "1") (pinfunction "1_1") (pintype "passive"))
    )
    (net (code "97") (name "Net-(IC1A-Q6)") (class "Default")
      (node (ref "IC1") (pin "16") (pinfunction "Q6_16") (pintype "open_collector"))
      (node (ref "R7") (pin "1") (pinfunction "1_1") (pintype "passive"))
    )
    (net (code "98") (name "Net-(IC1A-Q7)") (class "Default")
      (node (ref "IC1") (pin "17") (pinfunction "Q7_17") (pintype "open_collector"))
      (node (ref "R8") (pin "1") (pinfunction "1_1") (pintype "passive"))
    )
    (net (code "99") (name "Net-(IC1A-RCK)") (class "Default")
      (node (ref "IC1") (pin "12") (pinfunction "RCK_12") (pintype "input"))
      (node (ref "IC2") (pin "12") (pinfunction "RCK_12") (pintype "input"))
      (node (ref "IC3") (pin "12") (pinfunction "RCK_12") (pintype "input"))
      (node (ref "IC4") (pin "12") (pinfunction "RCK_12") (pintype "input"))
      (node (ref "IC5") (pin "12") (pinfunction "RCK_12") (pintype "input"))
      (node (ref "IC6") (pin "12") (pinfunction "RCK_12") (pintype "input"))
      (node (ref "IC7") (pin "12") (pinfunction "RCK_12") (pintype "input"))
      (node (ref "IC8") (pin "12") (pinfunction "RCK_12") (pintype "input"))
    )
    (net (code "100") (name "Net-(IC1A-SCK)") (class "Default")
      (node (ref "IC1") (pin "13") (pinfunction "SCK_13") (pintype "input"))
      (node (ref "IC2") (pin "13") (pinfunction "SCK_13") (pintype "input"))
      (node (ref "IC3") (pin "13") (pinfunction "SCK_13") (pintype "input"))
      (node (ref "IC4") (pin "13") (pinfunction "SCK_13") (pintype "input"))
      (node (ref "IC5") (pin "13") (pinfunction "SCK_13") (pintype "input"))
      (node (ref "IC6") (pin "13") (pinfunction "SCK_13") (pintype "input"))
      (node (ref "IC7") (pin "13") (pinfunction "SCK_13") (pintype "input"))
      (node (ref "IC8") (pin "13") (pinfunction "SCK_13") (pintype "input"))
    )
    (net (code "101") (name "Net-(IC2A-DO)") (class "Default")
      (node (ref "IC2") (pin "18") (pinfunction "DO_18") (pintype "output"))
      (node (ref "IC3") (pin "3") (pinfunction "DI_3") (pintype "input"))
    )
    (net (code "102") (name "Net-(IC2A-Q0)") (class "Default")
      (node (ref "IC2") (pin "4") (pinfunction "Q0_4") (pintype "open_collector"))
      (node (ref "R9") (pin "1") (pinfunction "1_1") (pintype "passive"))
    )
    (net (code "103") (name "Net-(IC2A-Q1)") (class "Default")
      (node (ref "IC2") (pin "5") (pinfunction "Q1_5") (pintype "open_collector"))
      (node (ref "R10") (pin "1") (pinfunction "1_1") (pintype "passive"))
    )
    (net (code "104") (name "Net-(IC2A-Q2)") (class "Default")
      (node (ref "IC2") (pin "6") (pinfunction "Q2_6") (pintype "open_collector"))
      (node (ref "R11") (pin "1") (pinfunction "1_1") (pintype "passive"))
    )
    (net (code "105") (name "Net-(IC2A-Q3)") (class "Default")
      (node (ref "IC2") (pin "7") (pinfunction "Q3_7") (pintype "open_collector"))
      (node (ref "R12") (pin "1") (pinfunction "1_1") (pintype "passive"))
    )
    (net (code "106") (name "Net-(IC2A-Q4)") (class "Default")
      (node (ref "IC2") (pin "14") (pinfunction "Q4_14") (pintype "open_collector"))
      (node (ref "R13") (pin "1") (pinfunction "1_1") (pintype "passive"))
    )
    (net (code "107") (name "Net-(IC2A-Q5)") (class "Default")
      (node (ref "IC2") (pin "15") (pinfunction "Q5_15") (pintype "open_collector"))
      (node (ref "R14") (pin "1") (pinfunction "1_1") (pintype "passive"))
    )
    (net (code "108") (name "Net-(IC2A-Q6)") (class "Default")
      (node (ref "IC2") (pin "16") (pinfunction "Q6_16") (pintype "open_collector"))
      (node (ref "R15") (pin "1") (pinfunction "1_1") (pintype "passive"))
    )
    (net (code "109") (name "Net-(IC2A-Q7)") (class "Default")
      (node (ref "IC2") (pin "17") (pinfunction "Q7_17") (pintype "open_collector"))
      (node (ref "R16") (pin "1") (pinfunction "1_1") (pintype "passive"))
    )
    (net (code "110") (name "Net-(IC3A-DO)") (class "Default")
      (node (ref "IC3") (pin "18") (pinfunction "DO_18") (pintype "output"))
      (node (ref "IC4") (pin "3") (pinfunction "DI_3") (pintype "input"))
    )
    (net (code "111") (name "Net-(IC3A-Q0)") (class "Default")
      (node (ref "IC3") (pin "4") (pinfunction "Q0_4") (pintype "open_collector"))
      (node (ref "R17") (pin "1") (pinfunction "1_1") (pintype "passive"))
    )
    (net (code "112") (name "Net-(IC3A-Q1)") (class "Default")
      (node (ref "IC3") (pin "5") (pinfunction "Q1_5") (pintype "open_collector"))
      (node (ref "R18") (pin "1") (pinfunction "1_1") (pintype "passive"))
    )
    (net (code "113") (name "Net-(IC3A-Q2)") (class "Default")
      (node (ref "IC3") (pin "6") (pinfunction "Q2_6") (pintype "open_collector"))
      (node (ref "R19") (pin "1") (pinfunction "1_1") (pintype "passive"))
    )
    (net (code "114") (name "Net-(IC3A-Q3)") (class "Default")
      (node (ref "IC3") (pin "7") (pinfunction "Q3_7") (pintype "open_collector"))
      (node (ref "R20") (pin "1") (pinfunction "1_1") (pintype "passive"))
    )
    (net (code "115") (name "Net-(IC3A-Q4)") (class "Default")
      (node (ref "IC3") (pin "14") (pinfunction "Q4_14") (pintype "open_collector"))
      (node (ref "R21") (pin "1") (pinfunction "1_1") (pintype "passive"))
    )
    (net (code "116") (name "Net-(IC3A-Q5)") (class "Default")
      (node (ref "IC3") (pin "15") (pinfunction "Q5_15") (pintype "open_collector"))
      (node (ref "R22") (pin "1") (pinfunction "1_1") (pintype "passive"))
    )
    (net (code "117") (name "Net-(IC3A-Q6)") (class "Default")
      (node (ref "IC3") (pin "16") (pinfunction "Q6_16") (pintype "open_collector"))
      (node (ref "R23") (pin "1") (pinfunction "1_1") (pintype "passive"))
    )
    (net (code "118") (name "Net-(IC3A-Q7)") (class "Default")
      (node (ref "IC3") (pin "17") (pinfunction "Q7_17") (pintype "open_collector"))
      (node (ref "R24") (pin "1") (pinfunction "1_1") (pintype "passive"))
    )
    (net (code "119") (name "Net-(IC4A-DO)") (class "Default")
      (node (ref "IC4") (pin "18") (pinfunction "DO_18") (pintype "output"))
      (node (ref "IC5") (pin "3") (pinfunction "DI_3") (pintype "input"))
    )
    (net (code "120") (name "Net-(IC4A-Q0)") (class "Default")
      (node (ref "IC4") (pin "4") (pinfunction "Q0_4") (pintype "open_collector"))
      (node (ref "R25") (pin "1") (pinfunction "1_1") (pintype "passive"))
    )
    (net (code "121") (name "Net-(IC4A-Q1)") (class "Default")
      (node (ref "IC4") (pin "5") (pinfunction "Q1_5") (pintype "open_collector"))
      (node (ref "R26") (pin "1") (pinfunction "1_1") (pintype "passive"))
    )
    (net (code "122") (name "Net-(IC4A-Q2)") (class "Default")
      (node (ref "IC4") (pin "6") (pinfunction "Q2_6") (pintype "open_collector"))
      (node (ref "R27") (pin "1") (pinfunction "1_1") (pintype "passive"))
    )
    (net (code "123") (name "Net-(IC4A-Q3)") (class "Default")
      (node (ref "IC4") (pin "7") (pinfunction "Q3_7") (pintype "open_collector"))
      (node (ref "R28") (pin "1") (pinfunction "1_1") (pintype "passive"))
    )
    (net (code "124") (name "Net-(IC4A-Q4)") (class "Default")
      (node (ref "IC4") (pin "14") (pinfunction "Q4_14") (pintype "open_collector"))
      (node (ref "R29") (pin "1") (pinfunction "1_1") (pintype "passive"))
    )
    (net (code "125") (name "Net-(IC4A-Q5)") (class "Default")
      (node (ref "IC4") (pin "15") (pinfunction "Q5_15") (pintype "open_collector"))
      (node (ref "R30") (pin "1") (pinfunction "1_1") (pintype "passive"))
    )
    (net (code "126") (name "Net-(IC4A-Q6)") (class "Default")
      (node (ref "IC4") (pin "16") (pinfunction "Q6_16") (pintype "open_collector"))
      (node (ref "R31") (pin "1") (pinfunction "1_1") (pintype "passive"))
    )
    (net (code "127") (name "Net-(IC4A-Q7)") (class "Default")
      (node (ref "IC4") (pin "17") (pinfunction "Q7_17") (pintype "open_collector"))
      (node (ref "R32") (pin "1") (pinfunction "1_1") (pintype "passive"))
    )
    (net (code "128") (name "Net-(IC5A-DO)") (class "Default")
      (node (ref "IC5") (pin "18") (pinfunction "DO_18") (pintype "output"))
      (node (ref "IC6") (pin "3") (pinfunction "DI_3") (pintype "input"))
    )
    (net (code "129") (name "Net-(IC5A-Q0)") (class "Default")
      (node (ref "IC5") (pin "4") (pinfunction "Q0_4") (pintype "open_collector"))
      (node (ref "R33") (pin "1") (pinfunction "1_1") (pintype "passive"))
    )
    (net (code "130") (name "Net-(IC5A-Q1)") (class "Default")
      (node (ref "IC5") (pin "5") (pinfunction "Q1_5") (pintype "open_collector"))
      (node (ref "R34") (pin "1") (pinfunction "1_1") (pintype "passive"))
    )
    (net (code "131") (name "Net-(IC5A-Q2)") (class "Default")
      (node (ref "IC5") (pin "6") (pinfunction "Q2_6") (pintype "open_collector"))
      (node (ref "R35") (pin "1") (pinfunction "1_1") (pintype "passive"))
    )
    (net (code "132") (name "Net-(IC5A-Q3)") (class "Default")
      (node (ref "IC5") (pin "7") (pinfunction "Q3_7") (pintype "open_collector"))
      (node (ref "R36") (pin "1") (pinfunction "1_1") (pintype "passive"))
    )
    (net (code "133") (name "Net-(IC5A-Q4)") (class "Default")
      (node (ref "IC5") (pin "14") (pinfunction "Q4_14") (pintype "open_collector"))
      (node (ref "R37") (pin "1") (pinfunction "1_1") (pintype "passive"))
    )
    (net (code "134") (name "Net-(IC5A-Q5)") (class "Default")
      (node (ref "IC5") (pin "15") (pinfunction "Q5_15") (pintype "open_collector"))
      (node (ref "R38") (pin "1") (pinfunction "1_1") (pintype "passive"))
    )
    (net (code "135") (name "Net-(IC5A-Q6)") (class "Default")
      (node (ref "IC5") (pin "16") (pinfunction "Q6_16") (pintype "open_collector"))
      (node (ref "R39") (pin "1") (pinfunction "1_1") (pintype "passive"))
    )
    (net (code "136") (name "Net-(IC5A-Q7)") (class "Default")
      (node (ref "IC5") (pin "17") (pinfunction "Q7_17") (pintype "open_collector"))
      (node (ref "R40") (pin "1") (pinfunction "1_1") (pintype "passive"))
    )
    (net (code "137") (name "Net-(IC6A-DO)") (class "Default")
      (node (ref "IC6") (pin "18") (pinfunction "DO_18") (pintype "output"))
      (node (ref "IC7") (pin "3") (pinfunction "DI_3") (pintype "input"))
    )
    (net (code "138") (name "Net-(IC6A-Q0)") (class "Default")
      (node (ref "IC6") (pin "4") (pinfunction "Q0_4") (pintype "open_collector"))
      (node (ref "R41") (pin "1") (pinfunction "1_1") (pintype "passive"))
    )
    (net (code "139") (name "Net-(IC6A-Q1)") (class "Default")
      (node (ref "IC6") (pin "5") (pinfunction "Q1_5") (pintype "open_collector"))
      (node (ref "R42") (pin "1") (pinfunction "1_1") (pintype "passive"))
    )
    (net (code "140") (name "Net-(IC6A-Q2)") (class "Default")
      (node (ref "IC6") (pin "6") (pinfunction "Q2_6") (pintype "open_collector"))
      (node (ref "R43") (pin "1") (pinfunction "1_1") (pintype "passive"))
    )
    (net (code "141") (name "Net-(IC6A-Q3)") (class "Default")
      (node (ref "IC6") (pin "7") (pinfunction "Q3_7") (pintype "open_collector"))
      (node (ref "R44") (pin "1") (pinfunction "1_1") (pintype "passive"))
    )
    (net (code "142") (name "Net-(IC6A-Q4)") (class "Default")
      (node (ref "IC6") (pin "14") (pinfunction "Q4_14") (pintype "open_collector"))
      (node (ref "R45") (pin "1") (pinfunction "1_1") (pintype "passive"))
    )
    (net (code "143") (name "Net-(IC6A-Q5)") (class "Default")
      (node (ref "IC6") (pin "15") (pinfunction "Q5_15") (pintype "open_collector"))
      (node (ref "R46") (pin "1") (pinfunction "1_1") (pintype "passive"))
    )
    (net (code "144") (name "Net-(IC6A-Q6)") (class "Default")
      (node (ref "IC6") (pin "16") (pinfunction "Q6_16") (pintype "open_collector"))
      (node (ref "R47") (pin "1") (pinfunction "1_1") (pintype "passive"))
    )
    (net (code "145") (name "Net-(IC6A-Q7)") (class "Default")
      (node (ref "IC6") (pin "17") (pinfunction "Q7_17") (pintype "open_collector"))
      (node (ref "R48") (pin "1") (pinfunction "1_1") (pintype "passive"))
    )
    (net (code "146") (name "Net-(IC7A-DO)") (class "Default")
      (node (ref "IC7") (pin "18") (pinfunction "DO_18") (pintype "output"))
      (node (ref "IC8") (pin "3") (pinfunction "DI_3") (pintype "input"))
    )
    (net (code "147") (name "Net-(IC7A-Q0)") (class "Default")
      (node (ref "IC7") (pin "4") (pinfunction "Q0_4") (pintype "open_collector"))
      (node (ref "R49") (pin "1") (pinfunction "1_1") (pintype "passive"))
    )
    (net (code "148") (name "Net-(IC7A-Q1)") (class "Default")
      (node (ref "IC7") (pin "5") (pinfunction "Q1_5") (pintype "open_collector"))
      (node (ref "R50") (pin "1") (pinfunction "1_1") (pintype "passive"))
    )
    (net (code "149") (name "Net-(IC7A-Q2)") (class "Default")
      (node (ref "IC7") (pin "6") (pinfunction "Q2_6") (pintype "open_collector"))
      (node (ref "R51") (pin "1") (pinfunction "1_1") (pintype "passive"))
    )
    (net (code "150") (name "Net-(IC7A-Q3)") (class "Default")
      (node (ref "IC7") (pin "7") (pinfunction "Q3_7") (pintype "open_collector"))
      (node (ref "R52") (pin "1") (pinfunction "1_1") (pintype "passive"))
    )
    (net (code "151") (name "Net-(IC7A-Q4)") (class "Default")
      (node (ref "IC7") (pin "14") (pinfunction "Q4_14") (pintype "open_collector"))
      (node (ref "R53") (pin "1") (pinfunction "1_1") (pintype "passive"))
    )
    (net (code "152") (name "Net-(IC7A-Q5)") (class "Default")
      (node (ref "IC7") (pin "15") (pinfunction "Q5_15") (pintype "open_collector"))
      (node (ref "R54") (pin "1") (pinfunction "1_1") (pintype "passive"))
    )
    (net (code "153") (name "Net-(IC7A-Q6)") (class "Default")
      (node (ref "IC7") (pin "16") (pinfunction "Q6_16") (pintype "open_collector"))
      (node (ref "R55") (pin "1") (pinfunction "1_1") (pintype "passive"))
    )
    (net (code "154") (name "Net-(IC7A-Q7)") (class "Default")
      (node (ref "IC7") (pin "17") (pinfunction "Q7_17") (pintype "open_collector"))
      (node (ref "R56") (pin "1") (pinfunction "1_1") (pintype "passive"))
    )
    (net (code "155") (name "Net-(IC8A-Q0)") (class "Default")
      (node (ref "IC8") (pin "4") (pinfunction "Q0_4") (pintype "open_collector"))
      (node (ref "R57") (pin "1") (pinfunction "1_1") (pintype "passive"))
    )
    (net (code "156") (name "Net-(IC8A-Q1)") (class "Default")
      (node (ref "IC8") (pin "5") (pinfunction "Q1_5") (pintype "open_collector"))
      (node (ref "R58") (pin "1") (pinfunction "1_1") (pintype "passive"))
    )
    (net (code "157") (name "Net-(IC8A-Q2)") (class "Default")
      (node (ref "IC8") (pin "6") (pinfunction "Q2_6") (pintype "open_collector"))
      (node (ref "R59") (pin "1") (pinfunction "1_1") (pintype "passive"))
    )
    (net (code "158") (name "Net-(IC8A-Q3)") (class "Default")
      (node (ref "IC8") (pin "7") (pinfunction "Q3_7") (pintype "open_collector"))
      (node (ref "R60") (pin "1") (pinfunction "1_1") (pintype "passive"))
    )
    (net (code "159") (name "Net-(IC8A-Q4)") (class "Default")
      (node (ref "IC8") (pin "14") (pinfunction "Q4_14") (pintype "open_collector"))
      (node (ref "R61") (pin "1") (pinfunction "1_1") (pintype "passive"))
    )
    (net (code "160") (name "Net-(IC8A-Q5)") (class "Default")
      (node (ref "IC8") (pin "15") (pinfunction "Q5_15") (pintype "open_collector"))
      (node (ref "R62") (pin "1") (pinfunction "1_1") (pintype "passive"))
    )
    (net (code "161") (name "Net-(IC8A-Q6)") (class "Default")
      (node (ref "IC8") (pin "16") (pinfunction "Q6_16") (pintype "open_collector"))
      (node (ref "R63") (pin "1") (pinfunction "1_1") (pintype "passive"))
    )
    (net (code "162") (name "Net-(IC8A-Q7)") (class "Default")
      (node (ref "IC8") (pin "17") (pinfunction "Q7_17") (pintype "open_collector"))
      (node (ref "R64") (pin "1") (pinfunction "1_1") (pintype "passive"))
    )
    (net (code "163") (name "Net-(Q1-PadE)") (class "Default")
      (node (ref "Q1") (pin "E") (pinfunction "E_E") (pintype "passive"))
      (node (ref "Q2") (pin "E") (pinfunction "E_E") (pintype "passive"))
      (node (ref "Q3") (pin "E") (pinfunction "E_E") (pintype "passive"))
    )
    (net (code "164") (name "Net-(Q4-PadE)") (class "Default")
      (node (ref "Q4") (pin "E") (pinfunction "E_E") (pintype "passive"))
      (node (ref "Q5") (pin "E") (pinfunction "E_E") (pintype "passive"))
      (node (ref "Q6") (pin "E") (pinfunction "E_E") (pintype "passive"))
    )
    (net (code "165") (name "Net-(Q7-PadE)") (class "Default")
      (node (ref "Q7") (pin "E") (pinfunction "E_E") (pintype "passive"))
      (node (ref "Q8") (pin "E") (pinfunction "E_E") (pintype "passive"))
      (node (ref "Q9") (pin "E") (pinfunction "E_E") (pintype "passive"))
    )
    (net (code "166") (name "Net-(Q10-PadE)") (class "Default")
      (node (ref "Q10") (pin "E") (pinfunction "E_E") (pintype "passive"))
      (node (ref "Q11") (pin "E") (pinfunction "E_E") (pintype "passive"))
      (node (ref "Q12") (pin "E") (pinfunction "E_E") (pintype "passive"))
    )
    (net (code "167") (name "Net-(Q13-PadE)") (class "Default")
      (node (ref "Q13") (pin "E") (pinfunction "E_E") (pintype "passive"))
      (node (ref "Q14") (pin "E") (pinfunction "E_E") (pintype "passive"))
      (node (ref "Q15") (pin "E") (pinfunction "E_E") (pintype "passive"))
    )
    (net (code "168") (name "Net-(Q16-PadE)") (class "Default")
      (node (ref "Q16") (pin "E") (pinfunction "E_E") (pintype "passive"))
      (node (ref "Q17") (pin "E") (pinfunction "E_E") (pintype "passive"))
      (node (ref "Q18") (pin "E") (pinfunction "E_E") (pintype "passive"))
    )
    (net (code "169") (name "Net-(Q19-PadE)") (class "Default")
      (node (ref "Q19") (pin "E") (pinfunction "E_E") (pintype "passive"))
      (node (ref "Q20") (pin "E") (pinfunction "E_E") (pintype "passive"))
      (node (ref "Q21") (pin "E") (pinfunction "E_E") (pintype "passive"))
    )
    (net (code "170") (name "Net-(Q22-PadE)") (class "Default")
      (node (ref "Q22") (pin "E") (pinfunction "E_E") (pintype "passive"))
      (node (ref "Q23") (pin "E") (pinfunction "E_E") (pintype "passive"))
      (node (ref "Q24") (pin "E") (pinfunction "E_E") (pintype "passive"))
    )
    (net (code "171") (name "VCC") (class "Default")
      (node (ref "C1") (pin "1") (pinfunction "1_1") (pintype "passive"))
      (node (ref "C2") (pin "1") (pinfunction "1_1") (pintype "passive"))
      (node (ref "C3") (pin "1") (pinfunction "1_1") (pintype "passive"))
      (node (ref "C4") (pin "1") (pinfunction "1_1") (pintype "passive"))
      (node (ref "C5") (pin "1") (pinfunction "1_1") (pintype "passive"))
      (node (ref "C6") (pin "1") (pinfunction "1_1") (pintype "passive"))
      (node (ref "C7") (pin "1") (pinfunction "1_1") (pintype "passive"))
      (node (ref "C8") (pin "1") (pinfunction "1_1") (pintype "passive"))
      (node (ref "IC1") (pin "8") (pinfunction "SCLR_8") (pintype "input"))
      (node (ref "IC2") (pin "8") (pinfunction "SCLR_8") (pintype "input"))
      (node (ref "IC3") (pin "8") (pinfunction "SCLR_8") (pintype "input"))
      (node (ref "IC4") (pin "8") (pinfunction "SCLR_8") (pintype "input"))
      (node (ref "IC5") (pin "8") (pinfunction "SCLR_8") (pintype "input"))
      (node (ref "IC6") (pin "8") (pinfunction "SCLR_8") (pintype "input"))
      (node (ref "IC7") (pin "8") (pinfunction "SCLR_8") (pintype "input"))
      (node (ref "IC8") (pin "8") (pinfunction "SCLR_8") (pintype "input"))
    )
    (net (code "172") (name "unconnected-(IC1A-DI-Pad3)") (class "Default")
      (node (ref "IC1") (pin "3") (pinfunction "DI_3") (pintype "input"))
    )
    (net (code "173") (name "unconnected-(IC8A-DO-Pad18)") (class "Default")
      (node (ref "IC8") (pin "18") (pinfunction "DO_18") (pintype "output"))
    )
    (net (code "174") (name "unconnected-(Q1-PadB)") (class "Default")
      (node (ref "Q1") (pin "B") (pinfunction "B_B") (pintype "passive"))
    )
    (net (code "175") (name "unconnected-(Q2-PadB)") (class "Default")
      (node (ref "Q2") (pin "B") (pinfunction "B_B") (pintype "passive"))
    )
    (net (code "176") (name "unconnected-(Q3-PadB)") (class "Default")
      (node (ref "Q3") (pin "B") (pinfunction "B_B") (pintype "passive"))
    )
    (net (code "177") (name "unconnected-(Q4-PadB)") (class "Default")
      (node (ref "Q4") (pin "B") (pinfunction "B_B") (pintype "passive"))
    )
    (net (code "178") (name "unconnected-(Q5-PadB)") (class "Default")
      (node (ref "Q5") (pin "B") (pinfunction "B_B") (pintype "passive"))
    )
    (net (code "179") (name "unconnected-(Q6-PadB)") (class "Default")
      (node (ref "Q6") (pin "B") (pinfunction "B_B") (pintype "passive"))
    )
    (net (code "180") (name "unconnected-(Q7-PadB)") (class "Default")
      (node (ref "Q7") (pin "B") (pinfunction "B_B") (pintype "passive"))
    )
    (net (code "181") (name "unconnected-(Q8-PadB)") (class "Default")
      (node (ref "Q8") (pin "B") (pinfunction "B_B") (pintype "passive"))
    )
    (net (code "182") (name "unconnected-(Q9-PadB)") (class "Default")
      (node (ref "Q9") (pin "B") (pinfunction "B_B") (pintype "passive"))
    )
    (net (code "183") (name "unconnected-(Q10-PadB)") (class "Default")
      (node (ref "Q10") (pin "B") (pinfunction "B_B") (pintype "passive"))
    )
    (net (code "184") (name "unconnected-(Q11-PadB)") (class "Default")
      (node (ref "Q11") (pin "B") (pinfunction "B_B") (pintype "passive"))
    )
    (net (code "185") (name "unconnected-(Q12-PadB)") (class "Default")
      (node (ref "Q12") (pin "B") (pinfunction "B_B") (pintype "passive"))
    )
    (net (code "186") (name "unconnected-(Q13-PadB)") (class "Default")
      (node (ref "Q13") (pin "B") (pinfunction "B_B") (pintype "passive"))
    )
    (net (code "187") (name "unconnected-(Q14-PadB)") (class "Default")
      (node (ref "Q14") (pin "B") (pinfunction "B_B") (pintype "passive"))
    )
    (net (code "188") (name "unconnected-(Q15-PadB)") (class "Default")
      (node (ref "Q15") (pin "B") (pinfunction "B_B") (pintype "passive"))
    )
    (net (code "189") (name "unconnected-(Q16-PadB)") (class "Default")
      (node (ref "Q16") (pin "B") (pinfunction "B_B") (pintype "passive"))
    )
    (net (code "190") (name "unconnected-(Q17-PadB)") (class "Default")
      (node (ref "Q17") (pin "B") (pinfunction "B_B") (pintype "passive"))
    )
    (net (code "191") (name "unconnected-(Q18-PadB)") (class "Default")
      (node (ref "Q18") (pin "B") (pinfunction "B_B") (pintype "passive"))
    )
    (net (code "192") (name "unconnected-(Q19-PadB)") (class "Default")
      (node (ref "Q19") (pin "B") (pinfunction "B_B") (pintype "passive"))
    )
    (net (code "193") (name "unconnected-(Q20-PadB)") (class "Default")
      (node (ref "Q20") (pin "B") (pinfunction "B_B") (pintype "passive"))
    )
    (net (code "194") (name "unconnected-(Q21-PadB)") (class "Default")
      (node (ref "Q21") (pin "B") (pinfunction "B_B") (pintype "passive"))
    )
    (net (code "195") (name "unconnected-(Q22-PadB)") (class "Default")
      (node (ref "Q22") (pin "B") (pinfunction "B_B") (pintype "passive"))
    )
    (net (code "196") (name "unconnected-(Q23-PadB)") (class "Default")
      (node (ref "Q23") (pin "B") (pinfunction "B_B") (pintype "passive"))
    )
    (net (code "197") (name "unconnected-(Q24-PadB)") (class "Default")
      (node (ref "Q24") (pin "B") (pinfunction "B_B") (pintype "passive"))
    )
  )
)
